# icyradio-main.net
KiCad netlist of a schematic drawn in EAGLE
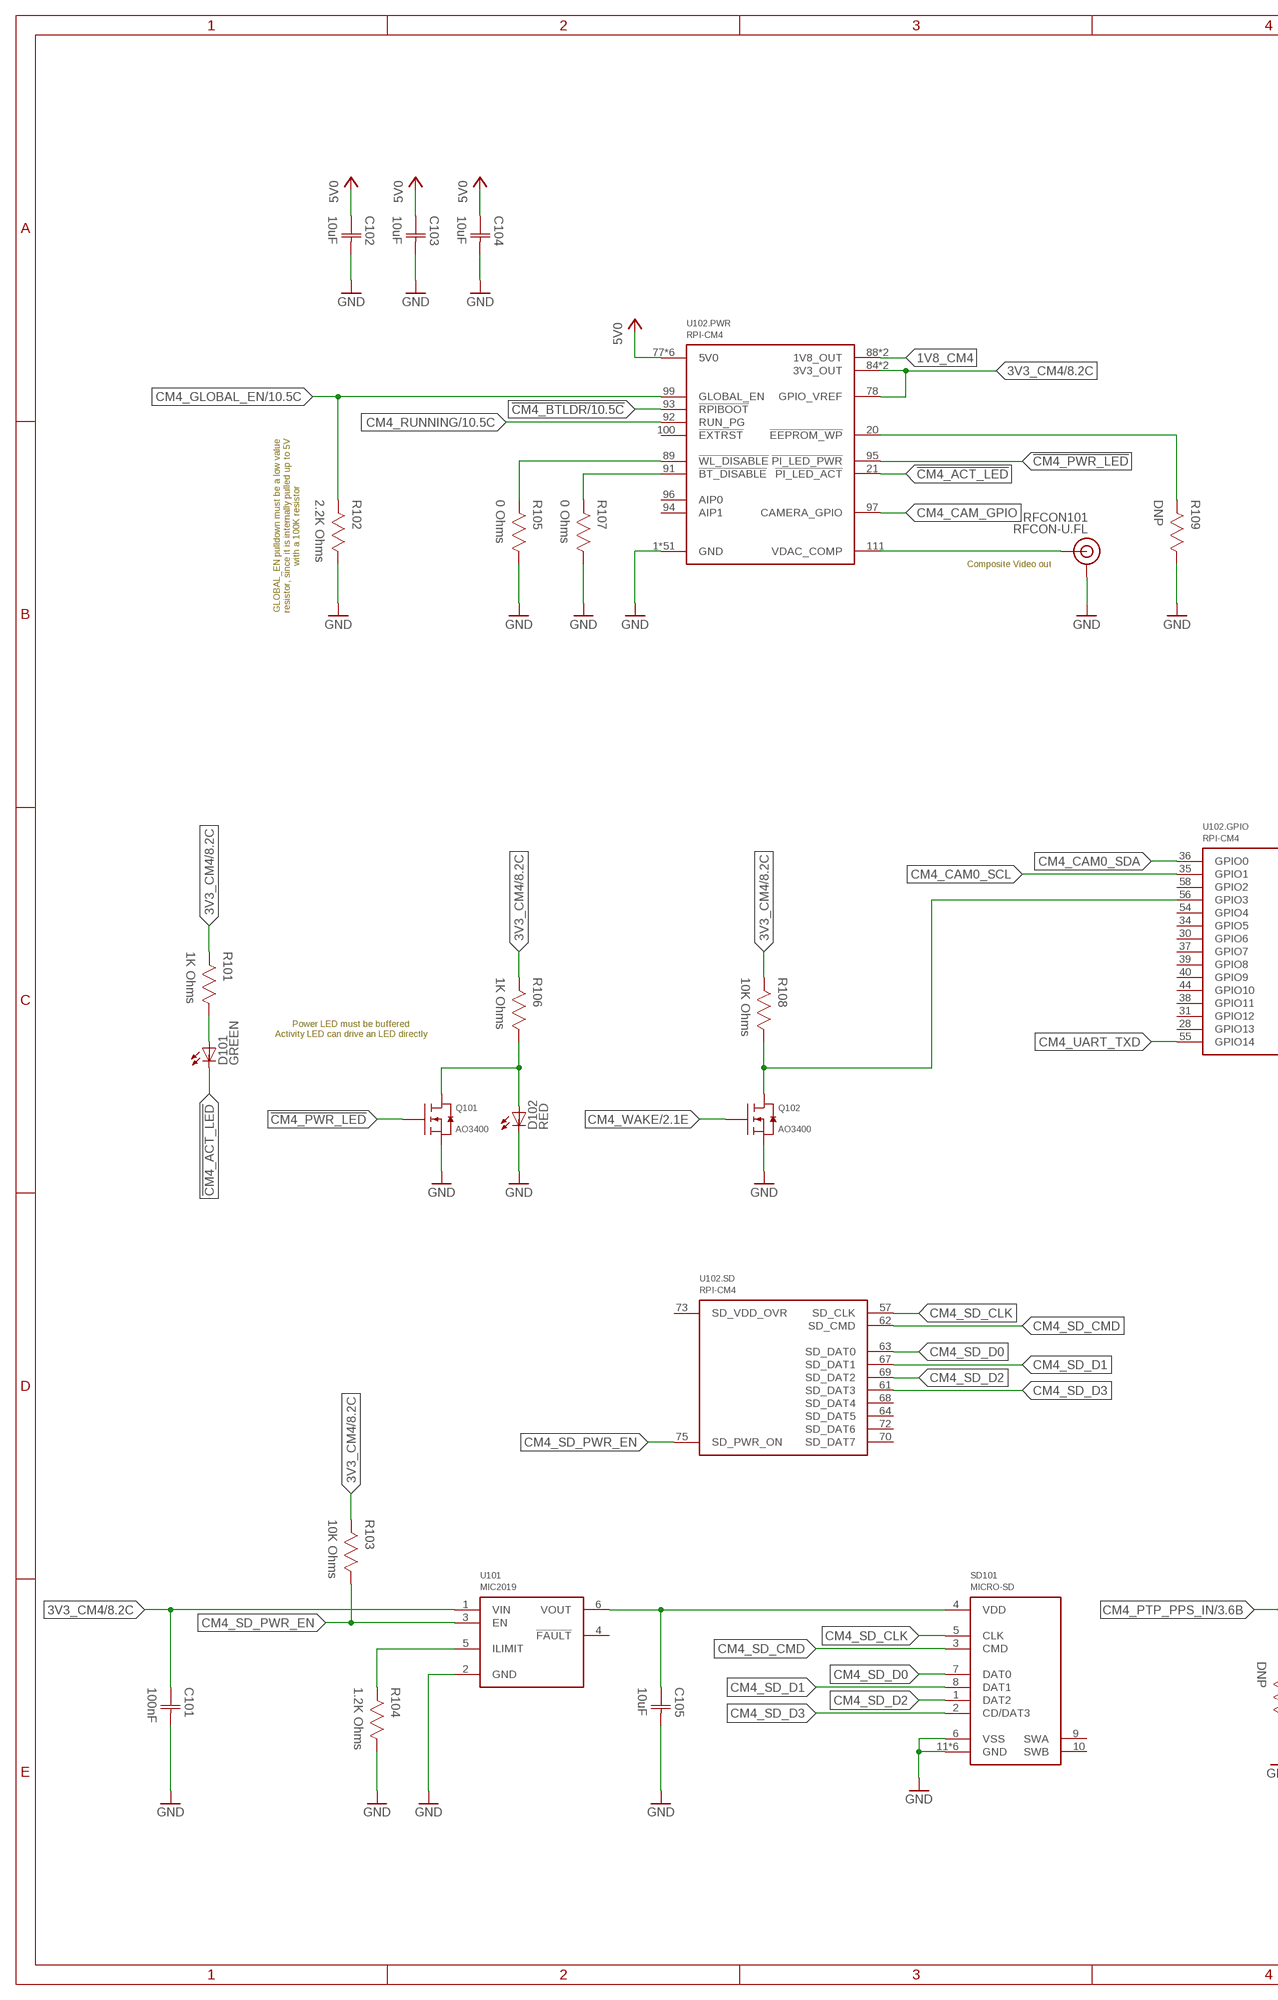
[diagram p0: schematic, sheet 1, part 1 of 2]
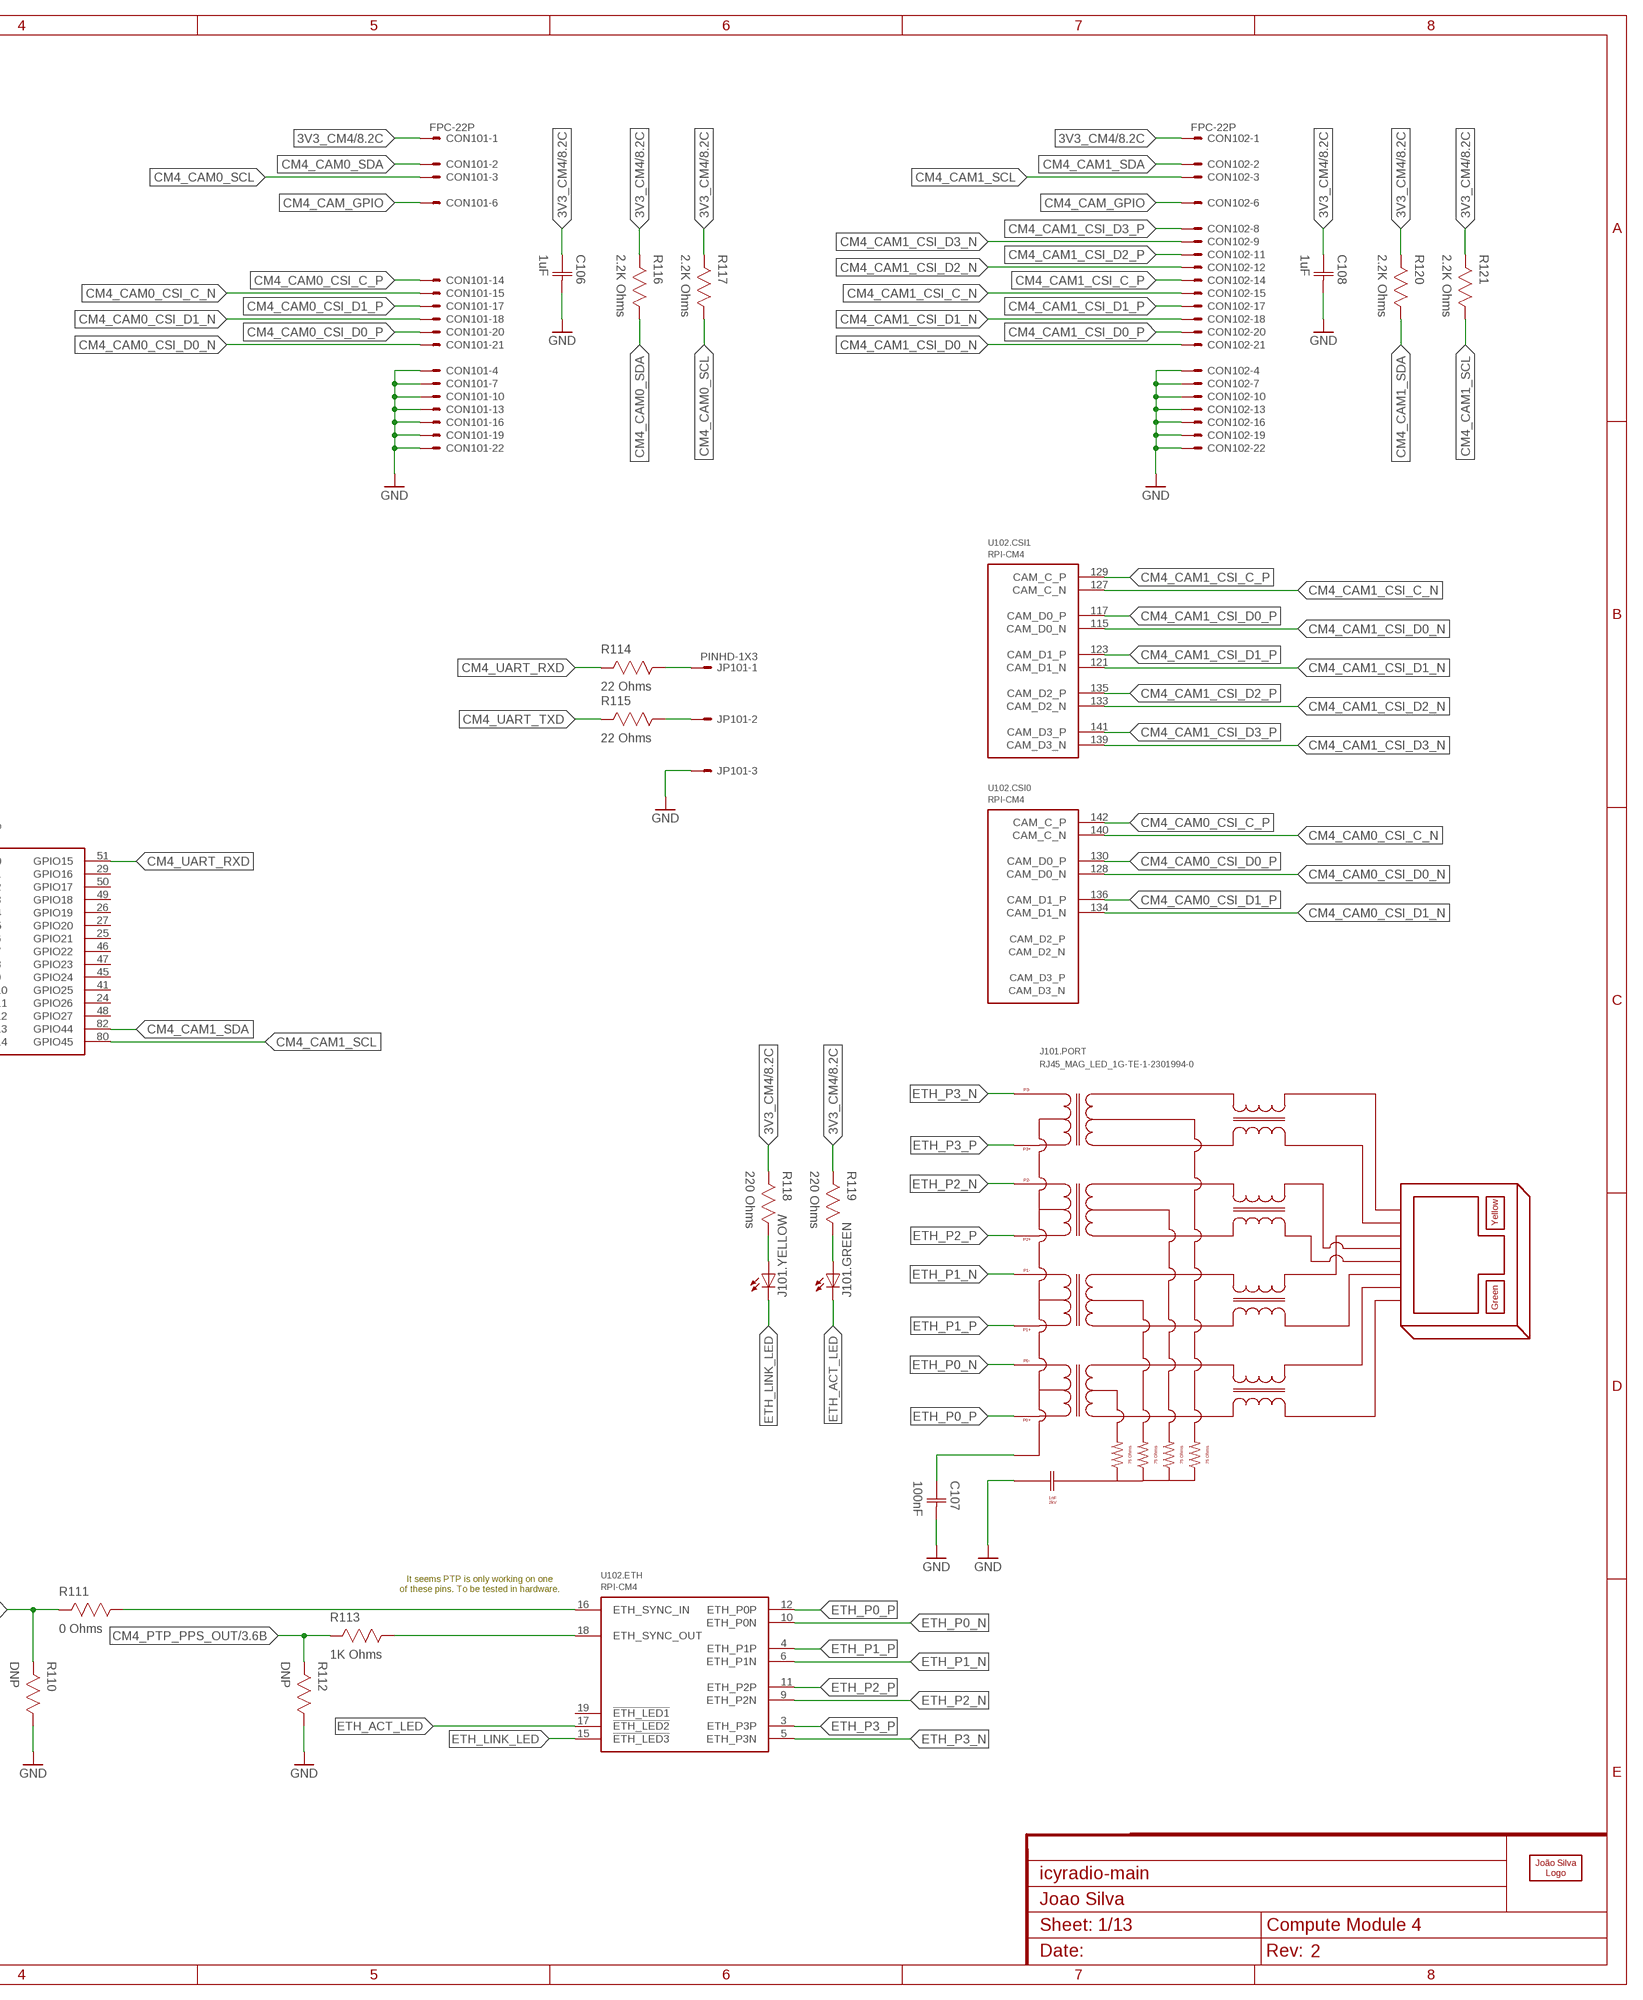
[diagram p1: schematic, sheet 1, part 2 of 2]
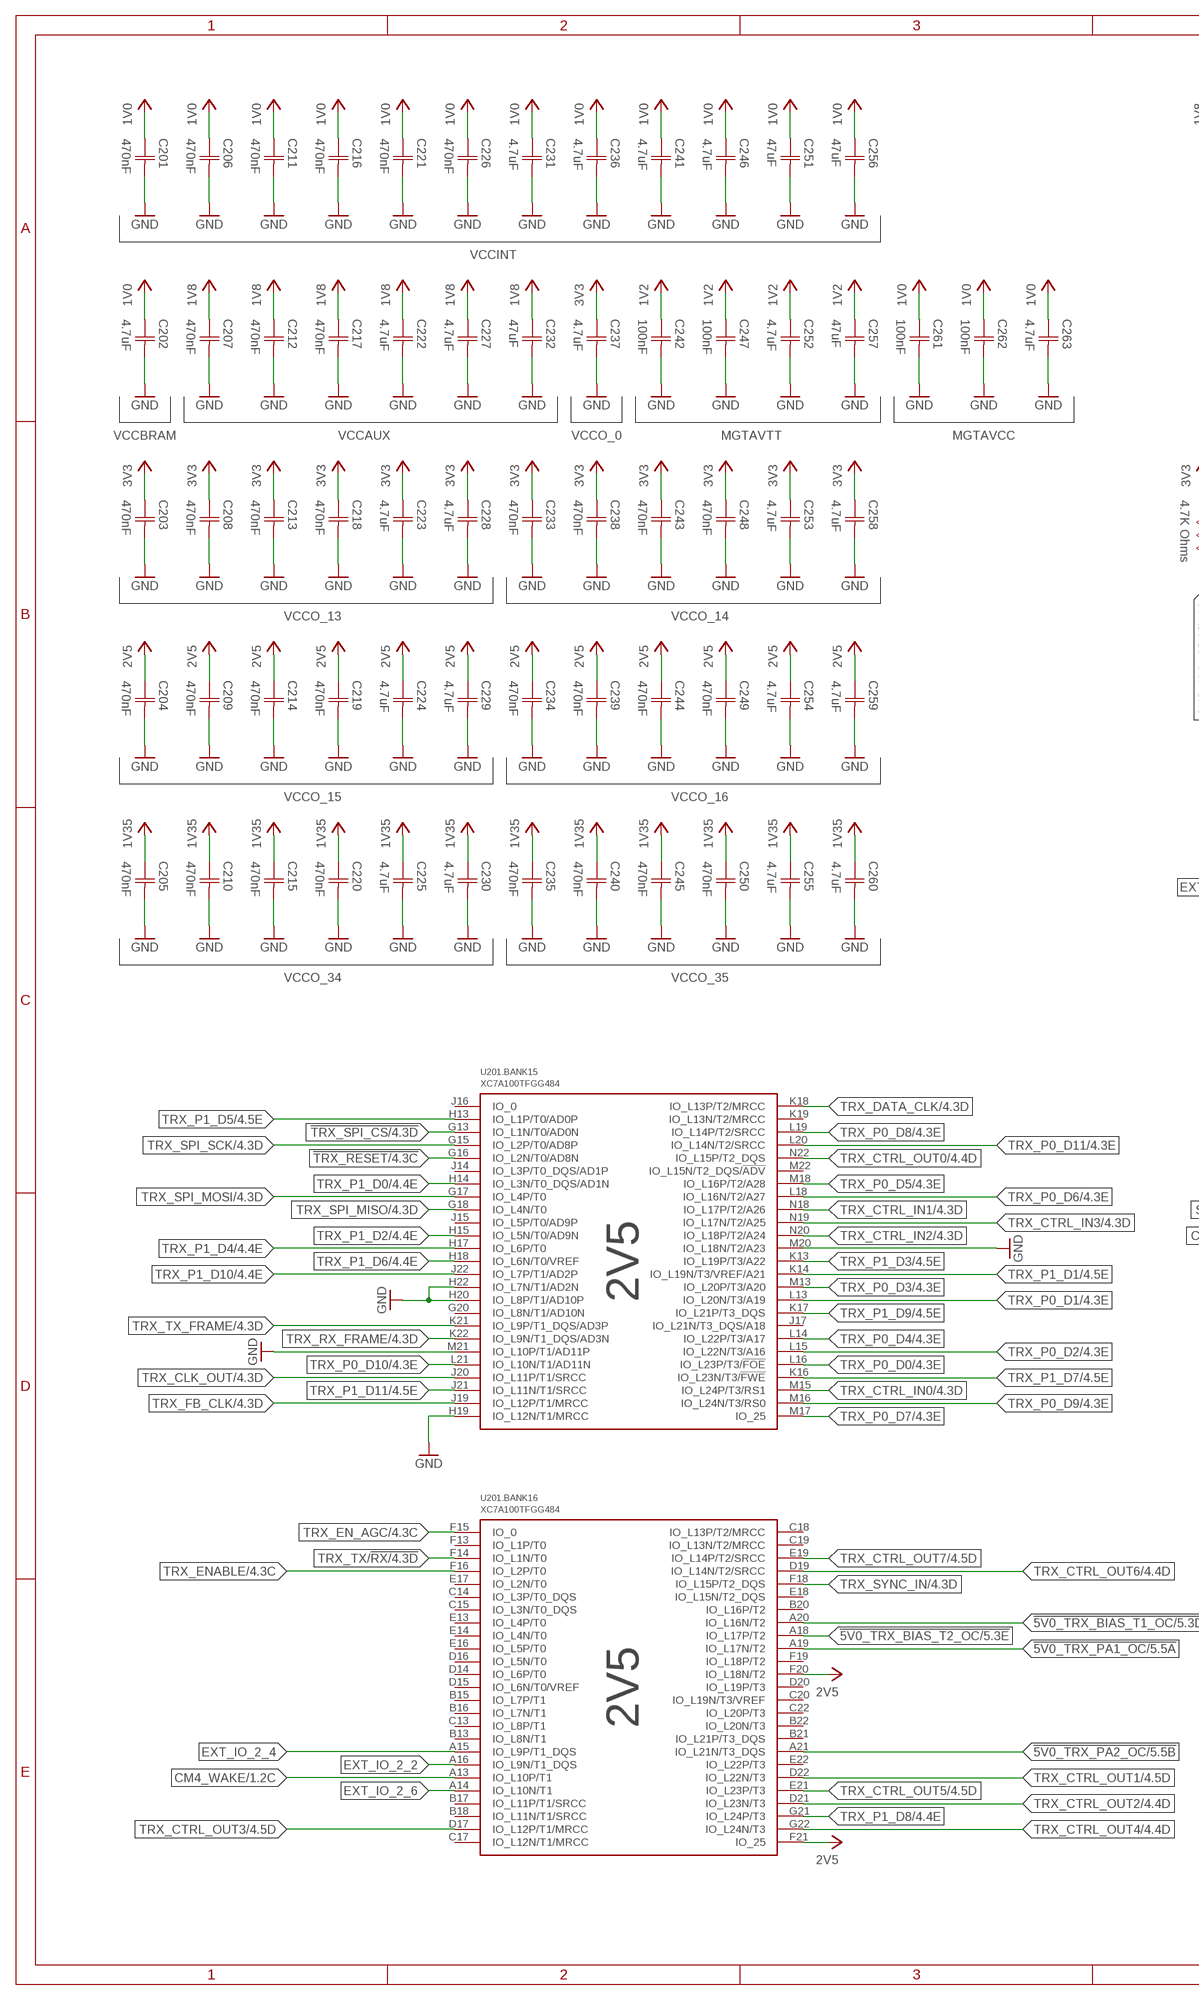
[diagram p2: schematic, sheet 2, part 1 of 2]
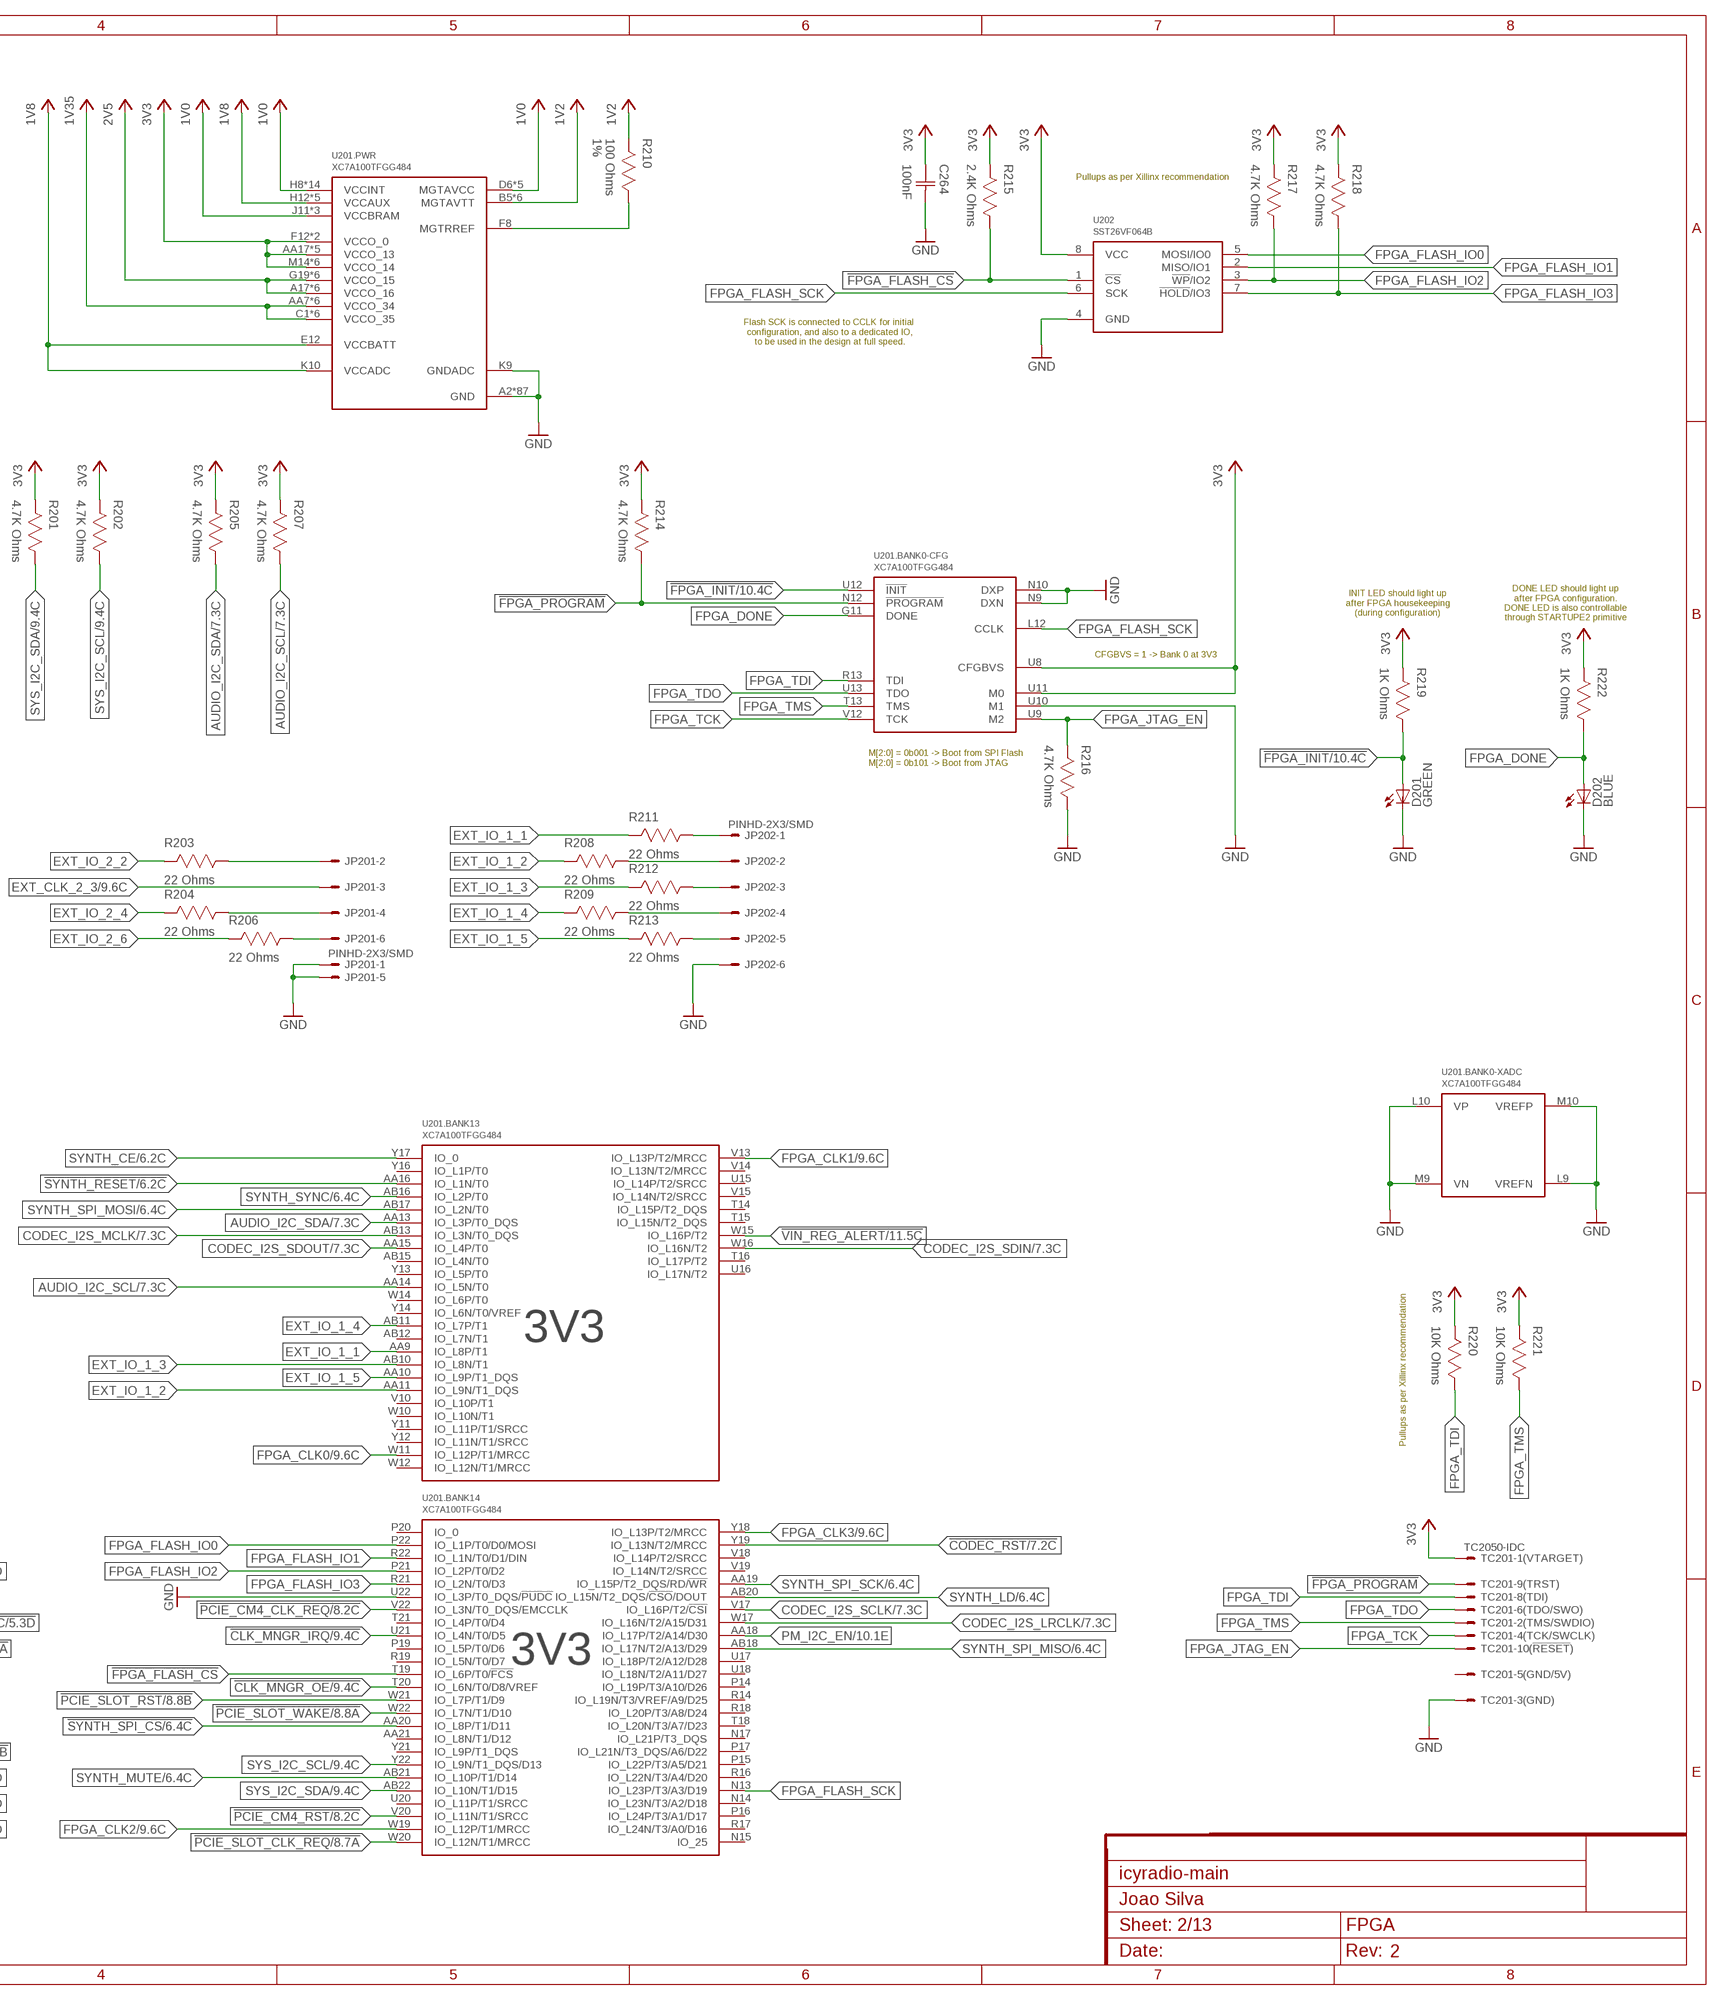
[diagram p3: schematic, sheet 2, part 2 of 2]
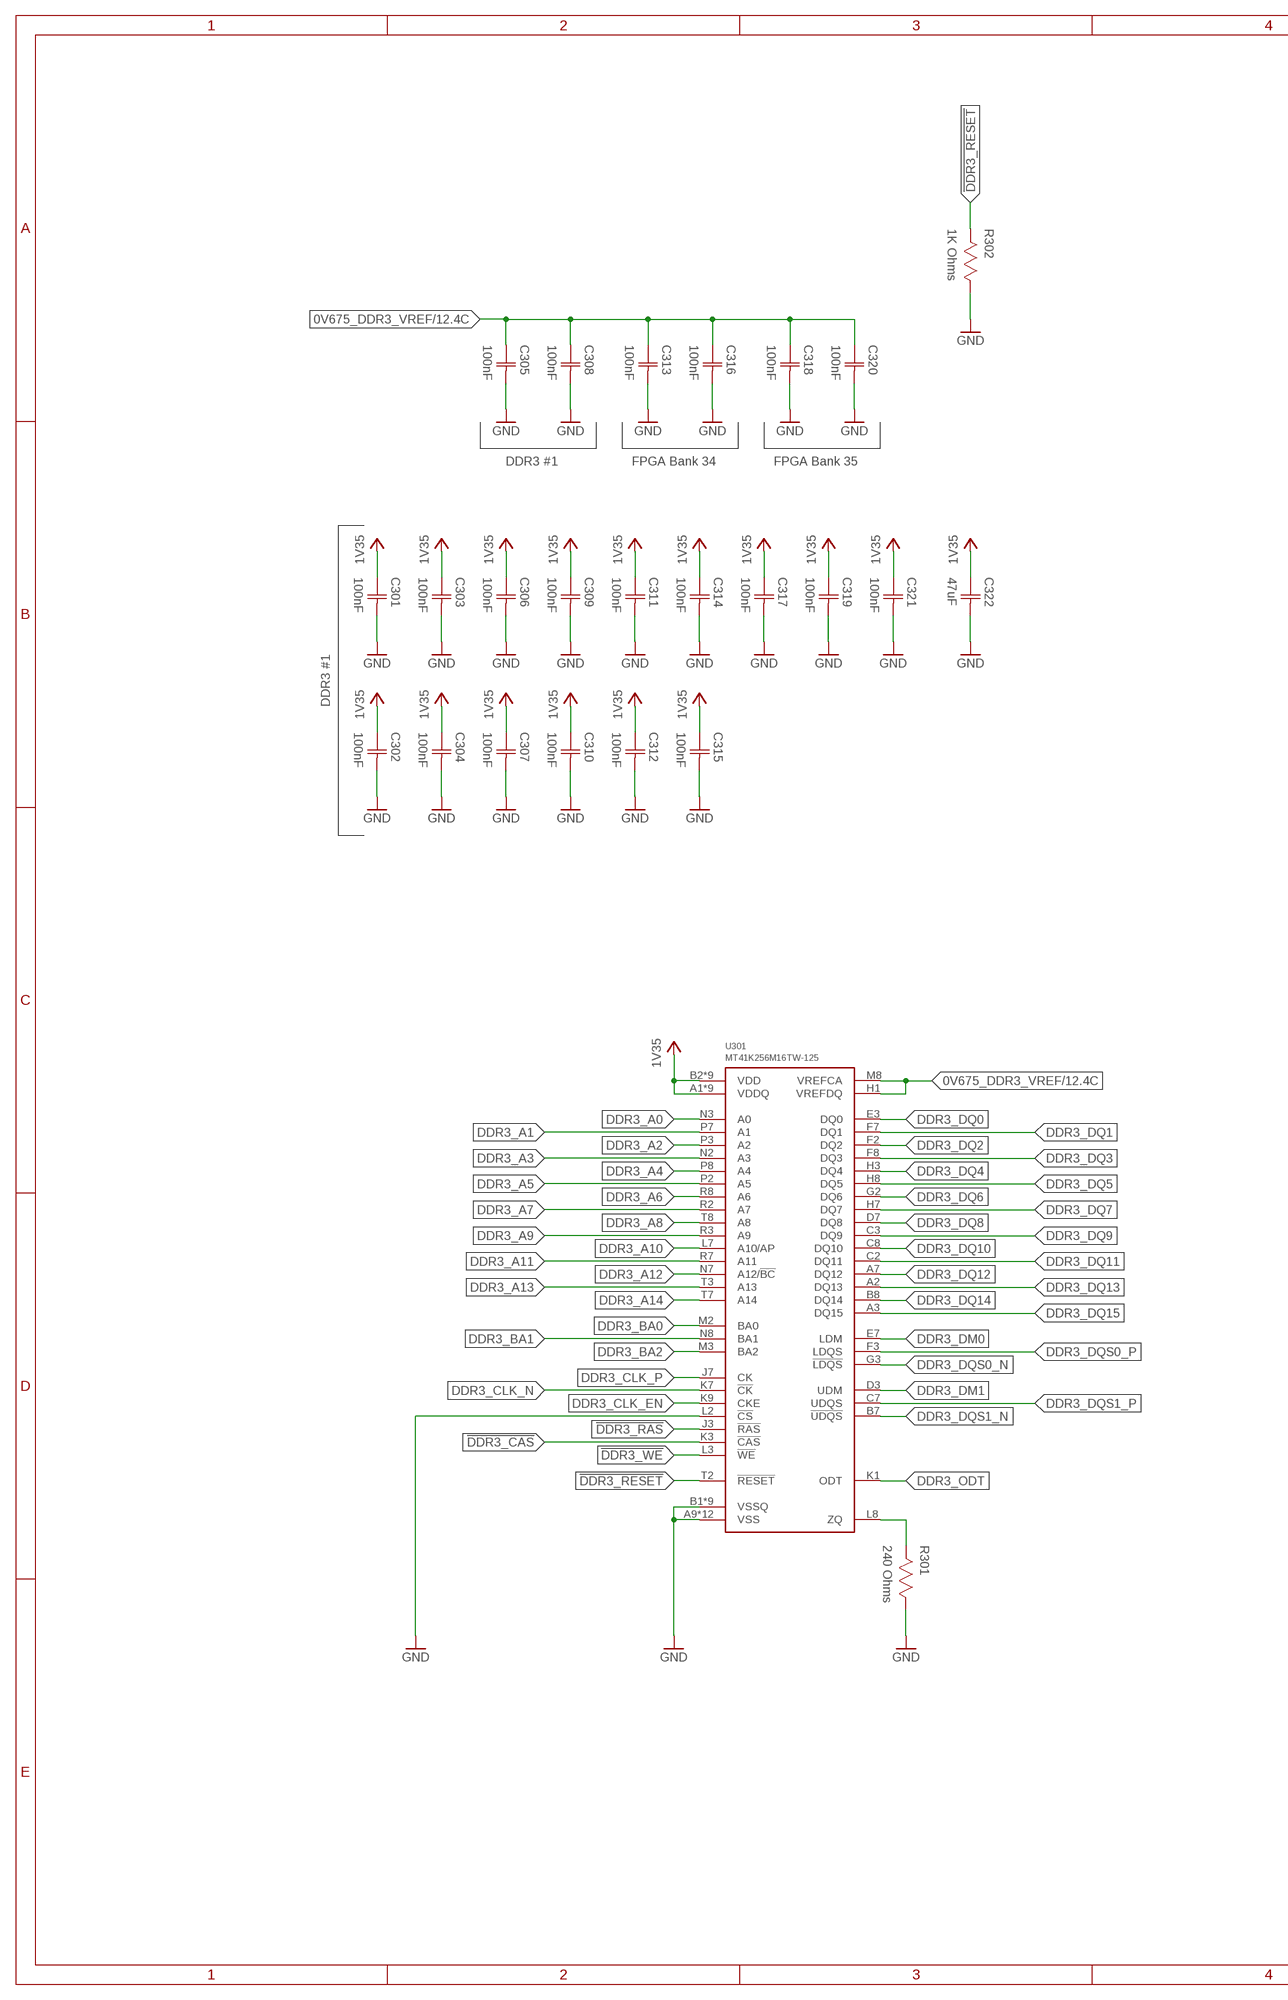
[diagram p4: schematic, sheet 3, part 1 of 2]
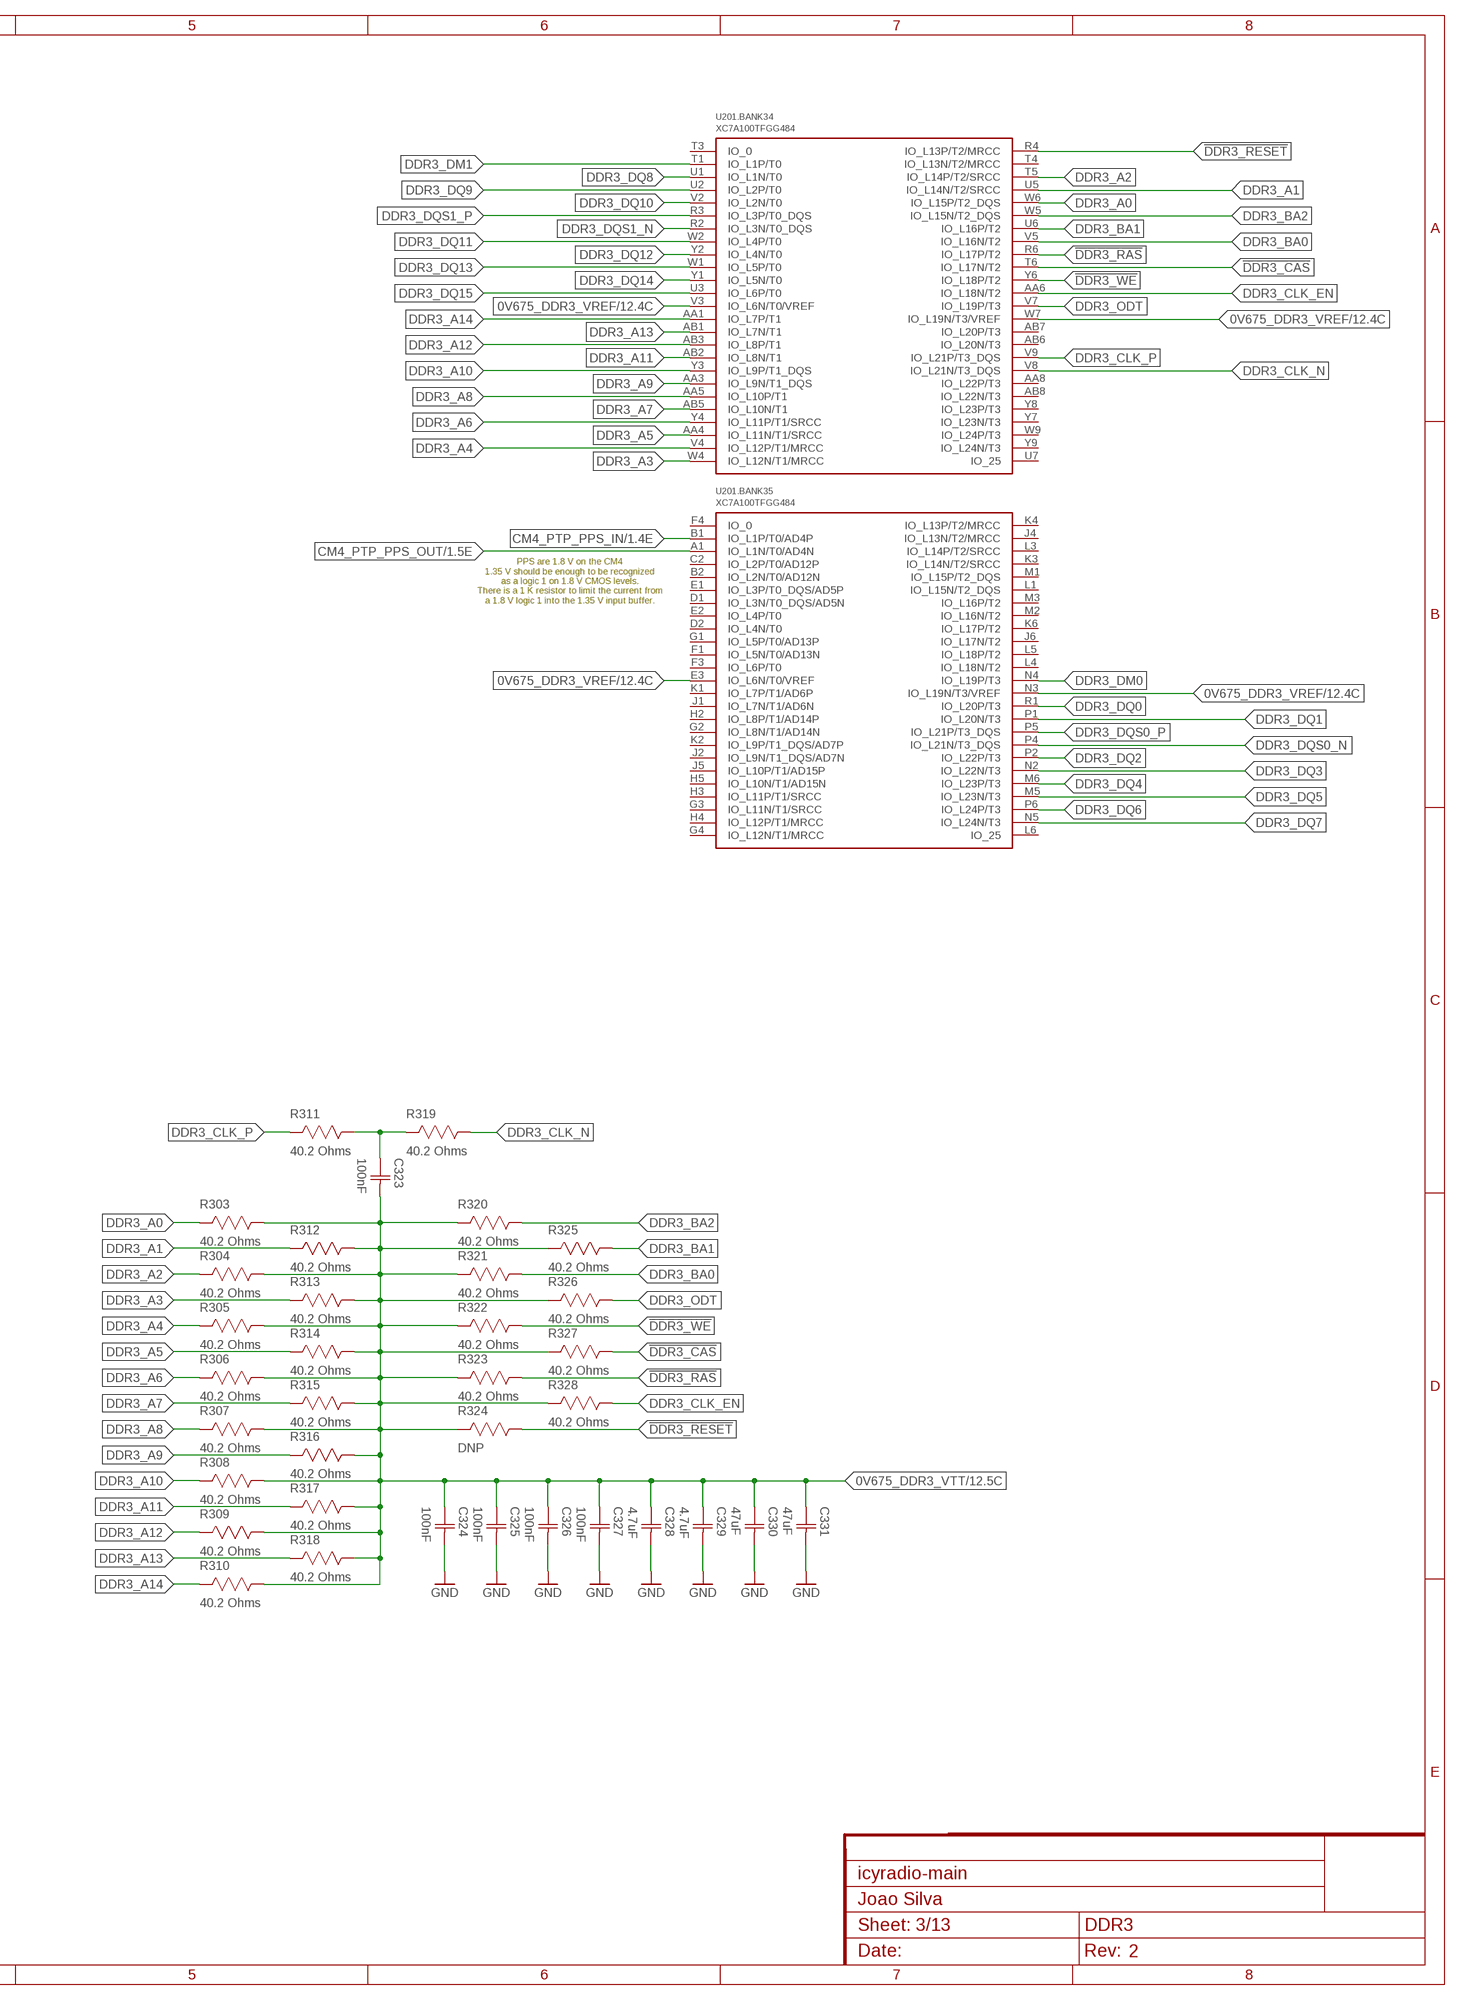
[diagram p5: schematic, sheet 3, part 2 of 2]
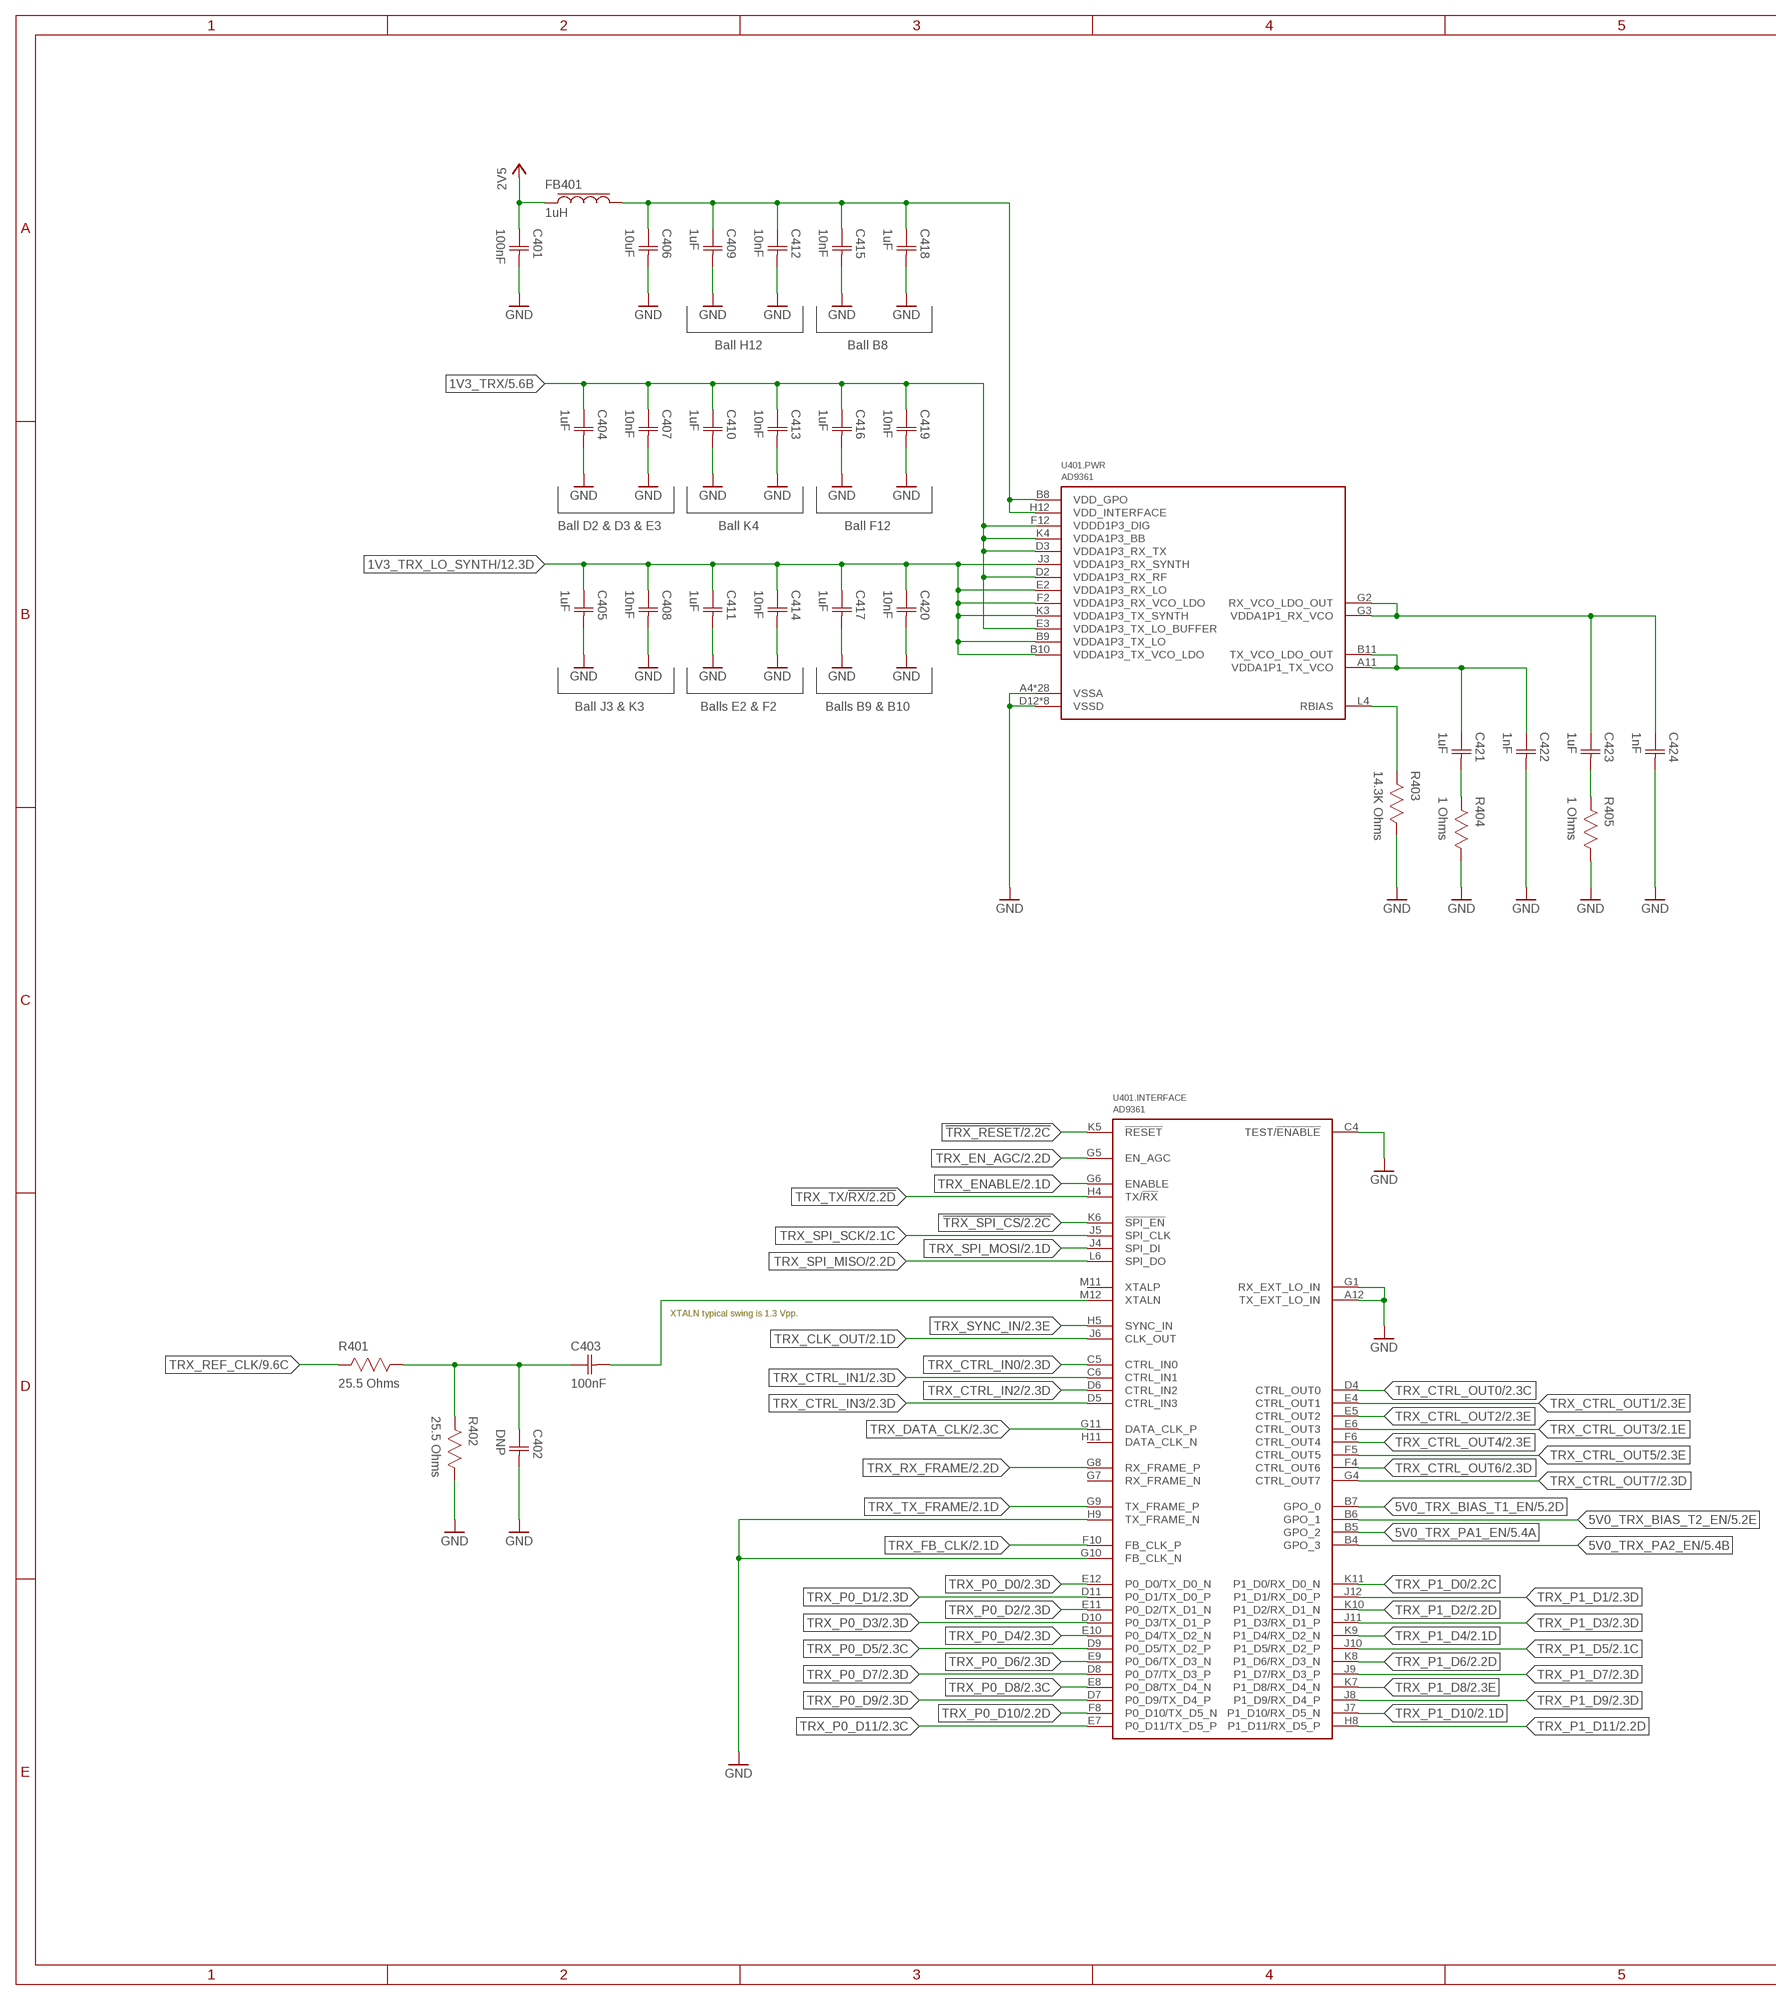
[diagram p6: schematic, sheet 4, part 1 of 2]
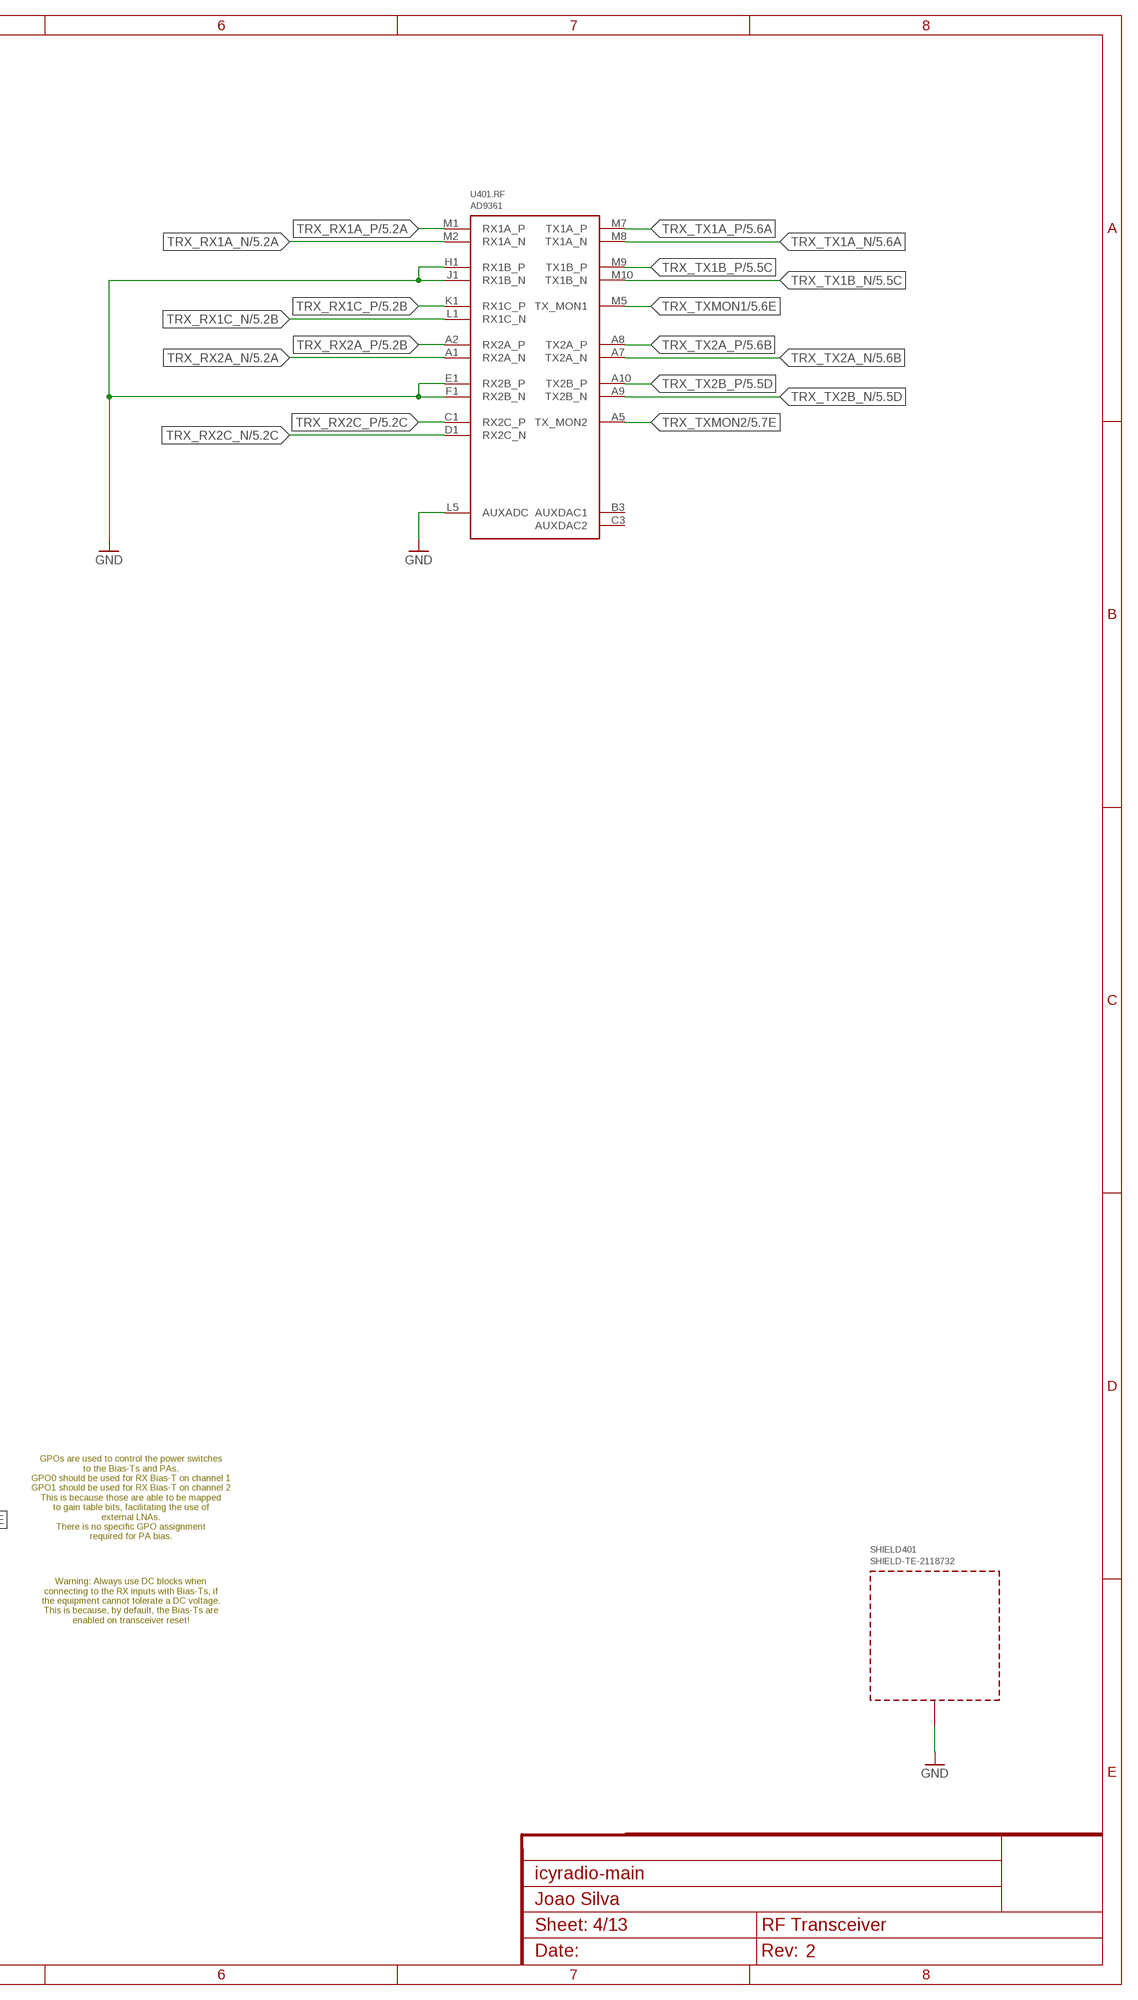
[diagram p7: schematic, sheet 4, part 2 of 2]
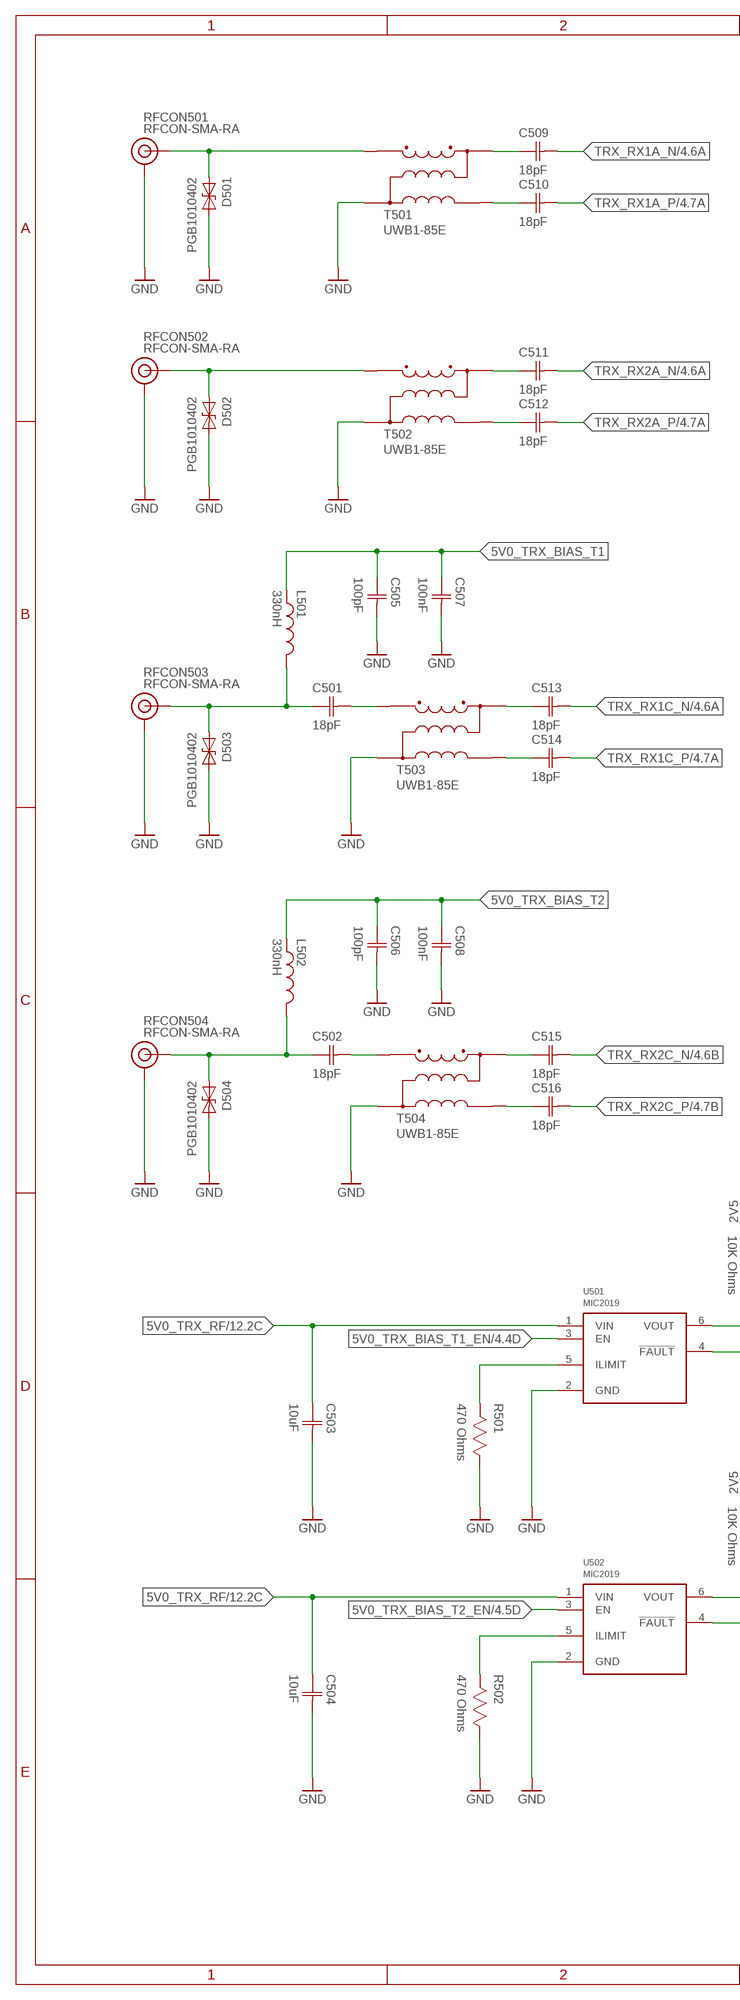
[diagram p8: schematic, sheet 5, part 1 of 2]
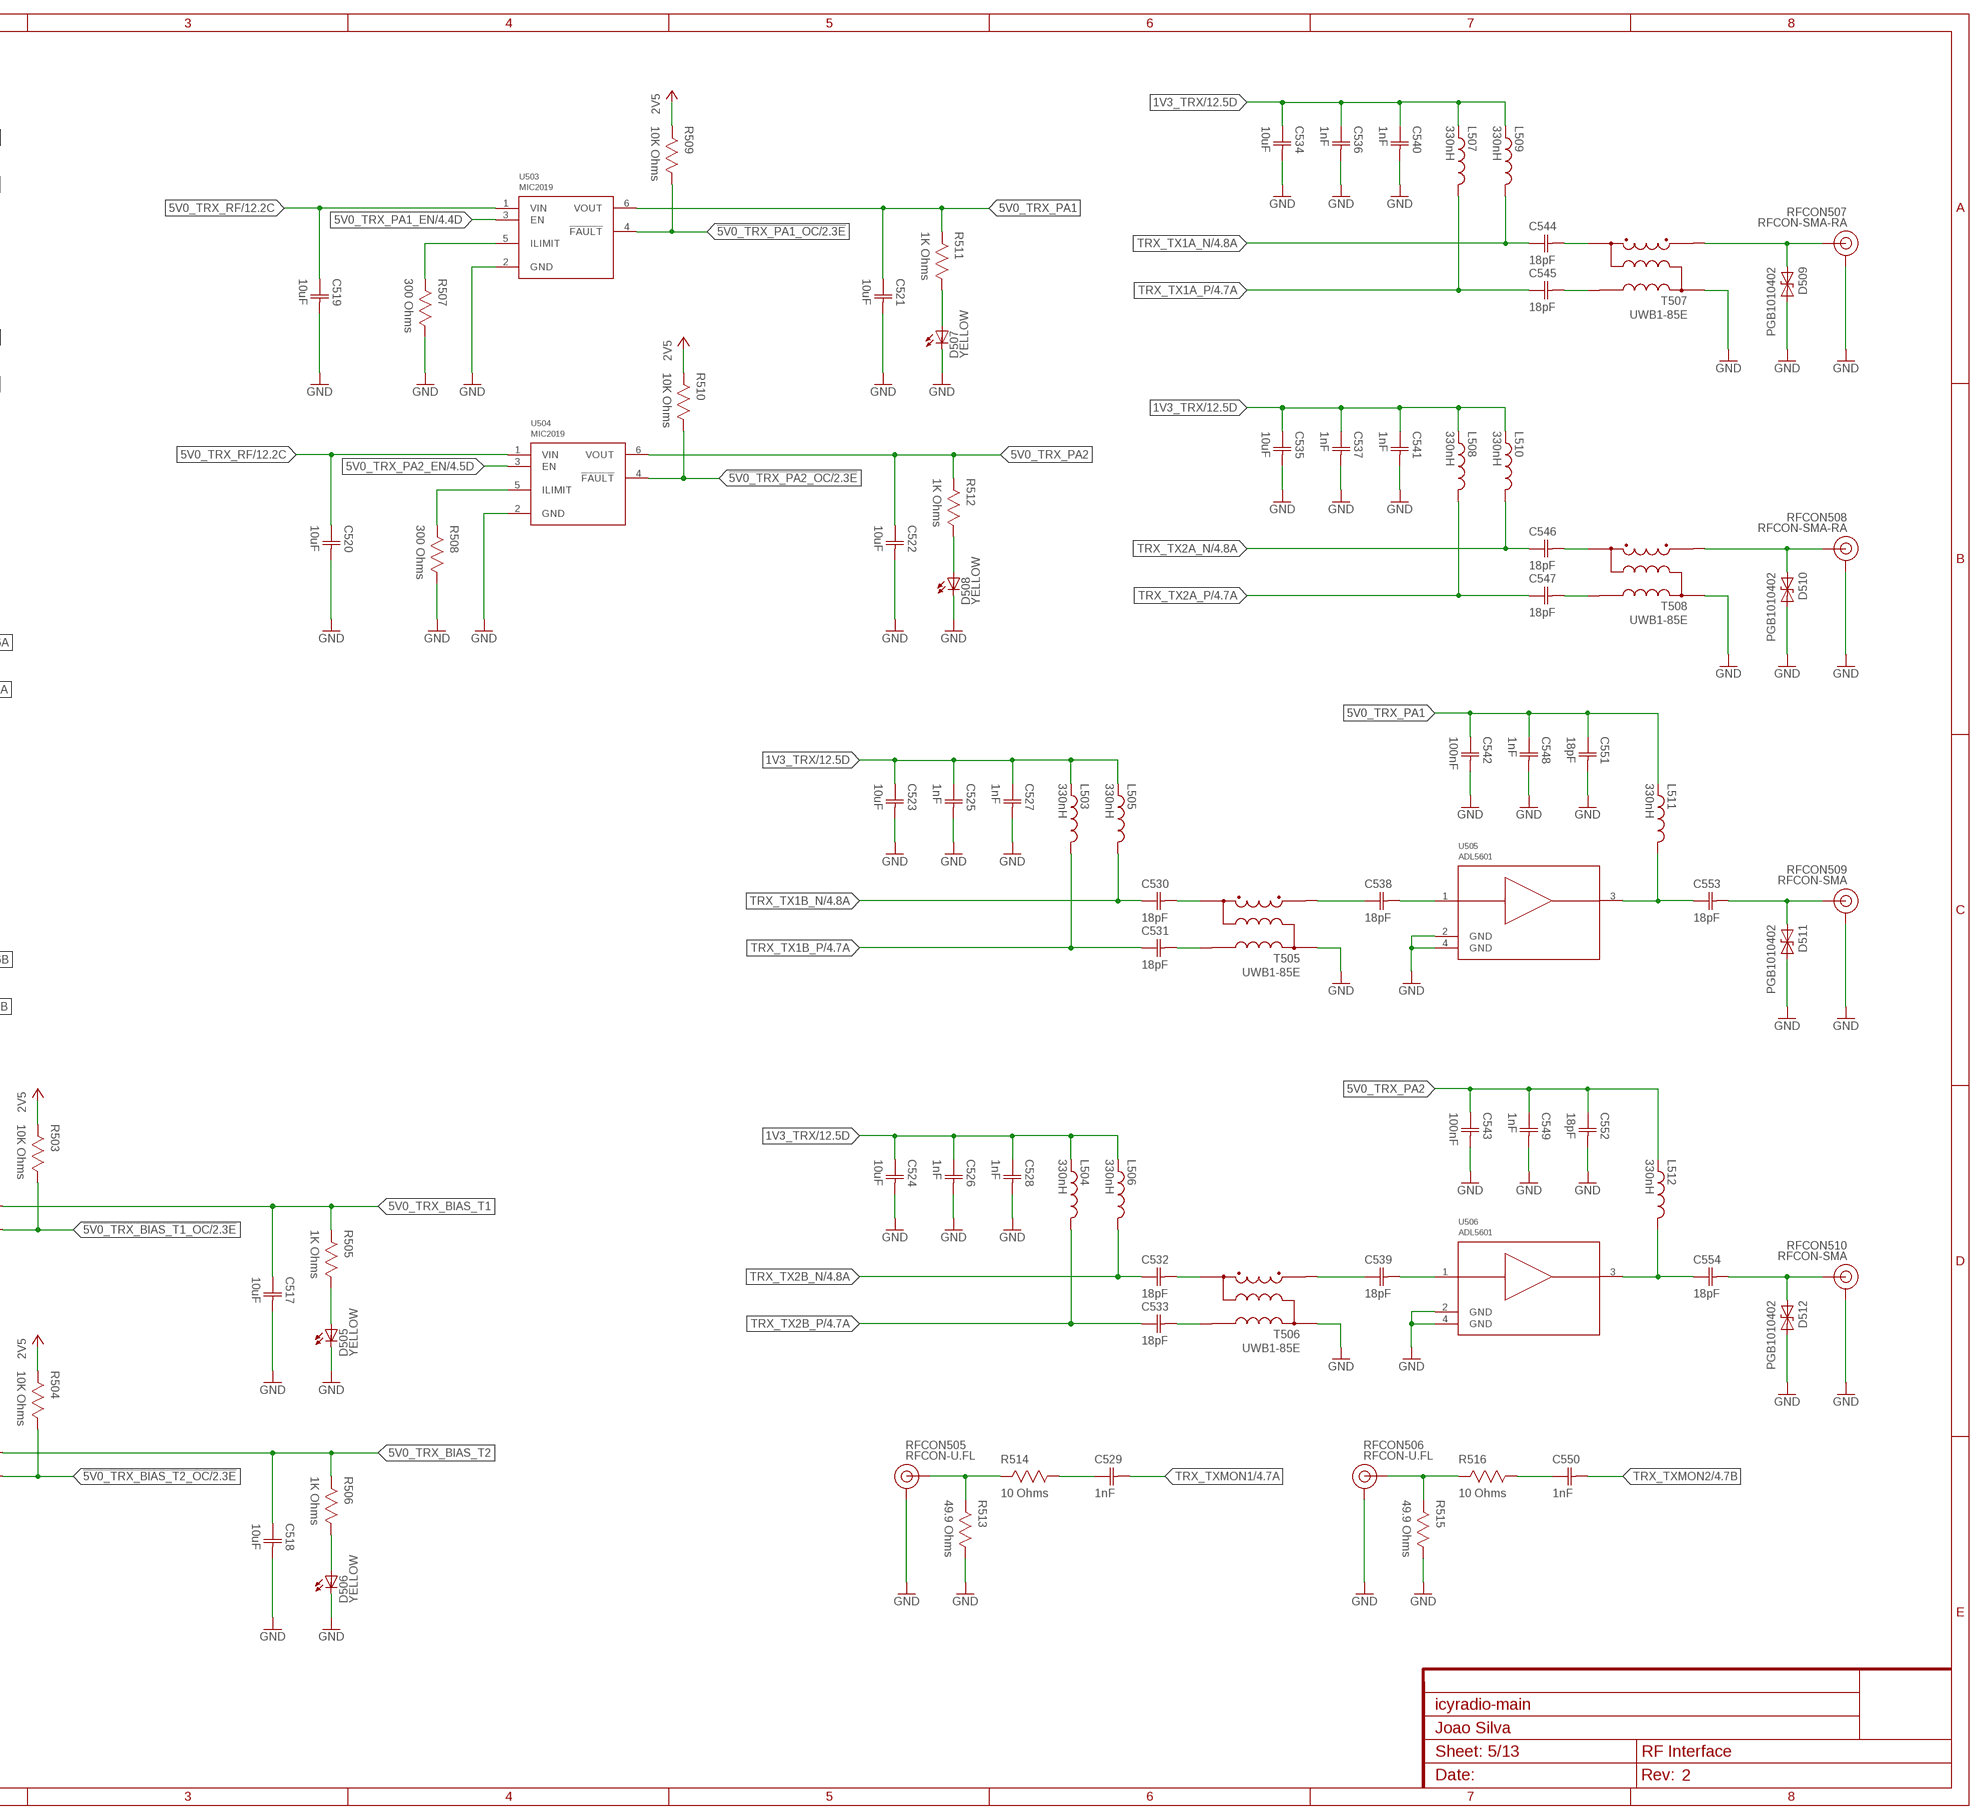
[diagram p9: schematic, sheet 5, part 2 of 2]
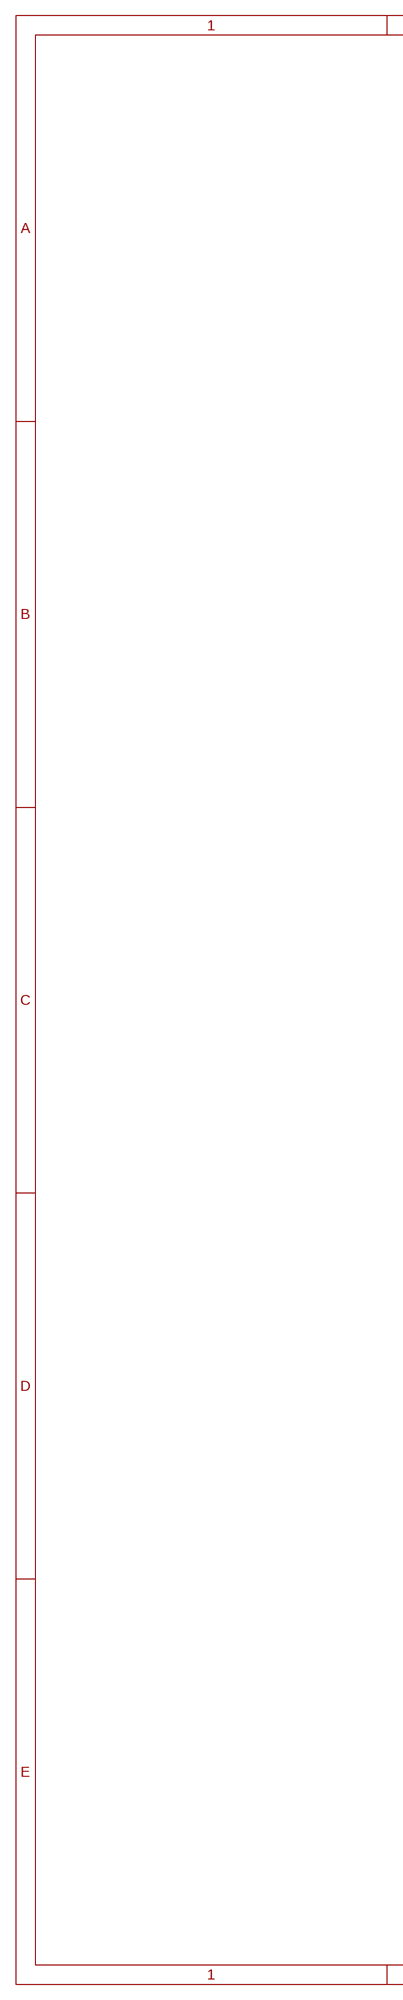
[diagram p10: schematic, sheet 6, part 1 of 2]
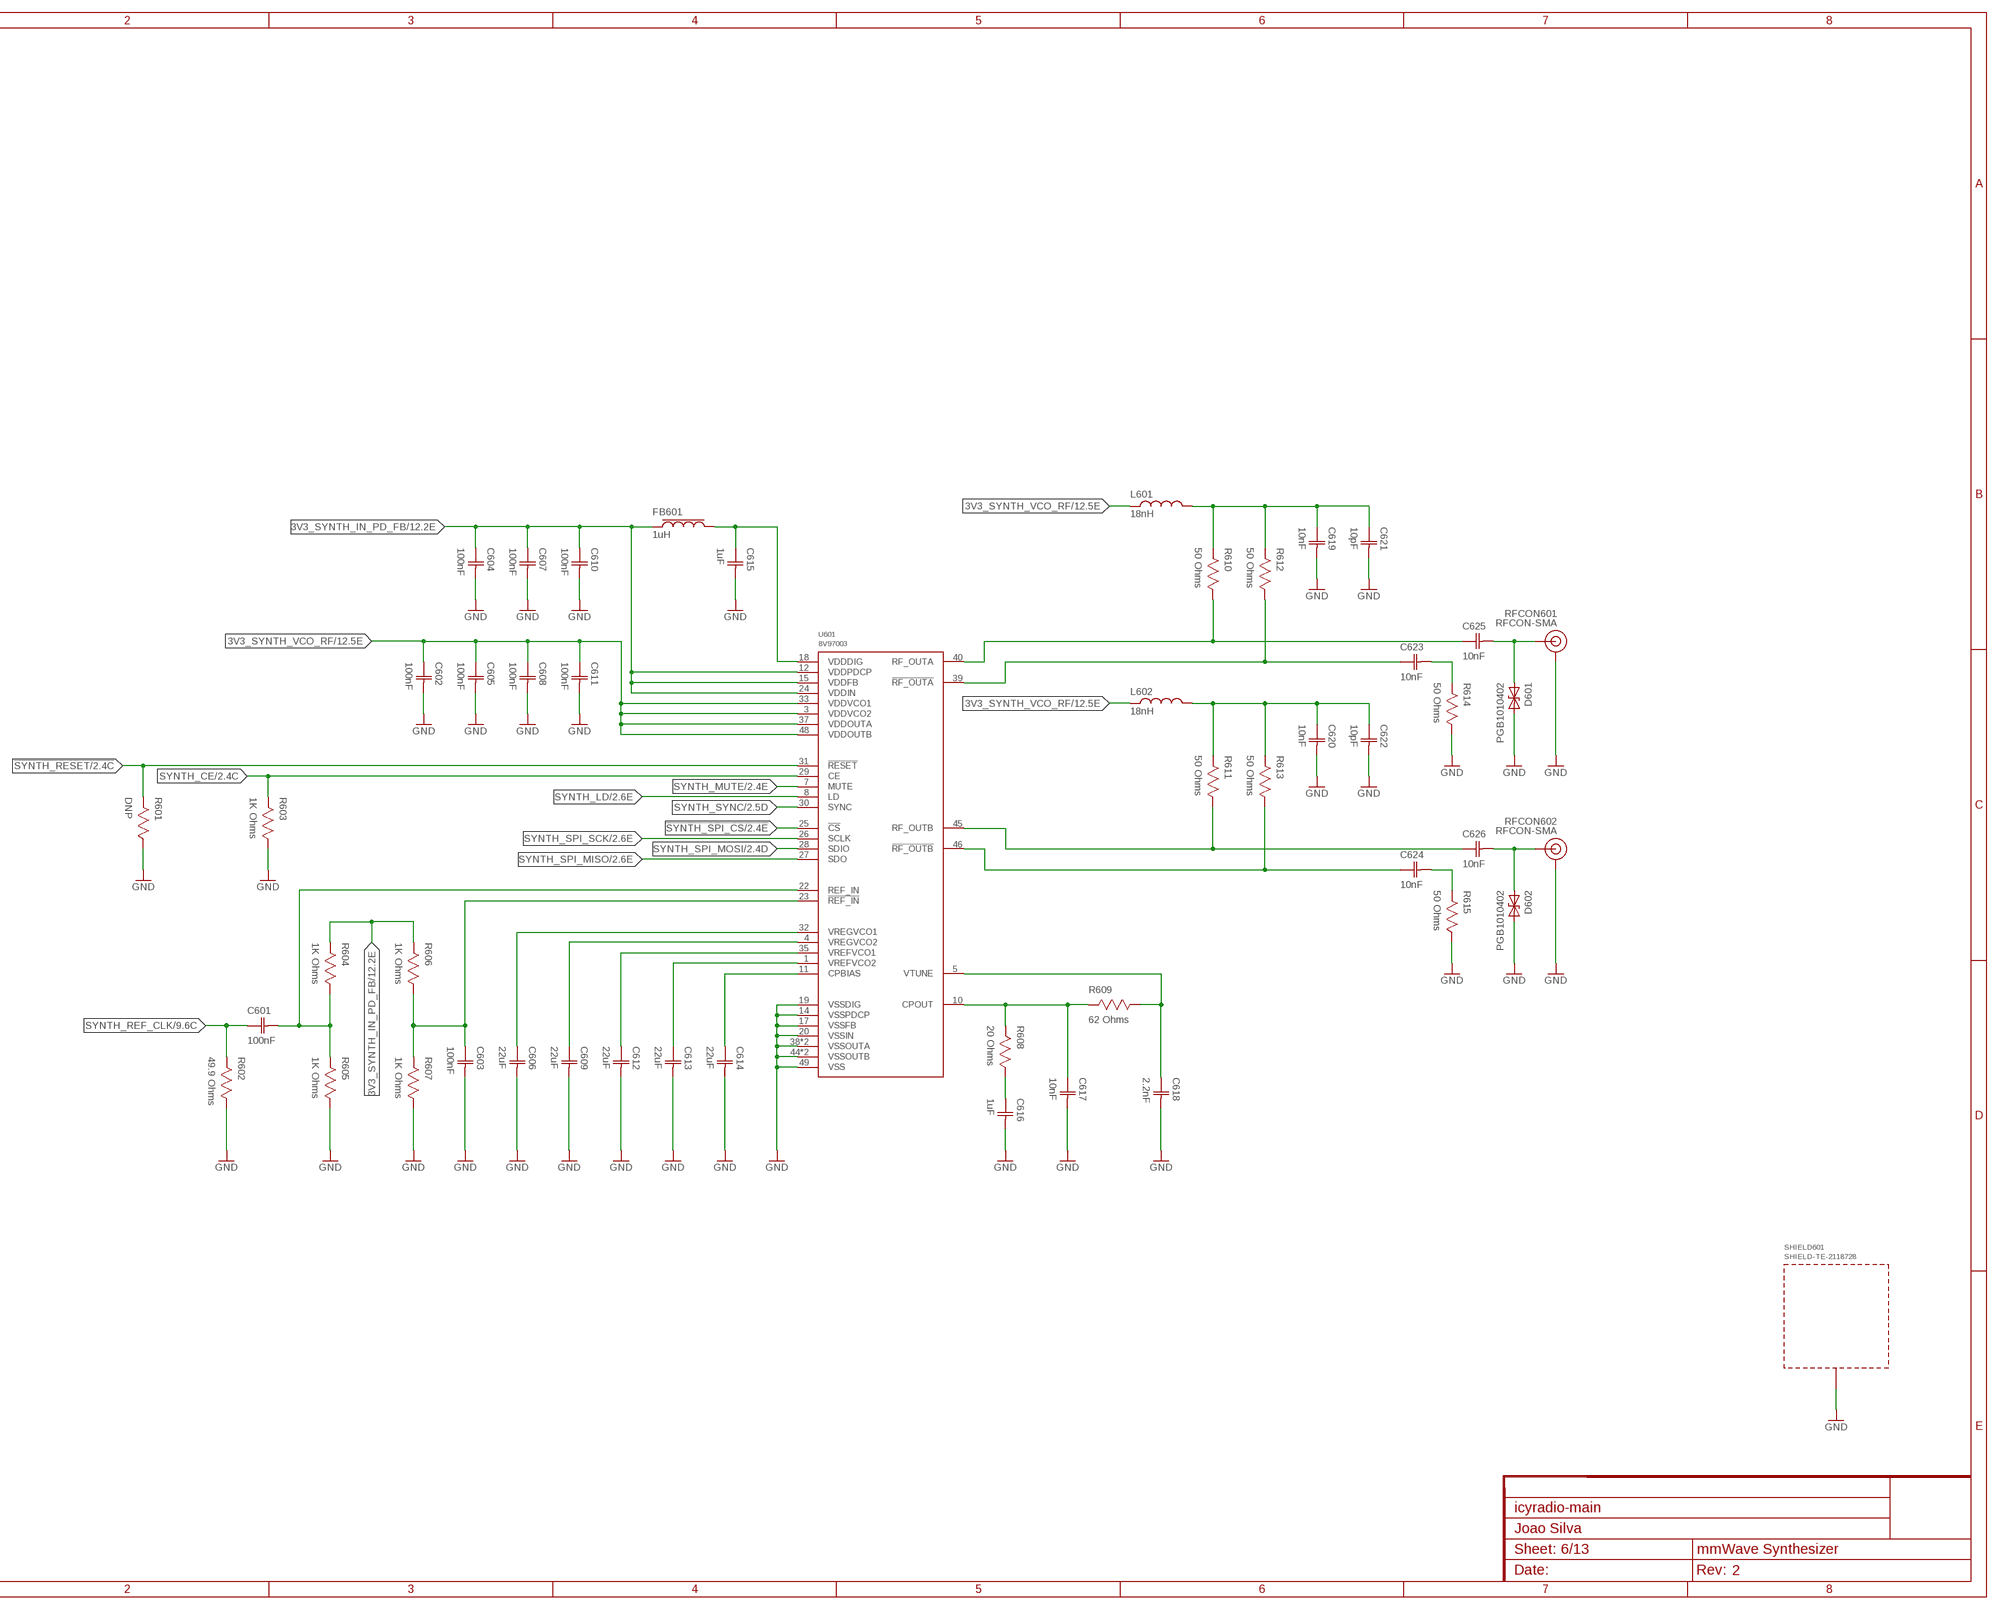
[diagram p11: schematic, sheet 6, part 2 of 2]
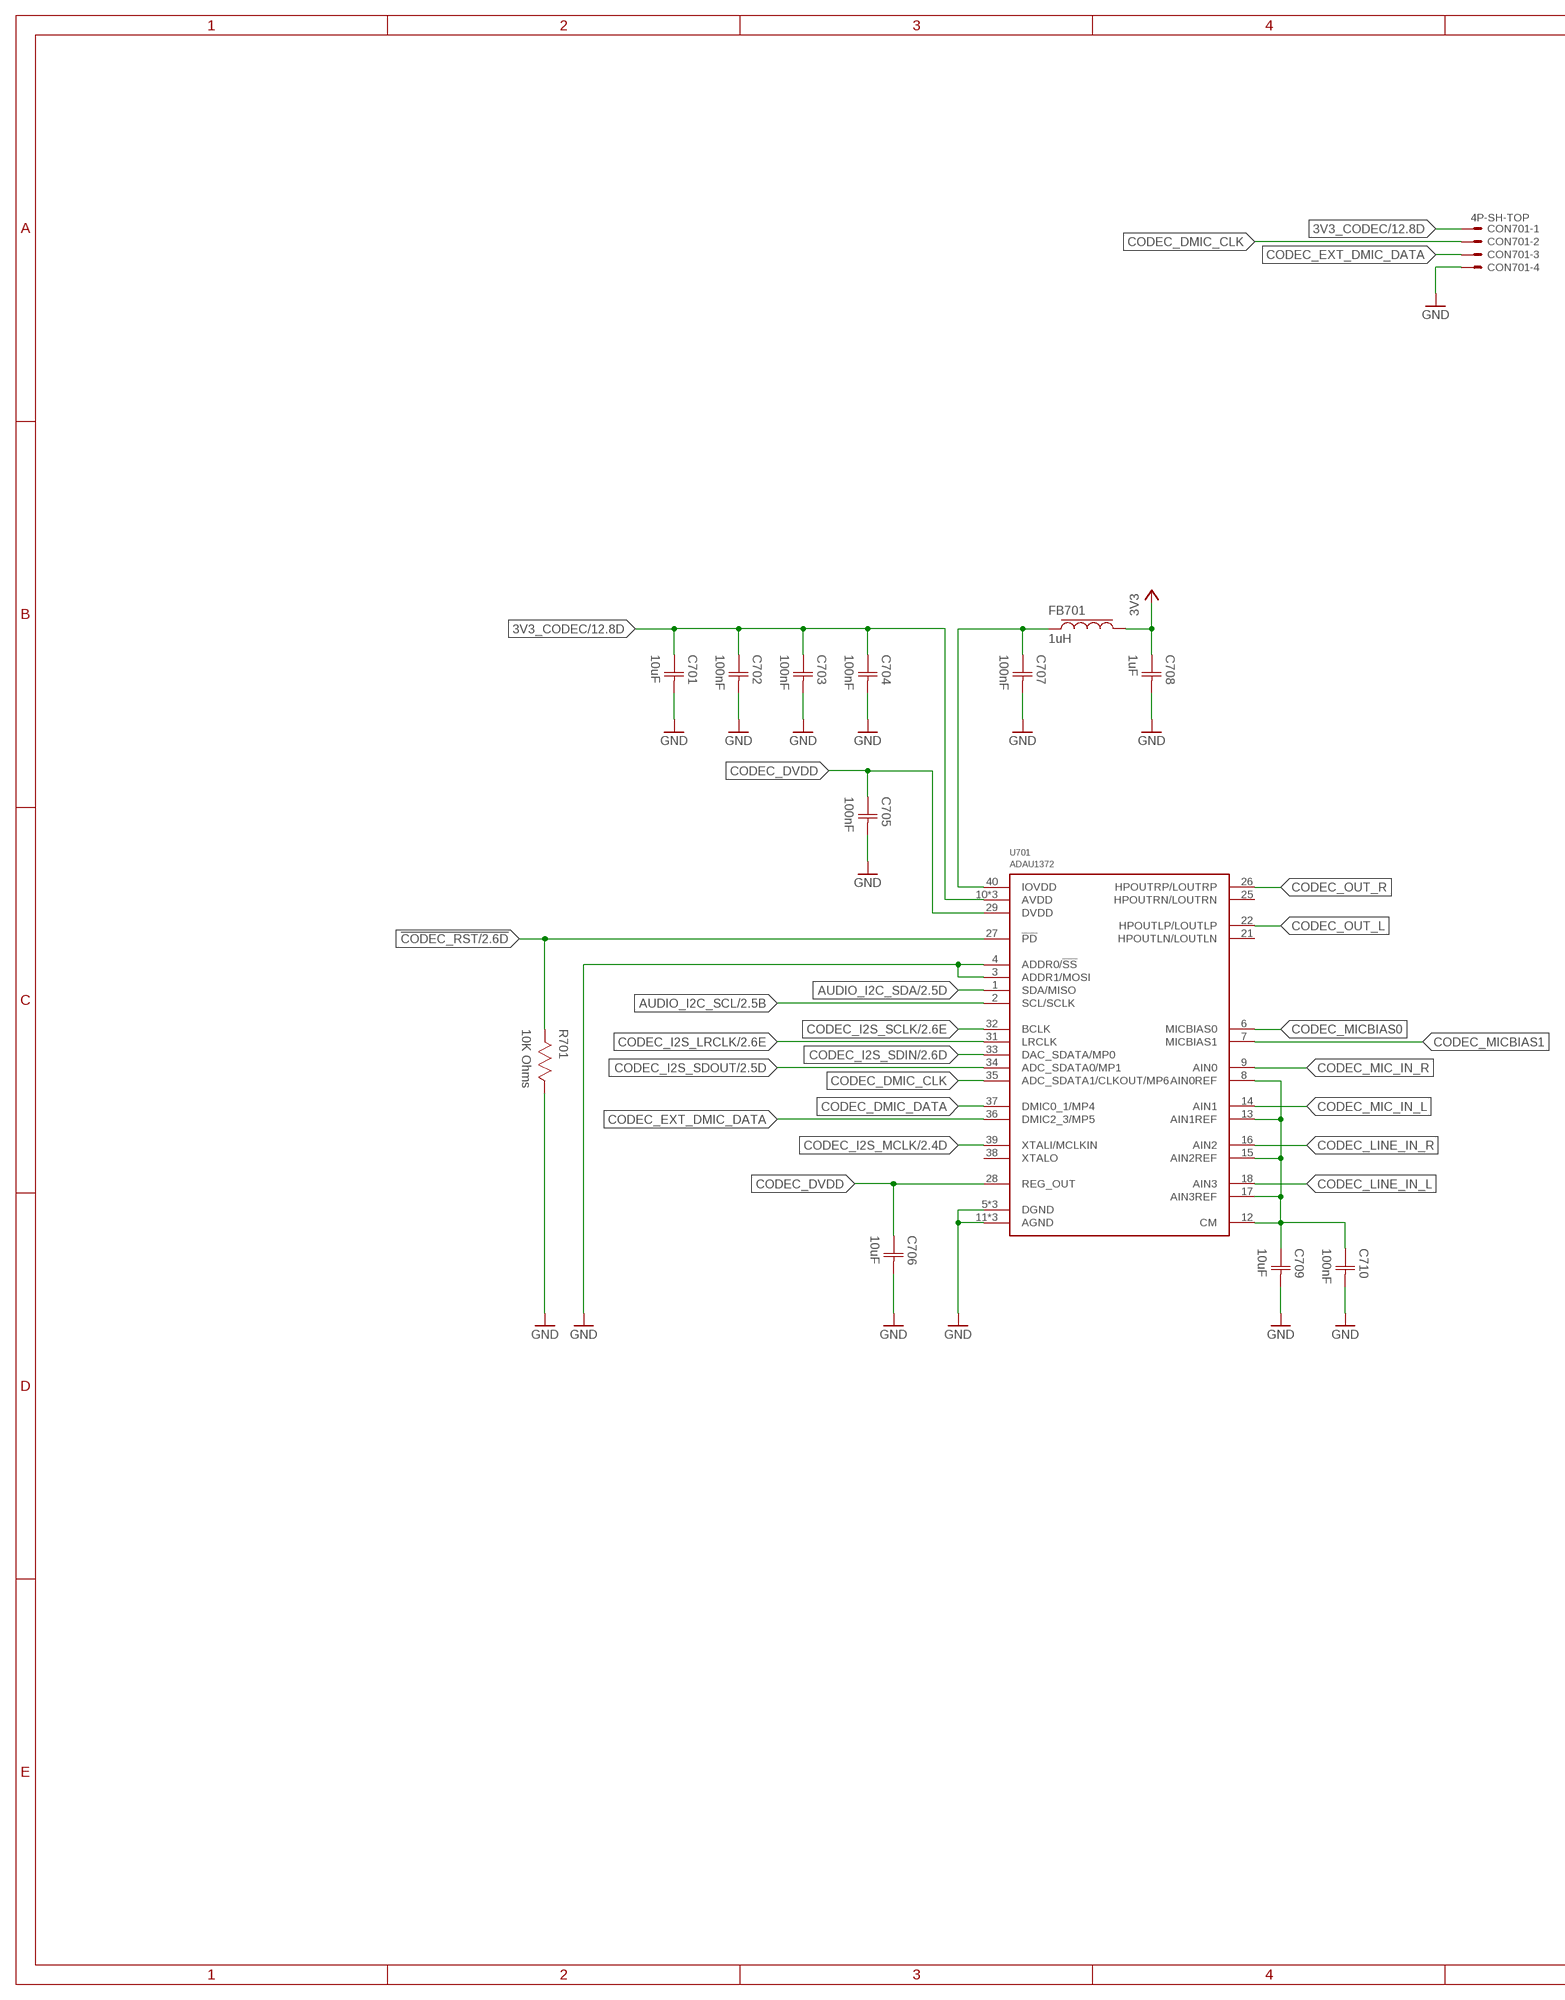
[diagram p12: schematic, sheet 7, part 1 of 2]
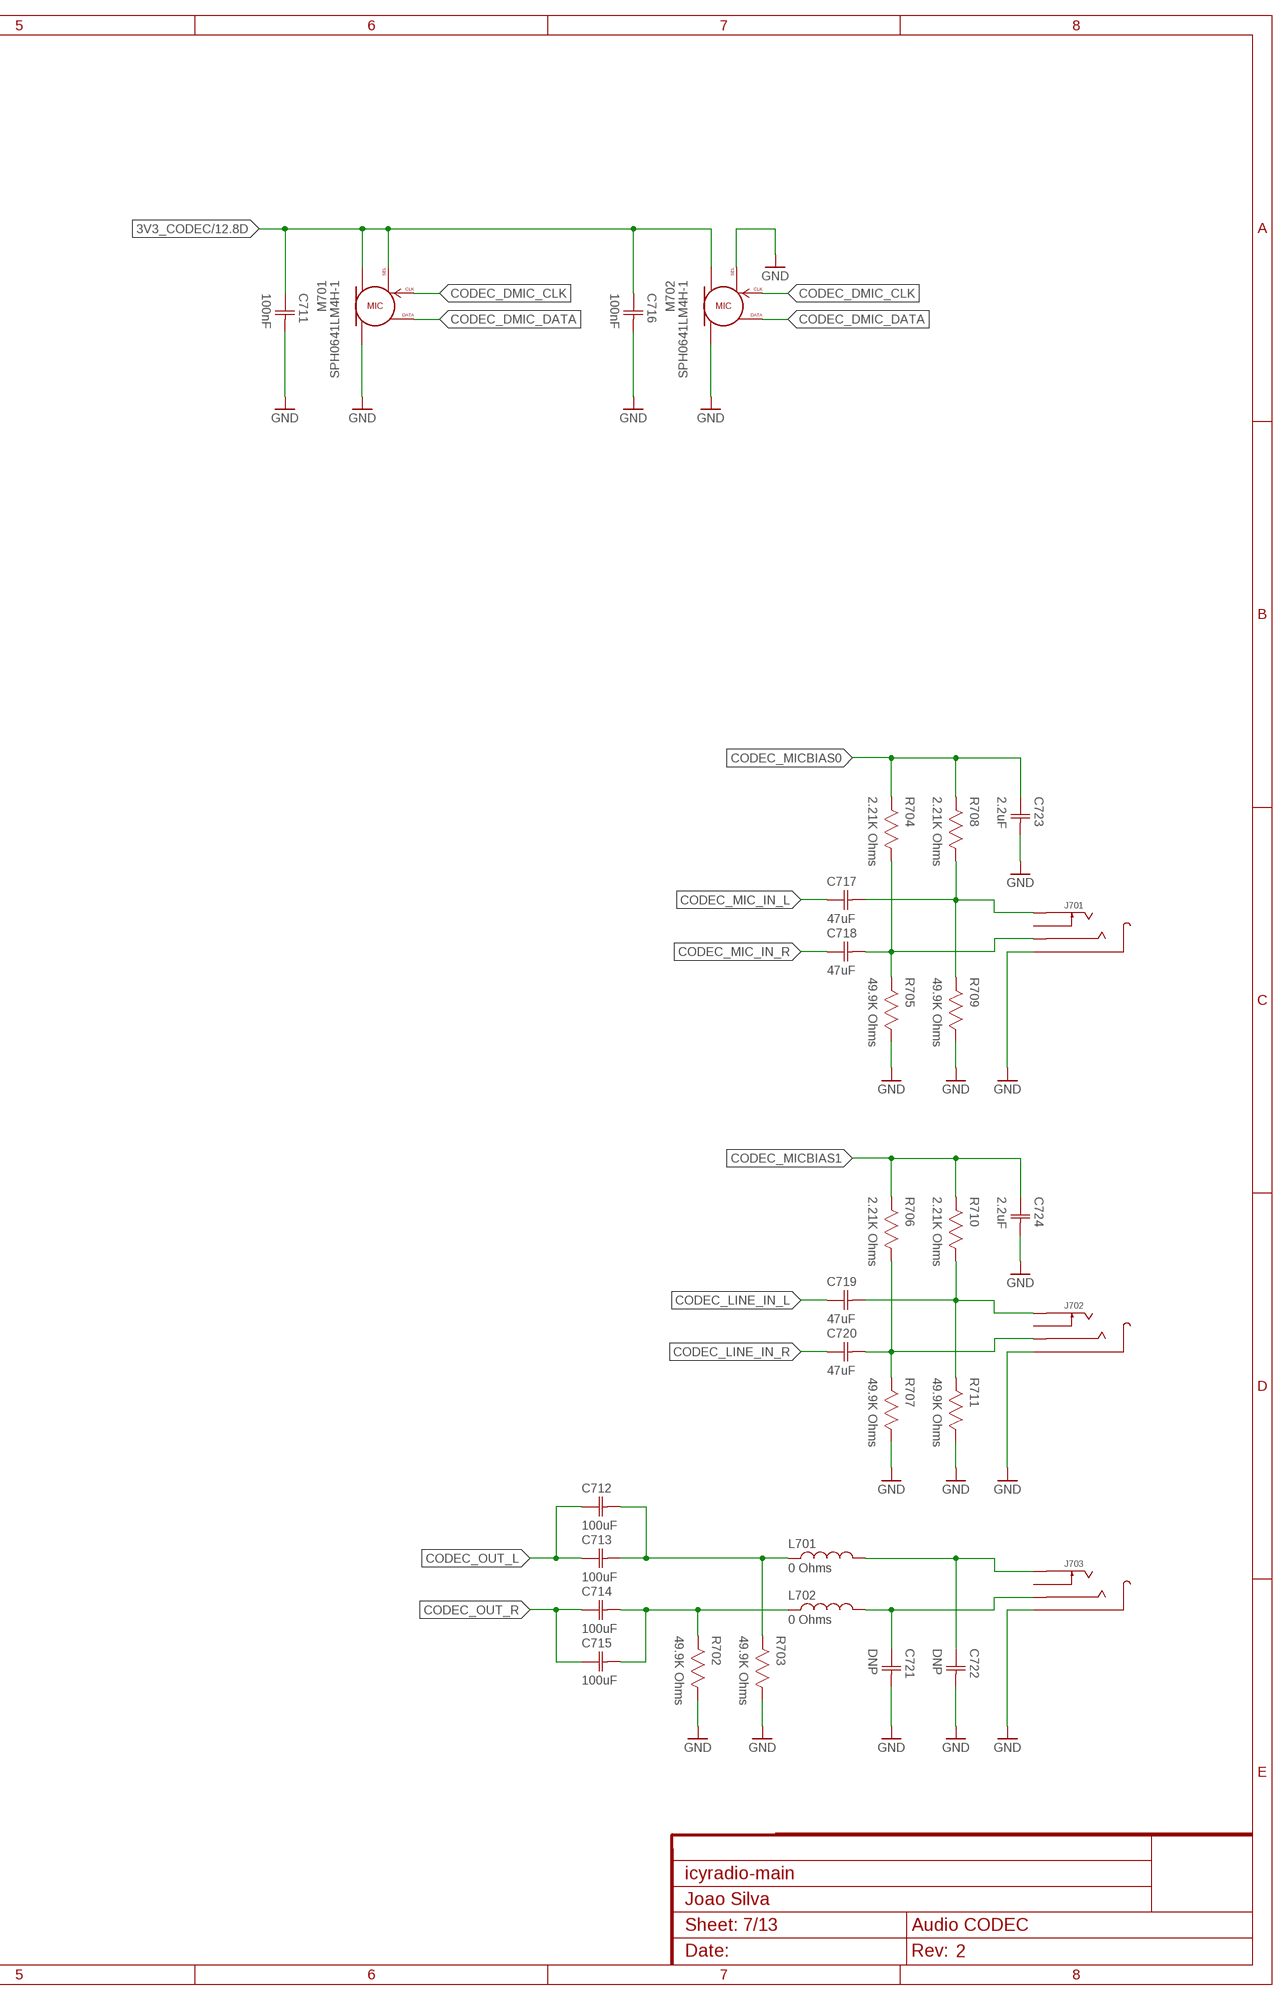
[diagram p13: schematic, sheet 7, part 2 of 2]
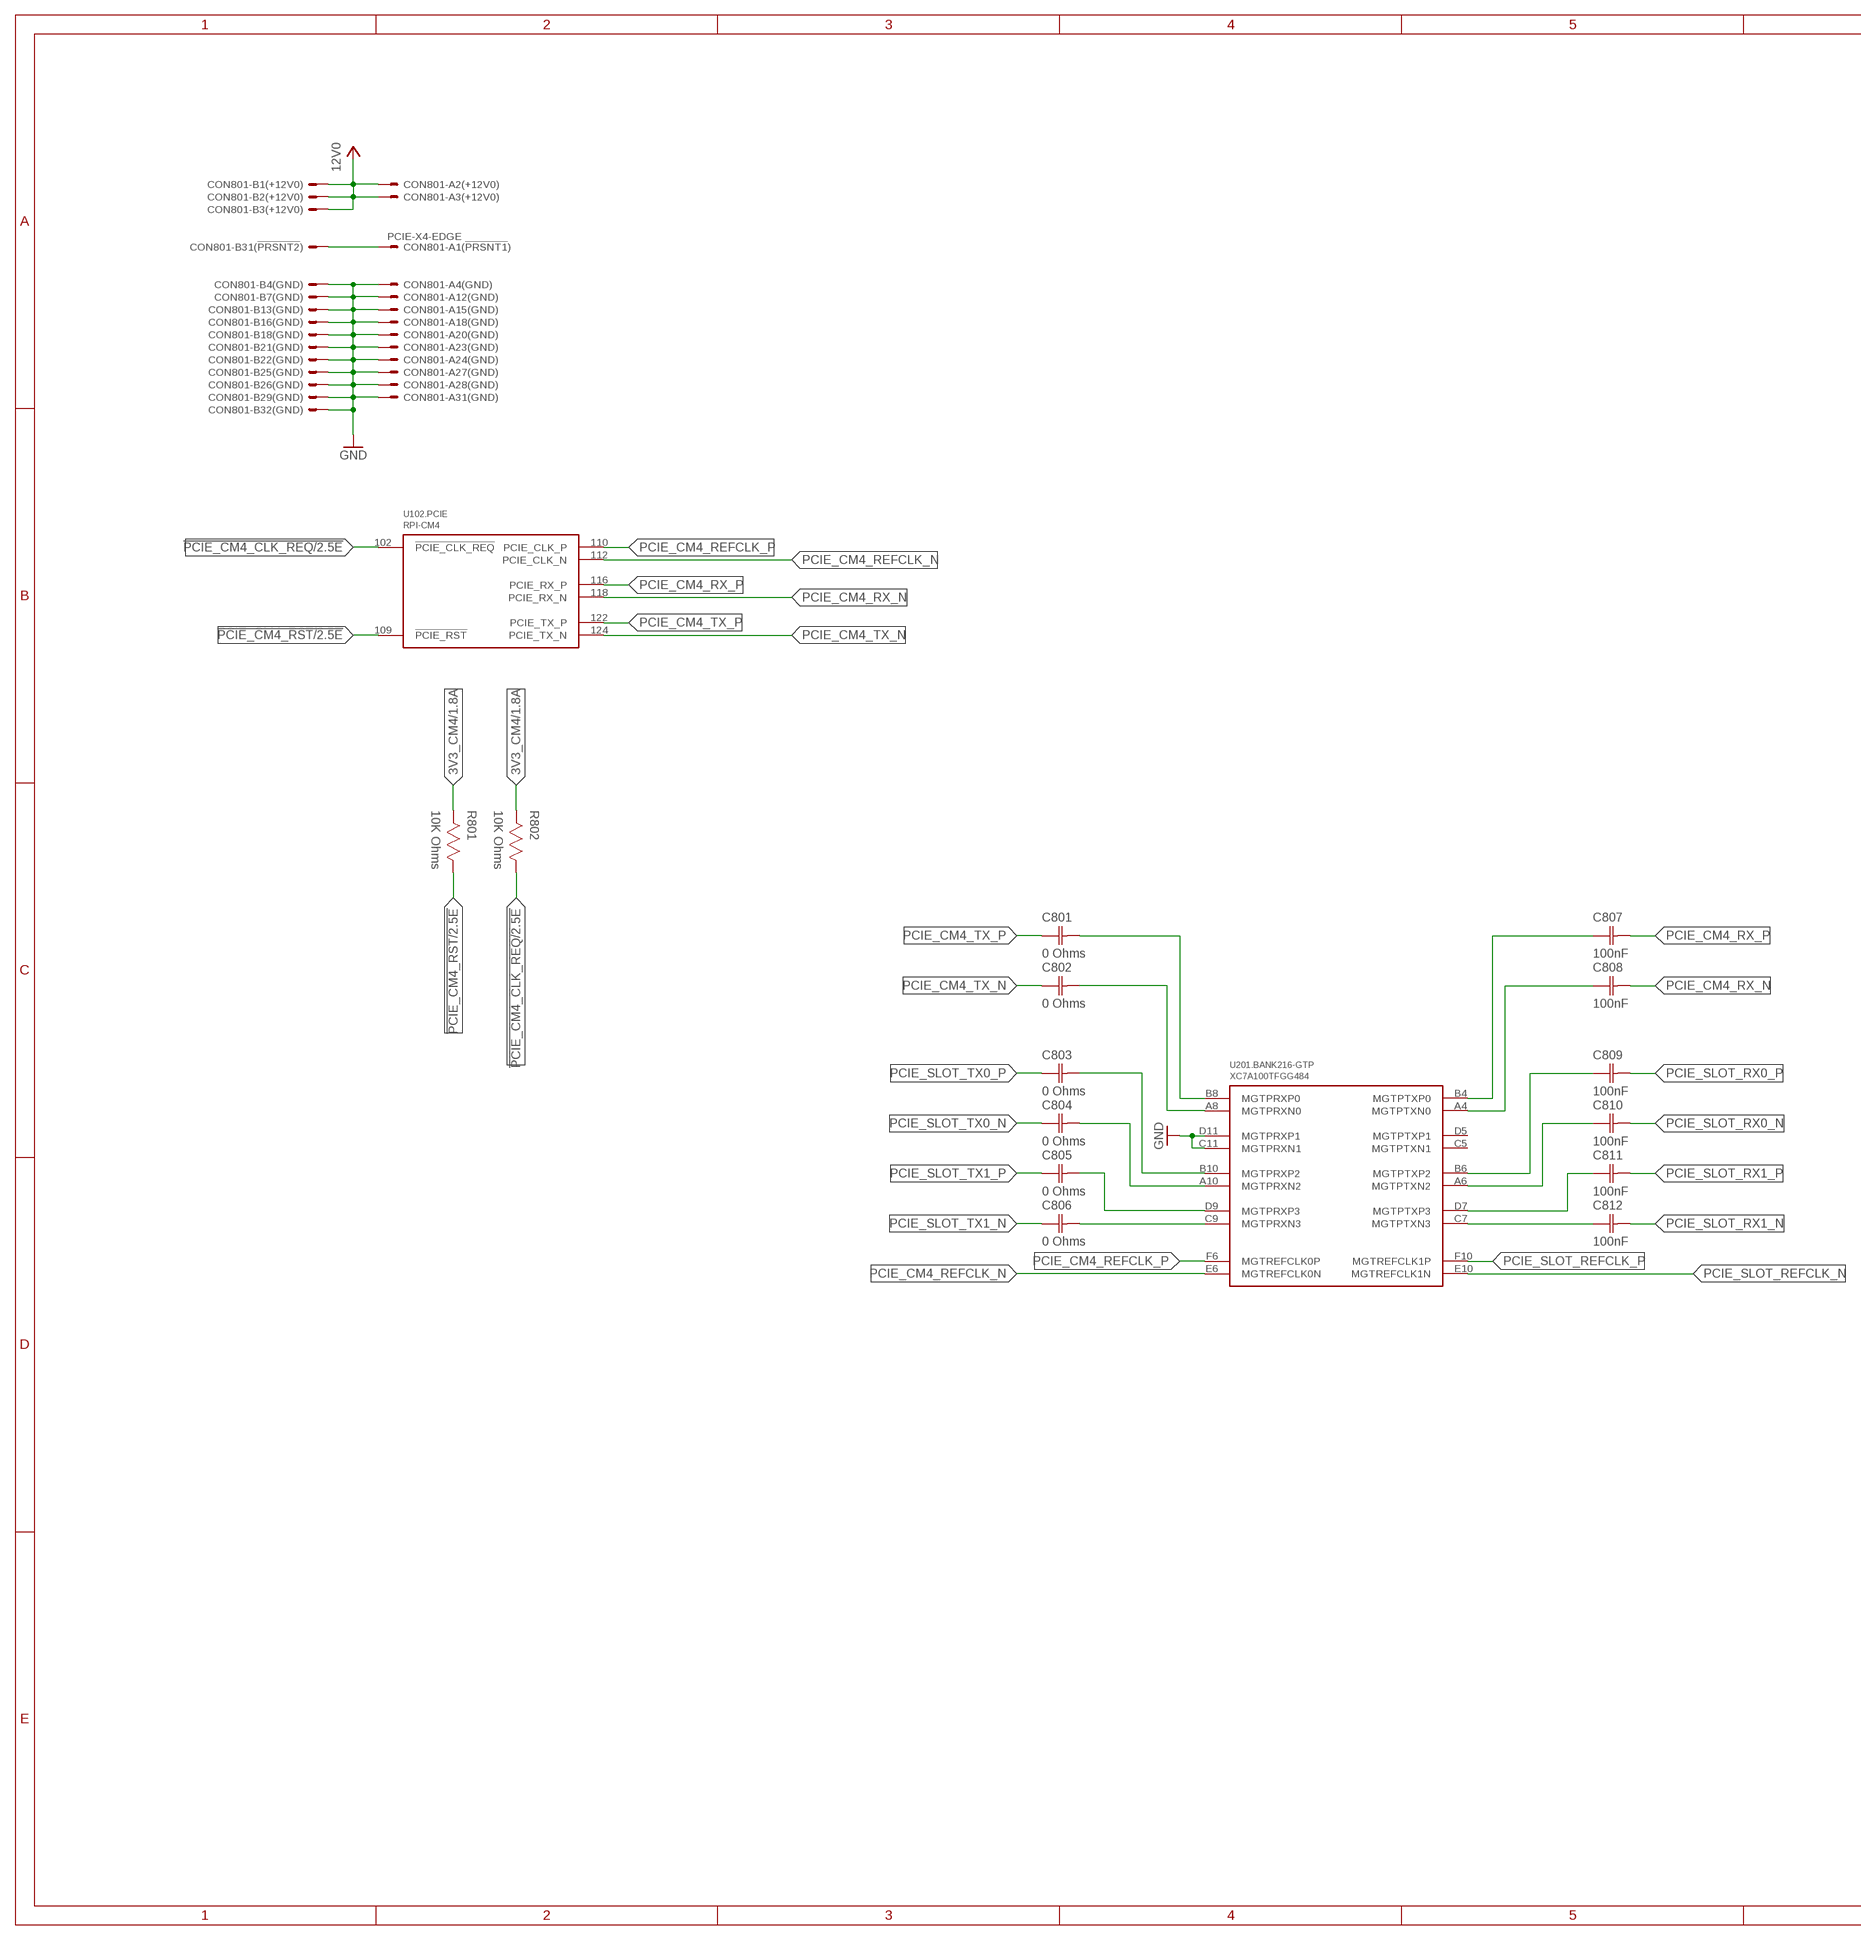
[diagram p14: schematic, sheet 8, part 1 of 2]
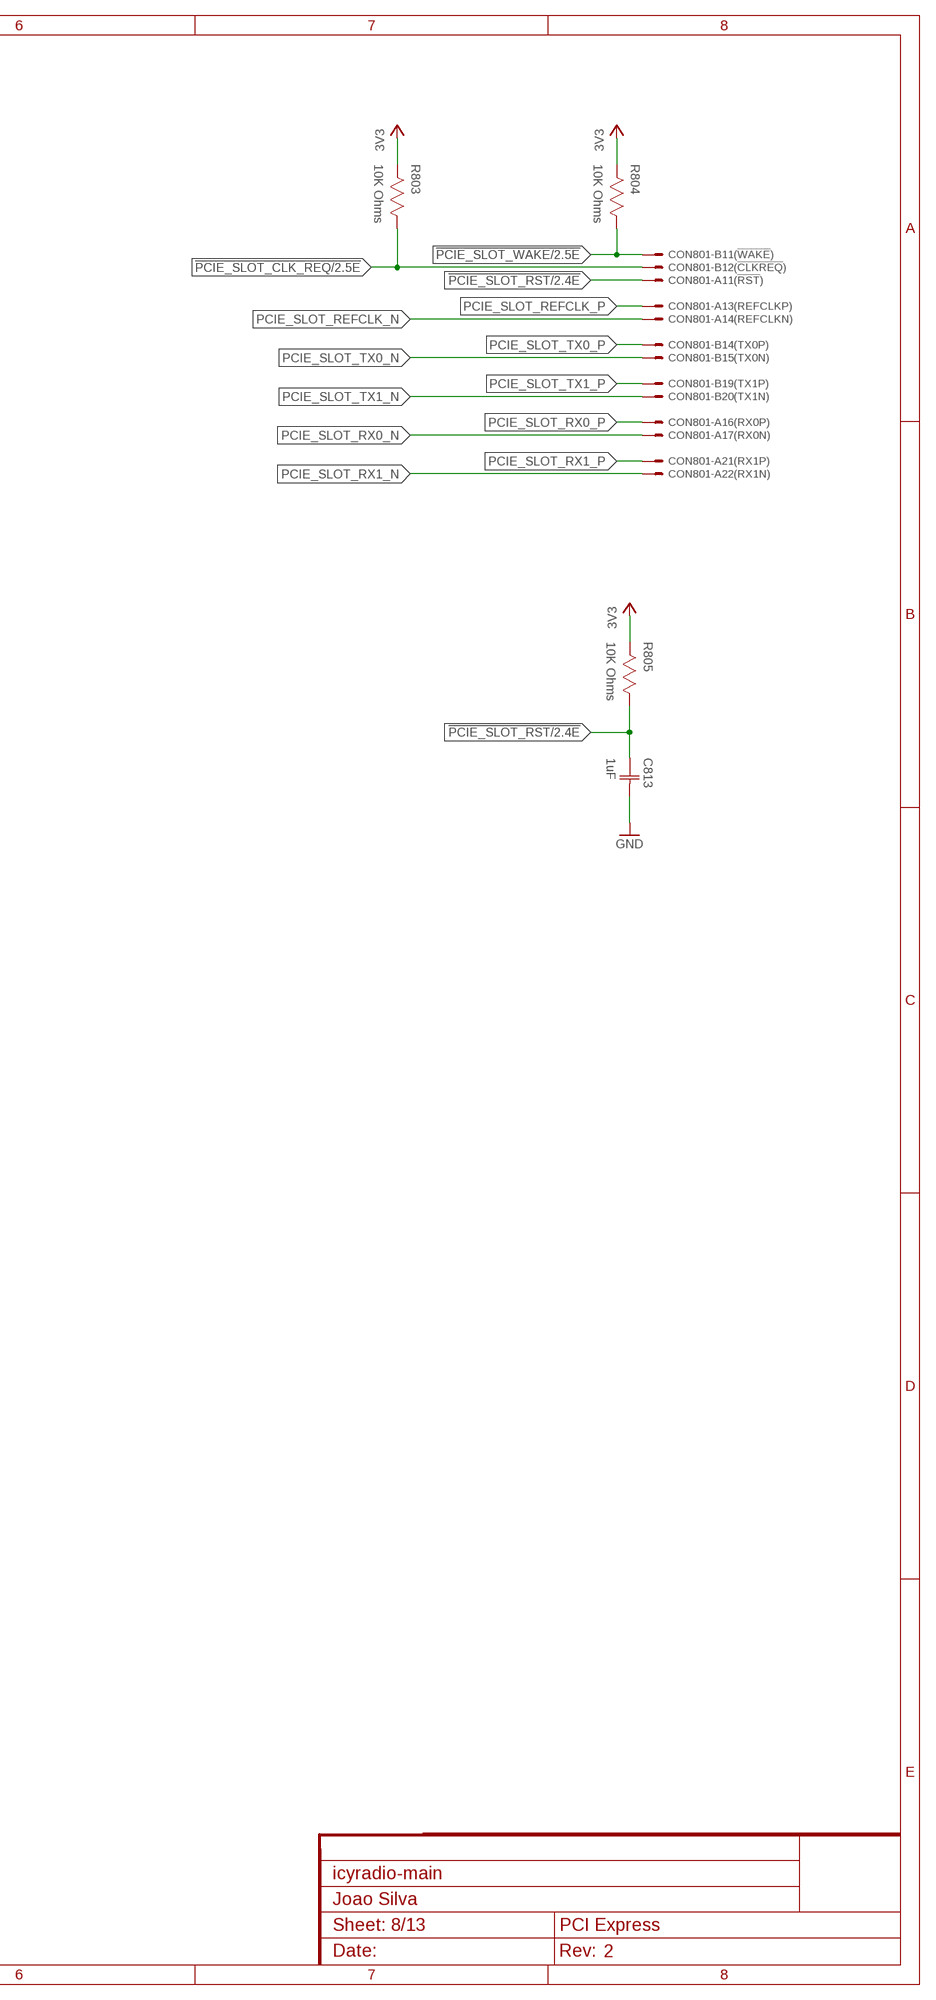
[diagram p15: schematic, sheet 8, part 2 of 2]
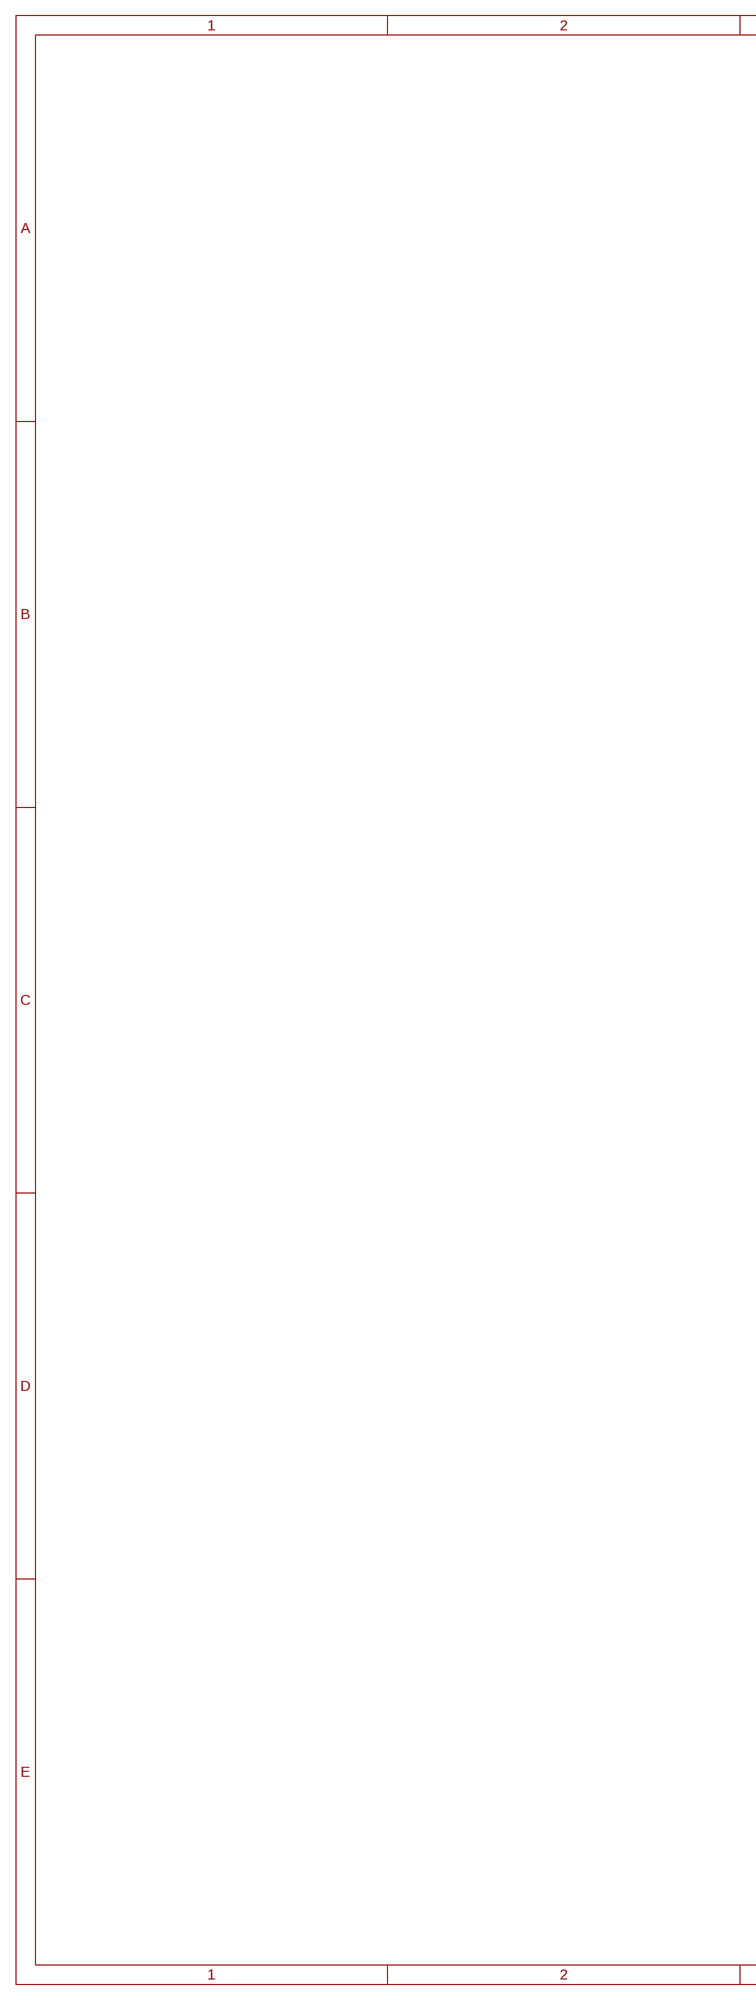
[diagram p16: schematic, sheet 9, part 1 of 2]
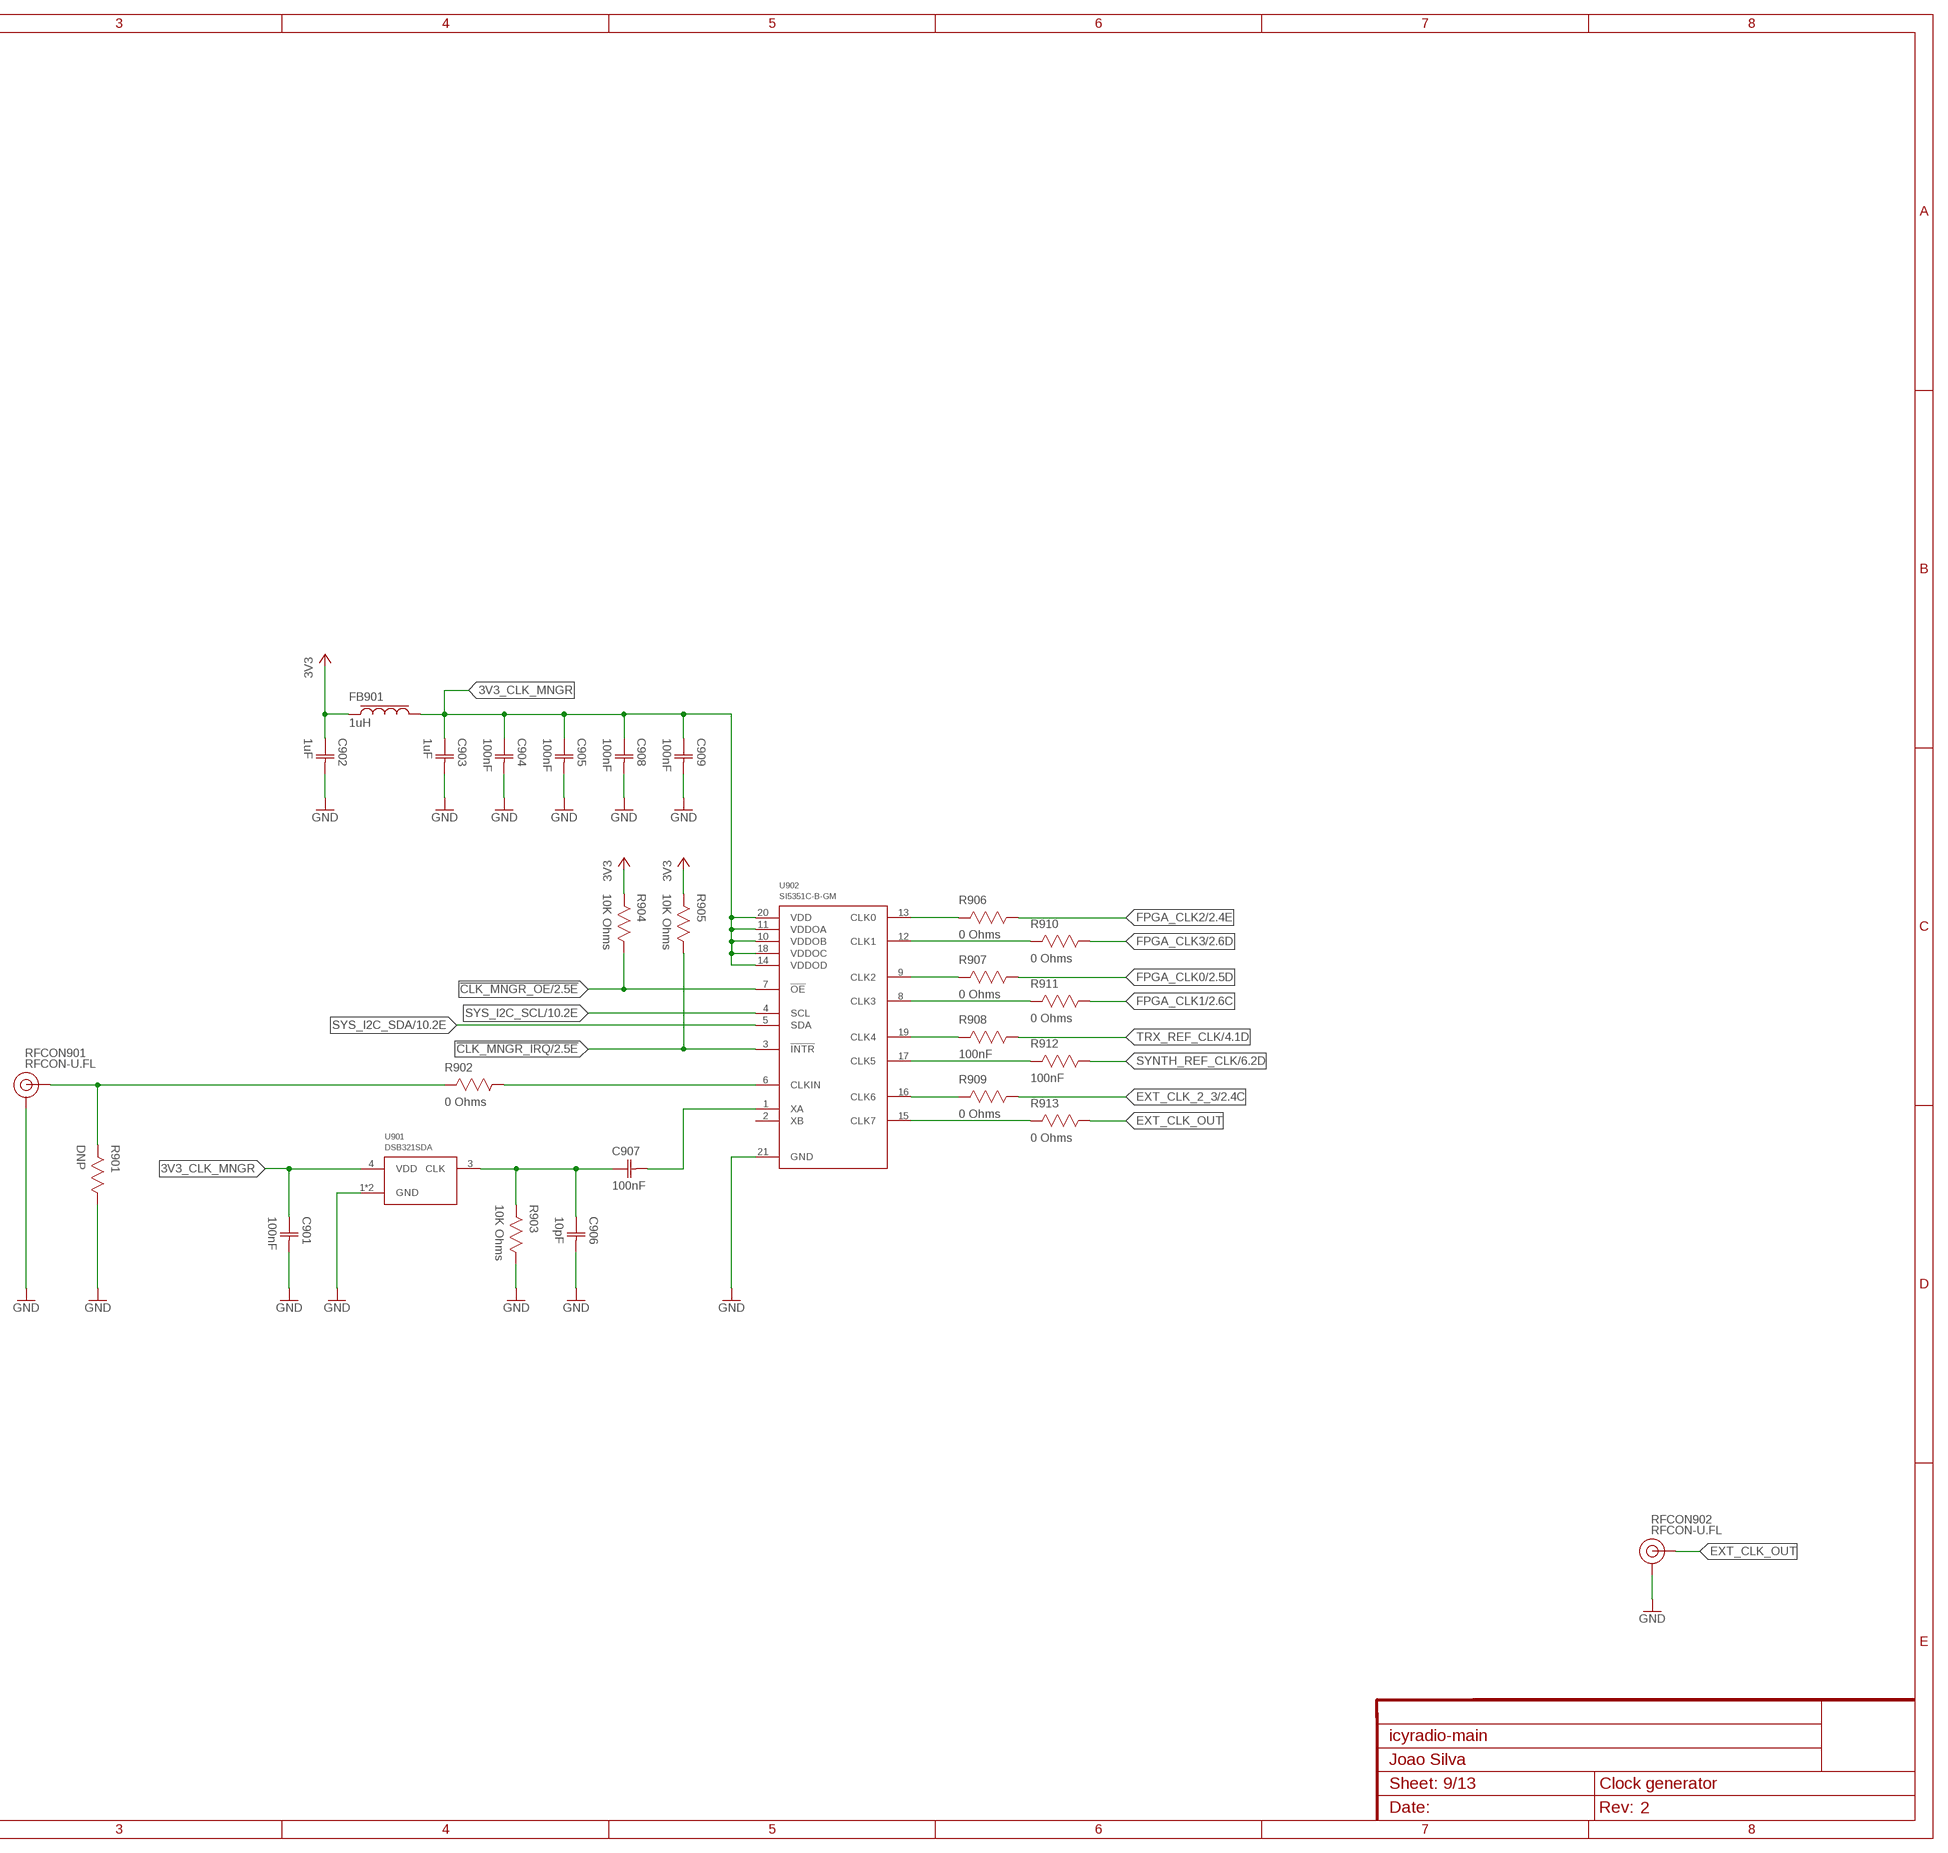
[diagram p17: schematic, sheet 9, part 2 of 2]
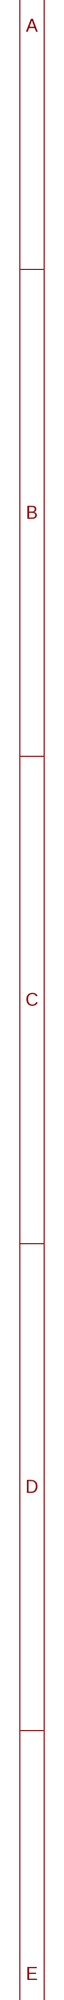
[diagram p18: schematic, sheet 10, part 1 of 2]
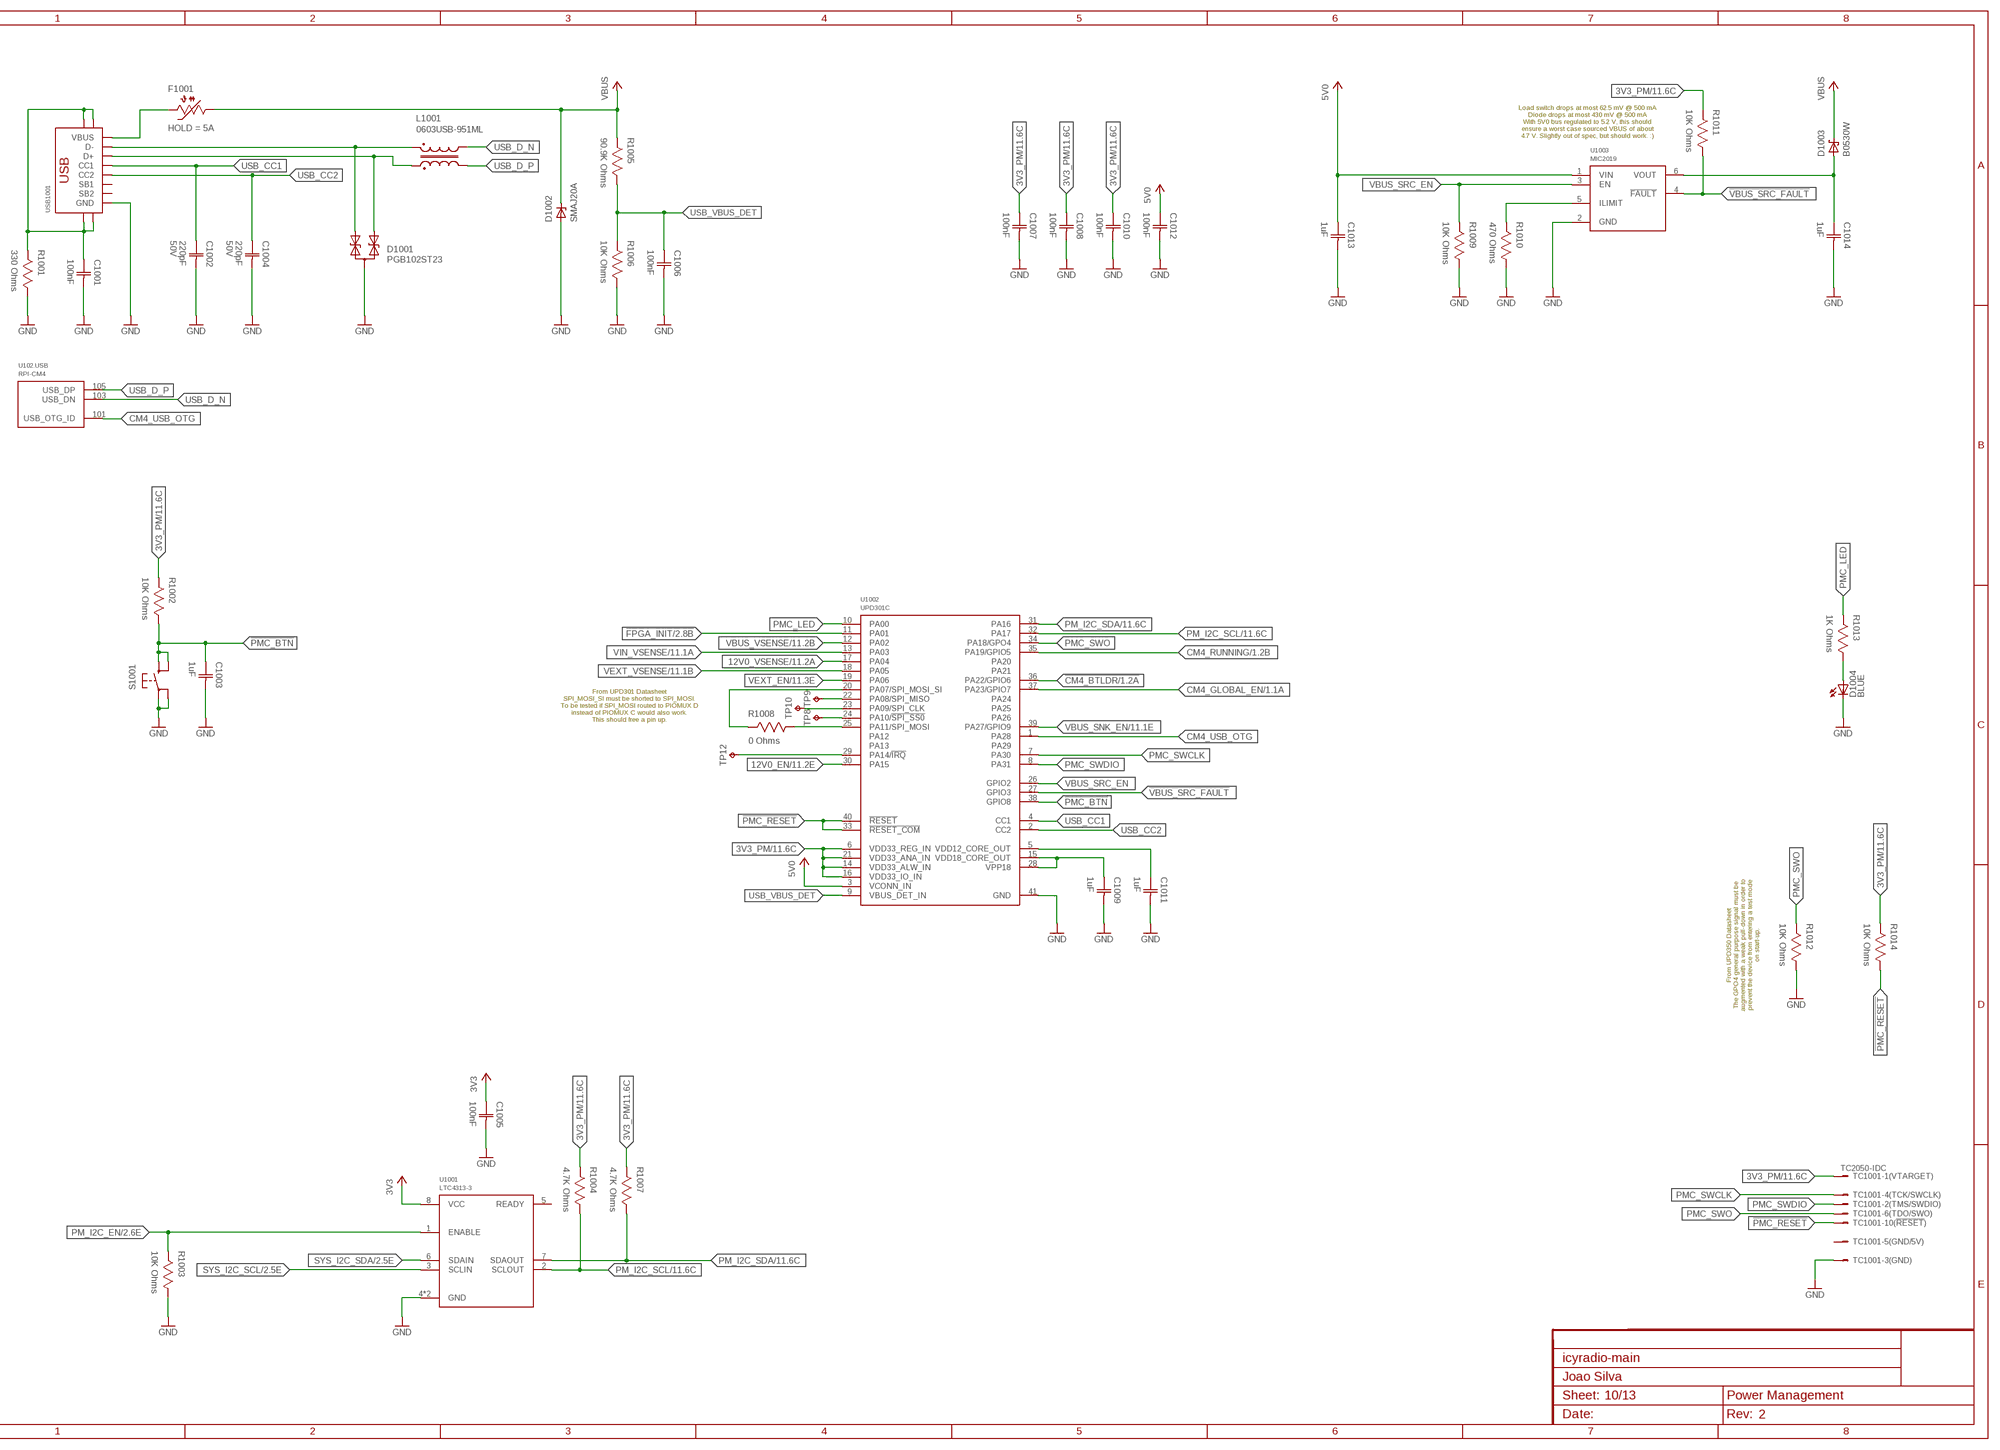
[diagram p19: schematic, sheet 10, part 2 of 2]
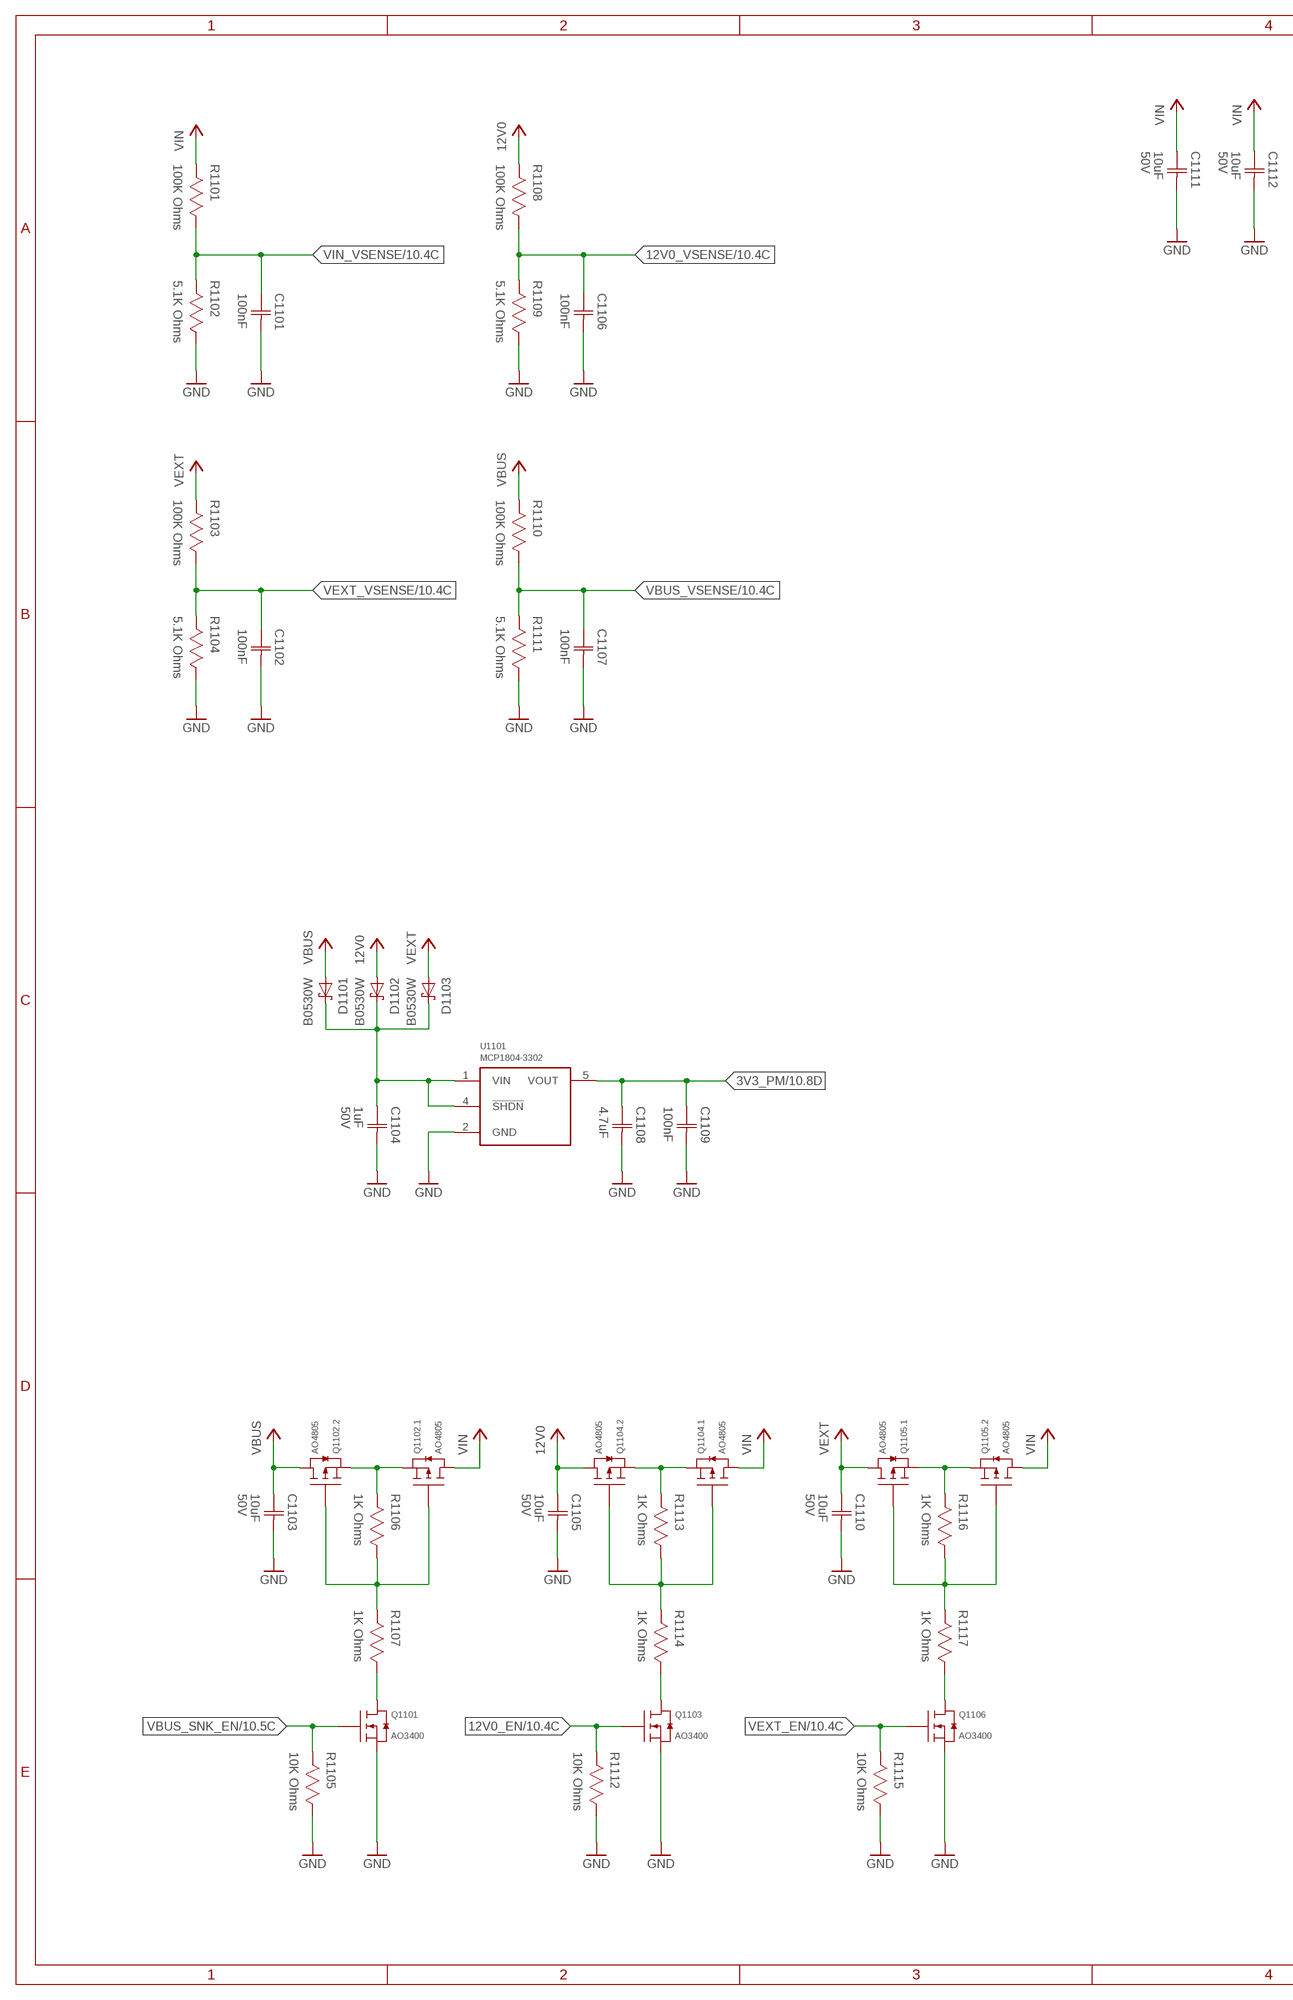
[diagram p20: schematic, sheet 11, part 1 of 2]
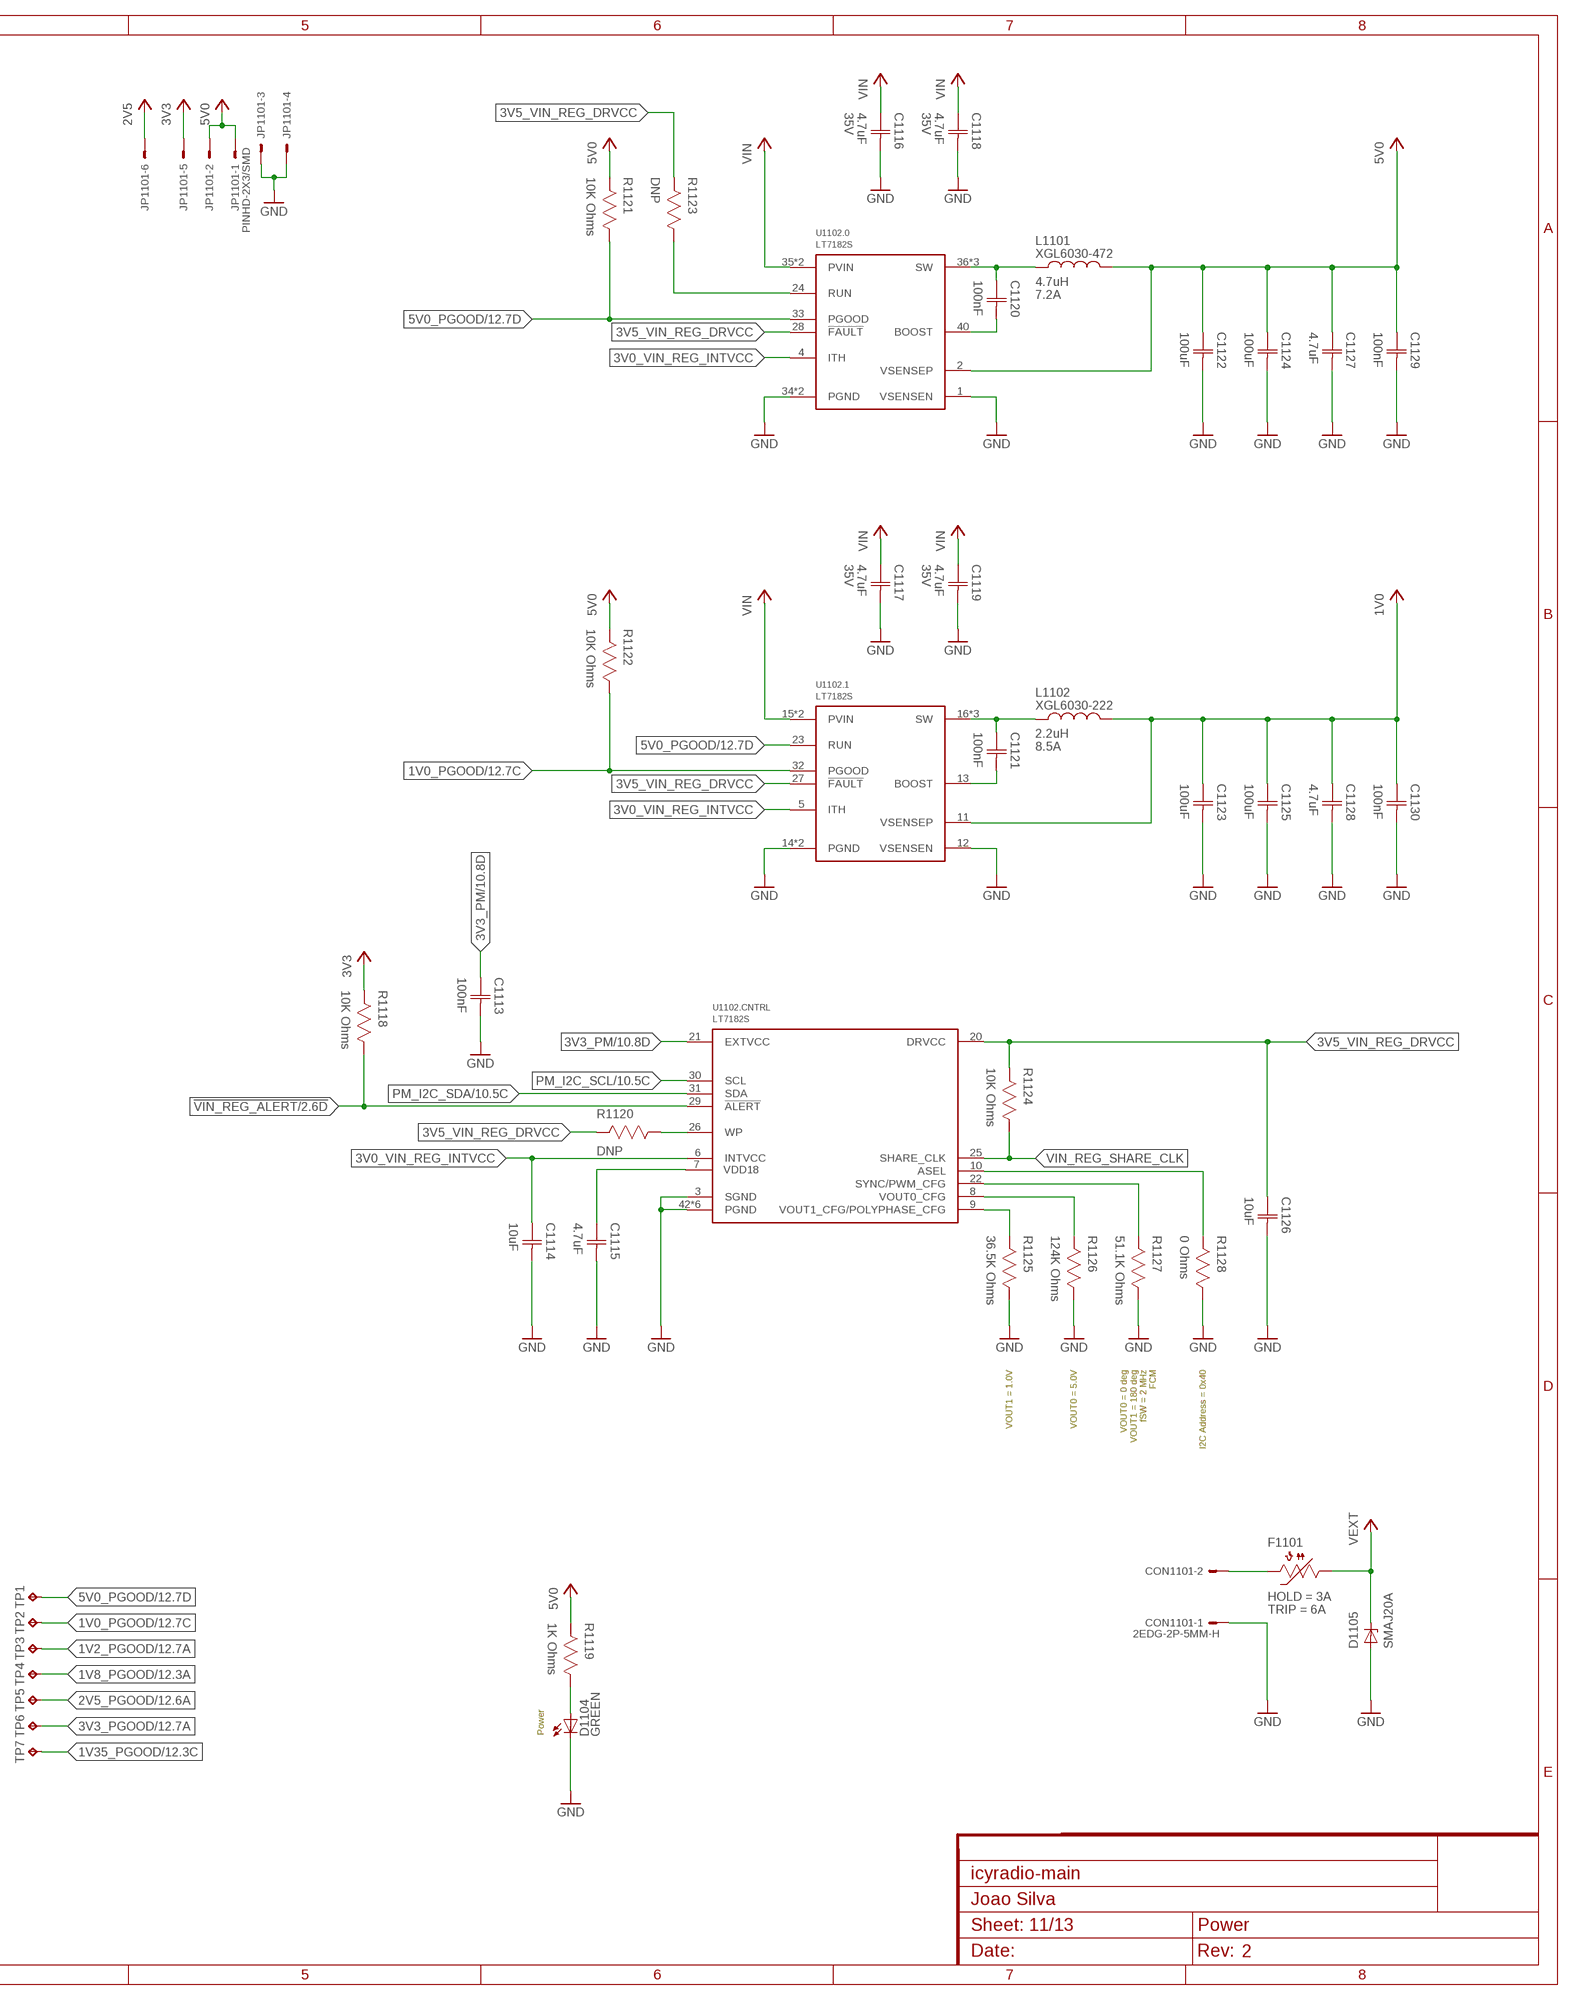
[diagram p21: schematic, sheet 11, part 2 of 2]
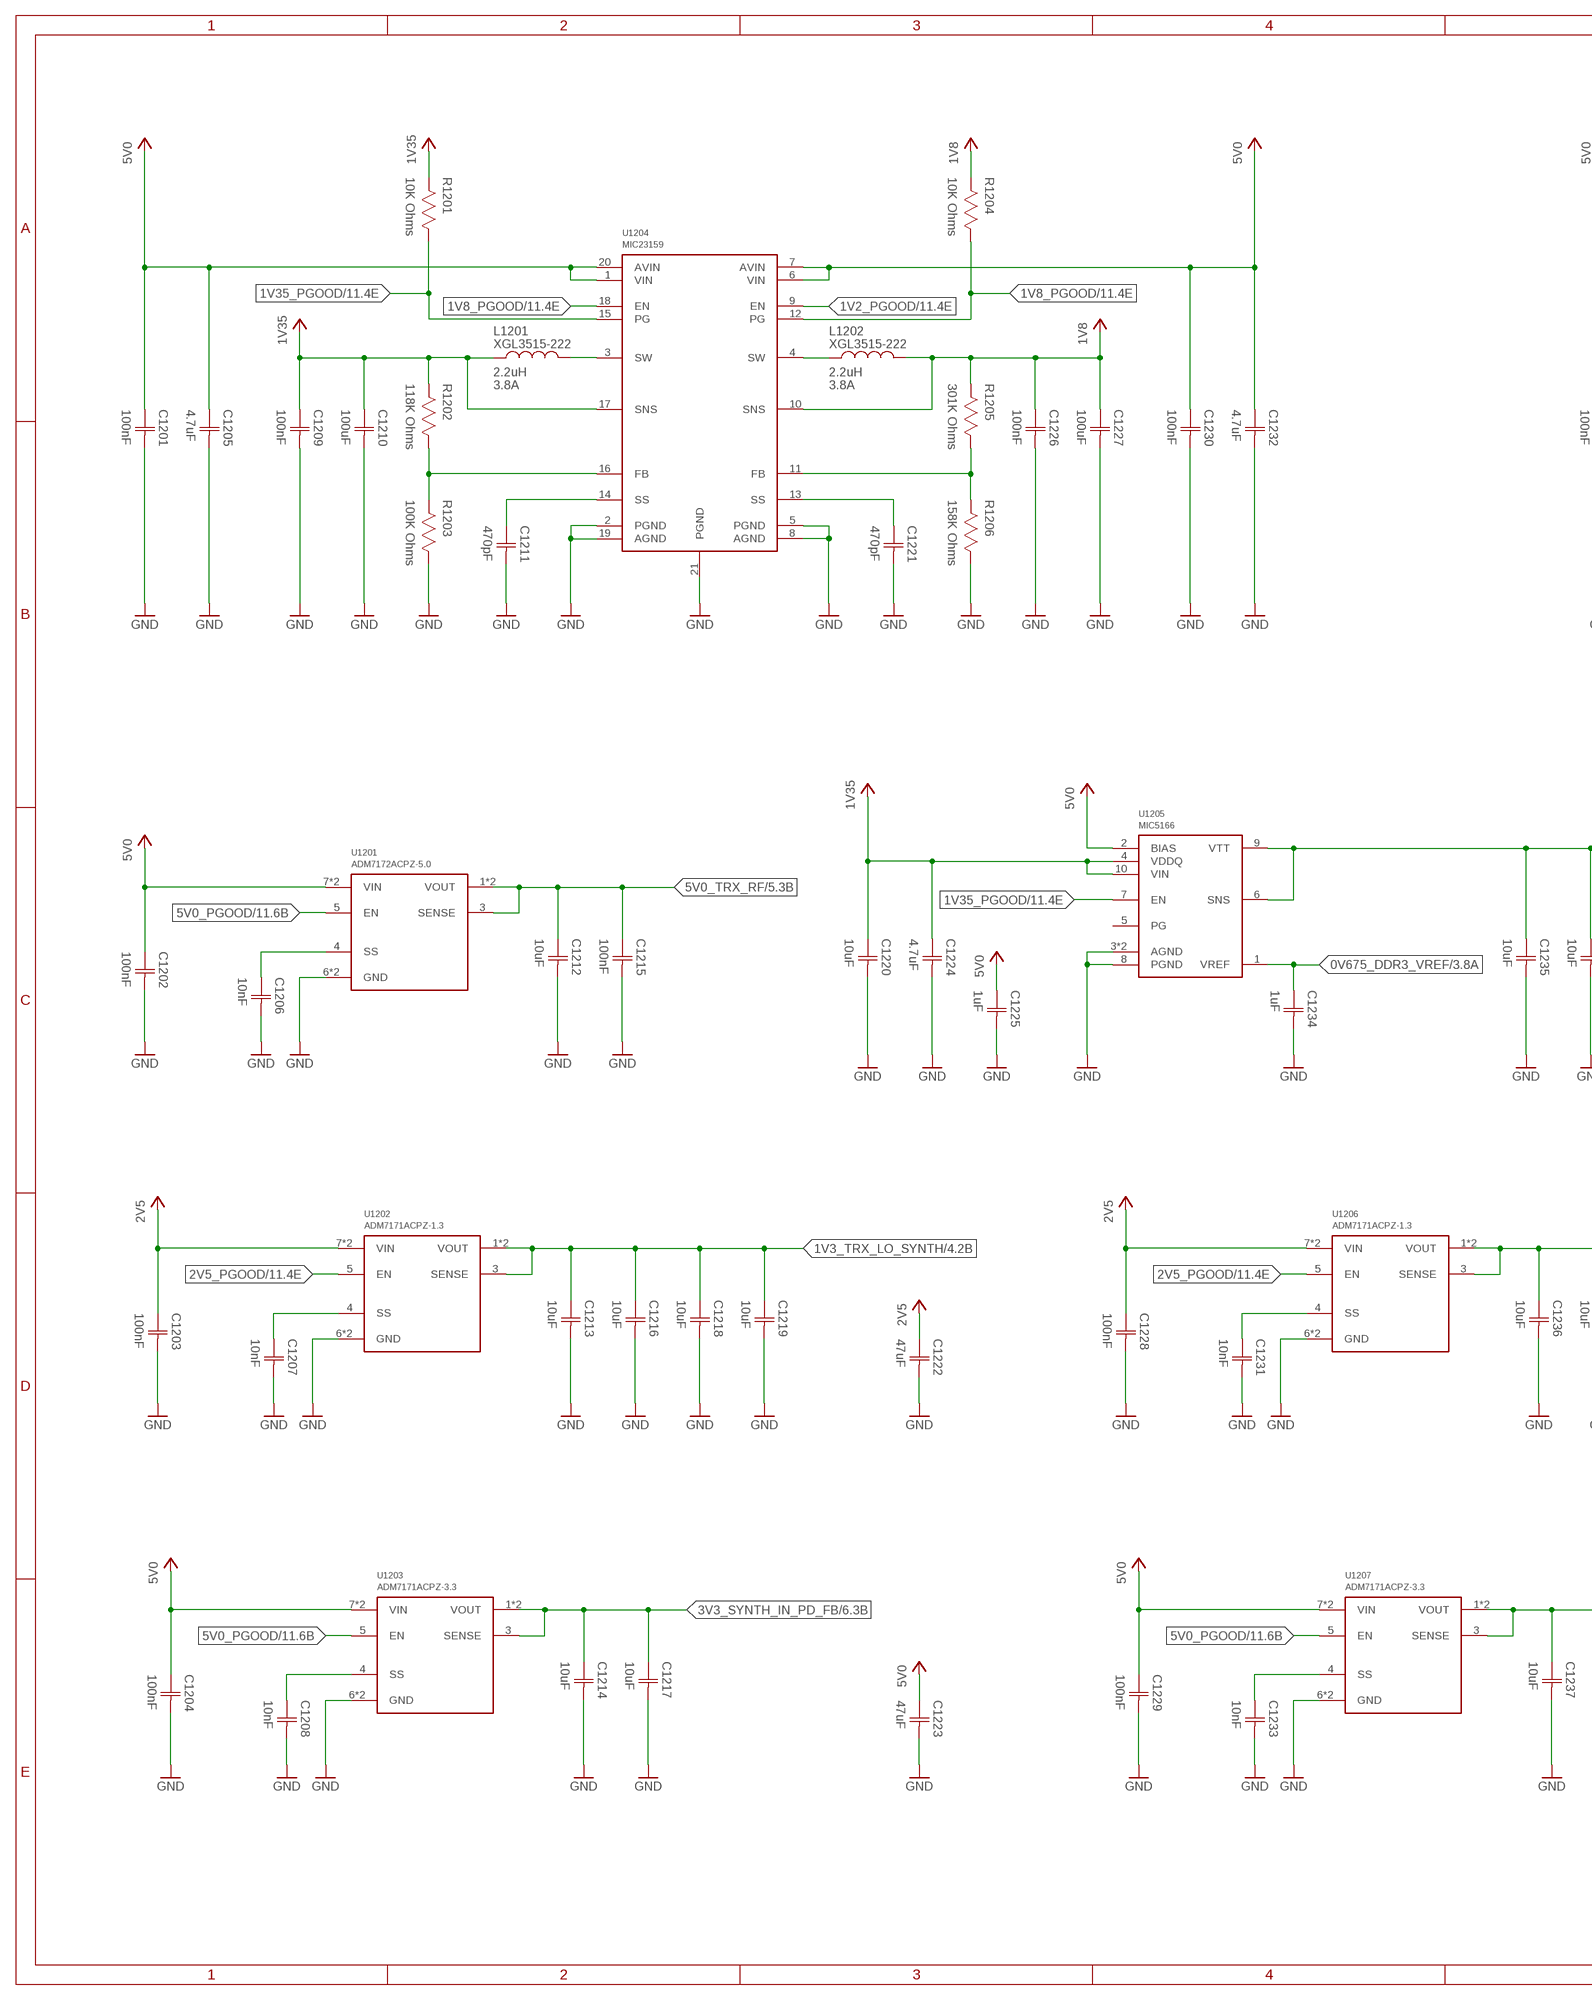
[diagram p22: schematic, sheet 12, part 1 of 2]
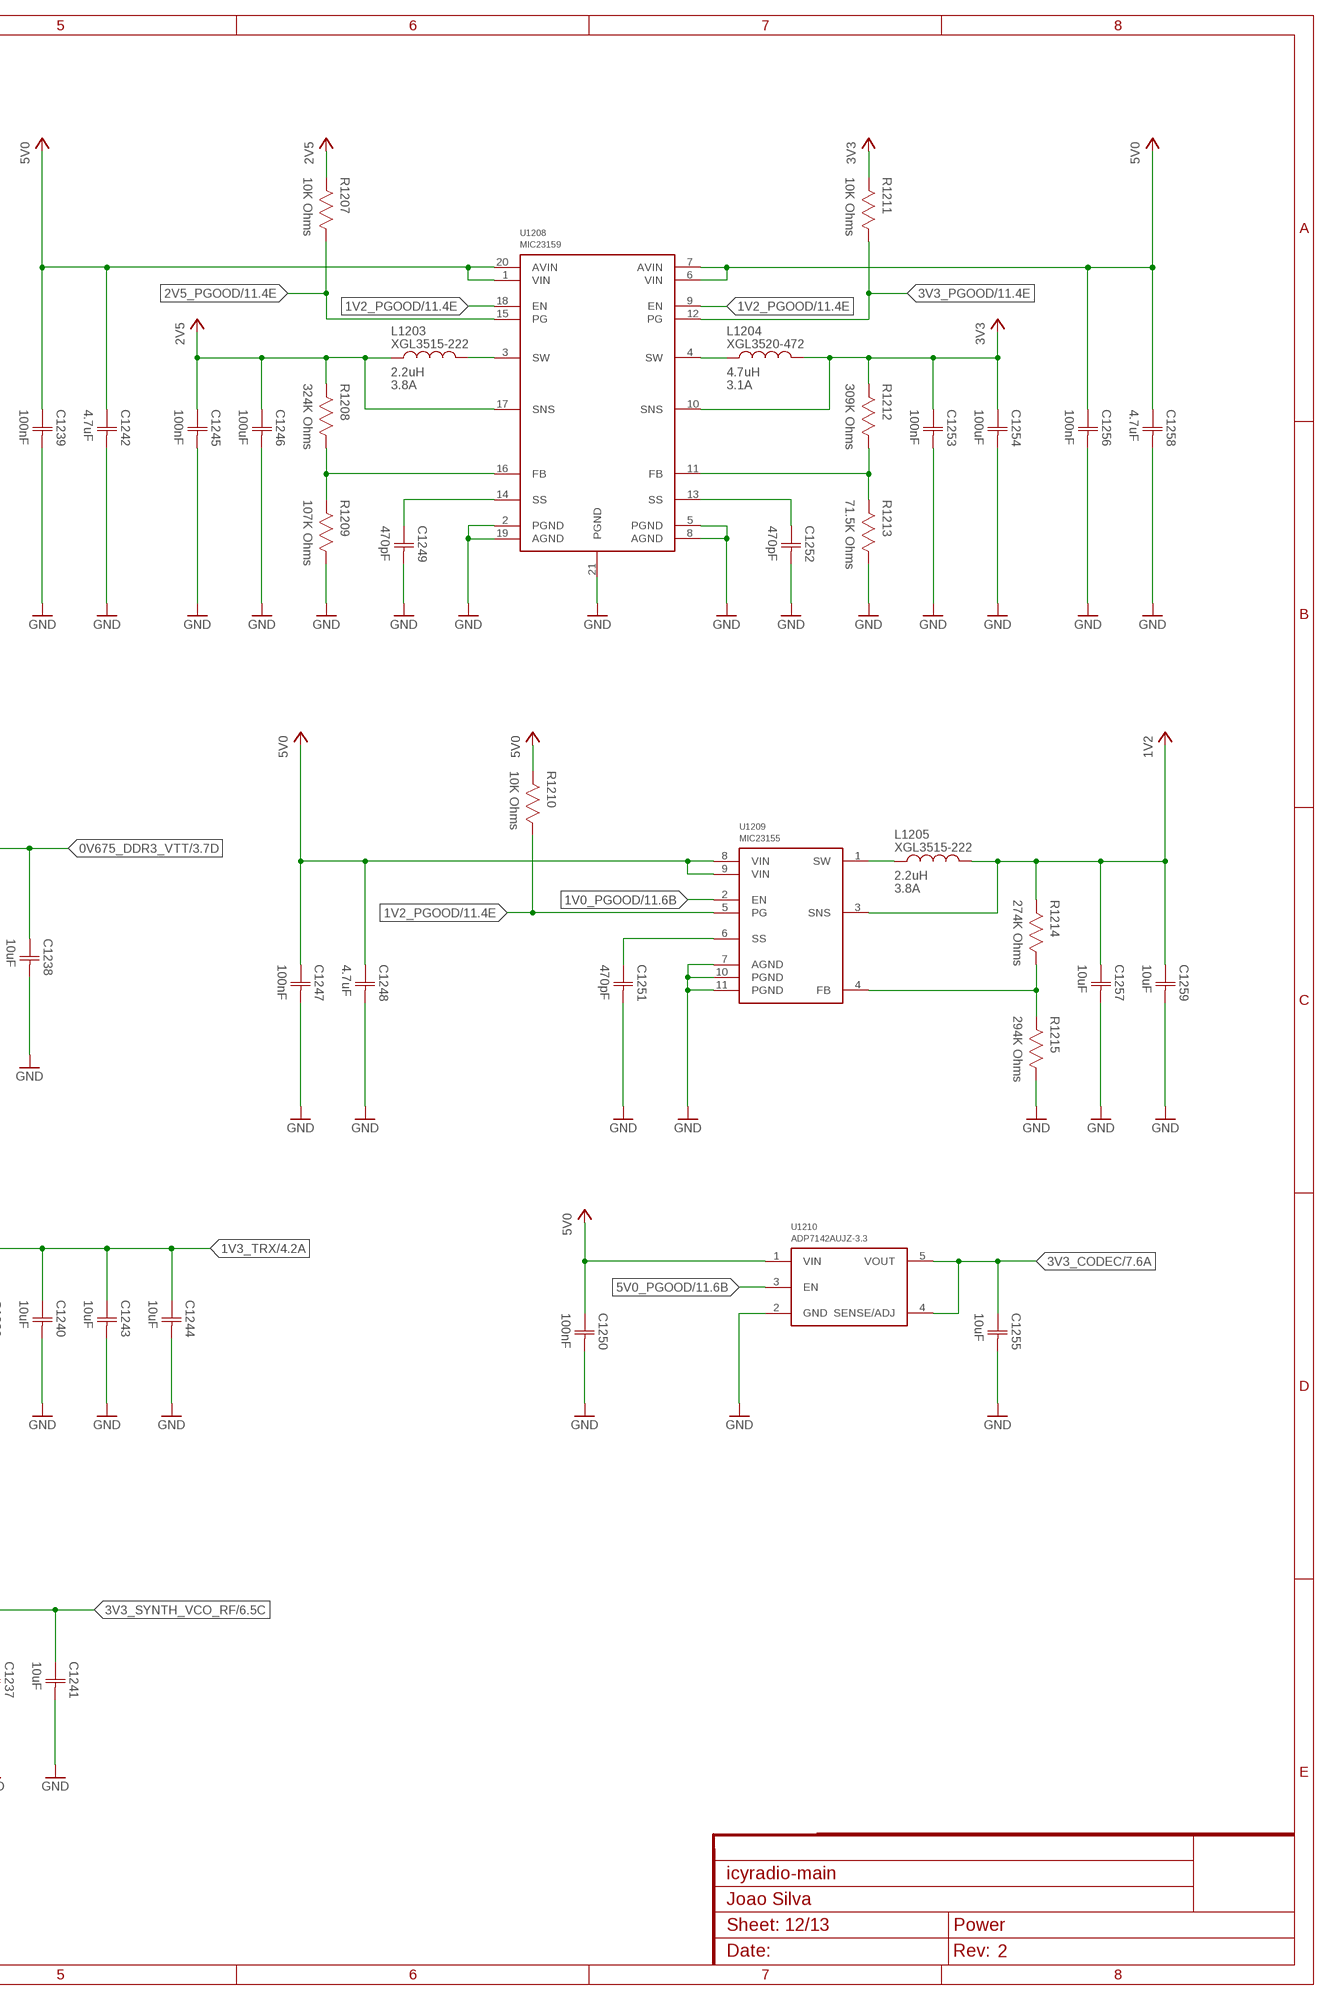
[diagram p23: schematic, sheet 12, part 2 of 2]
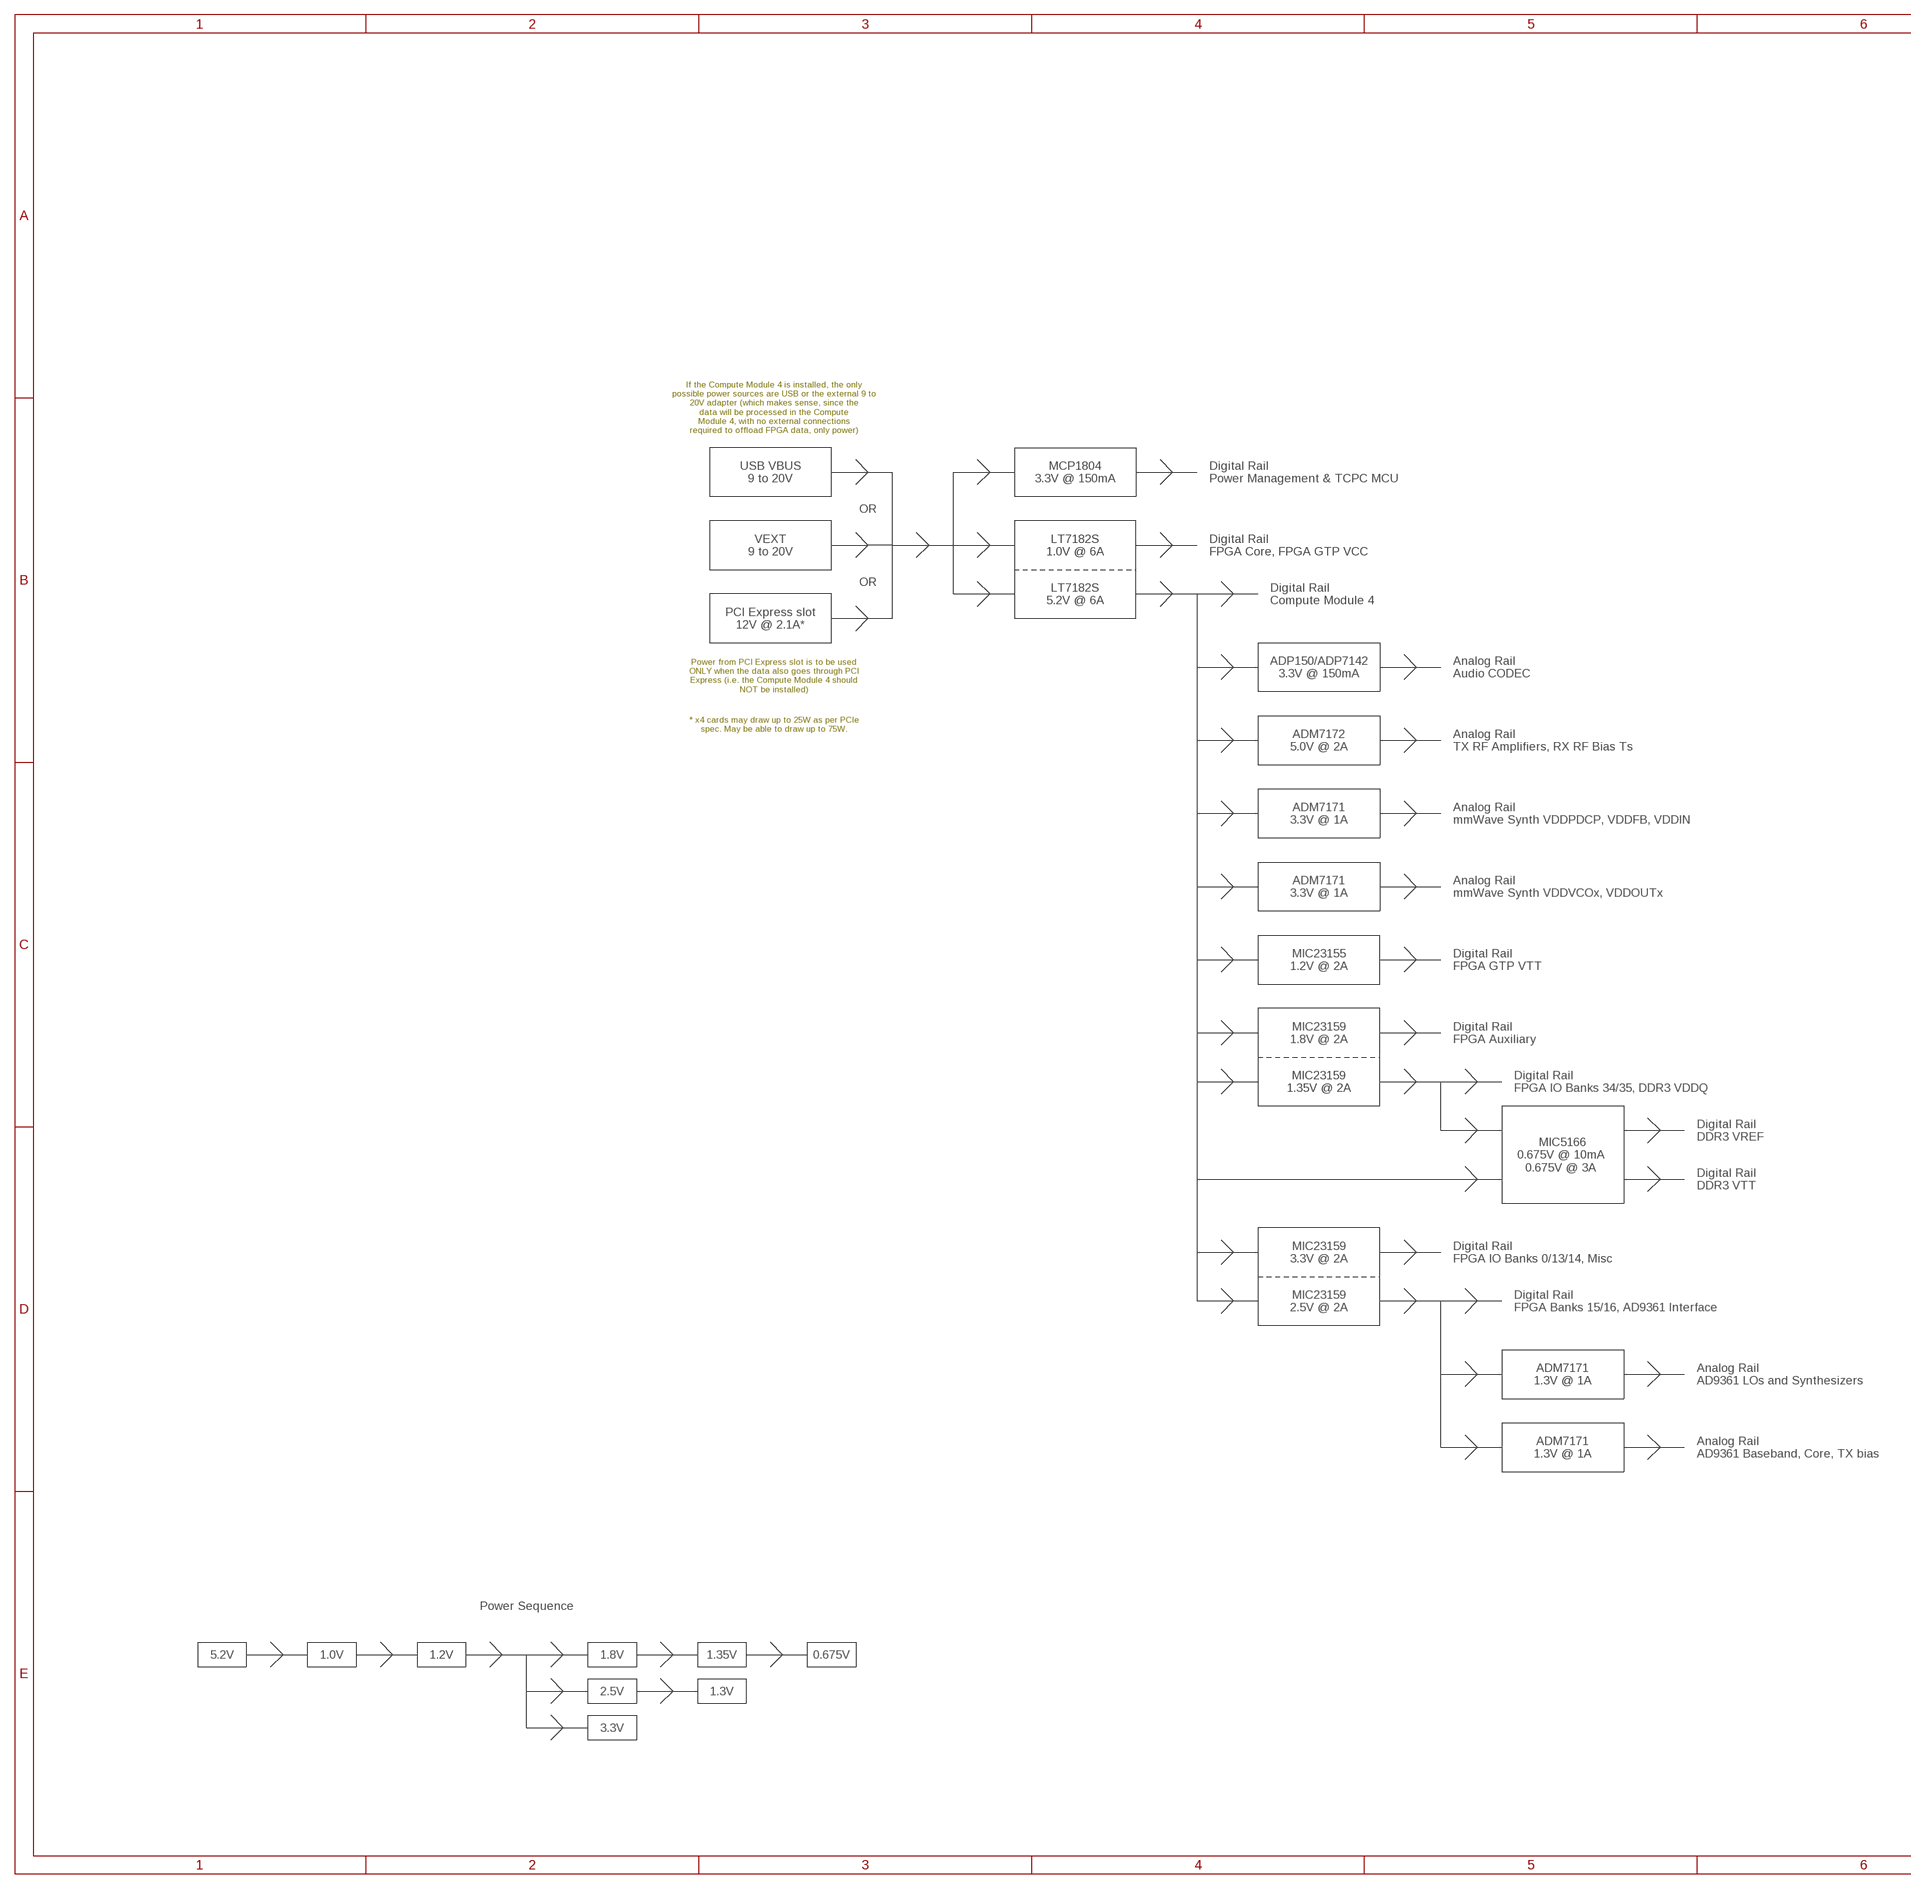
[diagram p24: schematic, sheet 13, part 1 of 2]
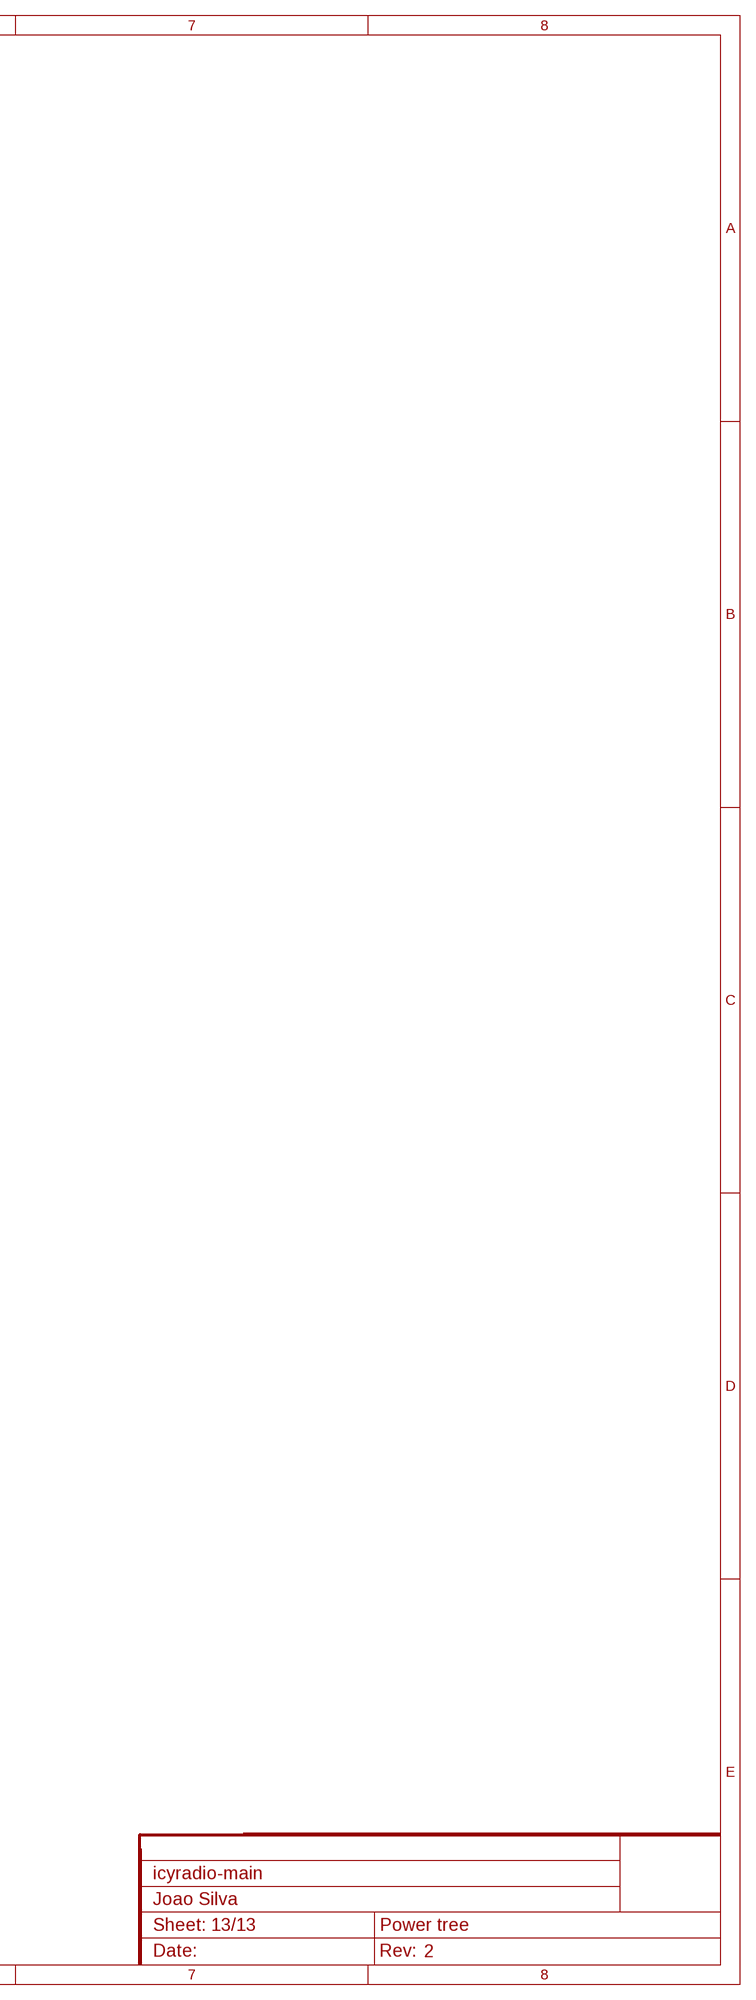
[diagram p25: schematic, sheet 13, part 2 of 2]

(export (version "E")
  (design (tool "Eeschema 10.0.6"))
  (components
    (comp (ref "C101")
      (value "100nF")
      (footprint "eagle-import:CAP0402")
      (libsource (lib "eagle-import") (part "CAPACITOR-0402"))
    )
    (comp (ref "C102")
      (value "10uF")
      (footprint "eagle-import:CAP0603")
      (libsource (lib "eagle-import") (part "CAPACITOR-0603"))
    )
    (comp (ref "C103")
      (value "10uF")
      (footprint "eagle-import:CAP0603")
      (libsource (lib "eagle-import") (part "CAPACITOR-0603"))
    )
    (comp (ref "C104")
      (value "10uF")
      (footprint "eagle-import:CAP0603")
      (libsource (lib "eagle-import") (part "CAPACITOR-0603"))
    )
    (comp (ref "C105")
      (value "10uF")
      (footprint "eagle-import:CAP0402")
      (libsource (lib "eagle-import") (part "CAPACITOR-0402"))
    )
    (comp (ref "C106")
      (value "1uF")
      (footprint "eagle-import:CAP0402")
      (libsource (lib "eagle-import") (part "CAPACITOR-0402"))
    )
    (comp (ref "C107")
      (value "100nF")
      (footprint "eagle-import:CAP0402")
      (libsource (lib "eagle-import") (part "CAPACITOR-0402"))
    )
    (comp (ref "C108")
      (value "1uF")
      (footprint "eagle-import:CAP0402")
      (libsource (lib "eagle-import") (part "CAPACITOR-0402"))
    )
    (comp (ref "CON101")
      (value "FPC-22P")
      (footprint "eagle-import:FPC-22P")
      (libsource (lib "eagle-import") (part "FPC-22P"))
    )
    (comp (ref "CON102")
      (value "FPC-22P")
      (footprint "eagle-import:FPC-22P")
      (libsource (lib "eagle-import") (part "FPC-22P"))
    )
    (comp (ref "D101")
      (value "LED0603")
      (footprint "eagle-import:0603")
      (fields (field (name "COLOR") "GREEN"))
      (libsource (lib "eagle-import") (part "LED0603"))
    )
    (comp (ref "D102")
      (value "LED0603")
      (footprint "eagle-import:0603")
      (fields (field (name "COLOR") "RED"))
      (libsource (lib "eagle-import") (part "LED0603"))
    )
    (comp (ref "J101")
      (value "RJ45_MAG_LED_1G-TE-1-2301994-0")
      (footprint "eagle-import:TE-1-2301994-0")
      (libsource (lib "eagle-import") (part "RJ45_MAG_LED_1G-TE-1-2301994-0"))
    )
    (comp (ref "JP101")
      (value "PINHD-1X3")
      (footprint "eagle-import:1X03")
      (libsource (lib "eagle-import") (part "PINHD-1X3"))
    )
    (comp (ref "LOGO101")
      (value "JS-10MM")
      (footprint "eagle-import:JS_10MM")
      (libsource (lib "eagle-import") (part "JS-10MM"))
    )
    (comp (ref "Q101")
      (value "AO3400")
      (footprint "eagle-import:SOT23")
      (libsource (lib "eagle-import") (part "AO3400"))
    )
    (comp (ref "Q102")
      (value "AO3400")
      (footprint "eagle-import:SOT23")
      (libsource (lib "eagle-import") (part "AO3400"))
    )
    (comp (ref "R101")
      (value "1K Ohms")
      (footprint "eagle-import:RES0402")
      (libsource (lib "eagle-import") (part "RESISTOR-0402"))
    )
    (comp (ref "R102")
      (value "2.2K Ohms")
      (footprint "eagle-import:RES0402")
      (libsource (lib "eagle-import") (part "RESISTOR-0402"))
    )
    (comp (ref "R103")
      (value "10K Ohms")
      (footprint "eagle-import:RES0402")
      (libsource (lib "eagle-import") (part "RESISTOR-0402"))
    )
    (comp (ref "R104")
      (value "1.2K Ohms")
      (footprint "eagle-import:RES0402")
      (libsource (lib "eagle-import") (part "RESISTOR-0402"))
    )
    (comp (ref "R105")
      (value "0 Ohms")
      (footprint "eagle-import:RES0402")
      (libsource (lib "eagle-import") (part "RESISTOR-0402"))
    )
    (comp (ref "R106")
      (value "1K Ohms")
      (footprint "eagle-import:RES0402")
      (libsource (lib "eagle-import") (part "RESISTOR-0402"))
    )
    (comp (ref "R107")
      (value "0 Ohms")
      (footprint "eagle-import:RES0402")
      (libsource (lib "eagle-import") (part "RESISTOR-0402"))
    )
    (comp (ref "R108")
      (value "10K Ohms")
      (footprint "eagle-import:RES0402")
      (libsource (lib "eagle-import") (part "RESISTOR-0402"))
    )
    (comp (ref "R109")
      (value "DNP")
      (footprint "eagle-import:RES0402")
      (libsource (lib "eagle-import") (part "RESISTOR-0402"))
    )
    (comp (ref "R110")
      (value "DNP")
      (footprint "eagle-import:RES0402")
      (libsource (lib "eagle-import") (part "RESISTOR-0402"))
    )
    (comp (ref "R111")
      (value "0 Ohms")
      (footprint "eagle-import:RES0402")
      (libsource (lib "eagle-import") (part "RESISTOR-0402"))
    )
    (comp (ref "R112")
      (value "DNP")
      (footprint "eagle-import:RES0402")
      (libsource (lib "eagle-import") (part "RESISTOR-0402"))
    )
    (comp (ref "R113")
      (value "1K Ohms")
      (footprint "eagle-import:RES0402")
      (libsource (lib "eagle-import") (part "RESISTOR-0402"))
    )
    (comp (ref "R114")
      (value "22 Ohms")
      (footprint "eagle-import:RES0402")
      (libsource (lib "eagle-import") (part "RESISTOR-0402"))
    )
    (comp (ref "R115")
      (value "22 Ohms")
      (footprint "eagle-import:RES0402")
      (libsource (lib "eagle-import") (part "RESISTOR-0402"))
    )
    (comp (ref "R116")
      (value "2.2K Ohms")
      (footprint "eagle-import:RES0402")
      (libsource (lib "eagle-import") (part "RESISTOR-0402"))
    )
    (comp (ref "R117")
      (value "2.2K Ohms")
      (footprint "eagle-import:RES0402")
      (libsource (lib "eagle-import") (part "RESISTOR-0402"))
    )
    (comp (ref "R118")
      (value "220 Ohms")
      (footprint "eagle-import:RES0402")
      (libsource (lib "eagle-import") (part "RESISTOR-0402"))
    )
    (comp (ref "R119")
      (value "220 Ohms")
      (footprint "eagle-import:RES0402")
      (libsource (lib "eagle-import") (part "RESISTOR-0402"))
    )
    (comp (ref "R120")
      (value "2.2K Ohms")
      (footprint "eagle-import:RES0402")
      (libsource (lib "eagle-import") (part "RESISTOR-0402"))
    )
    (comp (ref "R121")
      (value "2.2K Ohms")
      (footprint "eagle-import:RES0402")
      (libsource (lib "eagle-import") (part "RESISTOR-0402"))
    )
    (comp (ref "RFCON101")
      (value "RFCON-U.FL")
      (footprint "eagle-import:U.FL")
      (libsource (lib "eagle-import") (part "RFCON-U.FL"))
    )
    (comp (ref "SD101")
      (value "MICRO-SD")
      (footprint "eagle-import:TE-2201778-1")
      (fields (field (name "MANUFACTURER") "TE Connectivity"))
      (libsource (lib "eagle-import") (part "MICRO-SD"))
    )
    (comp (ref "U101")
      (value "MIC2019")
      (footprint "eagle-import:SOT23-6")
      (libsource (lib "eagle-import") (part "MIC2091"))
    )
    (comp (ref "U102")
      (value "RPI-CM4")
      (footprint "eagle-import:RPI-CM4")
      (libsource (lib "eagle-import") (part "RPI-CM4"))
    )
    (comp (ref "C1201")
      (value "100nF")
      (footprint "eagle-import:CAP0402")
      (libsource (lib "eagle-import") (part "CAPACITOR-0402"))
    )
    (comp (ref "C1202")
      (value "100nF")
      (footprint "eagle-import:CAP0402")
      (libsource (lib "eagle-import") (part "CAPACITOR-0402"))
    )
    (comp (ref "C1203")
      (value "100nF")
      (footprint "eagle-import:CAP0402")
      (libsource (lib "eagle-import") (part "CAPACITOR-0402"))
    )
    (comp (ref "C1204")
      (value "100nF")
      (footprint "eagle-import:CAP0402")
      (libsource (lib "eagle-import") (part "CAPACITOR-0402"))
    )
    (comp (ref "C1205")
      (value "4.7uF")
      (footprint "eagle-import:CAP0603")
      (libsource (lib "eagle-import") (part "CAPACITOR-0603"))
    )
    (comp (ref "C1206")
      (value "10nF")
      (footprint "eagle-import:CAP0402")
      (libsource (lib "eagle-import") (part "CAPACITOR-0402"))
    )
    (comp (ref "C1207")
      (value "10nF")
      (footprint "eagle-import:CAP0402")
      (libsource (lib "eagle-import") (part "CAPACITOR-0402"))
    )
    (comp (ref "C1208")
      (value "10nF")
      (footprint "eagle-import:CAP0402")
      (libsource (lib "eagle-import") (part "CAPACITOR-0402"))
    )
    (comp (ref "C1209")
      (value "100nF")
      (footprint "eagle-import:CAP0402")
      (libsource (lib "eagle-import") (part "CAPACITOR-0402"))
    )
    (comp (ref "C1210")
      (value "100uF")
      (footprint "eagle-import:CAP1206")
      (libsource (lib "eagle-import") (part "CAPACITOR-1206"))
    )
    (comp (ref "C1211")
      (value "470pF")
      (footprint "eagle-import:CAP0402")
      (libsource (lib "eagle-import") (part "CAPACITOR-0402"))
    )
    (comp (ref "C1212")
      (value "10uF")
      (footprint "eagle-import:CAP0603")
      (libsource (lib "eagle-import") (part "CAPACITOR-0603"))
    )
    (comp (ref "C1213")
      (value "10uF")
      (footprint "eagle-import:CAP0402")
      (libsource (lib "eagle-import") (part "CAPACITOR-0402"))
    )
    (comp (ref "C1214")
      (value "10uF")
      (footprint "eagle-import:CAP0402")
      (libsource (lib "eagle-import") (part "CAPACITOR-0402"))
    )
    (comp (ref "C1215")
      (value "100nF")
      (footprint "eagle-import:CAP0402")
      (libsource (lib "eagle-import") (part "CAPACITOR-0402"))
    )
    (comp (ref "C1216")
      (value "10uF")
      (footprint "eagle-import:CAP0402")
      (libsource (lib "eagle-import") (part "CAPACITOR-0402"))
    )
    (comp (ref "C1217")
      (value "10uF")
      (footprint "eagle-import:CAP0402")
      (libsource (lib "eagle-import") (part "CAPACITOR-0402"))
    )
    (comp (ref "C1218")
      (value "10uF")
      (footprint "eagle-import:CAP0402")
      (libsource (lib "eagle-import") (part "CAPACITOR-0402"))
    )
    (comp (ref "C1219")
      (value "10uF")
      (footprint "eagle-import:CAP0402")
      (libsource (lib "eagle-import") (part "CAPACITOR-0402"))
    )
    (comp (ref "C1220")
      (value "10uF")
      (footprint "eagle-import:CAP0402")
      (libsource (lib "eagle-import") (part "CAPACITOR-0402"))
    )
    (comp (ref "C1221")
      (value "470pF")
      (footprint "eagle-import:CAP0402")
      (libsource (lib "eagle-import") (part "CAPACITOR-0402"))
    )
    (comp (ref "C1222")
      (value "47uF")
      (footprint "eagle-import:CAP0603")
      (libsource (lib "eagle-import") (part "CAPACITOR-0603"))
    )
    (comp (ref "C1223")
      (value "47uF")
      (footprint "eagle-import:CAP0603")
      (libsource (lib "eagle-import") (part "CAPACITOR-0603"))
    )
    (comp (ref "C1224")
      (value "4.7uF")
      (footprint "eagle-import:CAP0402")
      (libsource (lib "eagle-import") (part "CAPACITOR-0402"))
    )
    (comp (ref "C1225")
      (value "1uF")
      (footprint "eagle-import:CAP0402")
      (libsource (lib "eagle-import") (part "CAPACITOR-0402"))
    )
    (comp (ref "C1226")
      (value "100nF")
      (footprint "eagle-import:CAP0402")
      (libsource (lib "eagle-import") (part "CAPACITOR-0402"))
    )
    (comp (ref "C1227")
      (value "100uF")
      (footprint "eagle-import:CAP1206")
      (libsource (lib "eagle-import") (part "CAPACITOR-1206"))
    )
    (comp (ref "C1228")
      (value "100nF")
      (footprint "eagle-import:CAP0402")
      (libsource (lib "eagle-import") (part "CAPACITOR-0402"))
    )
    (comp (ref "C1229")
      (value "100nF")
      (footprint "eagle-import:CAP0402")
      (libsource (lib "eagle-import") (part "CAPACITOR-0402"))
    )
    (comp (ref "C1230")
      (value "100nF")
      (footprint "eagle-import:CAP0402")
      (libsource (lib "eagle-import") (part "CAPACITOR-0402"))
    )
    (comp (ref "C1231")
      (value "10nF")
      (footprint "eagle-import:CAP0402")
      (libsource (lib "eagle-import") (part "CAPACITOR-0402"))
    )
    (comp (ref "C1232")
      (value "4.7uF")
      (footprint "eagle-import:CAP0603")
      (libsource (lib "eagle-import") (part "CAPACITOR-0603"))
    )
    (comp (ref "C1233")
      (value "10nF")
      (footprint "eagle-import:CAP0402")
      (libsource (lib "eagle-import") (part "CAPACITOR-0402"))
    )
    (comp (ref "C1234")
      (value "1uF")
      (footprint "eagle-import:CAP0402")
      (libsource (lib "eagle-import") (part "CAPACITOR-0402"))
    )
    (comp (ref "C1235")
      (value "10uF")
      (footprint "eagle-import:CAP0402")
      (libsource (lib "eagle-import") (part "CAPACITOR-0402"))
    )
    (comp (ref "C1236")
      (value "10uF")
      (footprint "eagle-import:CAP0402")
      (libsource (lib "eagle-import") (part "CAPACITOR-0402"))
    )
    (comp (ref "C1237")
      (value "10uF")
      (footprint "eagle-import:CAP0402")
      (libsource (lib "eagle-import") (part "CAPACITOR-0402"))
    )
    (comp (ref "C1238")
      (value "10uF")
      (footprint "eagle-import:CAP0402")
      (libsource (lib "eagle-import") (part "CAPACITOR-0402"))
    )
    (comp (ref "C1239")
      (value "100nF")
      (footprint "eagle-import:CAP0402")
      (libsource (lib "eagle-import") (part "CAPACITOR-0402"))
    )
    (comp (ref "C1240")
      (value "10uF")
      (footprint "eagle-import:CAP0402")
      (libsource (lib "eagle-import") (part "CAPACITOR-0402"))
    )
    (comp (ref "C1241")
      (value "10uF")
      (footprint "eagle-import:CAP0402")
      (libsource (lib "eagle-import") (part "CAPACITOR-0402"))
    )
    (comp (ref "C1242")
      (value "4.7uF")
      (footprint "eagle-import:CAP0603")
      (libsource (lib "eagle-import") (part "CAPACITOR-0603"))
    )
    (comp (ref "C1243")
      (value "10uF")
      (footprint "eagle-import:CAP0402")
      (libsource (lib "eagle-import") (part "CAPACITOR-0402"))
    )
    (comp (ref "C1244")
      (value "10uF")
      (footprint "eagle-import:CAP0402")
      (libsource (lib "eagle-import") (part "CAPACITOR-0402"))
    )
    (comp (ref "C1245")
      (value "100nF")
      (footprint "eagle-import:CAP0402")
      (libsource (lib "eagle-import") (part "CAPACITOR-0402"))
    )
    (comp (ref "C1246")
      (value "100uF")
      (footprint "eagle-import:CAP1206")
      (libsource (lib "eagle-import") (part "CAPACITOR-1206"))
    )
    (comp (ref "C1247")
      (value "100nF")
      (footprint "eagle-import:CAP0402")
      (libsource (lib "eagle-import") (part "CAPACITOR-0402"))
    )
    (comp (ref "C1248")
      (value "4.7uF")
      (footprint "eagle-import:CAP0603")
      (libsource (lib "eagle-import") (part "CAPACITOR-0603"))
    )
    (comp (ref "C1249")
      (value "470pF")
      (footprint "eagle-import:CAP0402")
      (libsource (lib "eagle-import") (part "CAPACITOR-0402"))
    )
    (comp (ref "C1250")
      (value "100nF")
      (footprint "eagle-import:CAP0402")
      (libsource (lib "eagle-import") (part "CAPACITOR-0402"))
    )
    (comp (ref "C1251")
      (value "470pF")
      (footprint "eagle-import:CAP0402")
      (libsource (lib "eagle-import") (part "CAPACITOR-0402"))
    )
    (comp (ref "C1252")
      (value "470pF")
      (footprint "eagle-import:CAP0402")
      (libsource (lib "eagle-import") (part "CAPACITOR-0402"))
    )
    (comp (ref "C1253")
      (value "100nF")
      (footprint "eagle-import:CAP0402")
      (libsource (lib "eagle-import") (part "CAPACITOR-0402"))
    )
    (comp (ref "C1254")
      (value "100uF")
      (footprint "eagle-import:CAP1206")
      (libsource (lib "eagle-import") (part "CAPACITOR-1206"))
    )
    (comp (ref "C1255")
      (value "10uF")
      (footprint "eagle-import:CAP0402")
      (libsource (lib "eagle-import") (part "CAPACITOR-0402"))
    )
    (comp (ref "C1256")
      (value "100nF")
      (footprint "eagle-import:CAP0402")
      (libsource (lib "eagle-import") (part "CAPACITOR-0402"))
    )
    (comp (ref "C1257")
      (value "10uF")
      (footprint "eagle-import:CAP0402")
      (libsource (lib "eagle-import") (part "CAPACITOR-0402"))
    )
    (comp (ref "C1258")
      (value "4.7uF")
      (footprint "eagle-import:CAP0603")
      (libsource (lib "eagle-import") (part "CAPACITOR-0603"))
    )
    (comp (ref "C1259")
      (value "10uF")
      (footprint "eagle-import:CAP0402")
      (libsource (lib "eagle-import") (part "CAPACITOR-0402"))
    )
    (comp (ref "L1201")
      (value "2.2uH")
      (footprint "eagle-import:XGL35XX")
      (fields
        (field (name "CURRENT") "3.8A")
        (field (name "REF") "XGL3515-222")
        (field (name "CURRENT_1") "3.8A")
      )
      (libsource (lib "eagle-import") (part "XGL3515-222"))
    )
    (comp (ref "L1202")
      (value "2.2uH")
      (footprint "eagle-import:XGL35XX")
      (fields
        (field (name "CURRENT") "3.8A")
        (field (name "REF") "XGL3515-222")
        (field (name "CURRENT_1") "3.8A")
      )
      (libsource (lib "eagle-import") (part "XGL3515-222"))
    )
    (comp (ref "L1203")
      (value "2.2uH")
      (footprint "eagle-import:XGL35XX")
      (fields
        (field (name "CURRENT") "3.8A")
        (field (name "REF") "XGL3515-222")
        (field (name "CURRENT_1") "3.8A")
      )
      (libsource (lib "eagle-import") (part "XGL3515-222"))
    )
    (comp (ref "L1204")
      (value "4.7uH")
      (footprint "eagle-import:XGL35XX")
      (fields (field (name "CURRENT") "3.1A") (field (name "REF") "XGL3520-472"))
      (libsource (lib "eagle-import") (part "XGL3520-472"))
    )
    (comp (ref "L1205")
      (value "2.2uH")
      (footprint "eagle-import:XGL35XX")
      (fields
        (field (name "CURRENT") "3.8A")
        (field (name "REF") "XGL3515-222")
        (field (name "CURRENT_1") "3.8A")
      )
      (libsource (lib "eagle-import") (part "XGL3515-222"))
    )
    (comp (ref "R1201")
      (value "10K Ohms")
      (footprint "eagle-import:RES0402")
      (libsource (lib "eagle-import") (part "RESISTOR-0402"))
    )
    (comp (ref "R1202")
      (value "118K Ohms")
      (footprint "eagle-import:RES0402")
      (libsource (lib "eagle-import") (part "RESISTOR-0402"))
    )
    (comp (ref "R1203")
      (value "100K Ohms")
      (footprint "eagle-import:RES0402")
      (libsource (lib "eagle-import") (part "RESISTOR-0402"))
    )
    (comp (ref "R1204")
      (value "10K Ohms")
      (footprint "eagle-import:RES0402")
      (libsource (lib "eagle-import") (part "RESISTOR-0402"))
    )
    (comp (ref "R1205")
      (value "301K Ohms")
      (footprint "eagle-import:RES0402")
      (libsource (lib "eagle-import") (part "RESISTOR-0402"))
    )
    (comp (ref "R1206")
      (value "158K Ohms")
      (footprint "eagle-import:RES0402")
      (libsource (lib "eagle-import") (part "RESISTOR-0402"))
    )
    (comp (ref "R1207")
      (value "10K Ohms")
      (footprint "eagle-import:RES0402")
      (libsource (lib "eagle-import") (part "RESISTOR-0402"))
    )
    (comp (ref "R1208")
      (value "324K Ohms")
      (footprint "eagle-import:RES0402")
      (libsource (lib "eagle-import") (part "RESISTOR-0402"))
    )
    (comp (ref "R1209")
      (value "107K Ohms")
      (footprint "eagle-import:RES0402")
      (libsource (lib "eagle-import") (part "RESISTOR-0402"))
    )
    (comp (ref "R1210")
      (value "10K Ohms")
      (footprint "eagle-import:RES0402")
      (libsource (lib "eagle-import") (part "RESISTOR-0402"))
    )
    (comp (ref "R1211")
      (value "10K Ohms")
      (footprint "eagle-import:RES0402")
      (libsource (lib "eagle-import") (part "RESISTOR-0402"))
    )
    (comp (ref "R1212")
      (value "309K Ohms")
      (footprint "eagle-import:RES0402")
      (libsource (lib "eagle-import") (part "RESISTOR-0402"))
    )
    (comp (ref "R1213")
      (value "71.5K Ohms")
      (footprint "eagle-import:RES0402")
      (libsource (lib "eagle-import") (part "RESISTOR-0402"))
    )
    (comp (ref "R1214")
      (value "274K Ohms")
      (footprint "eagle-import:RES0402")
      (libsource (lib "eagle-import") (part "RESISTOR-0402"))
    )
    (comp (ref "R1215")
      (value "294K Ohms")
      (footprint "eagle-import:RES0402")
      (libsource (lib "eagle-import") (part "RESISTOR-0402"))
    )
    (comp (ref "U1201")
      (value "ADM7172ACPZ-5.0")
      (footprint "eagle-import:LFCSP8_3X3")
      (libsource (lib "eagle-import") (part "ADM7172ACPZ-5.0"))
    )
    (comp (ref "U1202")
      (value "ADM7171ACPZ-1.3")
      (footprint "eagle-import:LFCSP8_3X3")
      (libsource (lib "eagle-import") (part "ADM7171ACPZ-1.3"))
    )
    (comp (ref "U1203")
      (value "ADM7171ACPZ-3.3")
      (footprint "eagle-import:LFCSP8_3X3")
      (libsource (lib "eagle-import") (part "ADM7171ACPZ-3.3"))
    )
    (comp (ref "U1204")
      (value "MIC23159")
      (footprint "eagle-import:VQFN20")
      (libsource (lib "eagle-import") (part "MIC23159"))
    )
    (comp (ref "U1205")
      (value "MIC5166")
      (footprint "eagle-import:DFN10")
      (libsource (lib "eagle-import") (part "MIC5166"))
    )
    (comp (ref "U1206")
      (value "ADM7171ACPZ-1.3")
      (footprint "eagle-import:LFCSP8_3X3")
      (libsource (lib "eagle-import") (part "ADM7171ACPZ-1.3"))
    )
    (comp (ref "U1207")
      (value "ADM7171ACPZ-3.3")
      (footprint "eagle-import:LFCSP8_3X3")
      (libsource (lib "eagle-import") (part "ADM7171ACPZ-3.3"))
    )
    (comp (ref "U1208")
      (value "MIC23159")
      (footprint "eagle-import:VQFN20")
      (libsource (lib "eagle-import") (part "MIC23159"))
    )
    (comp (ref "U1209")
      (value "MIC23155")
      (footprint "eagle-import:DFN10_0.65P")
      (libsource (lib "eagle-import") (part "MIC23155"))
    )
    (comp (ref "U1210")
      (value "ADP7142AUJZ-3.3")
      (footprint "eagle-import:SOT23-5")
      (libsource (lib "eagle-import") (part "ADP7142AUJZ-3.3"))
    )
    (comp (ref "C501")
      (value "18pF")
      (footprint "eagle-import:CAP0402")
      (libsource (lib "eagle-import") (part "CAPACITOR-0402"))
    )
    (comp (ref "C502")
      (value "18pF")
      (footprint "eagle-import:CAP0402")
      (libsource (lib "eagle-import") (part "CAPACITOR-0402"))
    )
    (comp (ref "C503")
      (value "10uF")
      (footprint "eagle-import:CAP0603")
      (libsource (lib "eagle-import") (part "CAPACITOR-0603"))
    )
    (comp (ref "C504")
      (value "10uF")
      (footprint "eagle-import:CAP0603")
      (libsource (lib "eagle-import") (part "CAPACITOR-0603"))
    )
    (comp (ref "C505")
      (value "100pF")
      (footprint "eagle-import:CAP0402")
      (libsource (lib "eagle-import") (part "CAPACITOR-0402"))
    )
    (comp (ref "C506")
      (value "100pF")
      (footprint "eagle-import:CAP0402")
      (libsource (lib "eagle-import") (part "CAPACITOR-0402"))
    )
    (comp (ref "C507")
      (value "100nF")
      (footprint "eagle-import:CAP0402")
      (libsource (lib "eagle-import") (part "CAPACITOR-0402"))
    )
    (comp (ref "C508")
      (value "100nF")
      (footprint "eagle-import:CAP0402")
      (libsource (lib "eagle-import") (part "CAPACITOR-0402"))
    )
    (comp (ref "C509")
      (value "18pF")
      (footprint "eagle-import:CAP0402")
      (libsource (lib "eagle-import") (part "CAPACITOR-0402"))
    )
    (comp (ref "C510")
      (value "18pF")
      (footprint "eagle-import:CAP0402")
      (libsource (lib "eagle-import") (part "CAPACITOR-0402"))
    )
    (comp (ref "C511")
      (value "18pF")
      (footprint "eagle-import:CAP0402")
      (libsource (lib "eagle-import") (part "CAPACITOR-0402"))
    )
    (comp (ref "C512")
      (value "18pF")
      (footprint "eagle-import:CAP0402")
      (libsource (lib "eagle-import") (part "CAPACITOR-0402"))
    )
    (comp (ref "C513")
      (value "18pF")
      (footprint "eagle-import:CAP0402")
      (libsource (lib "eagle-import") (part "CAPACITOR-0402"))
    )
    (comp (ref "C514")
      (value "18pF")
      (footprint "eagle-import:CAP0402")
      (libsource (lib "eagle-import") (part "CAPACITOR-0402"))
    )
    (comp (ref "C515")
      (value "18pF")
      (footprint "eagle-import:CAP0402")
      (libsource (lib "eagle-import") (part "CAPACITOR-0402"))
    )
    (comp (ref "C516")
      (value "18pF")
      (footprint "eagle-import:CAP0402")
      (libsource (lib "eagle-import") (part "CAPACITOR-0402"))
    )
    (comp (ref "C517")
      (value "10uF")
      (footprint "eagle-import:CAP0603")
      (libsource (lib "eagle-import") (part "CAPACITOR-0603"))
    )
    (comp (ref "C518")
      (value "10uF")
      (footprint "eagle-import:CAP0603")
      (libsource (lib "eagle-import") (part "CAPACITOR-0603"))
    )
    (comp (ref "C519")
      (value "10uF")
      (footprint "eagle-import:CAP0603")
      (libsource (lib "eagle-import") (part "CAPACITOR-0603"))
    )
    (comp (ref "C520")
      (value "10uF")
      (footprint "eagle-import:CAP0603")
      (libsource (lib "eagle-import") (part "CAPACITOR-0603"))
    )
    (comp (ref "C521")
      (value "10uF")
      (footprint "eagle-import:CAP0603")
      (libsource (lib "eagle-import") (part "CAPACITOR-0603"))
    )
    (comp (ref "C522")
      (value "10uF")
      (footprint "eagle-import:CAP0603")
      (libsource (lib "eagle-import") (part "CAPACITOR-0603"))
    )
    (comp (ref "C523")
      (value "10uF")
      (footprint "eagle-import:CAP0402")
      (libsource (lib "eagle-import") (part "CAPACITOR-0402"))
    )
    (comp (ref "C524")
      (value "10uF")
      (footprint "eagle-import:CAP0402")
      (libsource (lib "eagle-import") (part "CAPACITOR-0402"))
    )
    (comp (ref "C525")
      (value "1nF")
      (footprint "eagle-import:CAP0402")
      (libsource (lib "eagle-import") (part "CAPACITOR-0402"))
    )
    (comp (ref "C526")
      (value "1nF")
      (footprint "eagle-import:CAP0402")
      (libsource (lib "eagle-import") (part "CAPACITOR-0402"))
    )
    (comp (ref "C527")
      (value "1nF")
      (footprint "eagle-import:CAP0402")
      (libsource (lib "eagle-import") (part "CAPACITOR-0402"))
    )
    (comp (ref "C528")
      (value "1nF")
      (footprint "eagle-import:CAP0402")
      (libsource (lib "eagle-import") (part "CAPACITOR-0402"))
    )
    (comp (ref "C529")
      (value "1nF")
      (footprint "eagle-import:CAP0402")
      (libsource (lib "eagle-import") (part "CAPACITOR-0402"))
    )
    (comp (ref "C530")
      (value "18pF")
      (footprint "eagle-import:CAP0402")
      (libsource (lib "eagle-import") (part "CAPACITOR-0402"))
    )
    (comp (ref "C531")
      (value "18pF")
      (footprint "eagle-import:CAP0402")
      (libsource (lib "eagle-import") (part "CAPACITOR-0402"))
    )
    (comp (ref "C532")
      (value "18pF")
      (footprint "eagle-import:CAP0402")
      (libsource (lib "eagle-import") (part "CAPACITOR-0402"))
    )
    (comp (ref "C533")
      (value "18pF")
      (footprint "eagle-import:CAP0402")
      (libsource (lib "eagle-import") (part "CAPACITOR-0402"))
    )
    (comp (ref "C534")
      (value "10uF")
      (footprint "eagle-import:CAP0402")
      (libsource (lib "eagle-import") (part "CAPACITOR-0402"))
    )
    (comp (ref "C535")
      (value "10uF")
      (footprint "eagle-import:CAP0402")
      (libsource (lib "eagle-import") (part "CAPACITOR-0402"))
    )
    (comp (ref "C536")
      (value "1nF")
      (footprint "eagle-import:CAP0402")
      (libsource (lib "eagle-import") (part "CAPACITOR-0402"))
    )
    (comp (ref "C537")
      (value "1nF")
      (footprint "eagle-import:CAP0402")
      (libsource (lib "eagle-import") (part "CAPACITOR-0402"))
    )
    (comp (ref "C538")
      (value "18pF")
      (footprint "eagle-import:CAP0402")
      (libsource (lib "eagle-import") (part "CAPACITOR-0402"))
    )
    (comp (ref "C539")
      (value "18pF")
      (footprint "eagle-import:CAP0402")
      (libsource (lib "eagle-import") (part "CAPACITOR-0402"))
    )
    (comp (ref "C540")
      (value "1nF")
      (footprint "eagle-import:CAP0402")
      (libsource (lib "eagle-import") (part "CAPACITOR-0402"))
    )
    (comp (ref "C541")
      (value "1nF")
      (footprint "eagle-import:CAP0402")
      (libsource (lib "eagle-import") (part "CAPACITOR-0402"))
    )
    (comp (ref "C542")
      (value "100nF")
      (footprint "eagle-import:CAP0402")
      (libsource (lib "eagle-import") (part "CAPACITOR-0402"))
    )
    (comp (ref "C543")
      (value "100nF")
      (footprint "eagle-import:CAP0402")
      (libsource (lib "eagle-import") (part "CAPACITOR-0402"))
    )
    (comp (ref "C544")
      (value "18pF")
      (footprint "eagle-import:CAP0402")
      (libsource (lib "eagle-import") (part "CAPACITOR-0402"))
    )
    (comp (ref "C545")
      (value "18pF")
      (footprint "eagle-import:CAP0402")
      (libsource (lib "eagle-import") (part "CAPACITOR-0402"))
    )
    (comp (ref "C546")
      (value "18pF")
      (footprint "eagle-import:CAP0402")
      (libsource (lib "eagle-import") (part "CAPACITOR-0402"))
    )
    (comp (ref "C547")
      (value "18pF")
      (footprint "eagle-import:CAP0402")
      (libsource (lib "eagle-import") (part "CAPACITOR-0402"))
    )
    (comp (ref "C548")
      (value "1nF")
      (footprint "eagle-import:CAP0402")
      (libsource (lib "eagle-import") (part "CAPACITOR-0402"))
    )
    (comp (ref "C549")
      (value "1nF")
      (footprint "eagle-import:CAP0402")
      (libsource (lib "eagle-import") (part "CAPACITOR-0402"))
    )
    (comp (ref "C550")
      (value "1nF")
      (footprint "eagle-import:CAP0402")
      (libsource (lib "eagle-import") (part "CAPACITOR-0402"))
    )
    (comp (ref "C551")
      (value "18pF")
      (footprint "eagle-import:CAP0402")
      (libsource (lib "eagle-import") (part "CAPACITOR-0402"))
    )
    (comp (ref "C552")
      (value "18pF")
      (footprint "eagle-import:CAP0402")
      (libsource (lib "eagle-import") (part "CAPACITOR-0402"))
    )
    (comp (ref "C553")
      (value "18pF")
      (footprint "eagle-import:CAP0402")
      (libsource (lib "eagle-import") (part "CAPACITOR-0402"))
    )
    (comp (ref "C554")
      (value "18pF")
      (footprint "eagle-import:CAP0402")
      (libsource (lib "eagle-import") (part "CAPACITOR-0402"))
    )
    (comp (ref "D501")
      (value "PGB1010402")
      (footprint "eagle-import:TVS0402")
      (libsource (lib "eagle-import") (part "PGB1010402"))
    )
    (comp (ref "D502")
      (value "PGB1010402")
      (footprint "eagle-import:TVS0402")
      (libsource (lib "eagle-import") (part "PGB1010402"))
    )
    (comp (ref "D503")
      (value "PGB1010402")
      (footprint "eagle-import:TVS0402")
      (libsource (lib "eagle-import") (part "PGB1010402"))
    )
    (comp (ref "D504")
      (value "PGB1010402")
      (footprint "eagle-import:TVS0402")
      (libsource (lib "eagle-import") (part "PGB1010402"))
    )
    (comp (ref "D505")
      (value "LED0603")
      (footprint "eagle-import:0603")
      (fields (field (name "COLOR") "YELLOW"))
      (libsource (lib "eagle-import") (part "LED0603"))
    )
    (comp (ref "D506")
      (value "LED0603")
      (footprint "eagle-import:0603")
      (fields (field (name "COLOR") "YELLOW"))
      (libsource (lib "eagle-import") (part "LED0603"))
    )
    (comp (ref "D507")
      (value "LED0603")
      (footprint "eagle-import:0603")
      (fields (field (name "COLOR") "YELLOW"))
      (libsource (lib "eagle-import") (part "LED0603"))
    )
    (comp (ref "D508")
      (value "LED0603")
      (footprint "eagle-import:0603")
      (fields (field (name "COLOR") "YELLOW"))
      (libsource (lib "eagle-import") (part "LED0603"))
    )
    (comp (ref "D509")
      (value "PGB1010402")
      (footprint "eagle-import:TVS0402")
      (libsource (lib "eagle-import") (part "PGB1010402"))
    )
    (comp (ref "D510")
      (value "PGB1010402")
      (footprint "eagle-import:TVS0402")
      (libsource (lib "eagle-import") (part "PGB1010402"))
    )
    (comp (ref "D511")
      (value "PGB1010402")
      (footprint "eagle-import:TVS0402")
      (libsource (lib "eagle-import") (part "PGB1010402"))
    )
    (comp (ref "D512")
      (value "PGB1010402")
      (footprint "eagle-import:TVS0402")
      (libsource (lib "eagle-import") (part "PGB1010402"))
    )
    (comp (ref "L501")
      (value "330nH")
      (footprint "eagle-import:IND0805")
      (libsource (lib "eagle-import") (part "INDUCTOR-0805"))
    )
    (comp (ref "L502")
      (value "330nH")
      (footprint "eagle-import:IND0805")
      (libsource (lib "eagle-import") (part "INDUCTOR-0805"))
    )
    (comp (ref "L503")
      (value "330nH")
      (footprint "eagle-import:IND0603")
      (libsource (lib "eagle-import") (part "INDUCTOR-0603"))
    )
    (comp (ref "L504")
      (value "330nH")
      (footprint "eagle-import:IND0603")
      (libsource (lib "eagle-import") (part "INDUCTOR-0603"))
    )
    (comp (ref "L505")
      (value "330nH")
      (footprint "eagle-import:IND0603")
      (libsource (lib "eagle-import") (part "INDUCTOR-0603"))
    )
    (comp (ref "L506")
      (value "330nH")
      (footprint "eagle-import:IND0603")
      (libsource (lib "eagle-import") (part "INDUCTOR-0603"))
    )
    (comp (ref "L507")
      (value "330nH")
      (footprint "eagle-import:IND0603")
      (libsource (lib "eagle-import") (part "INDUCTOR-0603"))
    )
    (comp (ref "L508")
      (value "330nH")
      (footprint "eagle-import:IND0603")
      (libsource (lib "eagle-import") (part "INDUCTOR-0603"))
    )
    (comp (ref "L509")
      (value "330nH")
      (footprint "eagle-import:IND0603")
      (libsource (lib "eagle-import") (part "INDUCTOR-0603"))
    )
    (comp (ref "L510")
      (value "330nH")
      (footprint "eagle-import:IND0603")
      (libsource (lib "eagle-import") (part "INDUCTOR-0603"))
    )
    (comp (ref "L511")
      (value "330nH")
      (footprint "eagle-import:IND0603")
      (libsource (lib "eagle-import") (part "INDUCTOR-0603"))
    )
    (comp (ref "L512")
      (value "330nH")
      (footprint "eagle-import:IND0603")
      (libsource (lib "eagle-import") (part "INDUCTOR-0603"))
    )
    (comp (ref "R501")
      (value "470 Ohms")
      (footprint "eagle-import:RES0402")
      (libsource (lib "eagle-import") (part "RESISTOR-0402"))
    )
    (comp (ref "R502")
      (value "470 Ohms")
      (footprint "eagle-import:RES0402")
      (libsource (lib "eagle-import") (part "RESISTOR-0402"))
    )
    (comp (ref "R503")
      (value "10K Ohms")
      (footprint "eagle-import:RES0402")
      (libsource (lib "eagle-import") (part "RESISTOR-0402"))
    )
    (comp (ref "R504")
      (value "10K Ohms")
      (footprint "eagle-import:RES0402")
      (libsource (lib "eagle-import") (part "RESISTOR-0402"))
    )
    (comp (ref "R505")
      (value "1K Ohms")
      (footprint "eagle-import:RES0402")
      (libsource (lib "eagle-import") (part "RESISTOR-0402"))
    )
    (comp (ref "R506")
      (value "1K Ohms")
      (footprint "eagle-import:RES0402")
      (libsource (lib "eagle-import") (part "RESISTOR-0402"))
    )
    (comp (ref "R507")
      (value "300 Ohms")
      (footprint "eagle-import:RES0402")
      (libsource (lib "eagle-import") (part "RESISTOR-0402"))
    )
    (comp (ref "R508")
      (value "300 Ohms")
      (footprint "eagle-import:RES0402")
      (libsource (lib "eagle-import") (part "RESISTOR-0402"))
    )
    (comp (ref "R509")
      (value "10K Ohms")
      (footprint "eagle-import:RES0402")
      (libsource (lib "eagle-import") (part "RESISTOR-0402"))
    )
    (comp (ref "R510")
      (value "10K Ohms")
      (footprint "eagle-import:RES0402")
      (libsource (lib "eagle-import") (part "RESISTOR-0402"))
    )
    (comp (ref "R511")
      (value "1K Ohms")
      (footprint "eagle-import:RES0402")
      (libsource (lib "eagle-import") (part "RESISTOR-0402"))
    )
    (comp (ref "R512")
      (value "1K Ohms")
      (footprint "eagle-import:RES0402")
      (libsource (lib "eagle-import") (part "RESISTOR-0402"))
    )
    (comp (ref "R513")
      (value "49.9 Ohms")
      (footprint "eagle-import:RES0402")
      (libsource (lib "eagle-import") (part "RESISTOR-0402"))
    )
    (comp (ref "R514")
      (value "10 Ohms")
      (footprint "eagle-import:RES0402")
      (libsource (lib "eagle-import") (part "RESISTOR-0402"))
    )
    (comp (ref "R515")
      (value "49.9 Ohms")
      (footprint "eagle-import:RES0402")
      (libsource (lib "eagle-import") (part "RESISTOR-0402"))
    )
    (comp (ref "R516")
      (value "10 Ohms")
      (footprint "eagle-import:RES0402")
      (libsource (lib "eagle-import") (part "RESISTOR-0402"))
    )
    (comp (ref "RFCON501")
      (value "RFCON-SMA-RA")
      (footprint "eagle-import:SMA-RA")
      (libsource (lib "eagle-import") (part "RFCON-SMA-RA"))
    )
    (comp (ref "RFCON502")
      (value "RFCON-SMA-RA")
      (footprint "eagle-import:SMA-RA")
      (libsource (lib "eagle-import") (part "RFCON-SMA-RA"))
    )
    (comp (ref "RFCON503")
      (value "RFCON-SMA-RA")
      (footprint "eagle-import:SMA-RA")
      (libsource (lib "eagle-import") (part "RFCON-SMA-RA"))
    )
    (comp (ref "RFCON504")
      (value "RFCON-SMA-RA")
      (footprint "eagle-import:SMA-RA")
      (libsource (lib "eagle-import") (part "RFCON-SMA-RA"))
    )
    (comp (ref "RFCON505")
      (value "RFCON-U.FL")
      (footprint "eagle-import:U.FL")
      (libsource (lib "eagle-import") (part "RFCON-U.FL"))
    )
    (comp (ref "RFCON506")
      (value "RFCON-U.FL")
      (footprint "eagle-import:U.FL")
      (libsource (lib "eagle-import") (part "RFCON-U.FL"))
    )
    (comp (ref "RFCON507")
      (value "RFCON-SMA-RA")
      (footprint "eagle-import:SMA-RA")
      (libsource (lib "eagle-import") (part "RFCON-SMA-RA"))
    )
    (comp (ref "RFCON508")
      (value "RFCON-SMA-RA")
      (footprint "eagle-import:SMA-RA")
      (libsource (lib "eagle-import") (part "RFCON-SMA-RA"))
    )
    (comp (ref "RFCON509")
      (value "RFCON-SMA")
      (footprint "eagle-import:SMA")
      (libsource (lib "eagle-import") (part "RFCON-SMA"))
    )
    (comp (ref "RFCON510")
      (value "RFCON-SMA")
      (footprint "eagle-import:SMA")
      (libsource (lib "eagle-import") (part "RFCON-SMA"))
    )
    (comp (ref "T501")
      (value "UWB1-85E")
      (footprint "eagle-import:UWB1")
      (libsource (lib "eagle-import") (part "UWB1-85E"))
    )
    (comp (ref "T502")
      (value "UWB1-85E")
      (footprint "eagle-import:UWB1")
      (libsource (lib "eagle-import") (part "UWB1-85E"))
    )
    (comp (ref "T503")
      (value "UWB1-85E")
      (footprint "eagle-import:UWB1")
      (libsource (lib "eagle-import") (part "UWB1-85E"))
    )
    (comp (ref "T504")
      (value "UWB1-85E")
      (footprint "eagle-import:UWB1")
      (libsource (lib "eagle-import") (part "UWB1-85E"))
    )
    (comp (ref "T505")
      (value "UWB1-85E")
      (footprint "eagle-import:UWB1")
      (libsource (lib "eagle-import") (part "UWB1-85E"))
    )
    (comp (ref "T506")
      (value "UWB1-85E")
      (footprint "eagle-import:UWB1")
      (libsource (lib "eagle-import") (part "UWB1-85E"))
    )
    (comp (ref "T507")
      (value "UWB1-85E")
      (footprint "eagle-import:UWB1")
      (libsource (lib "eagle-import") (part "UWB1-85E"))
    )
    (comp (ref "T508")
      (value "UWB1-85E")
      (footprint "eagle-import:UWB1")
      (libsource (lib "eagle-import") (part "UWB1-85E"))
    )
    (comp (ref "U501")
      (value "MIC2019")
      (footprint "eagle-import:SOT23-6")
      (libsource (lib "eagle-import") (part "MIC2091"))
    )
    (comp (ref "U502")
      (value "MIC2019")
      (footprint "eagle-import:SOT23-6")
      (libsource (lib "eagle-import") (part "MIC2091"))
    )
    (comp (ref "U503")
      (value "MIC2019")
      (footprint "eagle-import:SOT23-6")
      (libsource (lib "eagle-import") (part "MIC2091"))
    )
    (comp (ref "U504")
      (value "MIC2019")
      (footprint "eagle-import:SOT23-6")
      (libsource (lib "eagle-import") (part "MIC2091"))
    )
    (comp (ref "U505")
      (value "ADL5601")
      (footprint "eagle-import:SOT89")
      (libsource (lib "eagle-import") (part "ADL5?601"))
    )
    (comp (ref "U506")
      (value "ADL5601")
      (footprint "eagle-import:SOT89")
      (libsource (lib "eagle-import") (part "ADL5?601"))
    )
    (comp (ref "C901")
      (value "100nF")
      (footprint "eagle-import:CAP0402")
      (libsource (lib "eagle-import") (part "CAPACITOR-0402"))
    )
    (comp (ref "C902")
      (value "1uF")
      (footprint "eagle-import:CAP0402")
      (libsource (lib "eagle-import") (part "CAPACITOR-0402"))
    )
    (comp (ref "C903")
      (value "1uF")
      (footprint "eagle-import:CAP0402")
      (libsource (lib "eagle-import") (part "CAPACITOR-0402"))
    )
    (comp (ref "C904")
      (value "100nF")
      (footprint "eagle-import:CAP0402")
      (libsource (lib "eagle-import") (part "CAPACITOR-0402"))
    )
    (comp (ref "C905")
      (value "100nF")
      (footprint "eagle-import:CAP0402")
      (libsource (lib "eagle-import") (part "CAPACITOR-0402"))
    )
    (comp (ref "C906")
      (value "10pF")
      (footprint "eagle-import:CAP0402")
      (libsource (lib "eagle-import") (part "CAPACITOR-0402"))
    )
    (comp (ref "C907")
      (value "100nF")
      (footprint "eagle-import:CAP0402")
      (libsource (lib "eagle-import") (part "CAPACITOR-0402"))
    )
    (comp (ref "C908")
      (value "100nF")
      (footprint "eagle-import:CAP0402")
      (libsource (lib "eagle-import") (part "CAPACITOR-0402"))
    )
    (comp (ref "C909")
      (value "100nF")
      (footprint "eagle-import:CAP0402")
      (libsource (lib "eagle-import") (part "CAPACITOR-0402"))
    )
    (comp (ref "FB901")
      (value "1uH")
      (footprint "eagle-import:IND0603")
      (libsource (lib "eagle-import") (part "FERRITE-0603"))
    )
    (comp (ref "R901")
      (value "DNP")
      (footprint "eagle-import:RES0402")
      (libsource (lib "eagle-import") (part "RESISTOR-0402"))
    )
    (comp (ref "R902")
      (value "0 Ohms")
      (footprint "eagle-import:RES0402")
      (libsource (lib "eagle-import") (part "RESISTOR-0402"))
    )
    (comp (ref "R903")
      (value "10K Ohms")
      (footprint "eagle-import:RES0402")
      (libsource (lib "eagle-import") (part "RESISTOR-0402"))
    )
    (comp (ref "R904")
      (value "10K Ohms")
      (footprint "eagle-import:RES0402")
      (libsource (lib "eagle-import") (part "RESISTOR-0402"))
    )
    (comp (ref "R905")
      (value "10K Ohms")
      (footprint "eagle-import:RES0402")
      (libsource (lib "eagle-import") (part "RESISTOR-0402"))
    )
    (comp (ref "R906")
      (value "0 Ohms")
      (footprint "eagle-import:RES0402")
      (libsource (lib "eagle-import") (part "RESISTOR-0402"))
    )
    (comp (ref "R907")
      (value "0 Ohms")
      (footprint "eagle-import:RES0402")
      (libsource (lib "eagle-import") (part "RESISTOR-0402"))
    )
    (comp (ref "R908")
      (value "100nF")
      (footprint "eagle-import:RES0402")
      (libsource (lib "eagle-import") (part "RESISTOR-0402"))
    )
    (comp (ref "R909")
      (value "0 Ohms")
      (footprint "eagle-import:RES0402")
      (libsource (lib "eagle-import") (part "RESISTOR-0402"))
    )
    (comp (ref "R910")
      (value "0 Ohms")
      (footprint "eagle-import:RES0402")
      (libsource (lib "eagle-import") (part "RESISTOR-0402"))
    )
    (comp (ref "R911")
      (value "0 Ohms")
      (footprint "eagle-import:RES0402")
      (libsource (lib "eagle-import") (part "RESISTOR-0402"))
    )
    (comp (ref "R912")
      (value "100nF")
      (footprint "eagle-import:RES0402")
      (libsource (lib "eagle-import") (part "RESISTOR-0402"))
    )
    (comp (ref "R913")
      (value "0 Ohms")
      (footprint "eagle-import:RES0402")
      (libsource (lib "eagle-import") (part "RESISTOR-0402"))
    )
    (comp (ref "RFCON901")
      (value "RFCON-U.FL")
      (footprint "eagle-import:U.FL")
      (libsource (lib "eagle-import") (part "RFCON-U.FL"))
    )
    (comp (ref "RFCON902")
      (value "RFCON-U.FL")
      (footprint "eagle-import:U.FL")
      (libsource (lib "eagle-import") (part "RFCON-U.FL"))
    )
    (comp (ref "U901")
      (value "DSB321SDA")
      (footprint "eagle-import:TCXO-3225")
      (libsource (lib "eagle-import") (part "DSB321SDA"))
    )
    (comp (ref "U902")
      (value "SI5351C-B-GM")
      (footprint "eagle-import:QFN20")
      (libsource (lib "eagle-import") (part "SI5351C-B-GM"))
    )
    (comp (ref "C1001")
      (value "100nF")
      (footprint "eagle-import:CAP0402")
      (libsource (lib "eagle-import") (part "CAPACITOR-0402"))
    )
    (comp (ref "C1002")
      (value "220pF")
      (footprint "eagle-import:CAP0402")
      (fields (field (name "VOLTAGE") "50V"))
      (libsource (lib "eagle-import") (part "CAPACITOR-0402"))
    )
    (comp (ref "C1003")
      (value "1uF")
      (footprint "eagle-import:CAP0402")
      (libsource (lib "eagle-import") (part "CAPACITOR-0402"))
    )
    (comp (ref "C1004")
      (value "220pF")
      (footprint "eagle-import:CAP0402")
      (fields (field (name "VOLTAGE") "50V"))
      (libsource (lib "eagle-import") (part "CAPACITOR-0402"))
    )
    (comp (ref "C1005")
      (value "100nF")
      (footprint "eagle-import:CAP0402")
      (libsource (lib "eagle-import") (part "CAPACITOR-0402"))
    )
    (comp (ref "C1006")
      (value "100nF")
      (footprint "eagle-import:CAP0402")
      (libsource (lib "eagle-import") (part "CAPACITOR-0402"))
    )
    (comp (ref "C1007")
      (value "100nF")
      (footprint "eagle-import:CAP0402")
      (libsource (lib "eagle-import") (part "CAPACITOR-0402"))
    )
    (comp (ref "C1008")
      (value "100nF")
      (footprint "eagle-import:CAP0402")
      (libsource (lib "eagle-import") (part "CAPACITOR-0402"))
    )
    (comp (ref "C1009")
      (value "1uF")
      (footprint "eagle-import:CAP0402")
      (libsource (lib "eagle-import") (part "CAPACITOR-0402"))
    )
    (comp (ref "C1010")
      (value "100nF")
      (footprint "eagle-import:CAP0402")
      (libsource (lib "eagle-import") (part "CAPACITOR-0402"))
    )
    (comp (ref "C1011")
      (value "1uF")
      (footprint "eagle-import:CAP0402")
      (libsource (lib "eagle-import") (part "CAPACITOR-0402"))
    )
    (comp (ref "C1012")
      (value "100nF")
      (footprint "eagle-import:CAP0402")
      (libsource (lib "eagle-import") (part "CAPACITOR-0402"))
    )
    (comp (ref "C1013")
      (value "1uF")
      (footprint "eagle-import:CAP0402")
      (libsource (lib "eagle-import") (part "CAPACITOR-0402"))
    )
    (comp (ref "C1014")
      (value "1uF")
      (footprint "eagle-import:CAP0402")
      (libsource (lib "eagle-import") (part "CAPACITOR-0402"))
    )
    (comp (ref "D1001")
      (value "PGB102ST23")
      (footprint "eagle-import:SOT23")
      (libsource (lib "eagle-import") (part "PGB102ST23"))
    )
    (comp (ref "D1002")
      (value "SMAJ20A")
      (footprint "eagle-import:DO214AC")
      (fields (field (name "MF") "Littelfuse"))
      (libsource (lib "eagle-import") (part "SMAJA20"))
    )
    (comp (ref "D1003")
      (value "B0530W")
      (footprint "eagle-import:SOD-123")
      (libsource (lib "eagle-import") (part "B0530W"))
    )
    (comp (ref "D1004")
      (value "LED0603")
      (footprint "eagle-import:0603")
      (fields (field (name "COLOR") "BLUE"))
      (libsource (lib "eagle-import") (part "LED0603"))
    )
    (comp (ref "F1001")
      (value "PTC1206")
      (footprint "eagle-import:1206")
      (fields (field (name "HOLD") "5A") (field (name "TRIP") "6A"))
      (libsource (lib "eagle-import") (part "PTC Fuses_PTC1206"))
    )
    (comp (ref "L1001")
      (value "0603USB-951ML")
      (footprint "eagle-import:0603USB")
      (libsource (lib "eagle-import") (part "0603USB-951ML"))
    )
    (comp (ref "R1001")
      (value "330 Ohms")
      (footprint "eagle-import:RES0402")
      (libsource (lib "eagle-import") (part "RESISTOR-0402"))
    )
    (comp (ref "R1002")
      (value "10K Ohms")
      (footprint "eagle-import:RES0402")
      (libsource (lib "eagle-import") (part "RESISTOR-0402"))
    )
    (comp (ref "R1003")
      (value "10K Ohms")
      (footprint "eagle-import:RES0402")
      (libsource (lib "eagle-import") (part "RESISTOR-0402"))
    )
    (comp (ref "R1004")
      (value "4.7K Ohms")
      (footprint "eagle-import:RES0402")
      (libsource (lib "eagle-import") (part "RESISTOR-0402"))
    )
    (comp (ref "R1005")
      (value "90.9K Ohms")
      (footprint "eagle-import:RES0402")
      (libsource (lib "eagle-import") (part "RESISTOR-0402"))
    )
    (comp (ref "R1006")
      (value "10K Ohms")
      (footprint "eagle-import:RES0402")
      (libsource (lib "eagle-import") (part "RESISTOR-0402"))
    )
    (comp (ref "R1007")
      (value "4.7K Ohms")
      (footprint "eagle-import:RES0402")
      (libsource (lib "eagle-import") (part "RESISTOR-0402"))
    )
    (comp (ref "R1008")
      (value "0 Ohms")
      (footprint "eagle-import:RES0402")
      (libsource (lib "eagle-import") (part "RESISTOR-0402"))
    )
    (comp (ref "R1009")
      (value "10K Ohms")
      (footprint "eagle-import:RES0402")
      (libsource (lib "eagle-import") (part "RESISTOR-0402"))
    )
    (comp (ref "R1010")
      (value "470 Ohms")
      (footprint "eagle-import:RES0402")
      (libsource (lib "eagle-import") (part "RESISTOR-0402"))
    )
    (comp (ref "R1011")
      (value "10K Ohms")
      (footprint "eagle-import:RES0402")
      (libsource (lib "eagle-import") (part "RESISTOR-0402"))
    )
    (comp (ref "R1012")
      (value "10K Ohms")
      (footprint "eagle-import:RES0402")
      (libsource (lib "eagle-import") (part "RESISTOR-0402"))
    )
    (comp (ref "R1013")
      (value "1K Ohms")
      (footprint "eagle-import:RES0402")
      (libsource (lib "eagle-import") (part "RESISTOR-0402"))
    )
    (comp (ref "R1014")
      (value "10K Ohms")
      (footprint "eagle-import:RES0402")
      (libsource (lib "eagle-import") (part "RESISTOR-0402"))
    )
    (comp (ref "S1001")
      (value "TAC_SWITCHSMD_4.5X4.5")
      (footprint "eagle-import:TAC_SW_SMD_4.5X4.5")
      (libsource (lib "eagle-import") (part "TAC_SWITCHSMD_4.5X4.5"))
    )
    (comp (ref "TC1001")
      (value "TC2050-IDC")
      (footprint "eagle-import:TC2050-IDC")
      (libsource (lib "eagle-import") (part "TC2050-IDC"))
    )
    (comp (ref "TP8")
      (value "TESTPOINT-0.7MM")
      (footprint "eagle-import:PAD0.7MM")
      (libsource (lib "eagle-import") (part "TESTPOINT-0.7MM"))
    )
    (comp (ref "TP9")
      (value "TESTPOINT-0.7MM")
      (footprint "eagle-import:PAD0.7MM")
      (libsource (lib "eagle-import") (part "TESTPOINT-0.7MM"))
    )
    (comp (ref "TP10")
      (value "TESTPOINT-0.7MM")
      (footprint "eagle-import:PAD0.7MM")
      (libsource (lib "eagle-import") (part "TESTPOINT-0.7MM"))
    )
    (comp (ref "TP12")
      (value "TESTPOINT-0.7MM")
      (footprint "eagle-import:PAD0.7MM")
      (libsource (lib "eagle-import") (part "TESTPOINT-0.7MM"))
    )
    (comp (ref "U1001")
      (value "LTC4313-3")
      (footprint "eagle-import:DFN8")
      (libsource (lib "eagle-import") (part "LTC4313-3"))
    )
    (comp (ref "U1002")
      (value "UPD301C")
      (footprint "eagle-import:VQFN40")
      (libsource (lib "eagle-import") (part "UPD301C"))
    )
    (comp (ref "U1003")
      (value "MIC2019")
      (footprint "eagle-import:SOT23-6")
      (libsource (lib "eagle-import") (part "MIC2091"))
    )
    (comp (ref "USB1001")
      (value "USB-C-16P-SMD-FLAT-SIDE-TYPE-2")
      (footprint "eagle-import:USB-C-16P-SMD-FLAT-SIDE-TYPE-2")
      (libsource (lib "eagle-import") (part "USB-C-16P-SMD-FLAT-SIDE-TYPE-2"))
    )
    (comp (ref "C301")
      (value "100nF")
      (footprint "eagle-import:CAP0402")
      (libsource (lib "eagle-import") (part "CAPACITOR-0402"))
    )
    (comp (ref "C302")
      (value "100nF")
      (footprint "eagle-import:CAP0402")
      (libsource (lib "eagle-import") (part "CAPACITOR-0402"))
    )
    (comp (ref "C303")
      (value "100nF")
      (footprint "eagle-import:CAP0402")
      (libsource (lib "eagle-import") (part "CAPACITOR-0402"))
    )
    (comp (ref "C304")
      (value "100nF")
      (footprint "eagle-import:CAP0402")
      (libsource (lib "eagle-import") (part "CAPACITOR-0402"))
    )
    (comp (ref "C305")
      (value "100nF")
      (footprint "eagle-import:CAP0402")
      (libsource (lib "eagle-import") (part "CAPACITOR-0402"))
    )
    (comp (ref "C306")
      (value "100nF")
      (footprint "eagle-import:CAP0402")
      (libsource (lib "eagle-import") (part "CAPACITOR-0402"))
    )
    (comp (ref "C307")
      (value "100nF")
      (footprint "eagle-import:CAP0402")
      (libsource (lib "eagle-import") (part "CAPACITOR-0402"))
    )
    (comp (ref "C308")
      (value "100nF")
      (footprint "eagle-import:CAP0402")
      (libsource (lib "eagle-import") (part "CAPACITOR-0402"))
    )
    (comp (ref "C309")
      (value "100nF")
      (footprint "eagle-import:CAP0402")
      (libsource (lib "eagle-import") (part "CAPACITOR-0402"))
    )
    (comp (ref "C310")
      (value "100nF")
      (footprint "eagle-import:CAP0402")
      (libsource (lib "eagle-import") (part "CAPACITOR-0402"))
    )
    (comp (ref "C311")
      (value "100nF")
      (footprint "eagle-import:CAP0402")
      (libsource (lib "eagle-import") (part "CAPACITOR-0402"))
    )
    (comp (ref "C312")
      (value "100nF")
      (footprint "eagle-import:CAP0402")
      (libsource (lib "eagle-import") (part "CAPACITOR-0402"))
    )
    (comp (ref "C313")
      (value "100nF")
      (footprint "eagle-import:CAP0402")
      (libsource (lib "eagle-import") (part "CAPACITOR-0402"))
    )
    (comp (ref "C314")
      (value "100nF")
      (footprint "eagle-import:CAP0402")
      (libsource (lib "eagle-import") (part "CAPACITOR-0402"))
    )
    (comp (ref "C315")
      (value "100nF")
      (footprint "eagle-import:CAP0402")
      (libsource (lib "eagle-import") (part "CAPACITOR-0402"))
    )
    (comp (ref "C316")
      (value "100nF")
      (footprint "eagle-import:CAP0402")
      (libsource (lib "eagle-import") (part "CAPACITOR-0402"))
    )
    (comp (ref "C317")
      (value "100nF")
      (footprint "eagle-import:CAP0402")
      (libsource (lib "eagle-import") (part "CAPACITOR-0402"))
    )
    (comp (ref "C318")
      (value "100nF")
      (footprint "eagle-import:CAP0402")
      (libsource (lib "eagle-import") (part "CAPACITOR-0402"))
    )
    (comp (ref "C319")
      (value "100nF")
      (footprint "eagle-import:CAP0402")
      (libsource (lib "eagle-import") (part "CAPACITOR-0402"))
    )
    (comp (ref "C320")
      (value "100nF")
      (footprint "eagle-import:CAP0402")
      (libsource (lib "eagle-import") (part "CAPACITOR-0402"))
    )
    (comp (ref "C321")
      (value "100nF")
      (footprint "eagle-import:CAP0402")
      (libsource (lib "eagle-import") (part "CAPACITOR-0402"))
    )
    (comp (ref "C322")
      (value "47uF")
      (footprint "eagle-import:CAP0603")
      (libsource (lib "eagle-import") (part "CAPACITOR-0603"))
    )
    (comp (ref "C323")
      (value "100nF")
      (footprint "eagle-import:CAP0402")
      (libsource (lib "eagle-import") (part "CAPACITOR-0402"))
    )
    (comp (ref "C324")
      (value "100nF")
      (footprint "eagle-import:CAP0402")
      (libsource (lib "eagle-import") (part "CAPACITOR-0402"))
    )
    (comp (ref "C325")
      (value "100nF")
      (footprint "eagle-import:CAP0402")
      (libsource (lib "eagle-import") (part "CAPACITOR-0402"))
    )
    (comp (ref "C326")
      (value "100nF")
      (footprint "eagle-import:CAP0402")
      (libsource (lib "eagle-import") (part "CAPACITOR-0402"))
    )
    (comp (ref "C327")
      (value "100nF")
      (footprint "eagle-import:CAP0402")
      (libsource (lib "eagle-import") (part "CAPACITOR-0402"))
    )
    (comp (ref "C328")
      (value "4.7uF")
      (footprint "eagle-import:CAP0402")
      (libsource (lib "eagle-import") (part "CAPACITOR-0402"))
    )
    (comp (ref "C329")
      (value "4.7uF")
      (footprint "eagle-import:CAP0402")
      (libsource (lib "eagle-import") (part "CAPACITOR-0402"))
    )
    (comp (ref "C330")
      (value "47uF")
      (footprint "eagle-import:CAP0603")
      (libsource (lib "eagle-import") (part "CAPACITOR-0603"))
    )
    (comp (ref "C331")
      (value "47uF")
      (footprint "eagle-import:CAP0603")
      (libsource (lib "eagle-import") (part "CAPACITOR-0603"))
    )
    (comp (ref "R301")
      (value "240 Ohms")
      (footprint "eagle-import:RES0402")
      (libsource (lib "eagle-import") (part "RESISTOR-0402"))
    )
    (comp (ref "R302")
      (value "1K Ohms")
      (footprint "eagle-import:RES0402")
      (libsource (lib "eagle-import") (part "RESISTOR-0402"))
    )
    (comp (ref "R303")
      (value "40.2 Ohms")
      (footprint "eagle-import:RES0402")
      (libsource (lib "eagle-import") (part "RESISTOR-0402"))
    )
    (comp (ref "R304")
      (value "40.2 Ohms")
      (footprint "eagle-import:RES0402")
      (libsource (lib "eagle-import") (part "RESISTOR-0402"))
    )
    (comp (ref "R305")
      (value "40.2 Ohms")
      (footprint "eagle-import:RES0402")
      (libsource (lib "eagle-import") (part "RESISTOR-0402"))
    )
    (comp (ref "R306")
      (value "40.2 Ohms")
      (footprint "eagle-import:RES0402")
      (libsource (lib "eagle-import") (part "RESISTOR-0402"))
    )
    (comp (ref "R307")
      (value "40.2 Ohms")
      (footprint "eagle-import:RES0402")
      (libsource (lib "eagle-import") (part "RESISTOR-0402"))
    )
    (comp (ref "R308")
      (value "40.2 Ohms")
      (footprint "eagle-import:RES0402")
      (libsource (lib "eagle-import") (part "RESISTOR-0402"))
    )
    (comp (ref "R309")
      (value "40.2 Ohms")
      (footprint "eagle-import:RES0402")
      (libsource (lib "eagle-import") (part "RESISTOR-0402"))
    )
    (comp (ref "R310")
      (value "40.2 Ohms")
      (footprint "eagle-import:RES0402")
      (libsource (lib "eagle-import") (part "RESISTOR-0402"))
    )
    (comp (ref "R311")
      (value "40.2 Ohms")
      (footprint "eagle-import:RES0402")
      (libsource (lib "eagle-import") (part "RESISTOR-0402"))
    )
    (comp (ref "R312")
      (value "40.2 Ohms")
      (footprint "eagle-import:RES0402")
      (libsource (lib "eagle-import") (part "RESISTOR-0402"))
    )
    (comp (ref "R313")
      (value "40.2 Ohms")
      (footprint "eagle-import:RES0402")
      (libsource (lib "eagle-import") (part "RESISTOR-0402"))
    )
    (comp (ref "R314")
      (value "40.2 Ohms")
      (footprint "eagle-import:RES0402")
      (libsource (lib "eagle-import") (part "RESISTOR-0402"))
    )
    (comp (ref "R315")
      (value "40.2 Ohms")
      (footprint "eagle-import:RES0402")
      (libsource (lib "eagle-import") (part "RESISTOR-0402"))
    )
    (comp (ref "R316")
      (value "40.2 Ohms")
      (footprint "eagle-import:RES0402")
      (libsource (lib "eagle-import") (part "RESISTOR-0402"))
    )
    (comp (ref "R317")
      (value "40.2 Ohms")
      (footprint "eagle-import:RES0402")
      (libsource (lib "eagle-import") (part "RESISTOR-0402"))
    )
    (comp (ref "R318")
      (value "40.2 Ohms")
      (footprint "eagle-import:RES0402")
      (libsource (lib "eagle-import") (part "RESISTOR-0402"))
    )
    (comp (ref "R319")
      (value "40.2 Ohms")
      (footprint "eagle-import:RES0402")
      (libsource (lib "eagle-import") (part "RESISTOR-0402"))
    )
    (comp (ref "R320")
      (value "40.2 Ohms")
      (footprint "eagle-import:RES0402")
      (libsource (lib "eagle-import") (part "RESISTOR-0402"))
    )
    (comp (ref "R321")
      (value "40.2 Ohms")
      (footprint "eagle-import:RES0402")
      (libsource (lib "eagle-import") (part "RESISTOR-0402"))
    )
    (comp (ref "R322")
      (value "40.2 Ohms")
      (footprint "eagle-import:RES0402")
      (libsource (lib "eagle-import") (part "RESISTOR-0402"))
    )
    (comp (ref "R323")
      (value "40.2 Ohms")
      (footprint "eagle-import:RES0402")
      (libsource (lib "eagle-import") (part "RESISTOR-0402"))
    )
    (comp (ref "R324")
      (value "DNP")
      (footprint "eagle-import:RES0402")
      (libsource (lib "eagle-import") (part "RESISTOR-0402"))
    )
    (comp (ref "R325")
      (value "40.2 Ohms")
      (footprint "eagle-import:RES0402")
      (libsource (lib "eagle-import") (part "RESISTOR-0402"))
    )
    (comp (ref "R326")
      (value "40.2 Ohms")
      (footprint "eagle-import:RES0402")
      (libsource (lib "eagle-import") (part "RESISTOR-0402"))
    )
    (comp (ref "R327")
      (value "40.2 Ohms")
      (footprint "eagle-import:RES0402")
      (libsource (lib "eagle-import") (part "RESISTOR-0402"))
    )
    (comp (ref "R328")
      (value "40.2 Ohms")
      (footprint "eagle-import:RES0402")
      (libsource (lib "eagle-import") (part "RESISTOR-0402"))
    )
    (comp (ref "U201")
      (value "XC7A100TFGG484")
      (footprint "eagle-import:FGG484")
      (libsource (lib "eagle-import") (part "XC7A100TFGG484"))
    )
    (comp (ref "U301")
      (value "MT41K256M16TW-125")
      (footprint "eagle-import:FBGA96_14X8")
      (libsource (lib "eagle-import") (part "MT41K256M16?TW-125"))
    )
    (comp (ref "C1101")
      (value "100nF")
      (footprint "eagle-import:CAP0402")
      (libsource (lib "eagle-import") (part "CAPACITOR-0402"))
    )
    (comp (ref "C1102")
      (value "100nF")
      (footprint "eagle-import:CAP0402")
      (libsource (lib "eagle-import") (part "CAPACITOR-0402"))
    )
    (comp (ref "C1103")
      (value "10uF")
      (footprint "eagle-import:CAP1206")
      (fields (field (name "VOLTAGE") "50V"))
      (libsource (lib "eagle-import") (part "CAPACITOR-1206"))
    )
    (comp (ref "C1104")
      (value "1uF")
      (footprint "eagle-import:CAP0603")
      (fields (field (name "VOLTAGE") "50V"))
      (libsource (lib "eagle-import") (part "CAPACITOR-0603"))
    )
    (comp (ref "C1105")
      (value "10uF")
      (footprint "eagle-import:CAP1206")
      (fields (field (name "VOLTAGE") "50V"))
      (libsource (lib "eagle-import") (part "CAPACITOR-1206"))
    )
    (comp (ref "C1106")
      (value "100nF")
      (footprint "eagle-import:CAP0402")
      (libsource (lib "eagle-import") (part "CAPACITOR-0402"))
    )
    (comp (ref "C1107")
      (value "100nF")
      (footprint "eagle-import:CAP0402")
      (libsource (lib "eagle-import") (part "CAPACITOR-0402"))
    )
    (comp (ref "C1108")
      (value "4.7uF")
      (footprint "eagle-import:CAP0402")
      (libsource (lib "eagle-import") (part "CAPACITOR-0402"))
    )
    (comp (ref "C1109")
      (value "100nF")
      (footprint "eagle-import:CAP0402")
      (libsource (lib "eagle-import") (part "CAPACITOR-0402"))
    )
    (comp (ref "C1110")
      (value "10uF")
      (footprint "eagle-import:CAP1206")
      (fields (field (name "VOLTAGE") "50V"))
      (libsource (lib "eagle-import") (part "CAPACITOR-1206"))
    )
    (comp (ref "C1111")
      (value "10uF")
      (footprint "eagle-import:CAP1206")
      (fields (field (name "VOLTAGE") "50V"))
      (libsource (lib "eagle-import") (part "CAPACITOR-1206"))
    )
    (comp (ref "C1112")
      (value "10uF")
      (footprint "eagle-import:CAP1206")
      (fields (field (name "VOLTAGE") "50V"))
      (libsource (lib "eagle-import") (part "CAPACITOR-1206"))
    )
    (comp (ref "C1113")
      (value "100nF")
      (footprint "eagle-import:CAP0402")
      (libsource (lib "eagle-import") (part "CAPACITOR-0402"))
    )
    (comp (ref "C1114")
      (value "10uF")
      (footprint "eagle-import:CAP0402")
      (libsource (lib "eagle-import") (part "CAPACITOR-0402"))
    )
    (comp (ref "C1115")
      (value "4.7uF")
      (footprint "eagle-import:CAP0402")
      (libsource (lib "eagle-import") (part "CAPACITOR-0402"))
    )
    (comp (ref "C1116")
      (value "4.7uF")
      (footprint "eagle-import:CAP0603")
      (fields (field (name "VOLTAGE") "35V"))
      (libsource (lib "eagle-import") (part "CAPACITOR-0603"))
    )
    (comp (ref "C1117")
      (value "4.7uF")
      (footprint "eagle-import:CAP0603")
      (fields (field (name "VOLTAGE") "35V"))
      (libsource (lib "eagle-import") (part "CAPACITOR-0603"))
    )
    (comp (ref "C1118")
      (value "4.7uF")
      (footprint "eagle-import:CAP0603")
      (fields (field (name "VOLTAGE") "35V"))
      (libsource (lib "eagle-import") (part "CAPACITOR-0603"))
    )
    (comp (ref "C1119")
      (value "4.7uF")
      (footprint "eagle-import:CAP0603")
      (fields (field (name "VOLTAGE") "35V"))
      (libsource (lib "eagle-import") (part "CAPACITOR-0603"))
    )
    (comp (ref "C1120")
      (value "100nF")
      (footprint "eagle-import:CAP0402")
      (libsource (lib "eagle-import") (part "CAPACITOR-0402"))
    )
    (comp (ref "C1121")
      (value "100nF")
      (footprint "eagle-import:CAP0402")
      (libsource (lib "eagle-import") (part "CAPACITOR-0402"))
    )
    (comp (ref "C1122")
      (value "100uF")
      (footprint "eagle-import:CAP1206")
      (libsource (lib "eagle-import") (part "CAPACITOR-1206"))
    )
    (comp (ref "C1123")
      (value "100uF")
      (footprint "eagle-import:CAP1206")
      (libsource (lib "eagle-import") (part "CAPACITOR-1206"))
    )
    (comp (ref "C1124")
      (value "100uF")
      (footprint "eagle-import:CAP1206")
      (libsource (lib "eagle-import") (part "CAPACITOR-1206"))
    )
    (comp (ref "C1125")
      (value "100uF")
      (footprint "eagle-import:CAP1206")
      (libsource (lib "eagle-import") (part "CAPACITOR-1206"))
    )
    (comp (ref "C1126")
      (value "10uF")
      (footprint "eagle-import:CAP0402")
      (libsource (lib "eagle-import") (part "CAPACITOR-0402"))
    )
    (comp (ref "C1127")
      (value "4.7uF")
      (footprint "eagle-import:CAP0603")
      (libsource (lib "eagle-import") (part "CAPACITOR-0603"))
    )
    (comp (ref "C1128")
      (value "4.7uF")
      (footprint "eagle-import:CAP0402")
      (libsource (lib "eagle-import") (part "CAPACITOR-0402"))
    )
    (comp (ref "C1129")
      (value "100nF")
      (footprint "eagle-import:CAP0402")
      (libsource (lib "eagle-import") (part "CAPACITOR-0402"))
    )
    (comp (ref "C1130")
      (value "100nF")
      (footprint "eagle-import:CAP0402")
      (libsource (lib "eagle-import") (part "CAPACITOR-0402"))
    )
    (comp (ref "CON1101")
      (value "2EDG-2P-5MM-H")
      (footprint "eagle-import:2EDG-2P-5MM-H")
      (libsource (lib "eagle-import") (part "2EDG-2P-5MM-H"))
    )
    (comp (ref "D1101")
      (value "B0530W")
      (footprint "eagle-import:SOD-123")
      (libsource (lib "eagle-import") (part "B0530W"))
    )
    (comp (ref "D1102")
      (value "B0530W")
      (footprint "eagle-import:SOD-123")
      (libsource (lib "eagle-import") (part "B0530W"))
    )
    (comp (ref "D1103")
      (value "B0530W")
      (footprint "eagle-import:SOD-123")
      (libsource (lib "eagle-import") (part "B0530W"))
    )
    (comp (ref "D1104")
      (value "LED0603")
      (footprint "eagle-import:0603")
      (fields (field (name "COLOR") "GREEN"))
      (libsource (lib "eagle-import") (part "LED0603"))
    )
    (comp (ref "D1105")
      (value "SMAJ20A")
      (footprint "eagle-import:DO214AC")
      (fields (field (name "MF") "Littelfuse"))
      (libsource (lib "eagle-import") (part "SMAJA20"))
    )
    (comp (ref "F1101")
      (value "2.6A Hold")
      (footprint "eagle-import:1206")
      (fields (field (name "HOLD") "3A") (field (name "TRIP") "6A"))
      (libsource (lib "eagle-import") (part "PTC1206"))
    )
    (comp (ref "JP1101")
      (value "PINHD-2X3/SMD")
      (footprint "eagle-import:2X03_SMD")
      (fields (field (name "OCLCSC") "C5160777"))
      (libsource (lib "eagle-import") (part "PINHD-2X3/SMD"))
    )
    (comp (ref "L1101")
      (value "4.7uH")
      (footprint "eagle-import:XGL6030")
      (fields (field (name "CURRENT") "7.2A") (field (name "REF") "XGL6030-472"))
      (libsource (lib "eagle-import") (part "XGL6030-472"))
    )
    (comp (ref "L1102")
      (value "2.2uH")
      (footprint "eagle-import:XGL6030")
      (fields (field (name "CURRENT") "8.5A") (field (name "REF") "XGL6030-222"))
      (libsource (lib "eagle-import") (part "XGL6030-222"))
    )
    (comp (ref "Q1101")
      (value "AO3400")
      (footprint "eagle-import:SOT23")
      (libsource (lib "eagle-import") (part "AO3400"))
    )
    (comp (ref "Q1102")
      (value "AO4805")
      (footprint "eagle-import:SOIC8")
      (libsource (lib "eagle-import") (part "AO4805"))
    )
    (comp (ref "Q1103")
      (value "AO3400")
      (footprint "eagle-import:SOT23")
      (libsource (lib "eagle-import") (part "AO3400"))
    )
    (comp (ref "Q1104")
      (value "AO4805")
      (footprint "eagle-import:SOIC8")
      (libsource (lib "eagle-import") (part "AO4805"))
    )
    (comp (ref "Q1105")
      (value "AO4805")
      (footprint "eagle-import:SOIC8")
      (libsource (lib "eagle-import") (part "AO4805"))
    )
    (comp (ref "Q1106")
      (value "AO3400")
      (footprint "eagle-import:SOT23")
      (libsource (lib "eagle-import") (part "AO3400"))
    )
    (comp (ref "R1101")
      (value "100K Ohms")
      (footprint "eagle-import:RES0402")
      (libsource (lib "eagle-import") (part "RESISTOR-0402"))
    )
    (comp (ref "R1102")
      (value "5.1K Ohms")
      (footprint "eagle-import:RES0402")
      (libsource (lib "eagle-import") (part "RESISTOR-0402"))
    )
    (comp (ref "R1103")
      (value "100K Ohms")
      (footprint "eagle-import:RES0402")
      (libsource (lib "eagle-import") (part "RESISTOR-0402"))
    )
    (comp (ref "R1104")
      (value "5.1K Ohms")
      (footprint "eagle-import:RES0402")
      (libsource (lib "eagle-import") (part "RESISTOR-0402"))
    )
    (comp (ref "R1105")
      (value "10K Ohms")
      (footprint "eagle-import:RES0402")
      (libsource (lib "eagle-import") (part "RESISTOR-0402"))
    )
    (comp (ref "R1106")
      (value "1K Ohms")
      (footprint "eagle-import:RES0402")
      (libsource (lib "eagle-import") (part "RESISTOR-0402"))
    )
    (comp (ref "R1107")
      (value "1K Ohms")
      (footprint "eagle-import:RES0402")
      (libsource (lib "eagle-import") (part "RESISTOR-0402"))
    )
    (comp (ref "R1108")
      (value "100K Ohms")
      (footprint "eagle-import:RES0402")
      (libsource (lib "eagle-import") (part "RESISTOR-0402"))
    )
    (comp (ref "R1109")
      (value "5.1K Ohms")
      (footprint "eagle-import:RES0402")
      (libsource (lib "eagle-import") (part "RESISTOR-0402"))
    )
    (comp (ref "R1110")
      (value "100K Ohms")
      (footprint "eagle-import:RES0402")
      (libsource (lib "eagle-import") (part "RESISTOR-0402"))
    )
    (comp (ref "R1111")
      (value "5.1K Ohms")
      (footprint "eagle-import:RES0402")
      (libsource (lib "eagle-import") (part "RESISTOR-0402"))
    )
    (comp (ref "R1112")
      (value "10K Ohms")
      (footprint "eagle-import:RES0402")
      (libsource (lib "eagle-import") (part "RESISTOR-0402"))
    )
    (comp (ref "R1113")
      (value "1K Ohms")
      (footprint "eagle-import:RES0402")
      (libsource (lib "eagle-import") (part "RESISTOR-0402"))
    )
    (comp (ref "R1114")
      (value "1K Ohms")
      (footprint "eagle-import:RES0402")
      (libsource (lib "eagle-import") (part "RESISTOR-0402"))
    )
    (comp (ref "R1115")
      (value "10K Ohms")
      (footprint "eagle-import:RES0402")
      (libsource (lib "eagle-import") (part "RESISTOR-0402"))
    )
    (comp (ref "R1116")
      (value "1K Ohms")
      (footprint "eagle-import:RES0402")
      (libsource (lib "eagle-import") (part "RESISTOR-0402"))
    )
    (comp (ref "R1117")
      (value "1K Ohms")
      (footprint "eagle-import:RES0402")
      (libsource (lib "eagle-import") (part "RESISTOR-0402"))
    )
    (comp (ref "R1118")
      (value "10K Ohms")
      (footprint "eagle-import:RES0402")
      (libsource (lib "eagle-import") (part "RESISTOR-0402"))
    )
    (comp (ref "R1119")
      (value "1K Ohms")
      (footprint "eagle-import:RES0402")
      (libsource (lib "eagle-import") (part "RESISTOR-0402"))
    )
    (comp (ref "R1120")
      (value "DNP")
      (footprint "eagle-import:RES0402")
      (libsource (lib "eagle-import") (part "RESISTOR-0402"))
    )
    (comp (ref "R1121")
      (value "10K Ohms")
      (footprint "eagle-import:RES0402")
      (libsource (lib "eagle-import") (part "RESISTOR-0402"))
    )
    (comp (ref "R1122")
      (value "10K Ohms")
      (footprint "eagle-import:RES0402")
      (libsource (lib "eagle-import") (part "RESISTOR-0402"))
    )
    (comp (ref "R1123")
      (value "DNP")
      (footprint "eagle-import:RES0402")
      (libsource (lib "eagle-import") (part "RESISTOR-0402"))
    )
    (comp (ref "R1124")
      (value "10K Ohms")
      (footprint "eagle-import:RES0402")
      (libsource (lib "eagle-import") (part "RESISTOR-0402"))
    )
    (comp (ref "R1125")
      (value "36.5K Ohms")
      (footprint "eagle-import:RES0402")
      (libsource (lib "eagle-import") (part "RESISTOR-0402"))
    )
    (comp (ref "R1126")
      (value "124K Ohms")
      (footprint "eagle-import:RES0402")
      (libsource (lib "eagle-import") (part "RESISTOR-0402"))
    )
    (comp (ref "R1127")
      (value "51.1K Ohms")
      (footprint "eagle-import:RES0402")
      (libsource (lib "eagle-import") (part "RESISTOR-0402"))
    )
    (comp (ref "R1128")
      (value "0 Ohms")
      (footprint "eagle-import:RES0402")
      (libsource (lib "eagle-import") (part "RESISTOR-0402"))
    )
    (comp (ref "TP1")
      (value "TESTPOINT-0.7MM")
      (footprint "eagle-import:PAD0.7MM")
      (libsource (lib "eagle-import") (part "TESTPOINT-0.7MM"))
    )
    (comp (ref "TP2")
      (value "TESTPOINT-0.7MM")
      (footprint "eagle-import:PAD0.7MM")
      (libsource (lib "eagle-import") (part "TESTPOINT-0.7MM"))
    )
    (comp (ref "TP3")
      (value "TESTPOINT-0.7MM")
      (footprint "eagle-import:PAD0.7MM")
      (libsource (lib "eagle-import") (part "TESTPOINT-0.7MM"))
    )
    (comp (ref "TP4")
      (value "TESTPOINT-0.7MM")
      (footprint "eagle-import:PAD0.7MM")
      (libsource (lib "eagle-import") (part "TESTPOINT-0.7MM"))
    )
    (comp (ref "TP5")
      (value "TESTPOINT-0.7MM")
      (footprint "eagle-import:PAD0.7MM")
      (libsource (lib "eagle-import") (part "TESTPOINT-0.7MM"))
    )
    (comp (ref "TP6")
      (value "TESTPOINT-0.7MM")
      (footprint "eagle-import:PAD0.7MM")
      (libsource (lib "eagle-import") (part "TESTPOINT-0.7MM"))
    )
    (comp (ref "TP7")
      (value "TESTPOINT-0.7MM")
      (footprint "eagle-import:PAD0.7MM")
      (libsource (lib "eagle-import") (part "TESTPOINT-0.7MM"))
    )
    (comp (ref "U1101")
      (value "MCP1804-3302")
      (footprint "eagle-import:SOT23-5")
      (libsource (lib "eagle-import") (part "MCP1804-3302"))
    )
    (comp (ref "U1102")
      (value "LT7182S")
      (footprint "eagle-import:LQFN40_ASYM_CORNER")
      (libsource (lib "eagle-import") (part "LT7182S"))
    )
    (comp (ref "C701")
      (value "10uF")
      (footprint "eagle-import:CAP0402")
      (libsource (lib "eagle-import") (part "CAPACITOR-0402"))
    )
    (comp (ref "C702")
      (value "100nF")
      (footprint "eagle-import:CAP0402")
      (libsource (lib "eagle-import") (part "CAPACITOR-0402"))
    )
    (comp (ref "C703")
      (value "100nF")
      (footprint "eagle-import:CAP0402")
      (libsource (lib "eagle-import") (part "CAPACITOR-0402"))
    )
    (comp (ref "C704")
      (value "100nF")
      (footprint "eagle-import:CAP0402")
      (libsource (lib "eagle-import") (part "CAPACITOR-0402"))
    )
    (comp (ref "C705")
      (value "100nF")
      (footprint "eagle-import:CAP0402")
      (libsource (lib "eagle-import") (part "CAPACITOR-0402"))
    )
    (comp (ref "C706")
      (value "10uF")
      (footprint "eagle-import:CAP0402")
      (libsource (lib "eagle-import") (part "CAPACITOR-0402"))
    )
    (comp (ref "C707")
      (value "100nF")
      (footprint "eagle-import:CAP0402")
      (libsource (lib "eagle-import") (part "CAPACITOR-0402"))
    )
    (comp (ref "C708")
      (value "1uF")
      (footprint "eagle-import:CAP0402")
      (libsource (lib "eagle-import") (part "CAPACITOR-0402"))
    )
    (comp (ref "C709")
      (value "10uF")
      (footprint "eagle-import:CAP0402")
      (libsource (lib "eagle-import") (part "CAPACITOR-0402"))
    )
    (comp (ref "C710")
      (value "100nF")
      (footprint "eagle-import:CAP0402")
      (libsource (lib "eagle-import") (part "CAPACITOR-0402"))
    )
    (comp (ref "C711")
      (value "100nF")
      (footprint "eagle-import:CAP0402")
      (libsource (lib "eagle-import") (part "CAPACITOR-0402"))
    )
    (comp (ref "C712")
      (value "100uF")
      (footprint "eagle-import:CAP0805")
      (libsource (lib "eagle-import") (part "CAPACITOR-0805"))
    )
    (comp (ref "C713")
      (value "100uF")
      (footprint "eagle-import:CAP0805")
      (libsource (lib "eagle-import") (part "CAPACITOR-0805"))
    )
    (comp (ref "C714")
      (value "100uF")
      (footprint "eagle-import:CAP0805")
      (libsource (lib "eagle-import") (part "CAPACITOR-0805"))
    )
    (comp (ref "C715")
      (value "100uF")
      (footprint "eagle-import:CAP0805")
      (libsource (lib "eagle-import") (part "CAPACITOR-0805"))
    )
    (comp (ref "C716")
      (value "100nF")
      (footprint "eagle-import:CAP0402")
      (libsource (lib "eagle-import") (part "CAPACITOR-0402"))
    )
    (comp (ref "C717")
      (value "47uF")
      (footprint "eagle-import:CAP0603")
      (libsource (lib "eagle-import") (part "CAPACITOR-0603"))
    )
    (comp (ref "C718")
      (value "47uF")
      (footprint "eagle-import:CAP0603")
      (libsource (lib "eagle-import") (part "CAPACITOR-0603"))
    )
    (comp (ref "C719")
      (value "47uF")
      (footprint "eagle-import:CAP0603")
      (libsource (lib "eagle-import") (part "CAPACITOR-0603"))
    )
    (comp (ref "C720")
      (value "47uF")
      (footprint "eagle-import:CAP0603")
      (libsource (lib "eagle-import") (part "CAPACITOR-0603"))
    )
    (comp (ref "C721")
      (value "DNP")
      (footprint "eagle-import:CAP0402")
      (libsource (lib "eagle-import") (part "CAPACITOR-0402"))
    )
    (comp (ref "C722")
      (value "DNP")
      (footprint "eagle-import:CAP0402")
      (libsource (lib "eagle-import") (part "CAPACITOR-0402"))
    )
    (comp (ref "C723")
      (value "2.2uF")
      (footprint "eagle-import:CAP0402")
      (libsource (lib "eagle-import") (part "CAPACITOR-0402"))
    )
    (comp (ref "C724")
      (value "2.2uF")
      (footprint "eagle-import:CAP0402")
      (libsource (lib "eagle-import") (part "CAPACITOR-0402"))
    )
    (comp (ref "CON701")
      (value "4P-SH-TOP")
      (footprint "eagle-import:SH-04-TOP")
      (libsource (lib "eagle-import") (part "4P-SH-TOP"))
    )
    (comp (ref "FB701")
      (value "1uH")
      (footprint "eagle-import:IND0603")
      (libsource (lib "eagle-import") (part "FERRITE-0603"))
    )
    (comp (ref "J701")
      (value "TRSJACK")
      (footprint "eagle-import:3.5TRSJACK")
      (libsource (lib "eagle-import") (part "TRSJACK"))
    )
    (comp (ref "J702")
      (value "TRSJACK")
      (footprint "eagle-import:3.5TRSJACK")
      (libsource (lib "eagle-import") (part "TRSJACK"))
    )
    (comp (ref "J703")
      (value "TRSJACK")
      (footprint "eagle-import:3.5TRSJACK")
      (libsource (lib "eagle-import") (part "TRSJACK"))
    )
    (comp (ref "L701")
      (value "0 Ohms")
      (footprint "eagle-import:IND0603")
      (libsource (lib "eagle-import") (part "INDUCTOR-0603"))
    )
    (comp (ref "L702")
      (value "0 Ohms")
      (footprint "eagle-import:IND0603")
      (libsource (lib "eagle-import") (part "INDUCTOR-0603"))
    )
    (comp (ref "M701")
      (value "SPH0641LM4H-1")
      (footprint "eagle-import:SPH0641LM4H-1")
      (libsource (lib "eagle-import") (part "SPH0641LM4H-1"))
    )
    (comp (ref "M702")
      (value "SPH0641LM4H-1")
      (footprint "eagle-import:SPH0641LM4H-1")
      (libsource (lib "eagle-import") (part "SPH0641LM4H-1"))
    )
    (comp (ref "R701")
      (value "10K Ohms")
      (footprint "eagle-import:RES0402")
      (libsource (lib "eagle-import") (part "RESISTOR-0402"))
    )
    (comp (ref "R702")
      (value "49.9K Ohms")
      (footprint "eagle-import:RES0402")
      (libsource (lib "eagle-import") (part "RESISTOR-0402"))
    )
    (comp (ref "R703")
      (value "49.9K Ohms")
      (footprint "eagle-import:RES0402")
      (libsource (lib "eagle-import") (part "RESISTOR-0402"))
    )
    (comp (ref "R704")
      (value "2.21K Ohms")
      (footprint "eagle-import:RES0402")
      (libsource (lib "eagle-import") (part "RESISTOR-0402"))
    )
    (comp (ref "R705")
      (value "49.9K Ohms")
      (footprint "eagle-import:RES0402")
      (libsource (lib "eagle-import") (part "RESISTOR-0402"))
    )
    (comp (ref "R706")
      (value "2.21K Ohms")
      (footprint "eagle-import:RES0402")
      (libsource (lib "eagle-import") (part "RESISTOR-0402"))
    )
    (comp (ref "R707")
      (value "49.9K Ohms")
      (footprint "eagle-import:RES0402")
      (libsource (lib "eagle-import") (part "RESISTOR-0402"))
    )
    (comp (ref "R708")
      (value "2.21K Ohms")
      (footprint "eagle-import:RES0402")
      (libsource (lib "eagle-import") (part "RESISTOR-0402"))
    )
    (comp (ref "R709")
      (value "49.9K Ohms")
      (footprint "eagle-import:RES0402")
      (libsource (lib "eagle-import") (part "RESISTOR-0402"))
    )
    (comp (ref "R710")
      (value "2.21K Ohms")
      (footprint "eagle-import:RES0402")
      (libsource (lib "eagle-import") (part "RESISTOR-0402"))
    )
    (comp (ref "R711")
      (value "49.9K Ohms")
      (footprint "eagle-import:RES0402")
      (libsource (lib "eagle-import") (part "RESISTOR-0402"))
    )
    (comp (ref "U701")
      (value "ADAU1372")
      (footprint "eagle-import:QFN40")
      (libsource (lib "eagle-import") (part "ADAU1372"))
    )
    (comp (ref "C201")
      (value "470nF")
      (footprint "eagle-import:CAP0402")
      (libsource (lib "eagle-import") (part "CAPACITOR-0402"))
    )
    (comp (ref "C202")
      (value "4.7uF")
      (footprint "eagle-import:CAP0402")
      (libsource (lib "eagle-import") (part "CAPACITOR-0402"))
    )
    (comp (ref "C203")
      (value "470nF")
      (footprint "eagle-import:CAP0402")
      (libsource (lib "eagle-import") (part "CAPACITOR-0402"))
    )
    (comp (ref "C204")
      (value "470nF")
      (footprint "eagle-import:CAP0402")
      (libsource (lib "eagle-import") (part "CAPACITOR-0402"))
    )
    (comp (ref "C205")
      (value "470nF")
      (footprint "eagle-import:CAP0402")
      (libsource (lib "eagle-import") (part "CAPACITOR-0402"))
    )
    (comp (ref "C206")
      (value "470nF")
      (footprint "eagle-import:CAP0402")
      (libsource (lib "eagle-import") (part "CAPACITOR-0402"))
    )
    (comp (ref "C207")
      (value "470nF")
      (footprint "eagle-import:CAP0402")
      (libsource (lib "eagle-import") (part "CAPACITOR-0402"))
    )
    (comp (ref "C208")
      (value "470nF")
      (footprint "eagle-import:CAP0402")
      (libsource (lib "eagle-import") (part "CAPACITOR-0402"))
    )
    (comp (ref "C209")
      (value "470nF")
      (footprint "eagle-import:CAP0402")
      (libsource (lib "eagle-import") (part "CAPACITOR-0402"))
    )
    (comp (ref "C210")
      (value "470nF")
      (footprint "eagle-import:CAP0402")
      (libsource (lib "eagle-import") (part "CAPACITOR-0402"))
    )
    (comp (ref "C211")
      (value "470nF")
      (footprint "eagle-import:CAP0402")
      (libsource (lib "eagle-import") (part "CAPACITOR-0402"))
    )
    (comp (ref "C212")
      (value "470nF")
      (footprint "eagle-import:CAP0402")
      (libsource (lib "eagle-import") (part "CAPACITOR-0402"))
    )
    (comp (ref "C213")
      (value "470nF")
      (footprint "eagle-import:CAP0402")
      (libsource (lib "eagle-import") (part "CAPACITOR-0402"))
    )
    (comp (ref "C214")
      (value "470nF")
      (footprint "eagle-import:CAP0402")
      (libsource (lib "eagle-import") (part "CAPACITOR-0402"))
    )
    (comp (ref "C215")
      (value "470nF")
      (footprint "eagle-import:CAP0402")
      (libsource (lib "eagle-import") (part "CAPACITOR-0402"))
    )
    (comp (ref "C216")
      (value "470nF")
      (footprint "eagle-import:CAP0402")
      (libsource (lib "eagle-import") (part "CAPACITOR-0402"))
    )
    (comp (ref "C217")
      (value "470nF")
      (footprint "eagle-import:CAP0402")
      (libsource (lib "eagle-import") (part "CAPACITOR-0402"))
    )
    (comp (ref "C218")
      (value "470nF")
      (footprint "eagle-import:CAP0402")
      (libsource (lib "eagle-import") (part "CAPACITOR-0402"))
    )
    (comp (ref "C219")
      (value "470nF")
      (footprint "eagle-import:CAP0402")
      (libsource (lib "eagle-import") (part "CAPACITOR-0402"))
    )
    (comp (ref "C220")
      (value "470nF")
      (footprint "eagle-import:CAP0402")
      (libsource (lib "eagle-import") (part "CAPACITOR-0402"))
    )
    (comp (ref "C221")
      (value "470nF")
      (footprint "eagle-import:CAP0402")
      (libsource (lib "eagle-import") (part "CAPACITOR-0402"))
    )
    (comp (ref "C222")
      (value "4.7uF")
      (footprint "eagle-import:CAP0402")
      (libsource (lib "eagle-import") (part "CAPACITOR-0402"))
    )
    (comp (ref "C223")
      (value "4.7uF")
      (footprint "eagle-import:CAP0402")
      (libsource (lib "eagle-import") (part "CAPACITOR-0402"))
    )
    (comp (ref "C224")
      (value "4.7uF")
      (footprint "eagle-import:CAP0402")
      (libsource (lib "eagle-import") (part "CAPACITOR-0402"))
    )
    (comp (ref "C225")
      (value "4.7uF")
      (footprint "eagle-import:CAP0402")
      (libsource (lib "eagle-import") (part "CAPACITOR-0402"))
    )
    (comp (ref "C226")
      (value "470nF")
      (footprint "eagle-import:CAP0402")
      (libsource (lib "eagle-import") (part "CAPACITOR-0402"))
    )
    (comp (ref "C227")
      (value "4.7uF")
      (footprint "eagle-import:CAP0402")
      (libsource (lib "eagle-import") (part "CAPACITOR-0402"))
    )
    (comp (ref "C228")
      (value "4.7uF")
      (footprint "eagle-import:CAP0402")
      (libsource (lib "eagle-import") (part "CAPACITOR-0402"))
    )
    (comp (ref "C229")
      (value "4.7uF")
      (footprint "eagle-import:CAP0402")
      (libsource (lib "eagle-import") (part "CAPACITOR-0402"))
    )
    (comp (ref "C230")
      (value "4.7uF")
      (footprint "eagle-import:CAP0402")
      (libsource (lib "eagle-import") (part "CAPACITOR-0402"))
    )
    (comp (ref "C231")
      (value "4.7uF")
      (footprint "eagle-import:CAP0402")
      (libsource (lib "eagle-import") (part "CAPACITOR-0402"))
    )
    (comp (ref "C232")
      (value "47uF")
      (footprint "eagle-import:CAP0603")
      (libsource (lib "eagle-import") (part "CAPACITOR-0603"))
    )
    (comp (ref "C233")
      (value "470nF")
      (footprint "eagle-import:CAP0402")
      (libsource (lib "eagle-import") (part "CAPACITOR-0402"))
    )
    (comp (ref "C234")
      (value "470nF")
      (footprint "eagle-import:CAP0402")
      (libsource (lib "eagle-import") (part "CAPACITOR-0402"))
    )
    (comp (ref "C235")
      (value "470nF")
      (footprint "eagle-import:CAP0402")
      (libsource (lib "eagle-import") (part "CAPACITOR-0402"))
    )
    (comp (ref "C236")
      (value "4.7uF")
      (footprint "eagle-import:CAP0402")
      (libsource (lib "eagle-import") (part "CAPACITOR-0402"))
    )
    (comp (ref "C237")
      (value "4.7uF")
      (footprint "eagle-import:CAP0402")
      (libsource (lib "eagle-import") (part "CAPACITOR-0402"))
    )
    (comp (ref "C238")
      (value "470nF")
      (footprint "eagle-import:CAP0402")
      (libsource (lib "eagle-import") (part "CAPACITOR-0402"))
    )
    (comp (ref "C239")
      (value "470nF")
      (footprint "eagle-import:CAP0402")
      (libsource (lib "eagle-import") (part "CAPACITOR-0402"))
    )
    (comp (ref "C240")
      (value "470nF")
      (footprint "eagle-import:CAP0402")
      (libsource (lib "eagle-import") (part "CAPACITOR-0402"))
    )
    (comp (ref "C241")
      (value "4.7uF")
      (footprint "eagle-import:CAP0402")
      (libsource (lib "eagle-import") (part "CAPACITOR-0402"))
    )
    (comp (ref "C242")
      (value "100nF")
      (footprint "eagle-import:CAP0402")
      (libsource (lib "eagle-import") (part "CAPACITOR-0402"))
    )
    (comp (ref "C243")
      (value "470nF")
      (footprint "eagle-import:CAP0402")
      (libsource (lib "eagle-import") (part "CAPACITOR-0402"))
    )
    (comp (ref "C244")
      (value "470nF")
      (footprint "eagle-import:CAP0402")
      (libsource (lib "eagle-import") (part "CAPACITOR-0402"))
    )
    (comp (ref "C245")
      (value "470nF")
      (footprint "eagle-import:CAP0402")
      (libsource (lib "eagle-import") (part "CAPACITOR-0402"))
    )
    (comp (ref "C246")
      (value "4.7uF")
      (footprint "eagle-import:CAP0402")
      (libsource (lib "eagle-import") (part "CAPACITOR-0402"))
    )
    (comp (ref "C247")
      (value "100nF")
      (footprint "eagle-import:CAP0402")
      (libsource (lib "eagle-import") (part "CAPACITOR-0402"))
    )
    (comp (ref "C248")
      (value "470nF")
      (footprint "eagle-import:CAP0402")
      (libsource (lib "eagle-import") (part "CAPACITOR-0402"))
    )
    (comp (ref "C249")
      (value "470nF")
      (footprint "eagle-import:CAP0402")
      (libsource (lib "eagle-import") (part "CAPACITOR-0402"))
    )
    (comp (ref "C250")
      (value "470nF")
      (footprint "eagle-import:CAP0402")
      (libsource (lib "eagle-import") (part "CAPACITOR-0402"))
    )
    (comp (ref "C251")
      (value "47uF")
      (footprint "eagle-import:CAP0603")
      (libsource (lib "eagle-import") (part "CAPACITOR-0603"))
    )
    (comp (ref "C252")
      (value "4.7uF")
      (footprint "eagle-import:CAP0402")
      (libsource (lib "eagle-import") (part "CAPACITOR-0402"))
    )
    (comp (ref "C253")
      (value "4.7uF")
      (footprint "eagle-import:CAP0402")
      (libsource (lib "eagle-import") (part "CAPACITOR-0402"))
    )
    (comp (ref "C254")
      (value "4.7uF")
      (footprint "eagle-import:CAP0402")
      (libsource (lib "eagle-import") (part "CAPACITOR-0402"))
    )
    (comp (ref "C255")
      (value "4.7uF")
      (footprint "eagle-import:CAP0402")
      (libsource (lib "eagle-import") (part "CAPACITOR-0402"))
    )
    (comp (ref "C256")
      (value "47uF")
      (footprint "eagle-import:CAP0603")
      (libsource (lib "eagle-import") (part "CAPACITOR-0603"))
    )
    (comp (ref "C257")
      (value "47uF")
      (footprint "eagle-import:CAP0603")
      (libsource (lib "eagle-import") (part "CAPACITOR-0603"))
    )
    (comp (ref "C258")
      (value "4.7uF")
      (footprint "eagle-import:CAP0402")
      (libsource (lib "eagle-import") (part "CAPACITOR-0402"))
    )
    (comp (ref "C259")
      (value "4.7uF")
      (footprint "eagle-import:CAP0402")
      (libsource (lib "eagle-import") (part "CAPACITOR-0402"))
    )
    (comp (ref "C260")
      (value "4.7uF")
      (footprint "eagle-import:CAP0402")
      (libsource (lib "eagle-import") (part "CAPACITOR-0402"))
    )
    (comp (ref "C261")
      (value "100nF")
      (footprint "eagle-import:CAP0402")
      (libsource (lib "eagle-import") (part "CAPACITOR-0402"))
    )
    (comp (ref "C262")
      (value "100nF")
      (footprint "eagle-import:CAP0402")
      (libsource (lib "eagle-import") (part "CAPACITOR-0402"))
    )
    (comp (ref "C263")
      (value "4.7uF")
      (footprint "eagle-import:CAP0402")
      (libsource (lib "eagle-import") (part "CAPACITOR-0402"))
    )
    (comp (ref "C264")
      (value "100nF")
      (footprint "eagle-import:CAP0402")
      (libsource (lib "eagle-import") (part "CAPACITOR-0402"))
    )
    (comp (ref "D201")
      (value "LED0603")
      (footprint "eagle-import:0603")
      (fields (field (name "COLOR") "GREEN"))
      (libsource (lib "eagle-import") (part "LED0603"))
    )
    (comp (ref "D202")
      (value "LED0603")
      (footprint "eagle-import:0603")
      (fields (field (name "COLOR") "BLUE"))
      (libsource (lib "eagle-import") (part "LED0603"))
    )
    (comp (ref "JP201")
      (value "PINHD-2X3/SMD")
      (footprint "eagle-import:2X03_SMD")
      (fields (field (name "OCLCSC") "C5160777"))
      (libsource (lib "eagle-import") (part "PINHD-2X3/SMD"))
    )
    (comp (ref "JP202")
      (value "PINHD-2X3/SMD")
      (footprint "eagle-import:2X03_SMD")
      (fields (field (name "OCLCSC") "C5160777"))
      (libsource (lib "eagle-import") (part "PINHD-2X3/SMD"))
    )
    (comp (ref "R201")
      (value "4.7K Ohms")
      (footprint "eagle-import:RES0402")
      (libsource (lib "eagle-import") (part "RESISTOR-0402"))
    )
    (comp (ref "R202")
      (value "4.7K Ohms")
      (footprint "eagle-import:RES0402")
      (libsource (lib "eagle-import") (part "RESISTOR-0402"))
    )
    (comp (ref "R203")
      (value "22 Ohms")
      (footprint "eagle-import:RES0402")
      (libsource (lib "eagle-import") (part "RESISTOR-0402"))
    )
    (comp (ref "R204")
      (value "22 Ohms")
      (footprint "eagle-import:RES0402")
      (libsource (lib "eagle-import") (part "RESISTOR-0402"))
    )
    (comp (ref "R205")
      (value "4.7K Ohms")
      (footprint "eagle-import:RES0402")
      (libsource (lib "eagle-import") (part "RESISTOR-0402"))
    )
    (comp (ref "R206")
      (value "22 Ohms")
      (footprint "eagle-import:RES0402")
      (libsource (lib "eagle-import") (part "RESISTOR-0402"))
    )
    (comp (ref "R207")
      (value "4.7K Ohms")
      (footprint "eagle-import:RES0402")
      (libsource (lib "eagle-import") (part "RESISTOR-0402"))
    )
    (comp (ref "R208")
      (value "22 Ohms")
      (footprint "eagle-import:RES0402")
      (libsource (lib "eagle-import") (part "RESISTOR-0402"))
    )
    (comp (ref "R209")
      (value "22 Ohms")
      (footprint "eagle-import:RES0402")
      (libsource (lib "eagle-import") (part "RESISTOR-0402"))
    )
    (comp (ref "R210")
      (value "100 Ohms")
      (footprint "eagle-import:RES0402")
      (fields (field (name "TOLERANCE") "1%"))
      (libsource (lib "eagle-import") (part "RESISTOR-0402"))
    )
    (comp (ref "R211")
      (value "22 Ohms")
      (footprint "eagle-import:RES0402")
      (libsource (lib "eagle-import") (part "RESISTOR-0402"))
    )
    (comp (ref "R212")
      (value "22 Ohms")
      (footprint "eagle-import:RES0402")
      (libsource (lib "eagle-import") (part "RESISTOR-0402"))
    )
    (comp (ref "R213")
      (value "22 Ohms")
      (footprint "eagle-import:RES0402")
      (libsource (lib "eagle-import") (part "RESISTOR-0402"))
    )
    (comp (ref "R214")
      (value "4.7K Ohms")
      (footprint "eagle-import:RES0402")
      (libsource (lib "eagle-import") (part "RESISTOR-0402"))
    )
    (comp (ref "R215")
      (value "2.4K Ohms")
      (footprint "eagle-import:RES0402")
      (libsource (lib "eagle-import") (part "RESISTOR-0402"))
    )
    (comp (ref "R216")
      (value "4.7K Ohms")
      (footprint "eagle-import:RES0402")
      (libsource (lib "eagle-import") (part "RESISTOR-0402"))
    )
    (comp (ref "R217")
      (value "4.7K Ohms")
      (footprint "eagle-import:RES0402")
      (libsource (lib "eagle-import") (part "RESISTOR-0402"))
    )
    (comp (ref "R218")
      (value "4.7K Ohms")
      (footprint "eagle-import:RES0402")
      (libsource (lib "eagle-import") (part "RESISTOR-0402"))
    )
    (comp (ref "R219")
      (value "1K Ohms")
      (footprint "eagle-import:RES0402")
      (libsource (lib "eagle-import") (part "RESISTOR-0402"))
    )
    (comp (ref "R220")
      (value "10K Ohms")
      (footprint "eagle-import:RES0402")
      (libsource (lib "eagle-import") (part "RESISTOR-0402"))
    )
    (comp (ref "R221")
      (value "10K Ohms")
      (footprint "eagle-import:RES0402")
      (libsource (lib "eagle-import") (part "RESISTOR-0402"))
    )
    (comp (ref "R222")
      (value "1K Ohms")
      (footprint "eagle-import:RES0402")
      (libsource (lib "eagle-import") (part "RESISTOR-0402"))
    )
    (comp (ref "TC201")
      (value "TC2050-IDC")
      (footprint "eagle-import:TC2050-IDC")
      (libsource (lib "eagle-import") (part "TC2050-IDC"))
    )
    (comp (ref "U202")
      (value "SST26VF064B")
      (footprint "eagle-import:WSOIC8")
      (libsource (lib "eagle-import") (part "SST26VF064B"))
    )
    (comp (ref "C601")
      (value "100nF")
      (footprint "eagle-import:CAP0402")
      (libsource (lib "eagle-import") (part "CAPACITOR-0402"))
    )
    (comp (ref "C602")
      (value "100nF")
      (footprint "eagle-import:CAP0402")
      (libsource (lib "eagle-import") (part "CAPACITOR-0402"))
    )
    (comp (ref "C603")
      (value "100nF")
      (footprint "eagle-import:CAP0402")
      (libsource (lib "eagle-import") (part "CAPACITOR-0402"))
    )
    (comp (ref "C604")
      (value "100nF")
      (footprint "eagle-import:CAP0402")
      (libsource (lib "eagle-import") (part "CAPACITOR-0402"))
    )
    (comp (ref "C605")
      (value "100nF")
      (footprint "eagle-import:CAP0402")
      (libsource (lib "eagle-import") (part "CAPACITOR-0402"))
    )
    (comp (ref "C606")
      (value "22uF")
      (footprint "eagle-import:CAP0402")
      (libsource (lib "eagle-import") (part "CAPACITOR-0402"))
    )
    (comp (ref "C607")
      (value "100nF")
      (footprint "eagle-import:CAP0402")
      (libsource (lib "eagle-import") (part "CAPACITOR-0402"))
    )
    (comp (ref "C608")
      (value "100nF")
      (footprint "eagle-import:CAP0402")
      (libsource (lib "eagle-import") (part "CAPACITOR-0402"))
    )
    (comp (ref "C609")
      (value "22uF")
      (footprint "eagle-import:CAP0402")
      (libsource (lib "eagle-import") (part "CAPACITOR-0402"))
    )
    (comp (ref "C610")
      (value "100nF")
      (footprint "eagle-import:CAP0402")
      (libsource (lib "eagle-import") (part "CAPACITOR-0402"))
    )
    (comp (ref "C611")
      (value "100nF")
      (footprint "eagle-import:CAP0402")
      (libsource (lib "eagle-import") (part "CAPACITOR-0402"))
    )
    (comp (ref "C612")
      (value "22uF")
      (footprint "eagle-import:CAP0402")
      (libsource (lib "eagle-import") (part "CAPACITOR-0402"))
    )
    (comp (ref "C613")
      (value "22uF")
      (footprint "eagle-import:CAP0402")
      (libsource (lib "eagle-import") (part "CAPACITOR-0402"))
    )
    (comp (ref "C614")
      (value "22uF")
      (footprint "eagle-import:CAP0402")
      (libsource (lib "eagle-import") (part "CAPACITOR-0402"))
    )
    (comp (ref "C615")
      (value "1uF")
      (footprint "eagle-import:CAP0402")
      (libsource (lib "eagle-import") (part "CAPACITOR-0402"))
    )
    (comp (ref "C616")
      (value "1uF")
      (footprint "eagle-import:CAP0402")
      (libsource (lib "eagle-import") (part "CAPACITOR-0402"))
    )
    (comp (ref "C617")
      (value "10nF")
      (footprint "eagle-import:CAP0402")
      (libsource (lib "eagle-import") (part "CAPACITOR-0402"))
    )
    (comp (ref "C618")
      (value "2.2nF")
      (footprint "eagle-import:CAP0402")
      (libsource (lib "eagle-import") (part "CAPACITOR-0402"))
    )
    (comp (ref "C619")
      (value "10nF")
      (footprint "eagle-import:CAP0402")
      (libsource (lib "eagle-import") (part "CAPACITOR-0402"))
    )
    (comp (ref "C620")
      (value "10nF")
      (footprint "eagle-import:CAP0402")
      (libsource (lib "eagle-import") (part "CAPACITOR-0402"))
    )
    (comp (ref "C621")
      (value "10pF")
      (footprint "eagle-import:CAP0402")
      (libsource (lib "eagle-import") (part "CAPACITOR-0402"))
    )
    (comp (ref "C622")
      (value "10pF")
      (footprint "eagle-import:CAP0402")
      (libsource (lib "eagle-import") (part "CAPACITOR-0402"))
    )
    (comp (ref "C623")
      (value "10nF")
      (footprint "eagle-import:CAP0402")
      (libsource (lib "eagle-import") (part "CAPACITOR-0402"))
    )
    (comp (ref "C624")
      (value "10nF")
      (footprint "eagle-import:CAP0402")
      (libsource (lib "eagle-import") (part "CAPACITOR-0402"))
    )
    (comp (ref "C625")
      (value "10nF")
      (footprint "eagle-import:CAP0402")
      (libsource (lib "eagle-import") (part "CAPACITOR-0402"))
    )
    (comp (ref "C626")
      (value "10nF")
      (footprint "eagle-import:CAP0402")
      (libsource (lib "eagle-import") (part "CAPACITOR-0402"))
    )
    (comp (ref "D601")
      (value "PGB1010402")
      (footprint "eagle-import:TVS0402")
      (libsource (lib "eagle-import") (part "PGB1010402"))
    )
    (comp (ref "D602")
      (value "PGB1010402")
      (footprint "eagle-import:TVS0402")
      (libsource (lib "eagle-import") (part "PGB1010402"))
    )
    (comp (ref "FB601")
      (value "1uH")
      (footprint "eagle-import:IND0603")
      (libsource (lib "eagle-import") (part "FERRITE-0603"))
    )
    (comp (ref "L601")
      (value "18nH")
      (footprint "eagle-import:IND0402")
      (libsource (lib "eagle-import") (part "INDUCTOR-0402"))
    )
    (comp (ref "L602")
      (value "18nH")
      (footprint "eagle-import:IND0402")
      (libsource (lib "eagle-import") (part "INDUCTOR-0402"))
    )
    (comp (ref "R601")
      (value "DNP")
      (footprint "eagle-import:RES0402")
      (libsource (lib "eagle-import") (part "RESISTOR-0402"))
    )
    (comp (ref "R602")
      (value "49.9 Ohms")
      (footprint "eagle-import:RES0402")
      (libsource (lib "eagle-import") (part "RESISTOR-0402"))
    )
    (comp (ref "R603")
      (value "1K Ohms")
      (footprint "eagle-import:RES0402")
      (libsource (lib "eagle-import") (part "RESISTOR-0402"))
    )
    (comp (ref "R604")
      (value "1K Ohms")
      (footprint "eagle-import:RES0402")
      (libsource (lib "eagle-import") (part "RESISTOR-0402"))
    )
    (comp (ref "R605")
      (value "1K Ohms")
      (footprint "eagle-import:RES0402")
      (libsource (lib "eagle-import") (part "RESISTOR-0402"))
    )
    (comp (ref "R606")
      (value "1K Ohms")
      (footprint "eagle-import:RES0402")
      (libsource (lib "eagle-import") (part "RESISTOR-0402"))
    )
    (comp (ref "R607")
      (value "1K Ohms")
      (footprint "eagle-import:RES0402")
      (libsource (lib "eagle-import") (part "RESISTOR-0402"))
    )
    (comp (ref "R608")
      (value "20 Ohms")
      (footprint "eagle-import:RES0402")
      (libsource (lib "eagle-import") (part "RESISTOR-0402"))
    )
    (comp (ref "R609")
      (value "62 Ohms")
      (footprint "eagle-import:RES0402")
      (libsource (lib "eagle-import") (part "RESISTOR-0402"))
    )
    (comp (ref "R610")
      (value "50 Ohms")
      (footprint "eagle-import:RES0402")
      (libsource (lib "eagle-import") (part "RESISTOR-0402"))
    )
    (comp (ref "R611")
      (value "50 Ohms")
      (footprint "eagle-import:RES0402")
      (libsource (lib "eagle-import") (part "RESISTOR-0402"))
    )
    (comp (ref "R612")
      (value "50 Ohms")
      (footprint "eagle-import:RES0402")
      (libsource (lib "eagle-import") (part "RESISTOR-0402"))
    )
    (comp (ref "R613")
      (value "50 Ohms")
      (footprint "eagle-import:RES0402")
      (libsource (lib "eagle-import") (part "RESISTOR-0402"))
    )
    (comp (ref "R614")
      (value "50 Ohms")
      (footprint "eagle-import:RES0402")
      (libsource (lib "eagle-import") (part "RESISTOR-0402"))
    )
    (comp (ref "R615")
      (value "50 Ohms")
      (footprint "eagle-import:RES0402")
      (libsource (lib "eagle-import") (part "RESISTOR-0402"))
    )
    (comp (ref "RFCON601")
      (value "RFCON-SMA")
      (footprint "eagle-import:SMA")
      (libsource (lib "eagle-import") (part "RFCON-SMA"))
    )
    (comp (ref "RFCON602")
      (value "RFCON-SMA")
      (footprint "eagle-import:SMA")
      (libsource (lib "eagle-import") (part "RFCON-SMA"))
    )
    (comp (ref "SHIELD601")
      (value "SHIELD-TE-2118728")
      (footprint "eagle-import:2118728")
      (libsource (lib "eagle-import") (part "SHIELD-TE-2118728"))
    )
    (comp (ref "U601")
      (value "8V97003")
      (footprint "eagle-import:VFQFPN48")
      (libsource (lib "eagle-import") (part "8V97003"))
    )
    (comp (ref "C401")
      (value "100nF")
      (footprint "eagle-import:CAP0402")
      (libsource (lib "eagle-import") (part "CAPACITOR-0402"))
    )
    (comp (ref "C402")
      (value "DNP")
      (footprint "eagle-import:CAP0402")
      (libsource (lib "eagle-import") (part "CAPACITOR-0402"))
    )
    (comp (ref "C403")
      (value "100nF")
      (footprint "eagle-import:CAP0402")
      (libsource (lib "eagle-import") (part "CAPACITOR-0402"))
    )
    (comp (ref "C404")
      (value "1uF")
      (footprint "eagle-import:CAP0402")
      (libsource (lib "eagle-import") (part "CAPACITOR-0402"))
    )
    (comp (ref "C405")
      (value "1uF")
      (footprint "eagle-import:CAP0402")
      (libsource (lib "eagle-import") (part "CAPACITOR-0402"))
    )
    (comp (ref "C406")
      (value "10uF")
      (footprint "eagle-import:CAP0402")
      (libsource (lib "eagle-import") (part "CAPACITOR-0402"))
    )
    (comp (ref "C407")
      (value "10nF")
      (footprint "eagle-import:CAP0402")
      (libsource (lib "eagle-import") (part "CAPACITOR-0402"))
    )
    (comp (ref "C408")
      (value "10nF")
      (footprint "eagle-import:CAP0402")
      (libsource (lib "eagle-import") (part "CAPACITOR-0402"))
    )
    (comp (ref "C409")
      (value "1uF")
      (footprint "eagle-import:CAP0402")
      (libsource (lib "eagle-import") (part "CAPACITOR-0402"))
    )
    (comp (ref "C410")
      (value "1uF")
      (footprint "eagle-import:CAP0402")
      (libsource (lib "eagle-import") (part "CAPACITOR-0402"))
    )
    (comp (ref "C411")
      (value "1uF")
      (footprint "eagle-import:CAP0402")
      (libsource (lib "eagle-import") (part "CAPACITOR-0402"))
    )
    (comp (ref "C412")
      (value "10nF")
      (footprint "eagle-import:CAP0402")
      (libsource (lib "eagle-import") (part "CAPACITOR-0402"))
    )
    (comp (ref "C413")
      (value "10nF")
      (footprint "eagle-import:CAP0402")
      (libsource (lib "eagle-import") (part "CAPACITOR-0402"))
    )
    (comp (ref "C414")
      (value "10nF")
      (footprint "eagle-import:CAP0402")
      (libsource (lib "eagle-import") (part "CAPACITOR-0402"))
    )
    (comp (ref "C415")
      (value "10nF")
      (footprint "eagle-import:CAP0402")
      (libsource (lib "eagle-import") (part "CAPACITOR-0402"))
    )
    (comp (ref "C416")
      (value "1uF")
      (footprint "eagle-import:CAP0402")
      (libsource (lib "eagle-import") (part "CAPACITOR-0402"))
    )
    (comp (ref "C417")
      (value "1uF")
      (footprint "eagle-import:CAP0402")
      (libsource (lib "eagle-import") (part "CAPACITOR-0402"))
    )
    (comp (ref "C418")
      (value "1uF")
      (footprint "eagle-import:CAP0402")
      (libsource (lib "eagle-import") (part "CAPACITOR-0402"))
    )
    (comp (ref "C419")
      (value "10nF")
      (footprint "eagle-import:CAP0402")
      (libsource (lib "eagle-import") (part "CAPACITOR-0402"))
    )
    (comp (ref "C420")
      (value "10nF")
      (footprint "eagle-import:CAP0402")
      (libsource (lib "eagle-import") (part "CAPACITOR-0402"))
    )
    (comp (ref "C421")
      (value "1uF")
      (footprint "eagle-import:CAP0402")
      (libsource (lib "eagle-import") (part "CAPACITOR-0402"))
    )
    (comp (ref "C422")
      (value "1nF")
      (footprint "eagle-import:CAP0402")
      (libsource (lib "eagle-import") (part "CAPACITOR-0402"))
    )
    (comp (ref "C423")
      (value "1uF")
      (footprint "eagle-import:CAP0402")
      (libsource (lib "eagle-import") (part "CAPACITOR-0402"))
    )
    (comp (ref "C424")
      (value "1nF")
      (footprint "eagle-import:CAP0402")
      (libsource (lib "eagle-import") (part "CAPACITOR-0402"))
    )
    (comp (ref "FB401")
      (value "1uH")
      (footprint "eagle-import:IND0603")
      (libsource (lib "eagle-import") (part "FERRITE-0603"))
    )
    (comp (ref "R401")
      (value "25.5 Ohms")
      (footprint "eagle-import:RES0402")
      (libsource (lib "eagle-import") (part "RESISTOR-0402"))
    )
    (comp (ref "R402")
      (value "25.5 Ohms")
      (footprint "eagle-import:RES0402")
      (libsource (lib "eagle-import") (part "RESISTOR-0402"))
    )
    (comp (ref "R403")
      (value "14.3K Ohms")
      (footprint "eagle-import:RES0402")
      (libsource (lib "eagle-import") (part "RESISTOR-0402"))
    )
    (comp (ref "R404")
      (value "1 Ohms")
      (footprint "eagle-import:RES0402")
      (libsource (lib "eagle-import") (part "RESISTOR-0402"))
    )
    (comp (ref "R405")
      (value "1 Ohms")
      (footprint "eagle-import:RES0402")
      (libsource (lib "eagle-import") (part "RESISTOR-0402"))
    )
    (comp (ref "SHIELD401")
      (value "SHIELD-TE-2118732")
      (footprint "eagle-import:2118732")
      (libsource (lib "eagle-import") (part "SHIELD-TE-2118732"))
    )
    (comp (ref "U401")
      (value "AD9361")
      (footprint "eagle-import:BGA144")
      (libsource (lib "eagle-import") (part "AD9361"))
    )
    (comp (ref "C801")
      (value "0 Ohms")
      (footprint "eagle-import:CAP0402")
      (libsource (lib "eagle-import") (part "CAPACITOR-0402"))
    )
    (comp (ref "C802")
      (value "0 Ohms")
      (footprint "eagle-import:CAP0402")
      (libsource (lib "eagle-import") (part "CAPACITOR-0402"))
    )
    (comp (ref "C803")
      (value "0 Ohms")
      (footprint "eagle-import:CAP0402")
      (libsource (lib "eagle-import") (part "CAPACITOR-0402"))
    )
    (comp (ref "C804")
      (value "0 Ohms")
      (footprint "eagle-import:CAP0402")
      (libsource (lib "eagle-import") (part "CAPACITOR-0402"))
    )
    (comp (ref "C805")
      (value "0 Ohms")
      (footprint "eagle-import:CAP0402")
      (libsource (lib "eagle-import") (part "CAPACITOR-0402"))
    )
    (comp (ref "C806")
      (value "0 Ohms")
      (footprint "eagle-import:CAP0402")
      (libsource (lib "eagle-import") (part "CAPACITOR-0402"))
    )
    (comp (ref "C807")
      (value "100nF")
      (footprint "eagle-import:CAP0402")
      (libsource (lib "eagle-import") (part "CAPACITOR-0402"))
    )
    (comp (ref "C808")
      (value "100nF")
      (footprint "eagle-import:CAP0402")
      (libsource (lib "eagle-import") (part "CAPACITOR-0402"))
    )
    (comp (ref "C809")
      (value "100nF")
      (footprint "eagle-import:CAP0402")
      (libsource (lib "eagle-import") (part "CAPACITOR-0402"))
    )
    (comp (ref "C810")
      (value "100nF")
      (footprint "eagle-import:CAP0402")
      (libsource (lib "eagle-import") (part "CAPACITOR-0402"))
    )
    (comp (ref "C811")
      (value "100nF")
      (footprint "eagle-import:CAP0402")
      (libsource (lib "eagle-import") (part "CAPACITOR-0402"))
    )
    (comp (ref "C812")
      (value "100nF")
      (footprint "eagle-import:CAP0402")
      (libsource (lib "eagle-import") (part "CAPACITOR-0402"))
    )
    (comp (ref "C813")
      (value "1uF")
      (footprint "eagle-import:CAP0402")
      (libsource (lib "eagle-import") (part "CAPACITOR-0402"))
    )
    (comp (ref "CON801")
      (value "PCIE-X4-EDGE")
      (footprint "eagle-import:PCIE-X4-EDGE")
      (libsource (lib "eagle-import") (part "PCIE-X4-EDGE"))
    )
    (comp (ref "R801")
      (value "10K Ohms")
      (footprint "eagle-import:RES0402")
      (libsource (lib "eagle-import") (part "RESISTOR-0402"))
    )
    (comp (ref "R802")
      (value "10K Ohms")
      (footprint "eagle-import:RES0402")
      (libsource (lib "eagle-import") (part "RESISTOR-0402"))
    )
    (comp (ref "R803")
      (value "10K Ohms")
      (footprint "eagle-import:RES0402")
      (libsource (lib "eagle-import") (part "RESISTOR-0402"))
    )
    (comp (ref "R804")
      (value "10K Ohms")
      (footprint "eagle-import:RES0402")
      (libsource (lib "eagle-import") (part "RESISTOR-0402"))
    )
    (comp (ref "R805")
      (value "10K Ohms")
      (footprint "eagle-import:RES0402")
      (libsource (lib "eagle-import") (part "RESISTOR-0402"))
    )
  )
  (nets
    (net (code "1") (name "0V675_DDR3_VREF") (class "Default")
      (node (ref "C1234") (pin "1") (pinfunction "C1_1") (pintype "passive"))
      (node (ref "C305") (pin "1") (pinfunction "C1_1") (pintype "passive"))
      (node (ref "C308") (pin "1") (pinfunction "C1_1") (pintype "passive"))
      (node (ref "C313") (pin "1") (pinfunction "C1_1") (pintype "passive"))
      (node (ref "C316") (pin "1") (pinfunction "C1_1") (pintype "passive"))
      (node (ref "C318") (pin "1") (pinfunction "C1_1") (pintype "passive"))
      (node (ref "C320") (pin "1") (pinfunction "C1_1") (pintype "passive"))
      (node (ref "U1205") (pin "1") (pinfunction "VREF_1") (pintype "bidirectional"))
      (node (ref "U201") (pin "E3") (pinfunction "IO_L6N/T0/VREF_E3") (pintype "bidirectional"))
      (node (ref "U201") (pin "N3") (pinfunction "IO_L19N/T3/VREF_N3") (pintype "bidirectional"))
      (node (ref "U201") (pin "V3") (pinfunction "IO_L6N/T0/VREF_V3") (pintype "bidirectional"))
      (node (ref "U201") (pin "W7") (pinfunction "IO_L19N/T3/VREF_W7") (pintype "bidirectional"))
      (node (ref "U301") (pin "H1") (pinfunction "VREFDQ_H1") (pintype "bidirectional"))
      (node (ref "U301") (pin "M8") (pinfunction "VREFCA_M8") (pintype "bidirectional"))
    )
    (net (code "2") (name "0V675_DDR3_VTT") (class "Default")
      (node (ref "C1235") (pin "1") (pinfunction "C1_1") (pintype "passive"))
      (node (ref "C1238") (pin "1") (pinfunction "C1_1") (pintype "passive"))
      (node (ref "C323") (pin "2") (pinfunction "C2_2") (pintype "passive"))
      (node (ref "C324") (pin "1") (pinfunction "C1_1") (pintype "passive"))
      (node (ref "C325") (pin "1") (pinfunction "C1_1") (pintype "passive"))
      (node (ref "C326") (pin "1") (pinfunction "C1_1") (pintype "passive"))
      (node (ref "C327") (pin "1") (pinfunction "C1_1") (pintype "passive"))
      (node (ref "C328") (pin "1") (pinfunction "C1_1") (pintype "passive"))
      (node (ref "C329") (pin "1") (pinfunction "C1_1") (pintype "passive"))
      (node (ref "C330") (pin "1") (pinfunction "C1_1") (pintype "passive"))
      (node (ref "C331") (pin "1") (pinfunction "C1_1") (pintype "passive"))
      (node (ref "R303") (pin "1") (pinfunction "1_1") (pintype "passive"))
      (node (ref "R304") (pin "1") (pinfunction "1_1") (pintype "passive"))
      (node (ref "R305") (pin "1") (pinfunction "1_1") (pintype "passive"))
      (node (ref "R306") (pin "1") (pinfunction "1_1") (pintype "passive"))
      (node (ref "R307") (pin "1") (pinfunction "1_1") (pintype "passive"))
      (node (ref "R308") (pin "1") (pinfunction "1_1") (pintype "passive"))
      (node (ref "R309") (pin "1") (pinfunction "1_1") (pintype "passive"))
      (node (ref "R310") (pin "1") (pinfunction "1_1") (pintype "passive"))
      (node (ref "R312") (pin "1") (pinfunction "1_1") (pintype "passive"))
      (node (ref "R313") (pin "1") (pinfunction "1_1") (pintype "passive"))
      (node (ref "R314") (pin "1") (pinfunction "1_1") (pintype "passive"))
      (node (ref "R315") (pin "1") (pinfunction "1_1") (pintype "passive"))
      (node (ref "R316") (pin "1") (pinfunction "1_1") (pintype "passive"))
      (node (ref "R317") (pin "1") (pinfunction "1_1") (pintype "passive"))
      (node (ref "R318") (pin "1") (pinfunction "1_1") (pintype "passive"))
      (node (ref "R320") (pin "2") (pinfunction "2_2") (pintype "passive"))
      (node (ref "R321") (pin "2") (pinfunction "2_2") (pintype "passive"))
      (node (ref "R322") (pin "2") (pinfunction "2_2") (pintype "passive"))
      (node (ref "R323") (pin "2") (pinfunction "2_2") (pintype "passive"))
      (node (ref "R324") (pin "2") (pinfunction "2_2") (pintype "passive"))
      (node (ref "R325") (pin "2") (pinfunction "2_2") (pintype "passive"))
      (node (ref "R326") (pin "2") (pinfunction "2_2") (pintype "passive"))
      (node (ref "R327") (pin "2") (pinfunction "2_2") (pintype "passive"))
      (node (ref "R328") (pin "2") (pinfunction "2_2") (pintype "passive"))
      (node (ref "U1205") (pin "6") (pinfunction "SNS_6") (pintype "bidirectional"))
      (node (ref "U1205") (pin "9") (pinfunction "VTT_9") (pintype "bidirectional"))
    )
    (net (code "3") (name "1V0") (class "Default")
      (node (ref "C1123") (pin "1") (pinfunction "C1_1") (pintype "passive"))
      (node (ref "C1125") (pin "1") (pinfunction "C1_1") (pintype "passive"))
      (node (ref "C1128") (pin "1") (pinfunction "C1_1") (pintype "passive"))
      (node (ref "C1130") (pin "1") (pinfunction "C1_1") (pintype "passive"))
      (node (ref "C201") (pin "1") (pinfunction "C1_1") (pintype "passive"))
      (node (ref "C202") (pin "1") (pinfunction "C1_1") (pintype "passive"))
      (node (ref "C206") (pin "1") (pinfunction "C1_1") (pintype "passive"))
      (node (ref "C211") (pin "1") (pinfunction "C1_1") (pintype "passive"))
      (node (ref "C216") (pin "1") (pinfunction "C1_1") (pintype "passive"))
      (node (ref "C221") (pin "1") (pinfunction "C1_1") (pintype "passive"))
      (node (ref "C226") (pin "1") (pinfunction "C1_1") (pintype "passive"))
      (node (ref "C231") (pin "1") (pinfunction "C1_1") (pintype "passive"))
      (node (ref "C236") (pin "1") (pinfunction "C1_1") (pintype "passive"))
      (node (ref "C241") (pin "1") (pinfunction "C1_1") (pintype "passive"))
      (node (ref "C246") (pin "1") (pinfunction "C1_1") (pintype "passive"))
      (node (ref "C251") (pin "1") (pinfunction "C1_1") (pintype "passive"))
      (node (ref "C256") (pin "1") (pinfunction "C1_1") (pintype "passive"))
      (node (ref "C261") (pin "1") (pinfunction "C1_1") (pintype "passive"))
      (node (ref "C262") (pin "1") (pinfunction "C1_1") (pintype "passive"))
      (node (ref "C263") (pin "1") (pinfunction "C1_1") (pintype "passive"))
      (node (ref "L1102") (pin "2") (pinfunction "2_2") (pintype "passive"))
      (node (ref "U1102") (pin "11") (pinfunction "VSENSEP_11") (pintype "bidirectional"))
      (node (ref "U201") (pin "D10") (pinfunction "MGTAVCC_D10") (pintype "bidirectional"))
      (node (ref "U201") (pin "D6") (pinfunction "MGTAVCC_D6") (pintype "bidirectional"))
      (node (ref "U201") (pin "E8") (pinfunction "MGTAVCC_E8") (pintype "bidirectional"))
      (node (ref "U201") (pin "F7") (pinfunction "MGTAVCC_F7") (pintype "bidirectional"))
      (node (ref "U201") (pin "F9") (pinfunction "MGTAVCC_F9") (pintype "bidirectional"))
      (node (ref "U201") (pin "H10") (pinfunction "VCCINT_H10") (pintype "bidirectional"))
      (node (ref "U201") (pin "H8") (pinfunction "VCCINT_H8") (pintype "bidirectional"))
      (node (ref "U201") (pin "J11") (pinfunction "VCCBRAM_J11") (pintype "bidirectional"))
      (node (ref "U201") (pin "J7") (pinfunction "VCCINT_J7") (pintype "bidirectional"))
      (node (ref "U201") (pin "J9") (pinfunction "VCCINT_J9") (pintype "bidirectional"))
      (node (ref "U201") (pin "K8") (pinfunction "VCCINT_K8") (pintype "bidirectional"))
      (node (ref "U201") (pin "L11") (pinfunction "VCCBRAM_L11") (pintype "bidirectional"))
      (node (ref "U201") (pin "L7") (pinfunction "VCCINT_L7") (pintype "bidirectional"))
      (node (ref "U201") (pin "M8") (pinfunction "VCCINT_M8") (pintype "bidirectional"))
      (node (ref "U201") (pin "N11") (pinfunction "VCCBRAM_N11") (pintype "bidirectional"))
      (node (ref "U201") (pin "N7") (pinfunction "VCCINT_N7") (pintype "bidirectional"))
      (node (ref "U201") (pin "P10") (pinfunction "VCCINT_P10") (pintype "bidirectional"))
      (node (ref "U201") (pin "P8") (pinfunction "VCCINT_P8") (pintype "bidirectional"))
      (node (ref "U201") (pin "R7") (pinfunction "VCCINT_R7") (pintype "bidirectional"))
      (node (ref "U201") (pin "R9") (pinfunction "VCCINT_R9") (pintype "bidirectional"))
      (node (ref "U201") (pin "T10") (pinfunction "VCCINT_T10") (pintype "bidirectional"))
      (node (ref "U201") (pin "T8") (pinfunction "VCCINT_T8") (pintype "bidirectional"))
    )
    (net (code "4") (name "1V0_PGOOD") (class "Default")
      (node (ref "R1122") (pin "1") (pinfunction "1_1") (pintype "passive"))
      (node (ref "TP2") (pin "TP") (pinfunction "TP_TP") (pintype "input"))
      (node (ref "U1102") (pin "32") (pinfunction "PGOOD_32") (pintype "bidirectional"))
      (node (ref "U1209") (pin "2") (pinfunction "EN_2") (pintype "bidirectional"))
    )
    (net (code "5") (name "1V2") (class "Default")
      (node (ref "C1257") (pin "1") (pinfunction "C1_1") (pintype "passive"))
      (node (ref "C1259") (pin "1") (pinfunction "C1_1") (pintype "passive"))
      (node (ref "C242") (pin "1") (pinfunction "C1_1") (pintype "passive"))
      (node (ref "C247") (pin "1") (pinfunction "C1_1") (pintype "passive"))
      (node (ref "C252") (pin "1") (pinfunction "C1_1") (pintype "passive"))
      (node (ref "C257") (pin "1") (pinfunction "C1_1") (pintype "passive"))
      (node (ref "L1205") (pin "2") (pinfunction "2_2") (pintype "passive"))
      (node (ref "R1214") (pin "2") (pinfunction "2_2") (pintype "passive"))
      (node (ref "R210") (pin "2") (pinfunction "2_2") (pintype "passive"))
      (node (ref "U1209") (pin "3") (pinfunction "SNS_3") (pintype "bidirectional"))
      (node (ref "U201") (pin "B11") (pinfunction "MGTAVTT_B11") (pintype "bidirectional"))
      (node (ref "U201") (pin "B5") (pinfunction "MGTAVTT_B5") (pintype "bidirectional"))
      (node (ref "U201") (pin "B7") (pinfunction "MGTAVTT_B7") (pintype "bidirectional"))
      (node (ref "U201") (pin "B9") (pinfunction "MGTAVTT_B9") (pintype "bidirectional"))
      (node (ref "U201") (pin "C4") (pinfunction "MGTAVTT_C4") (pintype "bidirectional"))
      (node (ref "U201") (pin "C8") (pinfunction "MGTAVTT_C8") (pintype "bidirectional"))
    )
    (net (code "6") (name "1V2_PGOOD") (class "Default")
      (node (ref "R1210") (pin "1") (pinfunction "1_1") (pintype "passive"))
      (node (ref "TP3") (pin "TP") (pinfunction "TP_TP") (pintype "input"))
      (node (ref "U1204") (pin "9") (pinfunction "EN_9") (pintype "bidirectional"))
      (node (ref "U1208") (pin "18") (pinfunction "EN_18") (pintype "bidirectional"))
      (node (ref "U1208") (pin "9") (pinfunction "EN_9") (pintype "bidirectional"))
      (node (ref "U1209") (pin "5") (pinfunction "PG_5") (pintype "bidirectional"))
    )
    (net (code "7") (name "1V3_TRX") (class "Default")
      (node (ref "C1236") (pin "1") (pinfunction "C1_1") (pintype "passive"))
      (node (ref "C1240") (pin "1") (pinfunction "C1_1") (pintype "passive"))
      (node (ref "C1243") (pin "1") (pinfunction "C1_1") (pintype "passive"))
      (node (ref "C1244") (pin "1") (pinfunction "C1_1") (pintype "passive"))
      (node (ref "C404") (pin "1") (pinfunction "C1_1") (pintype "passive"))
      (node (ref "C407") (pin "1") (pinfunction "C1_1") (pintype "passive"))
      (node (ref "C410") (pin "1") (pinfunction "C1_1") (pintype "passive"))
      (node (ref "C413") (pin "1") (pinfunction "C1_1") (pintype "passive"))
      (node (ref "C416") (pin "1") (pinfunction "C1_1") (pintype "passive"))
      (node (ref "C419") (pin "1") (pinfunction "C1_1") (pintype "passive"))
      (node (ref "C523") (pin "1") (pinfunction "C1_1") (pintype "passive"))
      (node (ref "C524") (pin "1") (pinfunction "C1_1") (pintype "passive"))
      (node (ref "C525") (pin "1") (pinfunction "C1_1") (pintype "passive"))
      (node (ref "C526") (pin "1") (pinfunction "C1_1") (pintype "passive"))
      (node (ref "C527") (pin "1") (pinfunction "C1_1") (pintype "passive"))
      (node (ref "C528") (pin "1") (pinfunction "C1_1") (pintype "passive"))
      (node (ref "C534") (pin "1") (pinfunction "C1_1") (pintype "passive"))
      (node (ref "C535") (pin "1") (pinfunction "C1_1") (pintype "passive"))
      (node (ref "C536") (pin "1") (pinfunction "C1_1") (pintype "passive"))
      (node (ref "C537") (pin "1") (pinfunction "C1_1") (pintype "passive"))
      (node (ref "C540") (pin "1") (pinfunction "C1_1") (pintype "passive"))
      (node (ref "C541") (pin "1") (pinfunction "C1_1") (pintype "passive"))
      (node (ref "L503") (pin "1") (pinfunction "1_1") (pintype "passive"))
      (node (ref "L504") (pin "1") (pinfunction "1_1") (pintype "passive"))
      (node (ref "L505") (pin "1") (pinfunction "1_1") (pintype "passive"))
      (node (ref "L506") (pin "1") (pinfunction "1_1") (pintype "passive"))
      (node (ref "L507") (pin "1") (pinfunction "1_1") (pintype "passive"))
      (node (ref "L508") (pin "1") (pinfunction "1_1") (pintype "passive"))
      (node (ref "L509") (pin "1") (pinfunction "1_1") (pintype "passive"))
      (node (ref "L510") (pin "1") (pinfunction "1_1") (pintype "passive"))
      (node (ref "U1206") (pin "1") (pinfunction "VOUT_1") (pintype "bidirectional"))
      (node (ref "U1206") (pin "2") (pinfunction "VOUT_2") (pintype "bidirectional"))
      (node (ref "U1206") (pin "3") (pinfunction "SENSE_3") (pintype "bidirectional"))
      (node (ref "U401") (pin "D2") (pinfunction "VDDA1P3_RX_RF_D2") (pintype "bidirectional"))
      (node (ref "U401") (pin "D3") (pinfunction "VDDA1P3_RX_TX_D3") (pintype "bidirectional"))
      (node (ref "U401") (pin "E3") (pinfunction "VDDA1P3_TX_LO_BUFFER_E3") (pintype "bidirectional"))
      (node (ref "U401") (pin "F12") (pinfunction "VDDD1P3_DIG_F12") (pintype "bidirectional"))
      (node (ref "U401") (pin "K4") (pinfunction "VDDA1P3_BB_K4") (pintype "bidirectional"))
    )
    (net (code "8") (name "1V3_TRX_LO_SYNTH") (class "Default")
      (node (ref "C1213") (pin "1") (pinfunction "C1_1") (pintype "passive"))
      (node (ref "C1216") (pin "1") (pinfunction "C1_1") (pintype "passive"))
      (node (ref "C1218") (pin "1") (pinfunction "C1_1") (pintype "passive"))
      (node (ref "C1219") (pin "1") (pinfunction "C1_1") (pintype "passive"))
      (node (ref "C405") (pin "1") (pinfunction "C1_1") (pintype "passive"))
      (node (ref "C408") (pin "1") (pinfunction "C1_1") (pintype "passive"))
      (node (ref "C411") (pin "1") (pinfunction "C1_1") (pintype "passive"))
      (node (ref "C414") (pin "1") (pinfunction "C1_1") (pintype "passive"))
      (node (ref "C417") (pin "1") (pinfunction "C1_1") (pintype "passive"))
      (node (ref "C420") (pin "1") (pinfunction "C1_1") (pintype "passive"))
      (node (ref "U1202") (pin "1") (pinfunction "VOUT_1") (pintype "bidirectional"))
      (node (ref "U1202") (pin "2") (pinfunction "VOUT_2") (pintype "bidirectional"))
      (node (ref "U1202") (pin "3") (pinfunction "SENSE_3") (pintype "bidirectional"))
      (node (ref "U401") (pin "B10") (pinfunction "VDDA1P3_TX_VCO_LDO_B10") (pintype "bidirectional"))
      (node (ref "U401") (pin "B9") (pinfunction "VDDA1P3_TX_LO_B9") (pintype "bidirectional"))
      (node (ref "U401") (pin "E2") (pinfunction "VDDA1P3_RX_LO_E2") (pintype "bidirectional"))
      (node (ref "U401") (pin "F2") (pinfunction "VDDA1P3_RX_VCO_LDO_F2") (pintype "bidirectional"))
      (node (ref "U401") (pin "J3") (pinfunction "VDDA1P3_RX_SYNTH_J3") (pintype "bidirectional"))
      (node (ref "U401") (pin "K3") (pinfunction "VDDA1P3_TX_SYNTH_K3") (pintype "bidirectional"))
    )
    (net (code "9") (name "1V8") (class "Default")
      (node (ref "C1226") (pin "1") (pinfunction "C1_1") (pintype "passive"))
      (node (ref "C1227") (pin "1") (pinfunction "C1_1") (pintype "passive"))
      (node (ref "C207") (pin "1") (pinfunction "C1_1") (pintype "passive"))
      (node (ref "C212") (pin "1") (pinfunction "C1_1") (pintype "passive"))
      (node (ref "C217") (pin "1") (pinfunction "C1_1") (pintype "passive"))
      (node (ref "C222") (pin "1") (pinfunction "C1_1") (pintype "passive"))
      (node (ref "C227") (pin "1") (pinfunction "C1_1") (pintype "passive"))
      (node (ref "C232") (pin "1") (pinfunction "C1_1") (pintype "passive"))
      (node (ref "L1202") (pin "2") (pinfunction "2_2") (pintype "passive"))
      (node (ref "R1204") (pin "2") (pinfunction "2_2") (pintype "passive"))
      (node (ref "R1205") (pin "2") (pinfunction "2_2") (pintype "passive"))
      (node (ref "U1204") (pin "10") (pinfunction "SNS_10") (pintype "bidirectional"))
      (node (ref "U201") (pin "E12") (pinfunction "VCCBATT_E12") (pintype "bidirectional"))
      (node (ref "U201") (pin "H12") (pinfunction "VCCAUX_H12") (pintype "bidirectional"))
      (node (ref "U201") (pin "K10") (pinfunction "VCCADC_K10") (pintype "bidirectional"))
      (node (ref "U201") (pin "K12") (pinfunction "VCCAUX_K12") (pintype "bidirectional"))
      (node (ref "U201") (pin "M12") (pinfunction "VCCAUX_M12") (pintype "bidirectional"))
      (node (ref "U201") (pin "P12") (pinfunction "VCCAUX_P12") (pintype "bidirectional"))
      (node (ref "U201") (pin "R11") (pinfunction "VCCAUX_R11") (pintype "bidirectional"))
    )
    (net (code "10") (name "1V8_CM4") (class "Default")
      (node (ref "U102") (pin "88") (pinfunction "1V8_OUT_88") (pintype "bidirectional"))
      (node (ref "U102") (pin "90") (pinfunction "1V8_OUT_90") (pintype "bidirectional"))
    )
    (net (code "11") (name "1V8_PGOOD") (class "Default")
      (node (ref "R1204") (pin "1") (pinfunction "1_1") (pintype "passive"))
      (node (ref "TP4") (pin "TP") (pinfunction "TP_TP") (pintype "input"))
      (node (ref "U1204") (pin "12") (pinfunction "PG_12") (pintype "bidirectional"))
      (node (ref "U1204") (pin "18") (pinfunction "EN_18") (pintype "bidirectional"))
    )
    (net (code "12") (name "1V35") (class "Default")
      (node (ref "C1209") (pin "1") (pinfunction "C1_1") (pintype "passive"))
      (node (ref "C1210") (pin "1") (pinfunction "C1_1") (pintype "passive"))
      (node (ref "C1220") (pin "1") (pinfunction "C1_1") (pintype "passive"))
      (node (ref "C1224") (pin "1") (pinfunction "C1_1") (pintype "passive"))
      (node (ref "C205") (pin "1") (pinfunction "C1_1") (pintype "passive"))
      (node (ref "C210") (pin "1") (pinfunction "C1_1") (pintype "passive"))
      (node (ref "C215") (pin "1") (pinfunction "C1_1") (pintype "passive"))
      (node (ref "C220") (pin "1") (pinfunction "C1_1") (pintype "passive"))
      (node (ref "C225") (pin "1") (pinfunction "C1_1") (pintype "passive"))
      (node (ref "C230") (pin "1") (pinfunction "C1_1") (pintype "passive"))
      (node (ref "C235") (pin "1") (pinfunction "C1_1") (pintype "passive"))
      (node (ref "C240") (pin "1") (pinfunction "C1_1") (pintype "passive"))
      (node (ref "C245") (pin "1") (pinfunction "C1_1") (pintype "passive"))
      (node (ref "C250") (pin "1") (pinfunction "C1_1") (pintype "passive"))
      (node (ref "C255") (pin "1") (pinfunction "C1_1") (pintype "passive"))
      (node (ref "C260") (pin "1") (pinfunction "C1_1") (pintype "passive"))
      (node (ref "C301") (pin "1") (pinfunction "C1_1") (pintype "passive"))
      (node (ref "C302") (pin "1") (pinfunction "C1_1") (pintype "passive"))
      (node (ref "C303") (pin "1") (pinfunction "C1_1") (pintype "passive"))
      (node (ref "C304") (pin "1") (pinfunction "C1_1") (pintype "passive"))
      (node (ref "C306") (pin "1") (pinfunction "C1_1") (pintype "passive"))
      (node (ref "C307") (pin "1") (pinfunction "C1_1") (pintype "passive"))
      (node (ref "C309") (pin "1") (pinfunction "C1_1") (pintype "passive"))
      (node (ref "C310") (pin "1") (pinfunction "C1_1") (pintype "passive"))
      (node (ref "C311") (pin "1") (pinfunction "C1_1") (pintype "passive"))
      (node (ref "C312") (pin "1") (pinfunction "C1_1") (pintype "passive"))
      (node (ref "C314") (pin "1") (pinfunction "C1_1") (pintype "passive"))
      (node (ref "C315") (pin "1") (pinfunction "C1_1") (pintype "passive"))
      (node (ref "C317") (pin "1") (pinfunction "C1_1") (pintype "passive"))
      (node (ref "C319") (pin "1") (pinfunction "C1_1") (pintype "passive"))
      (node (ref "C321") (pin "1") (pinfunction "C1_1") (pintype "passive"))
      (node (ref "C322") (pin "1") (pinfunction "C1_1") (pintype "passive"))
      (node (ref "L1201") (pin "1") (pinfunction "1_1") (pintype "passive"))
      (node (ref "R1201") (pin "2") (pinfunction "2_2") (pintype "passive"))
      (node (ref "R1202") (pin "2") (pinfunction "2_2") (pintype "passive"))
      (node (ref "U1204") (pin "17") (pinfunction "SNS_17") (pintype "bidirectional"))
      (node (ref "U1205") (pin "10") (pinfunction "VIN_10") (pintype "bidirectional"))
      (node (ref "U1205") (pin "4") (pinfunction "VDDQ_4") (pintype "bidirectional"))
      (node (ref "U201") (pin "AA7") (pinfunction "VCCO_34_AA7") (pintype "bidirectional"))
      (node (ref "U201") (pin "AB4") (pinfunction "VCCO_34_AB4") (pintype "bidirectional"))
      (node (ref "U201") (pin "C1") (pinfunction "VCCO_35_C1") (pintype "bidirectional"))
      (node (ref "U201") (pin "F2") (pinfunction "VCCO_35_F2") (pintype "bidirectional"))
      (node (ref "U201") (pin "H6") (pinfunction "VCCO_35_H6") (pintype "bidirectional"))
      (node (ref "U201") (pin "J3") (pinfunction "VCCO_35_J3") (pintype "bidirectional"))
      (node (ref "U201") (pin "M4") (pinfunction "VCCO_35_M4") (pintype "bidirectional"))
      (node (ref "U201") (pin "N1") (pinfunction "VCCO_35_N1") (pintype "bidirectional"))
      (node (ref "U201") (pin "R5") (pinfunction "VCCO_34_R5") (pintype "bidirectional"))
      (node (ref "U201") (pin "T2") (pinfunction "VCCO_34_T2") (pintype "bidirectional"))
      (node (ref "U201") (pin "V6") (pinfunction "VCCO_34_V6") (pintype "bidirectional"))
      (node (ref "U201") (pin "W3") (pinfunction "VCCO_34_W3") (pintype "bidirectional"))
      (node (ref "U301") (pin "A1") (pinfunction "VDDQ_A1") (pintype "bidirectional"))
      (node (ref "U301") (pin "A8") (pinfunction "VDDQ_A8") (pintype "bidirectional"))
      (node (ref "U301") (pin "B2") (pinfunction "VDD_B2") (pintype "bidirectional"))
      (node (ref "U301") (pin "C1") (pinfunction "VDDQ_C1") (pintype "bidirectional"))
      (node (ref "U301") (pin "C9") (pinfunction "VDDQ_C9") (pintype "bidirectional"))
      (node (ref "U301") (pin "D2") (pinfunction "VDDQ_D2") (pintype "bidirectional"))
      (node (ref "U301") (pin "D9") (pinfunction "VDD_D9") (pintype "bidirectional"))
      (node (ref "U301") (pin "E9") (pinfunction "VDDQ_E9") (pintype "bidirectional"))
      (node (ref "U301") (pin "F1") (pinfunction "VDDQ_F1") (pintype "bidirectional"))
      (node (ref "U301") (pin "G7") (pinfunction "VDD_G7") (pintype "bidirectional"))
      (node (ref "U301") (pin "H2") (pinfunction "VDDQ_H2") (pintype "bidirectional"))
      (node (ref "U301") (pin "H9") (pinfunction "VDDQ_H9") (pintype "bidirectional"))
      (node (ref "U301") (pin "K2") (pinfunction "VDD_K2") (pintype "bidirectional"))
      (node (ref "U301") (pin "K8") (pinfunction "VDD_K8") (pintype "bidirectional"))
      (node (ref "U301") (pin "N1") (pinfunction "VDD_N1") (pintype "bidirectional"))
      (node (ref "U301") (pin "N9") (pinfunction "VDD_N9") (pintype "bidirectional"))
      (node (ref "U301") (pin "R1") (pinfunction "VDD_R1") (pintype "bidirectional"))
      (node (ref "U301") (pin "R9") (pinfunction "VDD_R9") (pintype "bidirectional"))
    )
    (net (code "13") (name "1V35_PGOOD") (class "Default")
      (node (ref "R1201") (pin "1") (pinfunction "1_1") (pintype "passive"))
      (node (ref "TP7") (pin "TP") (pinfunction "TP_TP") (pintype "input"))
      (node (ref "U1204") (pin "15") (pinfunction "PG_15") (pintype "bidirectional"))
      (node (ref "U1205") (pin "7") (pinfunction "EN_7") (pintype "bidirectional"))
    )
    (net (code "14") (name "2V5") (class "Default")
      (node (ref "C1203") (pin "1") (pinfunction "C1_1") (pintype "passive"))
      (node (ref "C1222") (pin "1") (pinfunction "C1_1") (pintype "passive"))
      (node (ref "C1228") (pin "1") (pinfunction "C1_1") (pintype "passive"))
      (node (ref "C1245") (pin "1") (pinfunction "C1_1") (pintype "passive"))
      (node (ref "C1246") (pin "1") (pinfunction "C1_1") (pintype "passive"))
      (node (ref "C204") (pin "1") (pinfunction "C1_1") (pintype "passive"))
      (node (ref "C209") (pin "1") (pinfunction "C1_1") (pintype "passive"))
      (node (ref "C214") (pin "1") (pinfunction "C1_1") (pintype "passive"))
      (node (ref "C219") (pin "1") (pinfunction "C1_1") (pintype "passive"))
      (node (ref "C224") (pin "1") (pinfunction "C1_1") (pintype "passive"))
      (node (ref "C229") (pin "1") (pinfunction "C1_1") (pintype "passive"))
      (node (ref "C234") (pin "1") (pinfunction "C1_1") (pintype "passive"))
      (node (ref "C239") (pin "1") (pinfunction "C1_1") (pintype "passive"))
      (node (ref "C244") (pin "1") (pinfunction "C1_1") (pintype "passive"))
      (node (ref "C249") (pin "1") (pinfunction "C1_1") (pintype "passive"))
      (node (ref "C254") (pin "1") (pinfunction "C1_1") (pintype "passive"))
      (node (ref "C259") (pin "1") (pinfunction "C1_1") (pintype "passive"))
      (node (ref "C401") (pin "1") (pinfunction "C1_1") (pintype "passive"))
      (node (ref "FB401") (pin "1") (pinfunction "1_1") (pintype "passive"))
      (node (ref "JP1101") (pin "6") (pinfunction "S_6") (pintype "passive"))
      (node (ref "L1203") (pin "1") (pinfunction "1_1") (pintype "passive"))
      (node (ref "R1207") (pin "2") (pinfunction "2_2") (pintype "passive"))
      (node (ref "R1208") (pin "2") (pinfunction "2_2") (pintype "passive"))
      (node (ref "R503") (pin "2") (pinfunction "2_2") (pintype "passive"))
      (node (ref "R504") (pin "2") (pinfunction "2_2") (pintype "passive"))
      (node (ref "R509") (pin "2") (pinfunction "2_2") (pintype "passive"))
      (node (ref "R510") (pin "2") (pinfunction "2_2") (pintype "passive"))
      (node (ref "U1202") (pin "7") (pinfunction "VIN_7") (pintype "bidirectional"))
      (node (ref "U1202") (pin "8") (pinfunction "VIN_8") (pintype "bidirectional"))
      (node (ref "U1206") (pin "7") (pinfunction "VIN_7") (pintype "bidirectional"))
      (node (ref "U1206") (pin "8") (pinfunction "VIN_8") (pintype "bidirectional"))
      (node (ref "U1208") (pin "17") (pinfunction "SNS_17") (pintype "bidirectional"))
      (node (ref "U201") (pin "A17") (pinfunction "VCCO_16_A17") (pintype "bidirectional"))
      (node (ref "U201") (pin "B14") (pinfunction "VCCO_16_B14") (pintype "bidirectional"))
      (node (ref "U201") (pin "C21") (pinfunction "VCCO_16_C21") (pintype "bidirectional"))
      (node (ref "U201") (pin "D18") (pinfunction "VCCO_16_D18") (pintype "bidirectional"))
      (node (ref "U201") (pin "E15") (pinfunction "VCCO_16_E15") (pintype "bidirectional"))
      (node (ref "U201") (pin "F20") (pinfunction "IO_L18N/T2_F20") (pintype "bidirectional"))
      (node (ref "U201") (pin "F21") (pinfunction "IO_25_F21") (pintype "bidirectional"))
      (node (ref "U201") (pin "F22") (pinfunction "VCCO_16_F22") (pintype "bidirectional"))
      (node (ref "U201") (pin "G19") (pinfunction "VCCO_15_G19") (pintype "bidirectional"))
      (node (ref "U201") (pin "H16") (pinfunction "VCCO_15_H16") (pintype "bidirectional"))
      (node (ref "U201") (pin "J13") (pinfunction "VCCO_15_J13") (pintype "bidirectional"))
      (node (ref "U201") (pin "K20") (pinfunction "VCCO_15_K20") (pintype "bidirectional"))
      (node (ref "U201") (pin "L17") (pinfunction "VCCO_15_L17") (pintype "bidirectional"))
      (node (ref "U201") (pin "N21") (pinfunction "VCCO_15_N21") (pintype "bidirectional"))
    )
    (net (code "15") (name "2V5_PGOOD") (class "Default")
      (node (ref "R1207") (pin "1") (pinfunction "1_1") (pintype "passive"))
      (node (ref "TP5") (pin "TP") (pinfunction "TP_TP") (pintype "input"))
      (node (ref "U1202") (pin "5") (pinfunction "EN_5") (pintype "bidirectional"))
      (node (ref "U1206") (pin "5") (pinfunction "EN_5") (pintype "bidirectional"))
      (node (ref "U1208") (pin "15") (pinfunction "PG_15") (pintype "bidirectional"))
    )
    (net (code "16") (name "3V0_VIN_REG_INTVCC") (class "Default")
      (node (ref "C1114") (pin "1") (pinfunction "C1_1") (pintype "passive"))
      (node (ref "U1102") (pin "4") (pinfunction "ITH_4") (pintype "bidirectional"))
      (node (ref "U1102") (pin "5") (pinfunction "ITH_5") (pintype "bidirectional"))
      (node (ref "U1102") (pin "6") (pinfunction "INTVCC_6") (pintype "bidirectional"))
    )
    (net (code "17") (name "3V3") (class "Default")
      (node (ref "C1005") (pin "1") (pinfunction "C1_1") (pintype "passive"))
      (node (ref "C1253") (pin "1") (pinfunction "C1_1") (pintype "passive"))
      (node (ref "C1254") (pin "1") (pinfunction "C1_1") (pintype "passive"))
      (node (ref "C203") (pin "1") (pinfunction "C1_1") (pintype "passive"))
      (node (ref "C208") (pin "1") (pinfunction "C1_1") (pintype "passive"))
      (node (ref "C213") (pin "1") (pinfunction "C1_1") (pintype "passive"))
      (node (ref "C218") (pin "1") (pinfunction "C1_1") (pintype "passive"))
      (node (ref "C223") (pin "1") (pinfunction "C1_1") (pintype "passive"))
      (node (ref "C228") (pin "1") (pinfunction "C1_1") (pintype "passive"))
      (node (ref "C233") (pin "1") (pinfunction "C1_1") (pintype "passive"))
      (node (ref "C237") (pin "1") (pinfunction "C1_1") (pintype "passive"))
      (node (ref "C238") (pin "1") (pinfunction "C1_1") (pintype "passive"))
      (node (ref "C243") (pin "1") (pinfunction "C1_1") (pintype "passive"))
      (node (ref "C248") (pin "1") (pinfunction "C1_1") (pintype "passive"))
      (node (ref "C253") (pin "1") (pinfunction "C1_1") (pintype "passive"))
      (node (ref "C258") (pin "1") (pinfunction "C1_1") (pintype "passive"))
      (node (ref "C264") (pin "1") (pinfunction "C1_1") (pintype "passive"))
      (node (ref "C708") (pin "1") (pinfunction "C1_1") (pintype "passive"))
      (node (ref "C902") (pin "1") (pinfunction "C1_1") (pintype "passive"))
      (node (ref "FB701") (pin "2") (pinfunction "2_2") (pintype "passive"))
      (node (ref "FB901") (pin "1") (pinfunction "1_1") (pintype "passive"))
      (node (ref "JP1101") (pin "5") (pinfunction "S_5") (pintype "passive"))
      (node (ref "L1204") (pin "2") (pinfunction "2_2") (pintype "passive"))
      (node (ref "R1118") (pin "2") (pinfunction "2_2") (pintype "passive"))
      (node (ref "R1211") (pin "2") (pinfunction "2_2") (pintype "passive"))
      (node (ref "R1212") (pin "2") (pinfunction "2_2") (pintype "passive"))
      (node (ref "R201") (pin "2") (pinfunction "2_2") (pintype "passive"))
      (node (ref "R202") (pin "2") (pinfunction "2_2") (pintype "passive"))
      (node (ref "R205") (pin "2") (pinfunction "2_2") (pintype "passive"))
      (node (ref "R207") (pin "2") (pinfunction "2_2") (pintype "passive"))
      (node (ref "R214") (pin "2") (pinfunction "2_2") (pintype "passive"))
      (node (ref "R215") (pin "2") (pinfunction "2_2") (pintype "passive"))
      (node (ref "R217") (pin "2") (pinfunction "2_2") (pintype "passive"))
      (node (ref "R218") (pin "2") (pinfunction "2_2") (pintype "passive"))
      (node (ref "R219") (pin "2") (pinfunction "2_2") (pintype "passive"))
      (node (ref "R220") (pin "2") (pinfunction "2_2") (pintype "passive"))
      (node (ref "R221") (pin "2") (pinfunction "2_2") (pintype "passive"))
      (node (ref "R222") (pin "2") (pinfunction "2_2") (pintype "passive"))
      (node (ref "R803") (pin "2") (pinfunction "2_2") (pintype "passive"))
      (node (ref "R804") (pin "2") (pinfunction "2_2") (pintype "passive"))
      (node (ref "R805") (pin "2") (pinfunction "2_2") (pintype "passive"))
      (node (ref "R904") (pin "2") (pinfunction "2_2") (pintype "passive"))
      (node (ref "R905") (pin "2") (pinfunction "2_2") (pintype "passive"))
      (node (ref "TC201") (pin "1") (pinfunction "S_1") (pintype "passive"))
      (node (ref "U1001") (pin "8") (pinfunction "VCC_8") (pintype "bidirectional"))
      (node (ref "U1208") (pin "10") (pinfunction "SNS_10") (pintype "bidirectional"))
      (node (ref "U201") (pin "AA17") (pinfunction "VCCO_13_AA17") (pintype "bidirectional"))
      (node (ref "U201") (pin "AB14") (pinfunction "VCCO_13_AB14") (pintype "bidirectional"))
      (node (ref "U201") (pin "F12") (pinfunction "VCCO_0_F12") (pintype "bidirectional"))
      (node (ref "U201") (pin "M14") (pinfunction "VCCO_14_M14") (pintype "bidirectional"))
      (node (ref "U201") (pin "P18") (pinfunction "VCCO_14_P18") (pintype "bidirectional"))
      (node (ref "U201") (pin "R15") (pinfunction "VCCO_14_R15") (pintype "bidirectional"))
      (node (ref "U201") (pin "T12") (pinfunction "VCCO_0_T12") (pintype "bidirectional"))
      (node (ref "U201") (pin "T22") (pinfunction "VCCO_14_T22") (pintype "bidirectional"))
      (node (ref "U201") (pin "U11") (pinfunction "M0_U11") (pintype "bidirectional"))
      (node (ref "U201") (pin "U19") (pinfunction "VCCO_14_U19") (pintype "bidirectional"))
      (node (ref "U201") (pin "U8") (pinfunction "CFGBVS_U8") (pintype "bidirectional"))
      (node (ref "U201") (pin "V16") (pinfunction "VCCO_13_V16") (pintype "bidirectional"))
      (node (ref "U201") (pin "W13") (pinfunction "VCCO_13_W13") (pintype "bidirectional"))
      (node (ref "U201") (pin "Y10") (pinfunction "VCCO_13_Y10") (pintype "bidirectional"))
      (node (ref "U201") (pin "Y20") (pinfunction "VCCO_14_Y20") (pintype "bidirectional"))
      (node (ref "U202") (pin "8") (pinfunction "VCC_8") (pintype "power_in"))
    )
    (net (code "18") (name "3V3_CLK_MNGR") (class "Default")
      (node (ref "C901") (pin "1") (pinfunction "C1_1") (pintype "passive"))
      (node (ref "C903") (pin "1") (pinfunction "C1_1") (pintype "passive"))
      (node (ref "C904") (pin "1") (pinfunction "C1_1") (pintype "passive"))
      (node (ref "C905") (pin "1") (pinfunction "C1_1") (pintype "passive"))
      (node (ref "C908") (pin "1") (pinfunction "C1_1") (pintype "passive"))
      (node (ref "C909") (pin "1") (pinfunction "C1_1") (pintype "passive"))
      (node (ref "FB901") (pin "2") (pinfunction "2_2") (pintype "passive"))
      (node (ref "U901") (pin "4") (pinfunction "VDD_4") (pintype "power_in"))
      (node (ref "U902") (pin "10") (pinfunction "VDDOB_10") (pintype "bidirectional"))
      (node (ref "U902") (pin "11") (pinfunction "VDDOA_11") (pintype "bidirectional"))
      (node (ref "U902") (pin "14") (pinfunction "VDDOD_14") (pintype "bidirectional"))
      (node (ref "U902") (pin "18") (pinfunction "VDDOC_18") (pintype "bidirectional"))
      (node (ref "U902") (pin "20") (pinfunction "VDD_20") (pintype "bidirectional"))
    )
    (net (code "19") (name "3V3_CM4") (class "Default")
      (node (ref "C101") (pin "1") (pinfunction "C1_1") (pintype "passive"))
      (node (ref "C106") (pin "1") (pinfunction "C1_1") (pintype "passive"))
      (node (ref "C108") (pin "1") (pinfunction "C1_1") (pintype "passive"))
      (node (ref "CON101") (pin "1") (pinfunction "S_1") (pintype "passive"))
      (node (ref "CON102") (pin "1") (pinfunction "S_1") (pintype "passive"))
      (node (ref "R101") (pin "2") (pinfunction "2_2") (pintype "passive"))
      (node (ref "R103") (pin "2") (pinfunction "2_2") (pintype "passive"))
      (node (ref "R106") (pin "2") (pinfunction "2_2") (pintype "passive"))
      (node (ref "R108") (pin "2") (pinfunction "2_2") (pintype "passive"))
      (node (ref "R116") (pin "2") (pinfunction "2_2") (pintype "passive"))
      (node (ref "R117") (pin "2") (pinfunction "2_2") (pintype "passive"))
      (node (ref "R118") (pin "2") (pinfunction "2_2") (pintype "passive"))
      (node (ref "R119") (pin "2") (pinfunction "2_2") (pintype "passive"))
      (node (ref "R120") (pin "2") (pinfunction "2_2") (pintype "passive"))
      (node (ref "R121") (pin "2") (pinfunction "2_2") (pintype "passive"))
      (node (ref "R801") (pin "2") (pinfunction "2_2") (pintype "passive"))
      (node (ref "R802") (pin "2") (pinfunction "2_2") (pintype "passive"))
      (node (ref "U101") (pin "1") (pinfunction "VIN_1") (pintype "bidirectional"))
      (node (ref "U102") (pin "78") (pinfunction "GPIO_VREF_78") (pintype "bidirectional"))
      (node (ref "U102") (pin "84") (pinfunction "3V3_OUT_84") (pintype "bidirectional"))
      (node (ref "U102") (pin "86") (pinfunction "3V3_OUT_86") (pintype "bidirectional"))
    )
    (net (code "20") (name "3V3_CODEC") (class "Default")
      (node (ref "C1255") (pin "1") (pinfunction "C1_1") (pintype "passive"))
      (node (ref "C701") (pin "1") (pinfunction "C1_1") (pintype "passive"))
      (node (ref "C702") (pin "1") (pinfunction "C1_1") (pintype "passive"))
      (node (ref "C703") (pin "1") (pinfunction "C1_1") (pintype "passive"))
      (node (ref "C704") (pin "1") (pinfunction "C1_1") (pintype "passive"))
      (node (ref "C711") (pin "1") (pinfunction "C1_1") (pintype "passive"))
      (node (ref "C716") (pin "1") (pinfunction "C1_1") (pintype "passive"))
      (node (ref "CON701") (pin "1") (pinfunction "S_1") (pintype "passive"))
      (node (ref "M701") (pin "2") (pinfunction "SEL_2") (pintype "passive"))
      (node (ref "M701") (pin "5") (pinfunction "VCC_5") (pintype "passive"))
      (node (ref "M702") (pin "5") (pinfunction "VCC_5") (pintype "passive"))
      (node (ref "U1210") (pin "4") (pinfunction "SENSE/ADJ_4") (pintype "bidirectional"))
      (node (ref "U1210") (pin "5") (pinfunction "VOUT_5") (pintype "bidirectional"))
      (node (ref "U701") (pin "10") (pinfunction "AVDD_10") (pintype "bidirectional"))
      (node (ref "U701") (pin "19") (pinfunction "AVDD_19") (pintype "bidirectional"))
      (node (ref "U701") (pin "24") (pinfunction "AVDD_24") (pintype "bidirectional"))
    )
    (net (code "21") (name "3V3_PGOOD") (class "Default")
      (node (ref "R1211") (pin "1") (pinfunction "1_1") (pintype "passive"))
      (node (ref "TP6") (pin "TP") (pinfunction "TP_TP") (pintype "input"))
      (node (ref "U1208") (pin "12") (pinfunction "PG_12") (pintype "bidirectional"))
    )
    (net (code "22") (name "3V3_PM") (class "Default")
      (node (ref "C1007") (pin "1") (pinfunction "C1_1") (pintype "passive"))
      (node (ref "C1008") (pin "1") (pinfunction "C1_1") (pintype "passive"))
      (node (ref "C1010") (pin "1") (pinfunction "C1_1") (pintype "passive"))
      (node (ref "C1108") (pin "1") (pinfunction "C1_1") (pintype "passive"))
      (node (ref "C1109") (pin "1") (pinfunction "C1_1") (pintype "passive"))
      (node (ref "C1113") (pin "1") (pinfunction "C1_1") (pintype "passive"))
      (node (ref "R1002") (pin "2") (pinfunction "2_2") (pintype "passive"))
      (node (ref "R1004") (pin "2") (pinfunction "2_2") (pintype "passive"))
      (node (ref "R1007") (pin "2") (pinfunction "2_2") (pintype "passive"))
      (node (ref "R1011") (pin "2") (pinfunction "2_2") (pintype "passive"))
      (node (ref "R1014") (pin "2") (pinfunction "2_2") (pintype "passive"))
      (node (ref "TC1001") (pin "1") (pinfunction "S_1") (pintype "passive"))
      (node (ref "U1002") (pin "14") (pinfunction "VDD33_ALW_IN_14") (pintype "bidirectional"))
      (node (ref "U1002") (pin "16") (pinfunction "VDD33_IO_IN_16") (pintype "bidirectional"))
      (node (ref "U1002") (pin "21") (pinfunction "VDD33_ANA_IN_21") (pintype "bidirectional"))
      (node (ref "U1002") (pin "6") (pinfunction "VDD33_REG_IN_6") (pintype "bidirectional"))
      (node (ref "U1101") (pin "5") (pinfunction "VOUT_5") (pintype "bidirectional"))
      (node (ref "U1102") (pin "21") (pinfunction "EXTVCC_21") (pintype "bidirectional"))
    )
    (net (code "23") (name "3V3_SYNTH_IN_PD_FB") (class "Default")
      (node (ref "C1214") (pin "1") (pinfunction "C1_1") (pintype "passive"))
      (node (ref "C1217") (pin "1") (pinfunction "C1_1") (pintype "passive"))
      (node (ref "C604") (pin "1") (pinfunction "C1_1") (pintype "passive"))
      (node (ref "C607") (pin "1") (pinfunction "C1_1") (pintype "passive"))
      (node (ref "C610") (pin "1") (pinfunction "C1_1") (pintype "passive"))
      (node (ref "FB601") (pin "1") (pinfunction "1_1") (pintype "passive"))
      (node (ref "R604") (pin "2") (pinfunction "2_2") (pintype "passive"))
      (node (ref "R606") (pin "2") (pinfunction "2_2") (pintype "passive"))
      (node (ref "U1203") (pin "1") (pinfunction "VOUT_1") (pintype "bidirectional"))
      (node (ref "U1203") (pin "2") (pinfunction "VOUT_2") (pintype "bidirectional"))
      (node (ref "U1203") (pin "3") (pinfunction "SENSE_3") (pintype "bidirectional"))
      (node (ref "U601") (pin "12") (pinfunction "VDDPDCP_12") (pintype "bidirectional"))
      (node (ref "U601") (pin "15") (pinfunction "VDDFB_15") (pintype "bidirectional"))
      (node (ref "U601") (pin "24") (pinfunction "VDDIN_24") (pintype "bidirectional"))
    )
    (net (code "24") (name "3V3_SYNTH_VCO_RF") (class "Default")
      (node (ref "C1237") (pin "1") (pinfunction "C1_1") (pintype "passive"))
      (node (ref "C1241") (pin "1") (pinfunction "C1_1") (pintype "passive"))
      (node (ref "C602") (pin "1") (pinfunction "C1_1") (pintype "passive"))
      (node (ref "C605") (pin "1") (pinfunction "C1_1") (pintype "passive"))
      (node (ref "C608") (pin "1") (pinfunction "C1_1") (pintype "passive"))
      (node (ref "C611") (pin "1") (pinfunction "C1_1") (pintype "passive"))
      (node (ref "L601") (pin "1") (pinfunction "1_1") (pintype "passive"))
      (node (ref "L602") (pin "1") (pinfunction "1_1") (pintype "passive"))
      (node (ref "U1207") (pin "1") (pinfunction "VOUT_1") (pintype "bidirectional"))
      (node (ref "U1207") (pin "2") (pinfunction "VOUT_2") (pintype "bidirectional"))
      (node (ref "U1207") (pin "3") (pinfunction "SENSE_3") (pintype "bidirectional"))
      (node (ref "U601") (pin "3") (pinfunction "VDDVCO2_3") (pintype "bidirectional"))
      (node (ref "U601") (pin "33") (pinfunction "VDDVCO1_33") (pintype "bidirectional"))
      (node (ref "U601") (pin "37") (pinfunction "VDDOUTA_37") (pintype "bidirectional"))
      (node (ref "U601") (pin "48") (pinfunction "VDDOUTB_48") (pintype "bidirectional"))
    )
    (net (code "25") (name "3V5_VIN_REG_DRVCC") (class "Default")
      (node (ref "C1126") (pin "1") (pinfunction "C1_1") (pintype "passive"))
      (node (ref "R1120") (pin "2") (pinfunction "2_2") (pintype "passive"))
      (node (ref "R1123") (pin "2") (pinfunction "2_2") (pintype "passive"))
      (node (ref "R1124") (pin "2") (pinfunction "2_2") (pintype "passive"))
      (node (ref "U1102") (pin "20") (pinfunction "DRVCC_20") (pintype "bidirectional"))
      (node (ref "U1102") (pin "27") (pinfunction "~{FAULT}_27") (pintype "bidirectional"))
      (node (ref "U1102") (pin "28") (pinfunction "~{FAULT}_28") (pintype "bidirectional"))
    )
    (net (code "26") (name "5V0") (class "Default")
      (node (ref "C1012") (pin "1") (pinfunction "C1_1") (pintype "passive"))
      (node (ref "C1013") (pin "1") (pinfunction "C1_1") (pintype "passive"))
      (node (ref "C102") (pin "1") (pinfunction "C1_1") (pintype "passive"))
      (node (ref "C103") (pin "1") (pinfunction "C1_1") (pintype "passive"))
      (node (ref "C104") (pin "1") (pinfunction "C1_1") (pintype "passive"))
      (node (ref "C1122") (pin "1") (pinfunction "C1_1") (pintype "passive"))
      (node (ref "C1124") (pin "1") (pinfunction "C1_1") (pintype "passive"))
      (node (ref "C1127") (pin "1") (pinfunction "C1_1") (pintype "passive"))
      (node (ref "C1129") (pin "1") (pinfunction "C1_1") (pintype "passive"))
      (node (ref "C1201") (pin "1") (pinfunction "C1_1") (pintype "passive"))
      (node (ref "C1202") (pin "1") (pinfunction "C1_1") (pintype "passive"))
      (node (ref "C1204") (pin "1") (pinfunction "C1_1") (pintype "passive"))
      (node (ref "C1205") (pin "1") (pinfunction "C1_1") (pintype "passive"))
      (node (ref "C1223") (pin "1") (pinfunction "C1_1") (pintype "passive"))
      (node (ref "C1225") (pin "1") (pinfunction "C1_1") (pintype "passive"))
      (node (ref "C1229") (pin "1") (pinfunction "C1_1") (pintype "passive"))
      (node (ref "C1230") (pin "1") (pinfunction "C1_1") (pintype "passive"))
      (node (ref "C1232") (pin "1") (pinfunction "C1_1") (pintype "passive"))
      (node (ref "C1239") (pin "1") (pinfunction "C1_1") (pintype "passive"))
      (node (ref "C1242") (pin "1") (pinfunction "C1_1") (pintype "passive"))
      (node (ref "C1247") (pin "1") (pinfunction "C1_1") (pintype "passive"))
      (node (ref "C1248") (pin "1") (pinfunction "C1_1") (pintype "passive"))
      (node (ref "C1250") (pin "1") (pinfunction "C1_1") (pintype "passive"))
      (node (ref "C1256") (pin "1") (pinfunction "C1_1") (pintype "passive"))
      (node (ref "C1258") (pin "1") (pinfunction "C1_1") (pintype "passive"))
      (node (ref "JP1101") (pin "1") (pinfunction "S_1") (pintype "passive"))
      (node (ref "JP1101") (pin "2") (pinfunction "S_2") (pintype "passive"))
      (node (ref "L1101") (pin "2") (pinfunction "2_2") (pintype "passive"))
      (node (ref "R1119") (pin "2") (pinfunction "2_2") (pintype "passive"))
      (node (ref "R1121") (pin "2") (pinfunction "2_2") (pintype "passive"))
      (node (ref "R1122") (pin "2") (pinfunction "2_2") (pintype "passive"))
      (node (ref "R1210") (pin "2") (pinfunction "2_2") (pintype "passive"))
      (node (ref "U1002") (pin "3") (pinfunction "VCONN_IN_3") (pintype "bidirectional"))
      (node (ref "U1003") (pin "1") (pinfunction "VIN_1") (pintype "bidirectional"))
      (node (ref "U102") (pin "77") (pinfunction "5V0_77") (pintype "bidirectional"))
      (node (ref "U102") (pin "79") (pinfunction "5V0_79") (pintype "bidirectional"))
      (node (ref "U102") (pin "81") (pinfunction "5V0_81") (pintype "bidirectional"))
      (node (ref "U102") (pin "83") (pinfunction "5V0_83") (pintype "bidirectional"))
      (node (ref "U102") (pin "85") (pinfunction "5V0_85") (pintype "bidirectional"))
      (node (ref "U102") (pin "87") (pinfunction "5V0_87") (pintype "bidirectional"))
      (node (ref "U1102") (pin "2") (pinfunction "VSENSEP_2") (pintype "bidirectional"))
      (node (ref "U1201") (pin "7") (pinfunction "VIN_7") (pintype "bidirectional"))
      (node (ref "U1201") (pin "8") (pinfunction "VIN_8") (pintype "bidirectional"))
      (node (ref "U1203") (pin "7") (pinfunction "VIN_7") (pintype "bidirectional"))
      (node (ref "U1203") (pin "8") (pinfunction "VIN_8") (pintype "bidirectional"))
      (node (ref "U1204") (pin "1") (pinfunction "VIN_1") (pintype "bidirectional"))
      (node (ref "U1204") (pin "20") (pinfunction "AVIN_20") (pintype "bidirectional"))
      (node (ref "U1204") (pin "6") (pinfunction "VIN_6") (pintype "bidirectional"))
      (node (ref "U1204") (pin "7") (pinfunction "AVIN_7") (pintype "bidirectional"))
      (node (ref "U1205") (pin "2") (pinfunction "BIAS_2") (pintype "bidirectional"))
      (node (ref "U1207") (pin "7") (pinfunction "VIN_7") (pintype "bidirectional"))
      (node (ref "U1207") (pin "8") (pinfunction "VIN_8") (pintype "bidirectional"))
      (node (ref "U1208") (pin "1") (pinfunction "VIN_1") (pintype "bidirectional"))
      (node (ref "U1208") (pin "20") (pinfunction "AVIN_20") (pintype "bidirectional"))
      (node (ref "U1208") (pin "6") (pinfunction "VIN_6") (pintype "bidirectional"))
      (node (ref "U1208") (pin "7") (pinfunction "AVIN_7") (pintype "bidirectional"))
      (node (ref "U1209") (pin "8") (pinfunction "VIN_8") (pintype "bidirectional"))
      (node (ref "U1209") (pin "9") (pinfunction "VIN_9") (pintype "bidirectional"))
      (node (ref "U1210") (pin "1") (pinfunction "VIN_1") (pintype "bidirectional"))
    )
    (net (code "27") (name "5V0_PGOOD") (class "Default")
      (node (ref "R1121") (pin "1") (pinfunction "1_1") (pintype "passive"))
      (node (ref "TP1") (pin "TP") (pinfunction "TP_TP") (pintype "input"))
      (node (ref "U1102") (pin "23") (pinfunction "RUN_23") (pintype "bidirectional"))
      (node (ref "U1102") (pin "33") (pinfunction "PGOOD_33") (pintype "bidirectional"))
      (node (ref "U1201") (pin "5") (pinfunction "EN_5") (pintype "bidirectional"))
      (node (ref "U1203") (pin "5") (pinfunction "EN_5") (pintype "bidirectional"))
      (node (ref "U1207") (pin "5") (pinfunction "EN_5") (pintype "bidirectional"))
      (node (ref "U1210") (pin "3") (pinfunction "EN_3") (pintype "bidirectional"))
    )
    (net (code "28") (name "5V0_TRX_BIAS_T1") (class "Default")
      (node (ref "C505") (pin "1") (pinfunction "C1_1") (pintype "passive"))
      (node (ref "C507") (pin "1") (pinfunction "C1_1") (pintype "passive"))
      (node (ref "C517") (pin "1") (pinfunction "C1_1") (pintype "passive"))
      (node (ref "L501") (pin "1") (pinfunction "1_1") (pintype "passive"))
      (node (ref "R505") (pin "2") (pinfunction "2_2") (pintype "passive"))
      (node (ref "U501") (pin "6") (pinfunction "VOUT_6") (pintype "bidirectional"))
    )
    (net (code "29") (name "5V0_TRX_BIAS_T1_EN") (class "Default")
      (node (ref "U401") (pin "B7") (pinfunction "GPO_0_B7") (pintype "bidirectional"))
      (node (ref "U501") (pin "3") (pinfunction "EN_3") (pintype "bidirectional"))
    )
    (net (code "30") (name "5V0_TRX_BIAS_T2") (class "Default")
      (node (ref "C506") (pin "1") (pinfunction "C1_1") (pintype "passive"))
      (node (ref "C508") (pin "1") (pinfunction "C1_1") (pintype "passive"))
      (node (ref "C518") (pin "1") (pinfunction "C1_1") (pintype "passive"))
      (node (ref "L502") (pin "1") (pinfunction "1_1") (pintype "passive"))
      (node (ref "R506") (pin "2") (pinfunction "2_2") (pintype "passive"))
      (node (ref "U502") (pin "6") (pinfunction "VOUT_6") (pintype "bidirectional"))
    )
    (net (code "31") (name "5V0_TRX_BIAS_T2_EN") (class "Default")
      (node (ref "U401") (pin "B6") (pinfunction "GPO_1_B6") (pintype "bidirectional"))
      (node (ref "U502") (pin "3") (pinfunction "EN_3") (pintype "bidirectional"))
    )
    (net (code "32") (name "5V0_TRX_PA1") (class "Default")
      (node (ref "C521") (pin "1") (pinfunction "C1_1") (pintype "passive"))
      (node (ref "C542") (pin "1") (pinfunction "C1_1") (pintype "passive"))
      (node (ref "C548") (pin "1") (pinfunction "C1_1") (pintype "passive"))
      (node (ref "C551") (pin "1") (pinfunction "C1_1") (pintype "passive"))
      (node (ref "L511") (pin "1") (pinfunction "1_1") (pintype "passive"))
      (node (ref "R511") (pin "2") (pinfunction "2_2") (pintype "passive"))
      (node (ref "U503") (pin "6") (pinfunction "VOUT_6") (pintype "bidirectional"))
    )
    (net (code "33") (name "5V0_TRX_PA1_EN") (class "Default")
      (node (ref "U401") (pin "B5") (pinfunction "GPO_2_B5") (pintype "bidirectional"))
      (node (ref "U503") (pin "3") (pinfunction "EN_3") (pintype "bidirectional"))
    )
    (net (code "34") (name "5V0_TRX_PA2") (class "Default")
      (node (ref "C522") (pin "1") (pinfunction "C1_1") (pintype "passive"))
      (node (ref "C543") (pin "1") (pinfunction "C1_1") (pintype "passive"))
      (node (ref "C549") (pin "1") (pinfunction "C1_1") (pintype "passive"))
      (node (ref "C552") (pin "1") (pinfunction "C1_1") (pintype "passive"))
      (node (ref "L512") (pin "1") (pinfunction "1_1") (pintype "passive"))
      (node (ref "R512") (pin "2") (pinfunction "2_2") (pintype "passive"))
      (node (ref "U504") (pin "6") (pinfunction "VOUT_6") (pintype "bidirectional"))
    )
    (net (code "35") (name "5V0_TRX_PA2_EN") (class "Default")
      (node (ref "U401") (pin "B4") (pinfunction "GPO_3_B4") (pintype "bidirectional"))
      (node (ref "U504") (pin "3") (pinfunction "EN_3") (pintype "bidirectional"))
    )
    (net (code "36") (name "5V0_TRX_RF") (class "Default")
      (node (ref "C1212") (pin "1") (pinfunction "C1_1") (pintype "passive"))
      (node (ref "C1215") (pin "1") (pinfunction "C1_1") (pintype "passive"))
      (node (ref "C503") (pin "1") (pinfunction "C1_1") (pintype "passive"))
      (node (ref "C504") (pin "1") (pinfunction "C1_1") (pintype "passive"))
      (node (ref "C519") (pin "1") (pinfunction "C1_1") (pintype "passive"))
      (node (ref "C520") (pin "1") (pinfunction "C1_1") (pintype "passive"))
      (node (ref "U1201") (pin "1") (pinfunction "VOUT_1") (pintype "bidirectional"))
      (node (ref "U1201") (pin "2") (pinfunction "VOUT_2") (pintype "bidirectional"))
      (node (ref "U1201") (pin "3") (pinfunction "SENSE_3") (pintype "bidirectional"))
      (node (ref "U501") (pin "1") (pinfunction "VIN_1") (pintype "bidirectional"))
      (node (ref "U502") (pin "1") (pinfunction "VIN_1") (pintype "bidirectional"))
      (node (ref "U503") (pin "1") (pinfunction "VIN_1") (pintype "bidirectional"))
      (node (ref "U504") (pin "1") (pinfunction "VIN_1") (pintype "bidirectional"))
    )
    (net (code "37") (name "12V0") (class "Default")
      (node (ref "C1105") (pin "1") (pinfunction "C1_1") (pintype "passive"))
      (node (ref "CON801") (pin "A2") (pinfunction "S_A2") (pintype "passive"))
      (node (ref "CON801") (pin "A3") (pinfunction "S_A3") (pintype "passive"))
      (node (ref "CON801") (pin "B1") (pinfunction "S_B1") (pintype "passive"))
      (node (ref "CON801") (pin "B2") (pinfunction "S_B2") (pintype "passive"))
      (node (ref "CON801") (pin "B3") (pinfunction "S_B3") (pintype "passive"))
      (node (ref "D1102") (pin "A") (pinfunction "A_A") (pintype "passive"))
      (node (ref "Q1104") (pin "5") (pinfunction "D_5") (pintype "passive"))
      (node (ref "Q1104") (pin "6") (pinfunction "D_6") (pintype "passive"))
      (node (ref "R1108") (pin "2") (pinfunction "2_2") (pintype "passive"))
    )
    (net (code "38") (name "12V0_EN") (class "Default")
      (node (ref "Q1103") (pin "1") (pinfunction "G_1") (pintype "passive"))
      (node (ref "R1112") (pin "2") (pinfunction "2_2") (pintype "passive"))
      (node (ref "U1002") (pin "30") (pinfunction "PA15_30") (pintype "bidirectional"))
    )
    (net (code "39") (name "12V0_VSENSE") (class "Default")
      (node (ref "C1106") (pin "1") (pinfunction "C1_1") (pintype "passive"))
      (node (ref "R1108") (pin "1") (pinfunction "1_1") (pintype "passive"))
      (node (ref "R1109") (pin "2") (pinfunction "2_2") (pintype "passive"))
      (node (ref "U1002") (pin "17") (pinfunction "PA04_17") (pintype "bidirectional"))
    )
    (net (code "40") (name "AUDIO_I2C_SCL") (class "Default")
      (node (ref "R207") (pin "1") (pinfunction "1_1") (pintype "passive"))
      (node (ref "U201") (pin "AA14") (pinfunction "IO_L5N/T0_AA14") (pintype "bidirectional"))
      (node (ref "U701") (pin "2") (pinfunction "SCL/SCLK_2") (pintype "bidirectional"))
    )
    (net (code "41") (name "AUDIO_I2C_SDA") (class "Default")
      (node (ref "R205") (pin "1") (pinfunction "1_1") (pintype "passive"))
      (node (ref "U201") (pin "AA13") (pinfunction "IO_L3P/T0_DQS_AA13") (pintype "bidirectional"))
      (node (ref "U701") (pin "1") (pinfunction "SDA/MISO_1") (pintype "bidirectional"))
    )
    (net (code "42") (name "CM4_CAM0_CSI_C_N") (class "Default")
      (node (ref "CON101") (pin "15") (pinfunction "S_15") (pintype "passive"))
      (node (ref "U102") (pin "140") (pinfunction "CAM_C_N_140") (pintype "bidirectional"))
    )
    (net (code "43") (name "CM4_CAM0_CSI_C_P") (class "Default")
      (node (ref "CON101") (pin "14") (pinfunction "S_14") (pintype "passive"))
      (node (ref "U102") (pin "142") (pinfunction "CAM_C_P_142") (pintype "bidirectional"))
    )
    (net (code "44") (name "CM4_CAM0_CSI_D0_N") (class "Default")
      (node (ref "CON101") (pin "21") (pinfunction "S_21") (pintype "passive"))
      (node (ref "U102") (pin "128") (pinfunction "CAM_D0_N_128") (pintype "bidirectional"))
    )
    (net (code "45") (name "CM4_CAM0_CSI_D0_P") (class "Default")
      (node (ref "CON101") (pin "20") (pinfunction "S_20") (pintype "passive"))
      (node (ref "U102") (pin "130") (pinfunction "CAM_D0_P_130") (pintype "bidirectional"))
    )
    (net (code "46") (name "CM4_CAM0_CSI_D1_N") (class "Default")
      (node (ref "CON101") (pin "18") (pinfunction "S_18") (pintype "passive"))
      (node (ref "U102") (pin "134") (pinfunction "CAM_D1_N_134") (pintype "bidirectional"))
    )
    (net (code "47") (name "CM4_CAM0_CSI_D1_P") (class "Default")
      (node (ref "CON101") (pin "17") (pinfunction "S_17") (pintype "passive"))
      (node (ref "U102") (pin "136") (pinfunction "CAM_D1_P_136") (pintype "bidirectional"))
    )
    (net (code "48") (name "CM4_CAM0_SCL") (class "Default")
      (node (ref "CON101") (pin "3") (pinfunction "S_3") (pintype "passive"))
      (node (ref "R117") (pin "1") (pinfunction "1_1") (pintype "passive"))
      (node (ref "U102") (pin "35") (pinfunction "GPIO1_35") (pintype "bidirectional"))
    )
    (net (code "49") (name "CM4_CAM0_SDA") (class "Default")
      (node (ref "CON101") (pin "2") (pinfunction "S_2") (pintype "passive"))
      (node (ref "R116") (pin "1") (pinfunction "1_1") (pintype "passive"))
      (node (ref "U102") (pin "36") (pinfunction "GPIO0_36") (pintype "bidirectional"))
    )
    (net (code "50") (name "CM4_CAM1_CSI_C_N") (class "Default")
      (node (ref "CON102") (pin "15") (pinfunction "S_15") (pintype "passive"))
      (node (ref "U102") (pin "127") (pinfunction "CAM_C_N_127") (pintype "bidirectional"))
    )
    (net (code "51") (name "CM4_CAM1_CSI_C_P") (class "Default")
      (node (ref "CON102") (pin "14") (pinfunction "S_14") (pintype "passive"))
      (node (ref "U102") (pin "129") (pinfunction "CAM_C_P_129") (pintype "bidirectional"))
    )
    (net (code "52") (name "CM4_CAM1_CSI_D0_N") (class "Default")
      (node (ref "CON102") (pin "21") (pinfunction "S_21") (pintype "passive"))
      (node (ref "U102") (pin "115") (pinfunction "CAM_D0_N_115") (pintype "bidirectional"))
    )
    (net (code "53") (name "CM4_CAM1_CSI_D0_P") (class "Default")
      (node (ref "CON102") (pin "20") (pinfunction "S_20") (pintype "passive"))
      (node (ref "U102") (pin "117") (pinfunction "CAM_D0_P_117") (pintype "bidirectional"))
    )
    (net (code "54") (name "CM4_CAM1_CSI_D1_N") (class "Default")
      (node (ref "CON102") (pin "18") (pinfunction "S_18") (pintype "passive"))
      (node (ref "U102") (pin "121") (pinfunction "CAM_D1_N_121") (pintype "bidirectional"))
    )
    (net (code "55") (name "CM4_CAM1_CSI_D1_P") (class "Default")
      (node (ref "CON102") (pin "17") (pinfunction "S_17") (pintype "passive"))
      (node (ref "U102") (pin "123") (pinfunction "CAM_D1_P_123") (pintype "bidirectional"))
    )
    (net (code "56") (name "CM4_CAM1_CSI_D2_N") (class "Default")
      (node (ref "CON102") (pin "12") (pinfunction "S_12") (pintype "passive"))
      (node (ref "U102") (pin "133") (pinfunction "CAM_D2_N_133") (pintype "bidirectional"))
    )
    (net (code "57") (name "CM4_CAM1_CSI_D2_P") (class "Default")
      (node (ref "CON102") (pin "11") (pinfunction "S_11") (pintype "passive"))
      (node (ref "U102") (pin "135") (pinfunction "CAM_D2_P_135") (pintype "bidirectional"))
    )
    (net (code "58") (name "CM4_CAM1_CSI_D3_N") (class "Default")
      (node (ref "CON102") (pin "9") (pinfunction "S_9") (pintype "passive"))
      (node (ref "U102") (pin "139") (pinfunction "CAM_D3_N_139") (pintype "bidirectional"))
    )
    (net (code "59") (name "CM4_CAM1_CSI_D3_P") (class "Default")
      (node (ref "CON102") (pin "8") (pinfunction "S_8") (pintype "passive"))
      (node (ref "U102") (pin "141") (pinfunction "CAM_D3_P_141") (pintype "bidirectional"))
    )
    (net (code "60") (name "CM4_CAM1_SCL") (class "Default")
      (node (ref "CON102") (pin "3") (pinfunction "S_3") (pintype "passive"))
      (node (ref "R121") (pin "1") (pinfunction "1_1") (pintype "passive"))
      (node (ref "U102") (pin "80") (pinfunction "GPIO45_80") (pintype "bidirectional"))
    )
    (net (code "61") (name "CM4_CAM1_SDA") (class "Default")
      (node (ref "CON102") (pin "2") (pinfunction "S_2") (pintype "passive"))
      (node (ref "R120") (pin "1") (pinfunction "1_1") (pintype "passive"))
      (node (ref "U102") (pin "82") (pinfunction "GPIO44_82") (pintype "bidirectional"))
    )
    (net (code "62") (name "CM4_CAM_GPIO") (class "Default")
      (node (ref "CON101") (pin "6") (pinfunction "S_6") (pintype "passive"))
      (node (ref "CON102") (pin "6") (pinfunction "S_6") (pintype "passive"))
      (node (ref "U102") (pin "97") (pinfunction "CAMERA_GPIO_97") (pintype "bidirectional"))
    )
    (net (code "63") (name "CM4_GLOBAL_EN") (class "Default")
      (node (ref "R102") (pin "2") (pinfunction "2_2") (pintype "passive"))
      (node (ref "U1002") (pin "37") (pinfunction "PA23/GPIO7_37") (pintype "bidirectional"))
      (node (ref "U102") (pin "99") (pinfunction "GLOBAL_EN_99") (pintype "bidirectional"))
    )
    (net (code "64") (name "CM4_PTP_PPS_IN") (class "Default")
      (node (ref "R110") (pin "2") (pinfunction "2_2") (pintype "passive"))
      (node (ref "R111") (pin "2") (pinfunction "2_2") (pintype "passive"))
      (node (ref "U201") (pin "B1") (pinfunction "IO_L1P/T0/AD4P_B1") (pintype "bidirectional"))
    )
    (net (code "65") (name "CM4_PTP_PPS_OUT") (class "Default")
      (node (ref "R112") (pin "2") (pinfunction "2_2") (pintype "passive"))
      (node (ref "R113") (pin "2") (pinfunction "2_2") (pintype "passive"))
      (node (ref "U201") (pin "A1") (pinfunction "IO_L1N/T0/AD4N_A1") (pintype "bidirectional"))
    )
    (net (code "66") (name "CM4_RUNNING") (class "Default")
      (node (ref "U1002") (pin "35") (pinfunction "PA19/GPIO5_35") (pintype "bidirectional"))
      (node (ref "U102") (pin "92") (pinfunction "RUN_PG_92") (pintype "bidirectional"))
    )
    (net (code "67") (name "CM4_SD_CLK") (class "Default")
      (node (ref "SD101") (pin "5") (pinfunction "CLK_5") (pintype "input"))
      (node (ref "U102") (pin "57") (pinfunction "SD_CLK_57") (pintype "bidirectional"))
    )
    (net (code "68") (name "CM4_SD_CMD") (class "Default")
      (node (ref "SD101") (pin "3") (pinfunction "CMD_3") (pintype "bidirectional"))
      (node (ref "U102") (pin "62") (pinfunction "SD_CMD_62") (pintype "bidirectional"))
    )
    (net (code "69") (name "CM4_SD_D0") (class "Default")
      (node (ref "SD101") (pin "7") (pinfunction "DAT0_7") (pintype "bidirectional"))
      (node (ref "U102") (pin "63") (pinfunction "SD_DAT0_63") (pintype "bidirectional"))
    )
    (net (code "70") (name "CM4_SD_D1") (class "Default")
      (node (ref "SD101") (pin "8") (pinfunction "DAT1_8") (pintype "bidirectional"))
      (node (ref "U102") (pin "67") (pinfunction "SD_DAT1_67") (pintype "bidirectional"))
    )
    (net (code "71") (name "CM4_SD_D2") (class "Default")
      (node (ref "SD101") (pin "1") (pinfunction "DAT2_1") (pintype "bidirectional"))
      (node (ref "U102") (pin "69") (pinfunction "SD_DAT2_69") (pintype "bidirectional"))
    )
    (net (code "72") (name "CM4_SD_D3") (class "Default")
      (node (ref "SD101") (pin "2") (pinfunction "CD/DAT3_2") (pintype "bidirectional"))
      (node (ref "U102") (pin "61") (pinfunction "SD_DAT3_61") (pintype "bidirectional"))
    )
    (net (code "73") (name "CM4_SD_PWR_EN") (class "Default")
      (node (ref "R103") (pin "1") (pinfunction "1_1") (pintype "passive"))
      (node (ref "U101") (pin "3") (pinfunction "EN_3") (pintype "bidirectional"))
      (node (ref "U102") (pin "75") (pinfunction "SD_PWR_ON_75") (pintype "bidirectional"))
    )
    (net (code "74") (name "CM4_UART_RXD") (class "Default")
      (node (ref "R114") (pin "2") (pinfunction "2_2") (pintype "passive"))
      (node (ref "U102") (pin "51") (pinfunction "GPIO15_51") (pintype "bidirectional"))
    )
    (net (code "75") (name "CM4_UART_TXD") (class "Default")
      (node (ref "R115") (pin "2") (pinfunction "2_2") (pintype "passive"))
      (node (ref "U102") (pin "55") (pinfunction "GPIO14_55") (pintype "bidirectional"))
    )
    (net (code "76") (name "CM4_USB_OTG") (class "Default")
      (node (ref "U1002") (pin "1") (pinfunction "PA28_1") (pintype "bidirectional"))
      (node (ref "U102") (pin "101") (pinfunction "USB_OTG_ID_101") (pintype "bidirectional"))
    )
    (net (code "77") (name "CM4_WAKE") (class "Default")
      (node (ref "Q102") (pin "1") (pinfunction "G_1") (pintype "passive"))
      (node (ref "U201") (pin "A13") (pinfunction "IO_L10P/T1_A13") (pintype "bidirectional"))
    )
    (net (code "78") (name "CODEC_DMIC_CLK") (class "Default")
      (node (ref "CON701") (pin "2") (pinfunction "S_2") (pintype "passive"))
      (node (ref "M701") (pin "4") (pinfunction "CLK_4") (pintype "passive"))
      (node (ref "M702") (pin "4") (pinfunction "CLK_4") (pintype "passive"))
      (node (ref "U701") (pin "35") (pinfunction "ADC_SDATA1/CLKOUT/MP6_35") (pintype "bidirectional"))
    )
    (net (code "79") (name "CODEC_DMIC_DATA") (class "Default")
      (node (ref "M701") (pin "1") (pinfunction "DAT_1") (pintype "passive"))
      (node (ref "M702") (pin "1") (pinfunction "DAT_1") (pintype "passive"))
      (node (ref "U701") (pin "37") (pinfunction "DMIC0_1/MP4_37") (pintype "bidirectional"))
    )
    (net (code "80") (name "CODEC_DVDD") (class "Default")
      (node (ref "C705") (pin "1") (pinfunction "C1_1") (pintype "passive"))
      (node (ref "C706") (pin "1") (pinfunction "C1_1") (pintype "passive"))
      (node (ref "U701") (pin "28") (pinfunction "REG_OUT_28") (pintype "bidirectional"))
      (node (ref "U701") (pin "29") (pinfunction "DVDD_29") (pintype "bidirectional"))
    )
    (net (code "81") (name "CODEC_EXT_DMIC_DATA") (class "Default")
      (node (ref "CON701") (pin "3") (pinfunction "S_3") (pintype "passive"))
      (node (ref "U701") (pin "36") (pinfunction "DMIC2_3/MP5_36") (pintype "bidirectional"))
    )
    (net (code "82") (name "CODEC_I2S_LRCLK") (class "Default")
      (node (ref "U201") (pin "W17") (pinfunction "IO_L16N/T2/A15/D31_W17") (pintype "bidirectional"))
      (node (ref "U701") (pin "31") (pinfunction "LRCLK_31") (pintype "bidirectional"))
    )
    (net (code "83") (name "CODEC_I2S_MCLK") (class "Default")
      (node (ref "U201") (pin "AB13") (pinfunction "IO_L3N/T0_DQS_AB13") (pintype "bidirectional"))
      (node (ref "U701") (pin "39") (pinfunction "XTALI/MCLKIN_39") (pintype "bidirectional"))
    )
    (net (code "84") (name "CODEC_I2S_SCLK") (class "Default")
      (node (ref "U201") (pin "V17") (pinfunction "IO_L16P/T2/~{CSI}_V17") (pintype "bidirectional"))
      (node (ref "U701") (pin "32") (pinfunction "BCLK_32") (pintype "bidirectional"))
    )
    (net (code "85") (name "CODEC_I2S_SDIN") (class "Default")
      (node (ref "U201") (pin "W16") (pinfunction "IO_L16N/T2_W16") (pintype "bidirectional"))
      (node (ref "U701") (pin "33") (pinfunction "DAC_SDATA/MP0_33") (pintype "bidirectional"))
    )
    (net (code "86") (name "CODEC_I2S_SDOUT") (class "Default")
      (node (ref "U201") (pin "AA15") (pinfunction "IO_L4P/T0_AA15") (pintype "bidirectional"))
      (node (ref "U701") (pin "34") (pinfunction "ADC_SDATA0/MP1_34") (pintype "bidirectional"))
    )
    (net (code "87") (name "CODEC_LINE_IN_L") (class "Default")
      (node (ref "C719") (pin "1") (pinfunction "C1_1") (pintype "passive"))
      (node (ref "U701") (pin "18") (pinfunction "AIN3_18") (pintype "bidirectional"))
    )
    (net (code "88") (name "CODEC_LINE_IN_R") (class "Default")
      (node (ref "C720") (pin "1") (pinfunction "C1_1") (pintype "passive"))
      (node (ref "U701") (pin "16") (pinfunction "AIN2_16") (pintype "bidirectional"))
    )
    (net (code "89") (name "CODEC_MICBIAS0") (class "Default")
      (node (ref "C723") (pin "1") (pinfunction "C1_1") (pintype "passive"))
      (node (ref "R704") (pin "2") (pinfunction "2_2") (pintype "passive"))
      (node (ref "R708") (pin "2") (pinfunction "2_2") (pintype "passive"))
      (node (ref "U701") (pin "6") (pinfunction "MICBIAS0_6") (pintype "bidirectional"))
    )
    (net (code "90") (name "CODEC_MICBIAS1") (class "Default")
      (node (ref "C724") (pin "1") (pinfunction "C1_1") (pintype "passive"))
      (node (ref "R706") (pin "2") (pinfunction "2_2") (pintype "passive"))
      (node (ref "R710") (pin "2") (pinfunction "2_2") (pintype "passive"))
      (node (ref "U701") (pin "7") (pinfunction "MICBIAS1_7") (pintype "bidirectional"))
    )
    (net (code "91") (name "CODEC_MIC_IN_L") (class "Default")
      (node (ref "C717") (pin "1") (pinfunction "C1_1") (pintype "passive"))
      (node (ref "U701") (pin "14") (pinfunction "AIN1_14") (pintype "bidirectional"))
    )
    (net (code "92") (name "CODEC_MIC_IN_R") (class "Default")
      (node (ref "C718") (pin "1") (pinfunction "C1_1") (pintype "passive"))
      (node (ref "U701") (pin "9") (pinfunction "AIN0_9") (pintype "bidirectional"))
    )
    (net (code "93") (name "CODEC_OUT_L") (class "Default")
      (node (ref "C712") (pin "1") (pinfunction "C1_1") (pintype "passive"))
      (node (ref "C713") (pin "1") (pinfunction "C1_1") (pintype "passive"))
      (node (ref "U701") (pin "22") (pinfunction "HPOUTLP/LOUTLP_22") (pintype "bidirectional"))
    )
    (net (code "94") (name "CODEC_OUT_R") (class "Default")
      (node (ref "C714") (pin "1") (pinfunction "C1_1") (pintype "passive"))
      (node (ref "C715") (pin "1") (pinfunction "C1_1") (pintype "passive"))
      (node (ref "U701") (pin "26") (pinfunction "HPOUTRP/LOUTRP_26") (pintype "bidirectional"))
    )
    (net (code "95") (name "DDR3_A0") (class "Default")
      (node (ref "R303") (pin "2") (pinfunction "2_2") (pintype "passive"))
      (node (ref "U201") (pin "W6") (pinfunction "IO_L15P/T2_DQS_W6") (pintype "bidirectional"))
      (node (ref "U301") (pin "N3") (pinfunction "A0_N3") (pintype "bidirectional"))
    )
    (net (code "96") (name "DDR3_A1") (class "Default")
      (node (ref "R312") (pin "2") (pinfunction "2_2") (pintype "passive"))
      (node (ref "U201") (pin "U5") (pinfunction "IO_L14N/T2/SRCC_U5") (pintype "bidirectional"))
      (node (ref "U301") (pin "P7") (pinfunction "A1_P7") (pintype "bidirectional"))
    )
    (net (code "97") (name "DDR3_A2") (class "Default")
      (node (ref "R304") (pin "2") (pinfunction "2_2") (pintype "passive"))
      (node (ref "U201") (pin "T5") (pinfunction "IO_L14P/T2/SRCC_T5") (pintype "bidirectional"))
      (node (ref "U301") (pin "P3") (pinfunction "A2_P3") (pintype "bidirectional"))
    )
    (net (code "98") (name "DDR3_A3") (class "Default")
      (node (ref "R313") (pin "2") (pinfunction "2_2") (pintype "passive"))
      (node (ref "U201") (pin "W4") (pinfunction "IO_L12N/T1/MRCC_W4") (pintype "bidirectional"))
      (node (ref "U301") (pin "N2") (pinfunction "A3_N2") (pintype "bidirectional"))
    )
    (net (code "99") (name "DDR3_A4") (class "Default")
      (node (ref "R305") (pin "2") (pinfunction "2_2") (pintype "passive"))
      (node (ref "U201") (pin "V4") (pinfunction "IO_L12P/T1/MRCC_V4") (pintype "bidirectional"))
      (node (ref "U301") (pin "P8") (pinfunction "A4_P8") (pintype "bidirectional"))
    )
    (net (code "100") (name "DDR3_A5") (class "Default")
      (node (ref "R314") (pin "2") (pinfunction "2_2") (pintype "passive"))
      (node (ref "U201") (pin "AA4") (pinfunction "IO_L11N/T1/SRCC_AA4") (pintype "bidirectional"))
      (node (ref "U301") (pin "P2") (pinfunction "A5_P2") (pintype "bidirectional"))
    )
    (net (code "101") (name "DDR3_A6") (class "Default")
      (node (ref "R306") (pin "2") (pinfunction "2_2") (pintype "passive"))
      (node (ref "U201") (pin "Y4") (pinfunction "IO_L11P/T1/SRCC_Y4") (pintype "bidirectional"))
      (node (ref "U301") (pin "R8") (pinfunction "A6_R8") (pintype "bidirectional"))
    )
    (net (code "102") (name "DDR3_A7") (class "Default")
      (node (ref "R315") (pin "2") (pinfunction "2_2") (pintype "passive"))
      (node (ref "U201") (pin "AB5") (pinfunction "IO_L10N/T1_AB5") (pintype "bidirectional"))
      (node (ref "U301") (pin "R2") (pinfunction "A7_R2") (pintype "bidirectional"))
    )
    (net (code "103") (name "DDR3_A8") (class "Default")
      (node (ref "R307") (pin "2") (pinfunction "2_2") (pintype "passive"))
      (node (ref "U201") (pin "AA5") (pinfunction "IO_L10P/T1_AA5") (pintype "bidirectional"))
      (node (ref "U301") (pin "T8") (pinfunction "A8_T8") (pintype "bidirectional"))
    )
    (net (code "104") (name "DDR3_A9") (class "Default")
      (node (ref "R316") (pin "2") (pinfunction "2_2") (pintype "passive"))
      (node (ref "U201") (pin "AA3") (pinfunction "IO_L9N/T1_DQS_AA3") (pintype "bidirectional"))
      (node (ref "U301") (pin "R3") (pinfunction "A9_R3") (pintype "bidirectional"))
    )
    (net (code "105") (name "DDR3_A10") (class "Default")
      (node (ref "R308") (pin "2") (pinfunction "2_2") (pintype "passive"))
      (node (ref "U201") (pin "Y3") (pinfunction "IO_L9P/T1_DQS_Y3") (pintype "bidirectional"))
      (node (ref "U301") (pin "L7") (pinfunction "A10/AP_L7") (pintype "bidirectional"))
    )
    (net (code "106") (name "DDR3_A11") (class "Default")
      (node (ref "R317") (pin "2") (pinfunction "2_2") (pintype "passive"))
      (node (ref "U201") (pin "AB2") (pinfunction "IO_L8N/T1_AB2") (pintype "bidirectional"))
      (node (ref "U301") (pin "R7") (pinfunction "A11_R7") (pintype "bidirectional"))
    )
    (net (code "107") (name "DDR3_A12") (class "Default")
      (node (ref "R309") (pin "2") (pinfunction "2_2") (pintype "passive"))
      (node (ref "U201") (pin "AB3") (pinfunction "IO_L8P/T1_AB3") (pintype "bidirectional"))
      (node (ref "U301") (pin "N7") (pinfunction "A12/~{BC}_N7") (pintype "bidirectional"))
    )
    (net (code "108") (name "DDR3_A13") (class "Default")
      (node (ref "R318") (pin "2") (pinfunction "2_2") (pintype "passive"))
      (node (ref "U201") (pin "AB1") (pinfunction "IO_L7N/T1_AB1") (pintype "bidirectional"))
      (node (ref "U301") (pin "T3") (pinfunction "A13_T3") (pintype "bidirectional"))
    )
    (net (code "109") (name "DDR3_A14") (class "Default")
      (node (ref "R310") (pin "2") (pinfunction "2_2") (pintype "passive"))
      (node (ref "U201") (pin "AA1") (pinfunction "IO_L7P/T1_AA1") (pintype "bidirectional"))
      (node (ref "U301") (pin "T7") (pinfunction "A14_T7") (pintype "bidirectional"))
    )
    (net (code "110") (name "DDR3_BA0") (class "Default")
      (node (ref "R321") (pin "1") (pinfunction "1_1") (pintype "passive"))
      (node (ref "U201") (pin "V5") (pinfunction "IO_L16N/T2_V5") (pintype "bidirectional"))
      (node (ref "U301") (pin "M2") (pinfunction "BA0_M2") (pintype "bidirectional"))
    )
    (net (code "111") (name "DDR3_BA1") (class "Default")
      (node (ref "R325") (pin "1") (pinfunction "1_1") (pintype "passive"))
      (node (ref "U201") (pin "U6") (pinfunction "IO_L16P/T2_U6") (pintype "bidirectional"))
      (node (ref "U301") (pin "N8") (pinfunction "BA1_N8") (pintype "bidirectional"))
    )
    (net (code "112") (name "DDR3_BA2") (class "Default")
      (node (ref "R320") (pin "1") (pinfunction "1_1") (pintype "passive"))
      (node (ref "U201") (pin "W5") (pinfunction "IO_L15N/T2_DQS_W5") (pintype "bidirectional"))
      (node (ref "U301") (pin "M3") (pinfunction "BA2_M3") (pintype "bidirectional"))
    )
    (net (code "113") (name "DDR3_CLK_EN") (class "Default")
      (node (ref "R328") (pin "1") (pinfunction "1_1") (pintype "passive"))
      (node (ref "U201") (pin "AA6") (pinfunction "IO_L18N/T2_AA6") (pintype "bidirectional"))
      (node (ref "U301") (pin "K9") (pinfunction "CKE_K9") (pintype "bidirectional"))
    )
    (net (code "114") (name "DDR3_CLK_N") (class "Default")
      (node (ref "R319") (pin "1") (pinfunction "1_1") (pintype "passive"))
      (node (ref "U201") (pin "V8") (pinfunction "IO_L21N/T3_DQS_V8") (pintype "bidirectional"))
      (node (ref "U301") (pin "K7") (pinfunction "~{CK}_K7") (pintype "bidirectional"))
    )
    (net (code "115") (name "DDR3_CLK_P") (class "Default")
      (node (ref "R311") (pin "2") (pinfunction "2_2") (pintype "passive"))
      (node (ref "U201") (pin "V9") (pinfunction "IO_L21P/T3_DQS_V9") (pintype "bidirectional"))
      (node (ref "U301") (pin "J7") (pinfunction "CK_J7") (pintype "bidirectional"))
    )
    (net (code "116") (name "DDR3_DM0") (class "Default")
      (node (ref "U201") (pin "N4") (pinfunction "IO_L19P/T3_N4") (pintype "bidirectional"))
      (node (ref "U301") (pin "E7") (pinfunction "LDM_E7") (pintype "bidirectional"))
    )
    (net (code "117") (name "DDR3_DM1") (class "Default")
      (node (ref "U201") (pin "T1") (pinfunction "IO_L1P/T0_T1") (pintype "bidirectional"))
      (node (ref "U301") (pin "D3") (pinfunction "UDM_D3") (pintype "bidirectional"))
    )
    (net (code "118") (name "DDR3_DQ0") (class "Default")
      (node (ref "U201") (pin "R1") (pinfunction "IO_L20P/T3_R1") (pintype "bidirectional"))
      (node (ref "U301") (pin "E3") (pinfunction "DQ0_E3") (pintype "bidirectional"))
    )
    (net (code "119") (name "DDR3_DQ1") (class "Default")
      (node (ref "U201") (pin "P1") (pinfunction "IO_L20N/T3_P1") (pintype "bidirectional"))
      (node (ref "U301") (pin "F7") (pinfunction "DQ1_F7") (pintype "bidirectional"))
    )
    (net (code "120") (name "DDR3_DQ2") (class "Default")
      (node (ref "U201") (pin "P2") (pinfunction "IO_L22P/T3_P2") (pintype "bidirectional"))
      (node (ref "U301") (pin "F2") (pinfunction "DQ2_F2") (pintype "bidirectional"))
    )
    (net (code "121") (name "DDR3_DQ3") (class "Default")
      (node (ref "U201") (pin "N2") (pinfunction "IO_L22N/T3_N2") (pintype "bidirectional"))
      (node (ref "U301") (pin "F8") (pinfunction "DQ3_F8") (pintype "bidirectional"))
    )
    (net (code "122") (name "DDR3_DQ4") (class "Default")
      (node (ref "U201") (pin "M6") (pinfunction "IO_L23P/T3_M6") (pintype "bidirectional"))
      (node (ref "U301") (pin "H3") (pinfunction "DQ4_H3") (pintype "bidirectional"))
    )
    (net (code "123") (name "DDR3_DQ5") (class "Default")
      (node (ref "U201") (pin "M5") (pinfunction "IO_L23N/T3_M5") (pintype "bidirectional"))
      (node (ref "U301") (pin "H8") (pinfunction "DQ5_H8") (pintype "bidirectional"))
    )
    (net (code "124") (name "DDR3_DQ6") (class "Default")
      (node (ref "U201") (pin "P6") (pinfunction "IO_L24P/T3_P6") (pintype "bidirectional"))
      (node (ref "U301") (pin "G2") (pinfunction "DQ6_G2") (pintype "bidirectional"))
    )
    (net (code "125") (name "DDR3_DQ7") (class "Default")
      (node (ref "U201") (pin "N5") (pinfunction "IO_L24N/T3_N5") (pintype "bidirectional"))
      (node (ref "U301") (pin "H7") (pinfunction "DQ7_H7") (pintype "bidirectional"))
    )
    (net (code "126") (name "DDR3_DQ8") (class "Default")
      (node (ref "U201") (pin "U1") (pinfunction "IO_L1N/T0_U1") (pintype "bidirectional"))
      (node (ref "U301") (pin "D7") (pinfunction "DQ8_D7") (pintype "bidirectional"))
    )
    (net (code "127") (name "DDR3_DQ9") (class "Default")
      (node (ref "U201") (pin "U2") (pinfunction "IO_L2P/T0_U2") (pintype "bidirectional"))
      (node (ref "U301") (pin "C3") (pinfunction "DQ9_C3") (pintype "bidirectional"))
    )
    (net (code "128") (name "DDR3_DQ10") (class "Default")
      (node (ref "U201") (pin "V2") (pinfunction "IO_L2N/T0_V2") (pintype "bidirectional"))
      (node (ref "U301") (pin "C8") (pinfunction "DQ10_C8") (pintype "bidirectional"))
    )
    (net (code "129") (name "DDR3_DQ11") (class "Default")
      (node (ref "U201") (pin "W2") (pinfunction "IO_L4P/T0_W2") (pintype "bidirectional"))
      (node (ref "U301") (pin "C2") (pinfunction "DQ11_C2") (pintype "bidirectional"))
    )
    (net (code "130") (name "DDR3_DQ12") (class "Default")
      (node (ref "U201") (pin "Y2") (pinfunction "IO_L4N/T0_Y2") (pintype "bidirectional"))
      (node (ref "U301") (pin "A7") (pinfunction "DQ12_A7") (pintype "bidirectional"))
    )
    (net (code "131") (name "DDR3_DQ13") (class "Default")
      (node (ref "U201") (pin "W1") (pinfunction "IO_L5P/T0_W1") (pintype "bidirectional"))
      (node (ref "U301") (pin "A2") (pinfunction "DQ13_A2") (pintype "bidirectional"))
    )
    (net (code "132") (name "DDR3_DQ14") (class "Default")
      (node (ref "U201") (pin "Y1") (pinfunction "IO_L5N/T0_Y1") (pintype "bidirectional"))
      (node (ref "U301") (pin "B8") (pinfunction "DQ14_B8") (pintype "bidirectional"))
    )
    (net (code "133") (name "DDR3_DQ15") (class "Default")
      (node (ref "U201") (pin "U3") (pinfunction "IO_L6P/T0_U3") (pintype "bidirectional"))
      (node (ref "U301") (pin "A3") (pinfunction "DQ15_A3") (pintype "bidirectional"))
    )
    (net (code "134") (name "DDR3_DQS0_N") (class "Default")
      (node (ref "U201") (pin "P4") (pinfunction "IO_L21N/T3_DQS_P4") (pintype "bidirectional"))
      (node (ref "U301") (pin "G3") (pinfunction "~{LDQS}_G3") (pintype "bidirectional"))
    )
    (net (code "135") (name "DDR3_DQS0_P") (class "Default")
      (node (ref "U201") (pin "P5") (pinfunction "IO_L21P/T3_DQS_P5") (pintype "bidirectional"))
      (node (ref "U301") (pin "F3") (pinfunction "LDQS_F3") (pintype "bidirectional"))
    )
    (net (code "136") (name "DDR3_DQS1_N") (class "Default")
      (node (ref "U201") (pin "R2") (pinfunction "IO_L3N/T0_DQS_R2") (pintype "bidirectional"))
      (node (ref "U301") (pin "B7") (pinfunction "~{UDQS}_B7") (pintype "bidirectional"))
    )
    (net (code "137") (name "DDR3_DQS1_P") (class "Default")
      (node (ref "U201") (pin "R3") (pinfunction "IO_L3P/T0_DQS_R3") (pintype "bidirectional"))
      (node (ref "U301") (pin "C7") (pinfunction "UDQS_C7") (pintype "bidirectional"))
    )
    (net (code "138") (name "DDR3_ODT") (class "Default")
      (node (ref "R326") (pin "1") (pinfunction "1_1") (pintype "passive"))
      (node (ref "U201") (pin "V7") (pinfunction "IO_L19P/T3_V7") (pintype "bidirectional"))
      (node (ref "U301") (pin "K1") (pinfunction "ODT_K1") (pintype "bidirectional"))
    )
    (net (code "139") (name "ETH_ACT_LED") (class "Default")
      (node (ref "J101") (pin "12") (pinfunction "C_12") (pintype "passive"))
      (node (ref "U102") (pin "17") (pinfunction "~{ETH_LED2}_17") (pintype "bidirectional"))
    )
    (net (code "140") (name "ETH_LINK_LED") (class "Default")
      (node (ref "J101") (pin "14") (pinfunction "C_14") (pintype "passive"))
      (node (ref "U102") (pin "15") (pinfunction "~{ETH_LED3}_15") (pintype "bidirectional"))
    )
    (net (code "141") (name "ETH_P0_N") (class "Default")
      (node (ref "J101") (pin "3") (pinfunction "P0-_3") (pintype "bidirectional"))
      (node (ref "U102") (pin "10") (pinfunction "ETH_P0N_10") (pintype "bidirectional"))
    )
    (net (code "142") (name "ETH_P0_P") (class "Default")
      (node (ref "J101") (pin "2") (pinfunction "P0+_2") (pintype "bidirectional"))
      (node (ref "U102") (pin "12") (pinfunction "ETH_P0P_12") (pintype "bidirectional"))
    )
    (net (code "143") (name "ETH_P1_N") (class "Default")
      (node (ref "J101") (pin "7") (pinfunction "P1-_7") (pintype "bidirectional"))
      (node (ref "U102") (pin "6") (pinfunction "ETH_P1N_6") (pintype "bidirectional"))
    )
    (net (code "144") (name "ETH_P1_P") (class "Default")
      (node (ref "J101") (pin "4") (pinfunction "P1+_4") (pintype "bidirectional"))
      (node (ref "U102") (pin "4") (pinfunction "ETH_P1P_4") (pintype "bidirectional"))
    )
    (net (code "145") (name "ETH_P2_N") (class "Default")
      (node (ref "J101") (pin "6") (pinfunction "P2-_6") (pintype "bidirectional"))
      (node (ref "U102") (pin "9") (pinfunction "ETH_P2N_9") (pintype "bidirectional"))
    )
    (net (code "146") (name "ETH_P2_P") (class "Default")
      (node (ref "J101") (pin "5") (pinfunction "P2+_5") (pintype "bidirectional"))
      (node (ref "U102") (pin "11") (pinfunction "ETH_P2P_11") (pintype "bidirectional"))
    )
    (net (code "147") (name "ETH_P3_N") (class "Default")
      (node (ref "J101") (pin "9") (pinfunction "P3-_9") (pintype "bidirectional"))
      (node (ref "U102") (pin "5") (pinfunction "ETH_P3N_5") (pintype "bidirectional"))
    )
    (net (code "148") (name "ETH_P3_P") (class "Default")
      (node (ref "J101") (pin "8") (pinfunction "P3+_8") (pintype "bidirectional"))
      (node (ref "U102") (pin "3") (pinfunction "ETH_P3P_3") (pintype "bidirectional"))
    )
    (net (code "149") (name "EXT_CLK_2_3") (class "Default")
      (node (ref "JP201") (pin "3") (pinfunction "S_3") (pintype "passive"))
      (node (ref "R909") (pin "1") (pinfunction "1_1") (pintype "passive"))
    )
    (net (code "150") (name "EXT_CLK_OUT") (class "Default")
      (node (ref "R913") (pin "1") (pinfunction "1_1") (pintype "passive"))
      (node (ref "RFCON902") (pin "P$3") (pinfunction "SIGNAL_P$3") (pintype "bidirectional"))
    )
    (net (code "151") (name "EXT_IO_1_1") (class "Default")
      (node (ref "R211") (pin "2") (pinfunction "2_2") (pintype "passive"))
      (node (ref "U201") (pin "AA9") (pinfunction "IO_L8P/T1_AA9") (pintype "bidirectional"))
    )
    (net (code "152") (name "EXT_IO_1_2") (class "Default")
      (node (ref "R208") (pin "2") (pinfunction "2_2") (pintype "passive"))
      (node (ref "U201") (pin "AA11") (pinfunction "IO_L9N/T1_DQS_AA11") (pintype "bidirectional"))
    )
    (net (code "153") (name "EXT_IO_1_3") (class "Default")
      (node (ref "R212") (pin "2") (pinfunction "2_2") (pintype "passive"))
      (node (ref "U201") (pin "AB10") (pinfunction "IO_L8N/T1_AB10") (pintype "bidirectional"))
    )
    (net (code "154") (name "EXT_IO_1_4") (class "Default")
      (node (ref "R209") (pin "2") (pinfunction "2_2") (pintype "passive"))
      (node (ref "U201") (pin "AB11") (pinfunction "IO_L7P/T1_AB11") (pintype "bidirectional"))
    )
    (net (code "155") (name "EXT_IO_1_5") (class "Default")
      (node (ref "R213") (pin "2") (pinfunction "2_2") (pintype "passive"))
      (node (ref "U201") (pin "AA10") (pinfunction "IO_L9P/T1_DQS_AA10") (pintype "bidirectional"))
    )
    (net (code "156") (name "EXT_IO_2_2") (class "Default")
      (node (ref "R203") (pin "2") (pinfunction "2_2") (pintype "passive"))
      (node (ref "U201") (pin "A16") (pinfunction "IO_L9N/T1_DQS_A16") (pintype "bidirectional"))
    )
    (net (code "157") (name "EXT_IO_2_4") (class "Default")
      (node (ref "R204") (pin "2") (pinfunction "2_2") (pintype "passive"))
      (node (ref "U201") (pin "A15") (pinfunction "IO_L9P/T1_DQS_A15") (pintype "bidirectional"))
    )
    (net (code "158") (name "EXT_IO_2_6") (class "Default")
      (node (ref "R206") (pin "2") (pinfunction "2_2") (pintype "passive"))
      (node (ref "U201") (pin "A14") (pinfunction "IO_L10N/T1_A14") (pintype "bidirectional"))
    )
    (net (code "159") (name "FPGA_CLK0") (class "Default")
      (node (ref "R907") (pin "1") (pinfunction "1_1") (pintype "passive"))
      (node (ref "U201") (pin "W11") (pinfunction "IO_L12P/T1/MRCC_W11") (pintype "bidirectional"))
    )
    (net (code "160") (name "FPGA_CLK1") (class "Default")
      (node (ref "R911") (pin "1") (pinfunction "1_1") (pintype "passive"))
      (node (ref "U201") (pin "V13") (pinfunction "IO_L13P/T2/MRCC_V13") (pintype "bidirectional"))
    )
    (net (code "161") (name "FPGA_CLK2") (class "Default")
      (node (ref "R906") (pin "1") (pinfunction "1_1") (pintype "passive"))
      (node (ref "U201") (pin "W19") (pinfunction "IO_L12P/T1/MRCC_W19") (pintype "bidirectional"))
    )
    (net (code "162") (name "FPGA_CLK3") (class "Default")
      (node (ref "R910") (pin "1") (pinfunction "1_1") (pintype "passive"))
      (node (ref "U201") (pin "Y18") (pinfunction "IO_L13P/T2/MRCC_Y18") (pintype "bidirectional"))
    )
    (net (code "163") (name "FPGA_DONE") (class "Default")
      (node (ref "D202") (pin "A") (pinfunction "A_A") (pintype "passive"))
      (node (ref "R222") (pin "1") (pinfunction "1_1") (pintype "passive"))
      (node (ref "U201") (pin "G11") (pinfunction "DONE_G11") (pintype "bidirectional"))
    )
    (net (code "164") (name "FPGA_FLASH_IO0") (class "Default")
      (node (ref "U201") (pin "P22") (pinfunction "IO_L1P/T0/D0/MOSI_P22") (pintype "bidirectional"))
      (node (ref "U202") (pin "5") (pinfunction "MOSI/IO0_5") (pintype "input"))
    )
    (net (code "165") (name "FPGA_FLASH_IO1") (class "Default")
      (node (ref "U201") (pin "R22") (pinfunction "IO_L1N/T0/D1/DIN_R22") (pintype "bidirectional"))
      (node (ref "U202") (pin "2") (pinfunction "MISO/IO1_2") (pintype "output"))
    )
    (net (code "166") (name "FPGA_FLASH_IO2") (class "Default")
      (node (ref "R217") (pin "1") (pinfunction "1_1") (pintype "passive"))
      (node (ref "U201") (pin "P21") (pinfunction "IO_L2P/T0/D2_P21") (pintype "bidirectional"))
      (node (ref "U202") (pin "3") (pinfunction "~{WP}/IO2_3") (pintype "input"))
    )
    (net (code "167") (name "FPGA_FLASH_IO3") (class "Default")
      (node (ref "R218") (pin "1") (pinfunction "1_1") (pintype "passive"))
      (node (ref "U201") (pin "R21") (pinfunction "IO_L2N/T0/D3_R21") (pintype "bidirectional"))
      (node (ref "U202") (pin "7") (pinfunction "~{HOLD}/IO3_7") (pintype "input"))
    )
    (net (code "168") (name "FPGA_FLASH_SCK") (class "Default")
      (node (ref "U201") (pin "L12") (pinfunction "CCLK_L12") (pintype "bidirectional"))
      (node (ref "U201") (pin "N13") (pinfunction "IO_L23P/T3/A3/D19_N13") (pintype "bidirectional"))
      (node (ref "U202") (pin "6") (pinfunction "SCK_6") (pintype "input"))
    )
    (net (code "169") (name "FPGA_JTAG_EN") (class "Default")
      (node (ref "R216") (pin "2") (pinfunction "2_2") (pintype "passive"))
      (node (ref "TC201") (pin "10") (pinfunction "S_10") (pintype "passive"))
      (node (ref "U201") (pin "U9") (pinfunction "M2_U9") (pintype "bidirectional"))
    )
    (net (code "170") (name "FPGA_TCK") (class "Default")
      (node (ref "TC201") (pin "4") (pinfunction "S_4") (pintype "passive"))
      (node (ref "U201") (pin "V12") (pinfunction "TCK_V12") (pintype "bidirectional"))
    )
    (net (code "171") (name "FPGA_TDI") (class "Default")
      (node (ref "R220") (pin "1") (pinfunction "1_1") (pintype "passive"))
      (node (ref "TC201") (pin "8") (pinfunction "S_8") (pintype "passive"))
      (node (ref "U201") (pin "R13") (pinfunction "TDI_R13") (pintype "bidirectional"))
    )
    (net (code "172") (name "FPGA_TDO") (class "Default")
      (node (ref "TC201") (pin "6") (pinfunction "S_6") (pintype "passive"))
      (node (ref "U201") (pin "U13") (pinfunction "TDO_U13") (pintype "bidirectional"))
    )
    (net (code "173") (name "FPGA_TMS") (class "Default")
      (node (ref "R221") (pin "1") (pinfunction "1_1") (pintype "passive"))
      (node (ref "TC201") (pin "2") (pinfunction "S_2") (pintype "passive"))
      (node (ref "U201") (pin "T13") (pinfunction "TMS_T13") (pintype "bidirectional"))
    )
    (net (code "174") (name "GND") (class "Default")
      (node (ref "C1001") (pin "2") (pinfunction "C2_2") (pintype "passive"))
      (node (ref "C1002") (pin "2") (pinfunction "C2_2") (pintype "passive"))
      (node (ref "C1003") (pin "2") (pinfunction "C2_2") (pintype "passive"))
      (node (ref "C1004") (pin "2") (pinfunction "C2_2") (pintype "passive"))
      (node (ref "C1005") (pin "2") (pinfunction "C2_2") (pintype "passive"))
      (node (ref "C1006") (pin "2") (pinfunction "C2_2") (pintype "passive"))
      (node (ref "C1007") (pin "2") (pinfunction "C2_2") (pintype "passive"))
      (node (ref "C1008") (pin "2") (pinfunction "C2_2") (pintype "passive"))
      (node (ref "C1009") (pin "2") (pinfunction "C2_2") (pintype "passive"))
      (node (ref "C101") (pin "2") (pinfunction "C2_2") (pintype "passive"))
      (node (ref "C1010") (pin "2") (pinfunction "C2_2") (pintype "passive"))
      (node (ref "C1011") (pin "2") (pinfunction "C2_2") (pintype "passive"))
      (node (ref "C1012") (pin "2") (pinfunction "C2_2") (pintype "passive"))
      (node (ref "C1013") (pin "2") (pinfunction "C2_2") (pintype "passive"))
      (node (ref "C1014") (pin "2") (pinfunction "C2_2") (pintype "passive"))
      (node (ref "C102") (pin "2") (pinfunction "C2_2") (pintype "passive"))
      (node (ref "C103") (pin "2") (pinfunction "C2_2") (pintype "passive"))
      (node (ref "C104") (pin "2") (pinfunction "C2_2") (pintype "passive"))
      (node (ref "C105") (pin "2") (pinfunction "C2_2") (pintype "passive"))
      (node (ref "C106") (pin "2") (pinfunction "C2_2") (pintype "passive"))
      (node (ref "C107") (pin "2") (pinfunction "C2_2") (pintype "passive"))
      (node (ref "C108") (pin "2") (pinfunction "C2_2") (pintype "passive"))
      (node (ref "C1101") (pin "2") (pinfunction "C2_2") (pintype "passive"))
      (node (ref "C1102") (pin "2") (pinfunction "C2_2") (pintype "passive"))
      (node (ref "C1103") (pin "2") (pinfunction "C2_2") (pintype "passive"))
      (node (ref "C1104") (pin "2") (pinfunction "C2_2") (pintype "passive"))
      (node (ref "C1105") (pin "2") (pinfunction "C2_2") (pintype "passive"))
      (node (ref "C1106") (pin "2") (pinfunction "C2_2") (pintype "passive"))
      (node (ref "C1107") (pin "2") (pinfunction "C2_2") (pintype "passive"))
      (node (ref "C1108") (pin "2") (pinfunction "C2_2") (pintype "passive"))
      (node (ref "C1109") (pin "2") (pinfunction "C2_2") (pintype "passive"))
      (node (ref "C1110") (pin "2") (pinfunction "C2_2") (pintype "passive"))
      (node (ref "C1111") (pin "2") (pinfunction "C2_2") (pintype "passive"))
      (node (ref "C1112") (pin "2") (pinfunction "C2_2") (pintype "passive"))
      (node (ref "C1113") (pin "2") (pinfunction "C2_2") (pintype "passive"))
      (node (ref "C1114") (pin "2") (pinfunction "C2_2") (pintype "passive"))
      (node (ref "C1115") (pin "2") (pinfunction "C2_2") (pintype "passive"))
      (node (ref "C1116") (pin "2") (pinfunction "C2_2") (pintype "passive"))
      (node (ref "C1117") (pin "2") (pinfunction "C2_2") (pintype "passive"))
      (node (ref "C1118") (pin "2") (pinfunction "C2_2") (pintype "passive"))
      (node (ref "C1119") (pin "2") (pinfunction "C2_2") (pintype "passive"))
      (node (ref "C1122") (pin "2") (pinfunction "C2_2") (pintype "passive"))
      (node (ref "C1123") (pin "2") (pinfunction "C2_2") (pintype "passive"))
      (node (ref "C1124") (pin "2") (pinfunction "C2_2") (pintype "passive"))
      (node (ref "C1125") (pin "2") (pinfunction "C2_2") (pintype "passive"))
      (node (ref "C1126") (pin "2") (pinfunction "C2_2") (pintype "passive"))
      (node (ref "C1127") (pin "2") (pinfunction "C2_2") (pintype "passive"))
      (node (ref "C1128") (pin "2") (pinfunction "C2_2") (pintype "passive"))
      (node (ref "C1129") (pin "2") (pinfunction "C2_2") (pintype "passive"))
      (node (ref "C1130") (pin "2") (pinfunction "C2_2") (pintype "passive"))
      (node (ref "C1201") (pin "2") (pinfunction "C2_2") (pintype "passive"))
      (node (ref "C1202") (pin "2") (pinfunction "C2_2") (pintype "passive"))
      (node (ref "C1203") (pin "2") (pinfunction "C2_2") (pintype "passive"))
      (node (ref "C1204") (pin "2") (pinfunction "C2_2") (pintype "passive"))
      (node (ref "C1205") (pin "2") (pinfunction "C2_2") (pintype "passive"))
      (node (ref "C1206") (pin "2") (pinfunction "C2_2") (pintype "passive"))
      (node (ref "C1207") (pin "2") (pinfunction "C2_2") (pintype "passive"))
      (node (ref "C1208") (pin "2") (pinfunction "C2_2") (pintype "passive"))
      (node (ref "C1209") (pin "2") (pinfunction "C2_2") (pintype "passive"))
      (node (ref "C1210") (pin "2") (pinfunction "C2_2") (pintype "passive"))
      (node (ref "C1211") (pin "2") (pinfunction "C2_2") (pintype "passive"))
      (node (ref "C1212") (pin "2") (pinfunction "C2_2") (pintype "passive"))
      (node (ref "C1213") (pin "2") (pinfunction "C2_2") (pintype "passive"))
      (node (ref "C1214") (pin "2") (pinfunction "C2_2") (pintype "passive"))
      (node (ref "C1215") (pin "2") (pinfunction "C2_2") (pintype "passive"))
      (node (ref "C1216") (pin "2") (pinfunction "C2_2") (pintype "passive"))
      (node (ref "C1217") (pin "2") (pinfunction "C2_2") (pintype "passive"))
      (node (ref "C1218") (pin "2") (pinfunction "C2_2") (pintype "passive"))
      (node (ref "C1219") (pin "2") (pinfunction "C2_2") (pintype "passive"))
      (node (ref "C1220") (pin "2") (pinfunction "C2_2") (pintype "passive"))
      (node (ref "C1221") (pin "2") (pinfunction "C2_2") (pintype "passive"))
      (node (ref "C1222") (pin "2") (pinfunction "C2_2") (pintype "passive"))
      (node (ref "C1223") (pin "2") (pinfunction "C2_2") (pintype "passive"))
      (node (ref "C1224") (pin "2") (pinfunction "C2_2") (pintype "passive"))
      (node (ref "C1225") (pin "2") (pinfunction "C2_2") (pintype "passive"))
      (node (ref "C1226") (pin "2") (pinfunction "C2_2") (pintype "passive"))
      (node (ref "C1227") (pin "2") (pinfunction "C2_2") (pintype "passive"))
      (node (ref "C1228") (pin "2") (pinfunction "C2_2") (pintype "passive"))
      (node (ref "C1229") (pin "2") (pinfunction "C2_2") (pintype "passive"))
      (node (ref "C1230") (pin "2") (pinfunction "C2_2") (pintype "passive"))
      (node (ref "C1231") (pin "2") (pinfunction "C2_2") (pintype "passive"))
      (node (ref "C1232") (pin "2") (pinfunction "C2_2") (pintype "passive"))
      (node (ref "C1233") (pin "2") (pinfunction "C2_2") (pintype "passive"))
      (node (ref "C1234") (pin "2") (pinfunction "C2_2") (pintype "passive"))
      (node (ref "C1235") (pin "2") (pinfunction "C2_2") (pintype "passive"))
      (node (ref "C1236") (pin "2") (pinfunction "C2_2") (pintype "passive"))
      (node (ref "C1237") (pin "2") (pinfunction "C2_2") (pintype "passive"))
      (node (ref "C1238") (pin "2") (pinfunction "C2_2") (pintype "passive"))
      (node (ref "C1239") (pin "2") (pinfunction "C2_2") (pintype "passive"))
      (node (ref "C1240") (pin "2") (pinfunction "C2_2") (pintype "passive"))
      (node (ref "C1241") (pin "2") (pinfunction "C2_2") (pintype "passive"))
      (node (ref "C1242") (pin "2") (pinfunction "C2_2") (pintype "passive"))
      (node (ref "C1243") (pin "2") (pinfunction "C2_2") (pintype "passive"))
      (node (ref "C1244") (pin "2") (pinfunction "C2_2") (pintype "passive"))
      (node (ref "C1245") (pin "2") (pinfunction "C2_2") (pintype "passive"))
      (node (ref "C1246") (pin "2") (pinfunction "C2_2") (pintype "passive"))
      (node (ref "C1247") (pin "2") (pinfunction "C2_2") (pintype "passive"))
      (node (ref "C1248") (pin "2") (pinfunction "C2_2") (pintype "passive"))
      (node (ref "C1249") (pin "2") (pinfunction "C2_2") (pintype "passive"))
      (node (ref "C1250") (pin "2") (pinfunction "C2_2") (pintype "passive"))
      (node (ref "C1251") (pin "2") (pinfunction "C2_2") (pintype "passive"))
      (node (ref "C1252") (pin "2") (pinfunction "C2_2") (pintype "passive"))
      (node (ref "C1253") (pin "2") (pinfunction "C2_2") (pintype "passive"))
      (node (ref "C1254") (pin "2") (pinfunction "C2_2") (pintype "passive"))
      (node (ref "C1255") (pin "2") (pinfunction "C2_2") (pintype "passive"))
      (node (ref "C1256") (pin "2") (pinfunction "C2_2") (pintype "passive"))
      (node (ref "C1257") (pin "2") (pinfunction "C2_2") (pintype "passive"))
      (node (ref "C1258") (pin "2") (pinfunction "C2_2") (pintype "passive"))
      (node (ref "C1259") (pin "2") (pinfunction "C2_2") (pintype "passive"))
      (node (ref "C201") (pin "2") (pinfunction "C2_2") (pintype "passive"))
      (node (ref "C202") (pin "2") (pinfunction "C2_2") (pintype "passive"))
      (node (ref "C203") (pin "2") (pinfunction "C2_2") (pintype "passive"))
      (node (ref "C204") (pin "2") (pinfunction "C2_2") (pintype "passive"))
      (node (ref "C205") (pin "2") (pinfunction "C2_2") (pintype "passive"))
      (node (ref "C206") (pin "2") (pinfunction "C2_2") (pintype "passive"))
      (node (ref "C207") (pin "2") (pinfunction "C2_2") (pintype "passive"))
      (node (ref "C208") (pin "2") (pinfunction "C2_2") (pintype "passive"))
      (node (ref "C209") (pin "2") (pinfunction "C2_2") (pintype "passive"))
      (node (ref "C210") (pin "2") (pinfunction "C2_2") (pintype "passive"))
      (node (ref "C211") (pin "2") (pinfunction "C2_2") (pintype "passive"))
      (node (ref "C212") (pin "2") (pinfunction "C2_2") (pintype "passive"))
      (node (ref "C213") (pin "2") (pinfunction "C2_2") (pintype "passive"))
      (node (ref "C214") (pin "2") (pinfunction "C2_2") (pintype "passive"))
      (node (ref "C215") (pin "2") (pinfunction "C2_2") (pintype "passive"))
      (node (ref "C216") (pin "2") (pinfunction "C2_2") (pintype "passive"))
      (node (ref "C217") (pin "2") (pinfunction "C2_2") (pintype "passive"))
      (node (ref "C218") (pin "2") (pinfunction "C2_2") (pintype "passive"))
      (node (ref "C219") (pin "2") (pinfunction "C2_2") (pintype "passive"))
      (node (ref "C220") (pin "2") (pinfunction "C2_2") (pintype "passive"))
      (node (ref "C221") (pin "2") (pinfunction "C2_2") (pintype "passive"))
      (node (ref "C222") (pin "2") (pinfunction "C2_2") (pintype "passive"))
      (node (ref "C223") (pin "2") (pinfunction "C2_2") (pintype "passive"))
      (node (ref "C224") (pin "2") (pinfunction "C2_2") (pintype "passive"))
      (node (ref "C225") (pin "2") (pinfunction "C2_2") (pintype "passive"))
      (node (ref "C226") (pin "2") (pinfunction "C2_2") (pintype "passive"))
      (node (ref "C227") (pin "2") (pinfunction "C2_2") (pintype "passive"))
      (node (ref "C228") (pin "2") (pinfunction "C2_2") (pintype "passive"))
      (node (ref "C229") (pin "2") (pinfunction "C2_2") (pintype "passive"))
      (node (ref "C230") (pin "2") (pinfunction "C2_2") (pintype "passive"))
      (node (ref "C231") (pin "2") (pinfunction "C2_2") (pintype "passive"))
      (node (ref "C232") (pin "2") (pinfunction "C2_2") (pintype "passive"))
      (node (ref "C233") (pin "2") (pinfunction "C2_2") (pintype "passive"))
      (node (ref "C234") (pin "2") (pinfunction "C2_2") (pintype "passive"))
      (node (ref "C235") (pin "2") (pinfunction "C2_2") (pintype "passive"))
      (node (ref "C236") (pin "2") (pinfunction "C2_2") (pintype "passive"))
      (node (ref "C237") (pin "2") (pinfunction "C2_2") (pintype "passive"))
      (node (ref "C238") (pin "2") (pinfunction "C2_2") (pintype "passive"))
      (node (ref "C239") (pin "2") (pinfunction "C2_2") (pintype "passive"))
      (node (ref "C240") (pin "2") (pinfunction "C2_2") (pintype "passive"))
      (node (ref "C241") (pin "2") (pinfunction "C2_2") (pintype "passive"))
      (node (ref "C242") (pin "2") (pinfunction "C2_2") (pintype "passive"))
      (node (ref "C243") (pin "2") (pinfunction "C2_2") (pintype "passive"))
      (node (ref "C244") (pin "2") (pinfunction "C2_2") (pintype "passive"))
      (node (ref "C245") (pin "2") (pinfunction "C2_2") (pintype "passive"))
      (node (ref "C246") (pin "2") (pinfunction "C2_2") (pintype "passive"))
      (node (ref "C247") (pin "2") (pinfunction "C2_2") (pintype "passive"))
      (node (ref "C248") (pin "2") (pinfunction "C2_2") (pintype "passive"))
      (node (ref "C249") (pin "2") (pinfunction "C2_2") (pintype "passive"))
      (node (ref "C250") (pin "2") (pinfunction "C2_2") (pintype "passive"))
      (node (ref "C251") (pin "2") (pinfunction "C2_2") (pintype "passive"))
      (node (ref "C252") (pin "2") (pinfunction "C2_2") (pintype "passive"))
      (node (ref "C253") (pin "2") (pinfunction "C2_2") (pintype "passive"))
      (node (ref "C254") (pin "2") (pinfunction "C2_2") (pintype "passive"))
      (node (ref "C255") (pin "2") (pinfunction "C2_2") (pintype "passive"))
      (node (ref "C256") (pin "2") (pinfunction "C2_2") (pintype "passive"))
      (node (ref "C257") (pin "2") (pinfunction "C2_2") (pintype "passive"))
      (node (ref "C258") (pin "2") (pinfunction "C2_2") (pintype "passive"))
      (node (ref "C259") (pin "2") (pinfunction "C2_2") (pintype "passive"))
      (node (ref "C260") (pin "2") (pinfunction "C2_2") (pintype "passive"))
      (node (ref "C261") (pin "2") (pinfunction "C2_2") (pintype "passive"))
      (node (ref "C262") (pin "2") (pinfunction "C2_2") (pintype "passive"))
      (node (ref "C263") (pin "2") (pinfunction "C2_2") (pintype "passive"))
      (node (ref "C264") (pin "2") (pinfunction "C2_2") (pintype "passive"))
      (node (ref "C301") (pin "2") (pinfunction "C2_2") (pintype "passive"))
      (node (ref "C302") (pin "2") (pinfunction "C2_2") (pintype "passive"))
      (node (ref "C303") (pin "2") (pinfunction "C2_2") (pintype "passive"))
      (node (ref "C304") (pin "2") (pinfunction "C2_2") (pintype "passive"))
      (node (ref "C305") (pin "2") (pinfunction "C2_2") (pintype "passive"))
      (node (ref "C306") (pin "2") (pinfunction "C2_2") (pintype "passive"))
      (node (ref "C307") (pin "2") (pinfunction "C2_2") (pintype "passive"))
      (node (ref "C308") (pin "2") (pinfunction "C2_2") (pintype "passive"))
      (node (ref "C309") (pin "2") (pinfunction "C2_2") (pintype "passive"))
      (node (ref "C310") (pin "2") (pinfunction "C2_2") (pintype "passive"))
      (node (ref "C311") (pin "2") (pinfunction "C2_2") (pintype "passive"))
      (node (ref "C312") (pin "2") (pinfunction "C2_2") (pintype "passive"))
      (node (ref "C313") (pin "2") (pinfunction "C2_2") (pintype "passive"))
      (node (ref "C314") (pin "2") (pinfunction "C2_2") (pintype "passive"))
      (node (ref "C315") (pin "2") (pinfunction "C2_2") (pintype "passive"))
      (node (ref "C316") (pin "2") (pinfunction "C2_2") (pintype "passive"))
      (node (ref "C317") (pin "2") (pinfunction "C2_2") (pintype "passive"))
      (node (ref "C318") (pin "2") (pinfunction "C2_2") (pintype "passive"))
      (node (ref "C319") (pin "2") (pinfunction "C2_2") (pintype "passive"))
      (node (ref "C320") (pin "2") (pinfunction "C2_2") (pintype "passive"))
      (node (ref "C321") (pin "2") (pinfunction "C2_2") (pintype "passive"))
      (node (ref "C322") (pin "2") (pinfunction "C2_2") (pintype "passive"))
      (node (ref "C324") (pin "2") (pinfunction "C2_2") (pintype "passive"))
      (node (ref "C325") (pin "2") (pinfunction "C2_2") (pintype "passive"))
      (node (ref "C326") (pin "2") (pinfunction "C2_2") (pintype "passive"))
      (node (ref "C327") (pin "2") (pinfunction "C2_2") (pintype "passive"))
      (node (ref "C328") (pin "2") (pinfunction "C2_2") (pintype "passive"))
      (node (ref "C329") (pin "2") (pinfunction "C2_2") (pintype "passive"))
      (node (ref "C330") (pin "2") (pinfunction "C2_2") (pintype "passive"))
      (node (ref "C331") (pin "2") (pinfunction "C2_2") (pintype "passive"))
      (node (ref "C401") (pin "2") (pinfunction "C2_2") (pintype "passive"))
      (node (ref "C402") (pin "2") (pinfunction "C2_2") (pintype "passive"))
      (node (ref "C404") (pin "2") (pinfunction "C2_2") (pintype "passive"))
      (node (ref "C405") (pin "2") (pinfunction "C2_2") (pintype "passive"))
      (node (ref "C406") (pin "2") (pinfunction "C2_2") (pintype "passive"))
      (node (ref "C407") (pin "2") (pinfunction "C2_2") (pintype "passive"))
      (node (ref "C408") (pin "2") (pinfunction "C2_2") (pintype "passive"))
      (node (ref "C409") (pin "2") (pinfunction "C2_2") (pintype "passive"))
      (node (ref "C410") (pin "2") (pinfunction "C2_2") (pintype "passive"))
      (node (ref "C411") (pin "2") (pinfunction "C2_2") (pintype "passive"))
      (node (ref "C412") (pin "2") (pinfunction "C2_2") (pintype "passive"))
      (node (ref "C413") (pin "2") (pinfunction "C2_2") (pintype "passive"))
      (node (ref "C414") (pin "2") (pinfunction "C2_2") (pintype "passive"))
      (node (ref "C415") (pin "2") (pinfunction "C2_2") (pintype "passive"))
      (node (ref "C416") (pin "2") (pinfunction "C2_2") (pintype "passive"))
      (node (ref "C417") (pin "2") (pinfunction "C2_2") (pintype "passive"))
      (node (ref "C418") (pin "2") (pinfunction "C2_2") (pintype "passive"))
      (node (ref "C419") (pin "2") (pinfunction "C2_2") (pintype "passive"))
      (node (ref "C420") (pin "2") (pinfunction "C2_2") (pintype "passive"))
      (node (ref "C422") (pin "2") (pinfunction "C2_2") (pintype "passive"))
      (node (ref "C424") (pin "2") (pinfunction "C2_2") (pintype "passive"))
      (node (ref "C503") (pin "2") (pinfunction "C2_2") (pintype "passive"))
      (node (ref "C504") (pin "2") (pinfunction "C2_2") (pintype "passive"))
      (node (ref "C505") (pin "2") (pinfunction "C2_2") (pintype "passive"))
      (node (ref "C506") (pin "2") (pinfunction "C2_2") (pintype "passive"))
      (node (ref "C507") (pin "2") (pinfunction "C2_2") (pintype "passive"))
      (node (ref "C508") (pin "2") (pinfunction "C2_2") (pintype "passive"))
      (node (ref "C517") (pin "2") (pinfunction "C2_2") (pintype "passive"))
      (node (ref "C518") (pin "2") (pinfunction "C2_2") (pintype "passive"))
      (node (ref "C519") (pin "2") (pinfunction "C2_2") (pintype "passive"))
      (node (ref "C520") (pin "2") (pinfunction "C2_2") (pintype "passive"))
      (node (ref "C521") (pin "2") (pinfunction "C2_2") (pintype "passive"))
      (node (ref "C522") (pin "2") (pinfunction "C2_2") (pintype "passive"))
      (node (ref "C523") (pin "2") (pinfunction "C2_2") (pintype "passive"))
      (node (ref "C524") (pin "2") (pinfunction "C2_2") (pintype "passive"))
      (node (ref "C525") (pin "2") (pinfunction "C2_2") (pintype "passive"))
      (node (ref "C526") (pin "2") (pinfunction "C2_2") (pintype "passive"))
      (node (ref "C527") (pin "2") (pinfunction "C2_2") (pintype "passive"))
      (node (ref "C528") (pin "2") (pinfunction "C2_2") (pintype "passive"))
      (node (ref "C534") (pin "2") (pinfunction "C2_2") (pintype "passive"))
      (node (ref "C535") (pin "2") (pinfunction "C2_2") (pintype "passive"))
      (node (ref "C536") (pin "2") (pinfunction "C2_2") (pintype "passive"))
      (node (ref "C537") (pin "2") (pinfunction "C2_2") (pintype "passive"))
      (node (ref "C540") (pin "2") (pinfunction "C2_2") (pintype "passive"))
      (node (ref "C541") (pin "2") (pinfunction "C2_2") (pintype "passive"))
      (node (ref "C542") (pin "2") (pinfunction "C2_2") (pintype "passive"))
      (node (ref "C543") (pin "2") (pinfunction "C2_2") (pintype "passive"))
      (node (ref "C548") (pin "2") (pinfunction "C2_2") (pintype "passive"))
      (node (ref "C549") (pin "2") (pinfunction "C2_2") (pintype "passive"))
      (node (ref "C551") (pin "2") (pinfunction "C2_2") (pintype "passive"))
      (node (ref "C552") (pin "2") (pinfunction "C2_2") (pintype "passive"))
      (node (ref "C602") (pin "2") (pinfunction "C2_2") (pintype "passive"))
      (node (ref "C603") (pin "2") (pinfunction "C2_2") (pintype "passive"))
      (node (ref "C604") (pin "2") (pinfunction "C2_2") (pintype "passive"))
      (node (ref "C605") (pin "2") (pinfunction "C2_2") (pintype "passive"))
      (node (ref "C606") (pin "2") (pinfunction "C2_2") (pintype "passive"))
      (node (ref "C607") (pin "2") (pinfunction "C2_2") (pintype "passive"))
      (node (ref "C608") (pin "2") (pinfunction "C2_2") (pintype "passive"))
      (node (ref "C609") (pin "2") (pinfunction "C2_2") (pintype "passive"))
      (node (ref "C610") (pin "2") (pinfunction "C2_2") (pintype "passive"))
      (node (ref "C611") (pin "2") (pinfunction "C2_2") (pintype "passive"))
      (node (ref "C612") (pin "2") (pinfunction "C2_2") (pintype "passive"))
      (node (ref "C613") (pin "2") (pinfunction "C2_2") (pintype "passive"))
      (node (ref "C614") (pin "2") (pinfunction "C2_2") (pintype "passive"))
      (node (ref "C615") (pin "2") (pinfunction "C2_2") (pintype "passive"))
      (node (ref "C616") (pin "2") (pinfunction "C2_2") (pintype "passive"))
      (node (ref "C617") (pin "2") (pinfunction "C2_2") (pintype "passive"))
      (node (ref "C618") (pin "2") (pinfunction "C2_2") (pintype "passive"))
      (node (ref "C619") (pin "2") (pinfunction "C2_2") (pintype "passive"))
      (node (ref "C620") (pin "2") (pinfunction "C2_2") (pintype "passive"))
      (node (ref "C621") (pin "2") (pinfunction "C2_2") (pintype "passive"))
      (node (ref "C622") (pin "2") (pinfunction "C2_2") (pintype "passive"))
      (node (ref "C701") (pin "2") (pinfunction "C2_2") (pintype "passive"))
      (node (ref "C702") (pin "2") (pinfunction "C2_2") (pintype "passive"))
      (node (ref "C703") (pin "2") (pinfunction "C2_2") (pintype "passive"))
      (node (ref "C704") (pin "2") (pinfunction "C2_2") (pintype "passive"))
      (node (ref "C705") (pin "2") (pinfunction "C2_2") (pintype "passive"))
      (node (ref "C706") (pin "2") (pinfunction "C2_2") (pintype "passive"))
      (node (ref "C707") (pin "2") (pinfunction "C2_2") (pintype "passive"))
      (node (ref "C708") (pin "2") (pinfunction "C2_2") (pintype "passive"))
      (node (ref "C709") (pin "2") (pinfunction "C2_2") (pintype "passive"))
      (node (ref "C710") (pin "2") (pinfunction "C2_2") (pintype "passive"))
      (node (ref "C711") (pin "2") (pinfunction "C2_2") (pintype "passive"))
      (node (ref "C716") (pin "2") (pinfunction "C2_2") (pintype "passive"))
      (node (ref "C721") (pin "2") (pinfunction "C2_2") (pintype "passive"))
      (node (ref "C722") (pin "2") (pinfunction "C2_2") (pintype "passive"))
      (node (ref "C723") (pin "2") (pinfunction "C2_2") (pintype "passive"))
      (node (ref "C724") (pin "2") (pinfunction "C2_2") (pintype "passive"))
      (node (ref "C813") (pin "2") (pinfunction "C2_2") (pintype "passive"))
      (node (ref "C901") (pin "2") (pinfunction "C2_2") (pintype "passive"))
      (node (ref "C902") (pin "2") (pinfunction "C2_2") (pintype "passive"))
      (node (ref "C903") (pin "2") (pinfunction "C2_2") (pintype "passive"))
      (node (ref "C904") (pin "2") (pinfunction "C2_2") (pintype "passive"))
      (node (ref "C905") (pin "2") (pinfunction "C2_2") (pintype "passive"))
      (node (ref "C906") (pin "2") (pinfunction "C2_2") (pintype "passive"))
      (node (ref "C908") (pin "2") (pinfunction "C2_2") (pintype "passive"))
      (node (ref "C909") (pin "2") (pinfunction "C2_2") (pintype "passive"))
      (node (ref "CON101") (pin "10") (pinfunction "S_10") (pintype "passive"))
      (node (ref "CON101") (pin "13") (pinfunction "S_13") (pintype "passive"))
      (node (ref "CON101") (pin "16") (pinfunction "S_16") (pintype "passive"))
      (node (ref "CON101") (pin "19") (pinfunction "S_19") (pintype "passive"))
      (node (ref "CON101") (pin "22") (pinfunction "S_22") (pintype "passive"))
      (node (ref "CON101") (pin "4") (pinfunction "S_4") (pintype "passive"))
      (node (ref "CON101") (pin "7") (pinfunction "S_7") (pintype "passive"))
      (node (ref "CON102") (pin "10") (pinfunction "S_10") (pintype "passive"))
      (node (ref "CON102") (pin "13") (pinfunction "S_13") (pintype "passive"))
      (node (ref "CON102") (pin "16") (pinfunction "S_16") (pintype "passive"))
      (node (ref "CON102") (pin "19") (pinfunction "S_19") (pintype "passive"))
      (node (ref "CON102") (pin "22") (pinfunction "S_22") (pintype "passive"))
      (node (ref "CON102") (pin "4") (pinfunction "S_4") (pintype "passive"))
      (node (ref "CON102") (pin "7") (pinfunction "S_7") (pintype "passive"))
      (node (ref "CON1101") (pin "P$1") (pinfunction "S_P$1") (pintype "passive"))
      (node (ref "CON701") (pin "4") (pinfunction "S_4") (pintype "passive"))
      (node (ref "CON801") (pin "A12") (pinfunction "S_A12") (pintype "passive"))
      (node (ref "CON801") (pin "A15") (pinfunction "S_A15") (pintype "passive"))
      (node (ref "CON801") (pin "A18") (pinfunction "S_A18") (pintype "passive"))
      (node (ref "CON801") (pin "A20") (pinfunction "S_A20") (pintype "passive"))
      (node (ref "CON801") (pin "A23") (pinfunction "S_A23") (pintype "passive"))
      (node (ref "CON801") (pin "A24") (pinfunction "S_A24") (pintype "passive"))
      (node (ref "CON801") (pin "A27") (pinfunction "S_A27") (pintype "passive"))
      (node (ref "CON801") (pin "A28") (pinfunction "S_A28") (pintype "passive"))
      (node (ref "CON801") (pin "A31") (pinfunction "S_A31") (pintype "passive"))
      (node (ref "CON801") (pin "A4") (pinfunction "S_A4") (pintype "passive"))
      (node (ref "CON801") (pin "B13") (pinfunction "S_B13") (pintype "passive"))
      (node (ref "CON801") (pin "B16") (pinfunction "S_B16") (pintype "passive"))
      (node (ref "CON801") (pin "B18") (pinfunction "S_B18") (pintype "passive"))
      (node (ref "CON801") (pin "B21") (pinfunction "S_B21") (pintype "passive"))
      (node (ref "CON801") (pin "B22") (pinfunction "S_B22") (pintype "passive"))
      (node (ref "CON801") (pin "B25") (pinfunction "S_B25") (pintype "passive"))
      (node (ref "CON801") (pin "B26") (pinfunction "S_B26") (pintype "passive"))
      (node (ref "CON801") (pin "B29") (pinfunction "S_B29") (pintype "passive"))
      (node (ref "CON801") (pin "B32") (pinfunction "S_B32") (pintype "passive"))
      (node (ref "CON801") (pin "B4") (pinfunction "S_B4") (pintype "passive"))
      (node (ref "CON801") (pin "B7") (pinfunction "S_B7") (pintype "passive"))
      (node (ref "D1001") (pin "3") (pinfunction "A_3") (pintype "bidirectional"))
      (node (ref "D1002") (pin "A") (pinfunction "A_A") (pintype "passive"))
      (node (ref "D1004") (pin "C") (pinfunction "C_C") (pintype "passive"))
      (node (ref "D102") (pin "C") (pinfunction "C_C") (pintype "passive"))
      (node (ref "D1104") (pin "C") (pinfunction "C_C") (pintype "passive"))
      (node (ref "D1105") (pin "A") (pinfunction "A_A") (pintype "passive"))
      (node (ref "D201") (pin "C") (pinfunction "C_C") (pintype "passive"))
      (node (ref "D202") (pin "C") (pinfunction "C_C") (pintype "passive"))
      (node (ref "D501") (pin "2") (pinfunction "2_2") (pintype "passive"))
      (node (ref "D502") (pin "2") (pinfunction "2_2") (pintype "passive"))
      (node (ref "D503") (pin "2") (pinfunction "2_2") (pintype "passive"))
      (node (ref "D504") (pin "2") (pinfunction "2_2") (pintype "passive"))
      (node (ref "D505") (pin "C") (pinfunction "C_C") (pintype "passive"))
      (node (ref "D506") (pin "C") (pinfunction "C_C") (pintype "passive"))
      (node (ref "D507") (pin "C") (pinfunction "C_C") (pintype "passive"))
      (node (ref "D508") (pin "C") (pinfunction "C_C") (pintype "passive"))
      (node (ref "D509") (pin "2") (pinfunction "2_2") (pintype "passive"))
      (node (ref "D510") (pin "2") (pinfunction "2_2") (pintype "passive"))
      (node (ref "D511") (pin "2") (pinfunction "2_2") (pintype "passive"))
      (node (ref "D512") (pin "2") (pinfunction "2_2") (pintype "passive"))
      (node (ref "D601") (pin "2") (pinfunction "2_2") (pintype "passive"))
      (node (ref "D602") (pin "2") (pinfunction "2_2") (pintype "passive"))
      (node (ref "J101") (pin "10") (pinfunction "CHS_GND_10") (pintype "bidirectional"))
      (node (ref "J101") (pin "SHIELD@0") (pinfunction "CHS_GND_SHIELD@0") (pintype "bidirectional"))
      (node (ref "J101") (pin "SHIELD@1") (pinfunction "CHS_GND_SHIELD@1") (pintype "bidirectional"))
      (node (ref "J701") (pin "1") (pinfunction "S_1") (pintype "bidirectional"))
      (node (ref "J702") (pin "1") (pinfunction "S_1") (pintype "bidirectional"))
      (node (ref "J703") (pin "1") (pinfunction "S_1") (pintype "bidirectional"))
      (node (ref "JP101") (pin "3") (pinfunction "S_3") (pintype "passive"))
      (node (ref "JP1101") (pin "3") (pinfunction "S_3") (pintype "passive"))
      (node (ref "JP1101") (pin "4") (pinfunction "S_4") (pintype "passive"))
      (node (ref "JP201") (pin "1") (pinfunction "S_1") (pintype "passive"))
      (node (ref "JP201") (pin "5") (pinfunction "S_5") (pintype "passive"))
      (node (ref "JP202") (pin "6") (pinfunction "S_6") (pintype "passive"))
      (node (ref "M701") (pin "3") (pinfunction "GND_3") (pintype "passive"))
      (node (ref "M702") (pin "2") (pinfunction "SEL_2") (pintype "passive"))
      (node (ref "M702") (pin "3") (pinfunction "GND_3") (pintype "passive"))
      (node (ref "Q101") (pin "2") (pinfunction "S_2") (pintype "passive"))
      (node (ref "Q102") (pin "2") (pinfunction "S_2") (pintype "passive"))
      (node (ref "Q1101") (pin "2") (pinfunction "S_2") (pintype "passive"))
      (node (ref "Q1103") (pin "2") (pinfunction "S_2") (pintype "passive"))
      (node (ref "Q1106") (pin "2") (pinfunction "S_2") (pintype "passive"))
      (node (ref "R1001") (pin "1") (pinfunction "1_1") (pintype "passive"))
      (node (ref "R1003") (pin "1") (pinfunction "1_1") (pintype "passive"))
      (node (ref "R1006") (pin "1") (pinfunction "1_1") (pintype "passive"))
      (node (ref "R1009") (pin "1") (pinfunction "1_1") (pintype "passive"))
      (node (ref "R1010") (pin "1") (pinfunction "1_1") (pintype "passive"))
      (node (ref "R1012") (pin "1") (pinfunction "1_1") (pintype "passive"))
      (node (ref "R102") (pin "1") (pinfunction "1_1") (pintype "passive"))
      (node (ref "R104") (pin "1") (pinfunction "1_1") (pintype "passive"))
      (node (ref "R105") (pin "1") (pinfunction "1_1") (pintype "passive"))
      (node (ref "R107") (pin "1") (pinfunction "1_1") (pintype "passive"))
      (node (ref "R109") (pin "1") (pinfunction "1_1") (pintype "passive"))
      (node (ref "R110") (pin "1") (pinfunction "1_1") (pintype "passive"))
      (node (ref "R1102") (pin "1") (pinfunction "1_1") (pintype "passive"))
      (node (ref "R1104") (pin "1") (pinfunction "1_1") (pintype "passive"))
      (node (ref "R1105") (pin "1") (pinfunction "1_1") (pintype "passive"))
      (node (ref "R1109") (pin "1") (pinfunction "1_1") (pintype "passive"))
      (node (ref "R1111") (pin "1") (pinfunction "1_1") (pintype "passive"))
      (node (ref "R1112") (pin "1") (pinfunction "1_1") (pintype "passive"))
      (node (ref "R1115") (pin "1") (pinfunction "1_1") (pintype "passive"))
      (node (ref "R112") (pin "1") (pinfunction "1_1") (pintype "passive"))
      (node (ref "R1125") (pin "1") (pinfunction "1_1") (pintype "passive"))
      (node (ref "R1126") (pin "1") (pinfunction "1_1") (pintype "passive"))
      (node (ref "R1127") (pin "1") (pinfunction "1_1") (pintype "passive"))
      (node (ref "R1128") (pin "1") (pinfunction "1_1") (pintype "passive"))
      (node (ref "R1203") (pin "1") (pinfunction "1_1") (pintype "passive"))
      (node (ref "R1206") (pin "1") (pinfunction "1_1") (pintype "passive"))
      (node (ref "R1209") (pin "1") (pinfunction "1_1") (pintype "passive"))
      (node (ref "R1213") (pin "1") (pinfunction "1_1") (pintype "passive"))
      (node (ref "R1215") (pin "1") (pinfunction "1_1") (pintype "passive"))
      (node (ref "R216") (pin "1") (pinfunction "1_1") (pintype "passive"))
      (node (ref "R301") (pin "1") (pinfunction "1_1") (pintype "passive"))
      (node (ref "R302") (pin "1") (pinfunction "1_1") (pintype "passive"))
      (node (ref "R402") (pin "1") (pinfunction "1_1") (pintype "passive"))
      (node (ref "R403") (pin "1") (pinfunction "1_1") (pintype "passive"))
      (node (ref "R404") (pin "1") (pinfunction "1_1") (pintype "passive"))
      (node (ref "R405") (pin "1") (pinfunction "1_1") (pintype "passive"))
      (node (ref "R501") (pin "1") (pinfunction "1_1") (pintype "passive"))
      (node (ref "R502") (pin "1") (pinfunction "1_1") (pintype "passive"))
      (node (ref "R507") (pin "1") (pinfunction "1_1") (pintype "passive"))
      (node (ref "R508") (pin "1") (pinfunction "1_1") (pintype "passive"))
      (node (ref "R513") (pin "1") (pinfunction "1_1") (pintype "passive"))
      (node (ref "R515") (pin "1") (pinfunction "1_1") (pintype "passive"))
      (node (ref "R601") (pin "1") (pinfunction "1_1") (pintype "passive"))
      (node (ref "R602") (pin "1") (pinfunction "1_1") (pintype "passive"))
      (node (ref "R603") (pin "1") (pinfunction "1_1") (pintype "passive"))
      (node (ref "R605") (pin "1") (pinfunction "1_1") (pintype "passive"))
      (node (ref "R607") (pin "1") (pinfunction "1_1") (pintype "passive"))
      (node (ref "R614") (pin "1") (pinfunction "1_1") (pintype "passive"))
      (node (ref "R615") (pin "1") (pinfunction "1_1") (pintype "passive"))
      (node (ref "R701") (pin "1") (pinfunction "1_1") (pintype "passive"))
      (node (ref "R702") (pin "1") (pinfunction "1_1") (pintype "passive"))
      (node (ref "R703") (pin "1") (pinfunction "1_1") (pintype "passive"))
      (node (ref "R705") (pin "1") (pinfunction "1_1") (pintype "passive"))
      (node (ref "R707") (pin "1") (pinfunction "1_1") (pintype "passive"))
      (node (ref "R709") (pin "1") (pinfunction "1_1") (pintype "passive"))
      (node (ref "R711") (pin "1") (pinfunction "1_1") (pintype "passive"))
      (node (ref "R901") (pin "1") (pinfunction "1_1") (pintype "passive"))
      (node (ref "R903") (pin "1") (pinfunction "1_1") (pintype "passive"))
      (node (ref "RFCON101") (pin "P$1") (pinfunction "GND_P$1") (pintype "bidirectional"))
      (node (ref "RFCON101") (pin "P$2") (pinfunction "GND_P$2") (pintype "bidirectional"))
      (node (ref "RFCON501") (pin "GND@0") (pinfunction "GND_GND@0") (pintype "bidirectional"))
      (node (ref "RFCON501") (pin "GND@1") (pinfunction "GND_GND@1") (pintype "bidirectional"))
      (node (ref "RFCON501") (pin "GND@2") (pinfunction "GND_GND@2") (pintype "bidirectional"))
      (node (ref "RFCON501") (pin "GND@3") (pinfunction "GND_GND@3") (pintype "bidirectional"))
      (node (ref "RFCON502") (pin "GND@0") (pinfunction "GND_GND@0") (pintype "bidirectional"))
      (node (ref "RFCON502") (pin "GND@1") (pinfunction "GND_GND@1") (pintype "bidirectional"))
      (node (ref "RFCON502") (pin "GND@2") (pinfunction "GND_GND@2") (pintype "bidirectional"))
      (node (ref "RFCON502") (pin "GND@3") (pinfunction "GND_GND@3") (pintype "bidirectional"))
      (node (ref "RFCON503") (pin "GND@0") (pinfunction "GND_GND@0") (pintype "bidirectional"))
      (node (ref "RFCON503") (pin "GND@1") (pinfunction "GND_GND@1") (pintype "bidirectional"))
      (node (ref "RFCON503") (pin "GND@2") (pinfunction "GND_GND@2") (pintype "bidirectional"))
      (node (ref "RFCON503") (pin "GND@3") (pinfunction "GND_GND@3") (pintype "bidirectional"))
      (node (ref "RFCON504") (pin "GND@0") (pinfunction "GND_GND@0") (pintype "bidirectional"))
      (node (ref "RFCON504") (pin "GND@1") (pinfunction "GND_GND@1") (pintype "bidirectional"))
      (node (ref "RFCON504") (pin "GND@2") (pinfunction "GND_GND@2") (pintype "bidirectional"))
      (node (ref "RFCON504") (pin "GND@3") (pinfunction "GND_GND@3") (pintype "bidirectional"))
      (node (ref "RFCON505") (pin "P$1") (pinfunction "GND_P$1") (pintype "bidirectional"))
      (node (ref "RFCON505") (pin "P$2") (pinfunction "GND_P$2") (pintype "bidirectional"))
      (node (ref "RFCON506") (pin "P$1") (pinfunction "GND_P$1") (pintype "bidirectional"))
      (node (ref "RFCON506") (pin "P$2") (pinfunction "GND_P$2") (pintype "bidirectional"))
      (node (ref "RFCON507") (pin "GND@0") (pinfunction "GND_GND@0") (pintype "bidirectional"))
      (node (ref "RFCON507") (pin "GND@1") (pinfunction "GND_GND@1") (pintype "bidirectional"))
      (node (ref "RFCON507") (pin "GND@2") (pinfunction "GND_GND@2") (pintype "bidirectional"))
      (node (ref "RFCON507") (pin "GND@3") (pinfunction "GND_GND@3") (pintype "bidirectional"))
      (node (ref "RFCON508") (pin "GND@0") (pinfunction "GND_GND@0") (pintype "bidirectional"))
      (node (ref "RFCON508") (pin "GND@1") (pinfunction "GND_GND@1") (pintype "bidirectional"))
      (node (ref "RFCON508") (pin "GND@2") (pinfunction "GND_GND@2") (pintype "bidirectional"))
      (node (ref "RFCON508") (pin "GND@3") (pinfunction "GND_GND@3") (pintype "bidirectional"))
      (node (ref "RFCON509") (pin "GND@0") (pinfunction "GND_GND@0") (pintype "bidirectional"))
      (node (ref "RFCON509") (pin "GND@1") (pinfunction "GND_GND@1") (pintype "bidirectional"))
      (node (ref "RFCON509") (pin "GND@2") (pinfunction "GND_GND@2") (pintype "bidirectional"))
      (node (ref "RFCON509") (pin "GND@3") (pinfunction "GND_GND@3") (pintype "bidirectional"))
      (node (ref "RFCON510") (pin "GND@0") (pinfunction "GND_GND@0") (pintype "bidirectional"))
      (node (ref "RFCON510") (pin "GND@1") (pinfunction "GND_GND@1") (pintype "bidirectional"))
      (node (ref "RFCON510") (pin "GND@2") (pinfunction "GND_GND@2") (pintype "bidirectional"))
      (node (ref "RFCON510") (pin "GND@3") (pinfunction "GND_GND@3") (pintype "bidirectional"))
      (node (ref "RFCON601") (pin "GND@0") (pinfunction "GND_GND@0") (pintype "bidirectional"))
      (node (ref "RFCON601") (pin "GND@1") (pinfunction "GND_GND@1") (pintype "bidirectional"))
      (node (ref "RFCON601") (pin "GND@2") (pinfunction "GND_GND@2") (pintype "bidirectional"))
      (node (ref "RFCON601") (pin "GND@3") (pinfunction "GND_GND@3") (pintype "bidirectional"))
      (node (ref "RFCON602") (pin "GND@0") (pinfunction "GND_GND@0") (pintype "bidirectional"))
      (node (ref "RFCON602") (pin "GND@1") (pinfunction "GND_GND@1") (pintype "bidirectional"))
      (node (ref "RFCON602") (pin "GND@2") (pinfunction "GND_GND@2") (pintype "bidirectional"))
      (node (ref "RFCON602") (pin "GND@3") (pinfunction "GND_GND@3") (pintype "bidirectional"))
      (node (ref "RFCON901") (pin "P$1") (pinfunction "GND_P$1") (pintype "bidirectional"))
      (node (ref "RFCON901") (pin "P$2") (pinfunction "GND_P$2") (pintype "bidirectional"))
      (node (ref "RFCON902") (pin "P$1") (pinfunction "GND_P$1") (pintype "bidirectional"))
      (node (ref "RFCON902") (pin "P$2") (pinfunction "GND_P$2") (pintype "bidirectional"))
      (node (ref "S1001") (pin "1") (pinfunction "1_1") (pintype "passive"))
      (node (ref "S1001") (pin "2") (pinfunction "2_2") (pintype "passive"))
      (node (ref "SD101") (pin "11") (pinfunction "GND_11") (pintype "power_in"))
      (node (ref "SD101") (pin "12") (pinfunction "GND_12") (pintype "power_in"))
      (node (ref "SD101") (pin "13") (pinfunction "GND_13") (pintype "power_in"))
      (node (ref "SD101") (pin "14") (pinfunction "GND_14") (pintype "power_in"))
      (node (ref "SD101") (pin "15") (pinfunction "GND_15") (pintype "power_in"))
      (node (ref "SD101") (pin "16") (pinfunction "GND_16") (pintype "power_in"))
      (node (ref "SD101") (pin "6") (pinfunction "VSS_6") (pintype "power_in"))
      (node (ref "SHIELD401") (pin "1") (pinfunction "GND_1") (pintype "bidirectional"))
      (node (ref "SHIELD401") (pin "10") (pinfunction "GND_10") (pintype "bidirectional"))
      (node (ref "SHIELD401") (pin "11") (pinfunction "GND_11") (pintype "bidirectional"))
      (node (ref "SHIELD401") (pin "12") (pinfunction "GND_12") (pintype "bidirectional"))
      (node (ref "SHIELD401") (pin "13") (pinfunction "GND_13") (pintype "bidirectional"))
      (node (ref "SHIELD401") (pin "14") (pinfunction "GND_14") (pintype "bidirectional"))
      (node (ref "SHIELD401") (pin "15") (pinfunction "GND_15") (pintype "bidirectional"))
      (node (ref "SHIELD401") (pin "16") (pinfunction "GND_16") (pintype "bidirectional"))
      (node (ref "SHIELD401") (pin "17") (pinfunction "GND_17") (pintype "bidirectional"))
      (node (ref "SHIELD401") (pin "18") (pinfunction "GND_18") (pintype "bidirectional"))
      (node (ref "SHIELD401") (pin "19") (pinfunction "GND_19") (pintype "bidirectional"))
      (node (ref "SHIELD401") (pin "2") (pinfunction "GND_2") (pintype "bidirectional"))
      (node (ref "SHIELD401") (pin "20") (pinfunction "GND_20") (pintype "bidirectional"))
      (node (ref "SHIELD401") (pin "21") (pinfunction "GND_21") (pintype "bidirectional"))
      (node (ref "SHIELD401") (pin "22") (pinfunction "GND_22") (pintype "bidirectional"))
      (node (ref "SHIELD401") (pin "23") (pinfunction "GND_23") (pintype "bidirectional"))
      (node (ref "SHIELD401") (pin "24") (pinfunction "GND_24") (pintype "bidirectional"))
      (node (ref "SHIELD401") (pin "25") (pinfunction "GND_25") (pintype "bidirectional"))
      (node (ref "SHIELD401") (pin "26") (pinfunction "GND_26") (pintype "bidirectional"))
      (node (ref "SHIELD401") (pin "27") (pinfunction "GND_27") (pintype "bidirectional"))
      (node (ref "SHIELD401") (pin "28") (pinfunction "GND_28") (pintype "bidirectional"))
      (node (ref "SHIELD401") (pin "29") (pinfunction "GND_29") (pintype "bidirectional"))
      (node (ref "SHIELD401") (pin "3") (pinfunction "GND_3") (pintype "bidirectional"))
      (node (ref "SHIELD401") (pin "30") (pinfunction "GND_30") (pintype "bidirectional"))
      (node (ref "SHIELD401") (pin "31") (pinfunction "GND_31") (pintype "bidirectional"))
      (node (ref "SHIELD401") (pin "32") (pinfunction "GND_32") (pintype "bidirectional"))
      (node (ref "SHIELD401") (pin "4") (pinfunction "GND_4") (pintype "bidirectional"))
      (node (ref "SHIELD401") (pin "5") (pinfunction "GND_5") (pintype "bidirectional"))
      (node (ref "SHIELD401") (pin "6") (pinfunction "GND_6") (pintype "bidirectional"))
      (node (ref "SHIELD401") (pin "7") (pinfunction "GND_7") (pintype "bidirectional"))
      (node (ref "SHIELD401") (pin "8") (pinfunction "GND_8") (pintype "bidirectional"))
      (node (ref "SHIELD401") (pin "9") (pinfunction "GND_9") (pintype "bidirectional"))
      (node (ref "SHIELD601") (pin "1") (pinfunction "GND_1") (pintype "bidirectional"))
      (node (ref "SHIELD601") (pin "10") (pinfunction "GND_10") (pintype "bidirectional"))
      (node (ref "SHIELD601") (pin "11") (pinfunction "GND_11") (pintype "bidirectional"))
      (node (ref "SHIELD601") (pin "12") (pinfunction "GND_12") (pintype "bidirectional"))
      (node (ref "SHIELD601") (pin "13") (pinfunction "GND_13") (pintype "bidirectional"))
      (node (ref "SHIELD601") (pin "14") (pinfunction "GND_14") (pintype "bidirectional"))
      (node (ref "SHIELD601") (pin "15") (pinfunction "GND_15") (pintype "bidirectional"))
      (node (ref "SHIELD601") (pin "16") (pinfunction "GND_16") (pintype "bidirectional"))
      (node (ref "SHIELD601") (pin "2") (pinfunction "GND_2") (pintype "bidirectional"))
      (node (ref "SHIELD601") (pin "3") (pinfunction "GND_3") (pintype "bidirectional"))
      (node (ref "SHIELD601") (pin "4") (pinfunction "GND_4") (pintype "bidirectional"))
      (node (ref "SHIELD601") (pin "5") (pinfunction "GND_5") (pintype "bidirectional"))
      (node (ref "SHIELD601") (pin "6") (pinfunction "GND_6") (pintype "bidirectional"))
      (node (ref "SHIELD601") (pin "7") (pinfunction "GND_7") (pintype "bidirectional"))
      (node (ref "SHIELD601") (pin "8") (pinfunction "GND_8") (pintype "bidirectional"))
      (node (ref "SHIELD601") (pin "9") (pinfunction "GND_9") (pintype "bidirectional"))
      (node (ref "T501") (pin "2") (pinfunction "PRI2_2") (pintype "passive"))
      (node (ref "T502") (pin "2") (pinfunction "PRI2_2") (pintype "passive"))
      (node (ref "T503") (pin "2") (pinfunction "PRI2_2") (pintype "passive"))
      (node (ref "T504") (pin "2") (pinfunction "PRI2_2") (pintype "passive"))
      (node (ref "T505") (pin "2") (pinfunction "PRI2_2") (pintype "passive"))
      (node (ref "T506") (pin "2") (pinfunction "PRI2_2") (pintype "passive"))
      (node (ref "T507") (pin "2") (pinfunction "PRI2_2") (pintype "passive"))
      (node (ref "T508") (pin "2") (pinfunction "PRI2_2") (pintype "passive"))
      (node (ref "TC1001") (pin "3") (pinfunction "S_3") (pintype "passive"))
      (node (ref "TC201") (pin "3") (pinfunction "S_3") (pintype "passive"))
      (node (ref "U1001") (pin "4") (pinfunction "GND_4") (pintype "bidirectional"))
      (node (ref "U1001") (pin "9") (pinfunction "GND_9") (pintype "bidirectional"))
      (node (ref "U1002") (pin "41") (pinfunction "GND_41") (pintype "bidirectional"))
      (node (ref "U1003") (pin "2") (pinfunction "GND_2") (pintype "bidirectional"))
      (node (ref "U101") (pin "2") (pinfunction "GND_2") (pintype "bidirectional"))
      (node (ref "U102") (pin "1") (pinfunction "GND_1") (pintype "bidirectional"))
      (node (ref "U102") (pin "107") (pinfunction "GND_107") (pintype "bidirectional"))
      (node (ref "U102") (pin "108") (pinfunction "GND_108") (pintype "bidirectional"))
      (node (ref "U102") (pin "113") (pinfunction "GND_113") (pintype "bidirectional"))
      (node (ref "U102") (pin "114") (pinfunction "GND_114") (pintype "bidirectional"))
      (node (ref "U102") (pin "119") (pinfunction "GND_119") (pintype "bidirectional"))
      (node (ref "U102") (pin "120") (pinfunction "GND_120") (pintype "bidirectional"))
      (node (ref "U102") (pin "125") (pinfunction "GND_125") (pintype "bidirectional"))
      (node (ref "U102") (pin "126") (pinfunction "GND_126") (pintype "bidirectional"))
      (node (ref "U102") (pin "13") (pinfunction "GND_13") (pintype "bidirectional"))
      (node (ref "U102") (pin "131") (pinfunction "GND_131") (pintype "bidirectional"))
      (node (ref "U102") (pin "132") (pinfunction "GND_132") (pintype "bidirectional"))
      (node (ref "U102") (pin "137") (pinfunction "GND_137") (pintype "bidirectional"))
      (node (ref "U102") (pin "138") (pinfunction "GND_138") (pintype "bidirectional"))
      (node (ref "U102") (pin "14") (pinfunction "GND_14") (pintype "bidirectional"))
      (node (ref "U102") (pin "144") (pinfunction "GND_144") (pintype "bidirectional"))
      (node (ref "U102") (pin "150") (pinfunction "GND_150") (pintype "bidirectional"))
      (node (ref "U102") (pin "155") (pinfunction "GND_155") (pintype "bidirectional"))
      (node (ref "U102") (pin "156") (pinfunction "GND_156") (pintype "bidirectional"))
      (node (ref "U102") (pin "161") (pinfunction "GND_161") (pintype "bidirectional"))
      (node (ref "U102") (pin "162") (pinfunction "GND_162") (pintype "bidirectional"))
      (node (ref "U102") (pin "167") (pinfunction "GND_167") (pintype "bidirectional"))
      (node (ref "U102") (pin "168") (pinfunction "GND_168") (pintype "bidirectional"))
      (node (ref "U102") (pin "173") (pinfunction "GND_173") (pintype "bidirectional"))
      (node (ref "U102") (pin "174") (pinfunction "GND_174") (pintype "bidirectional"))
      (node (ref "U102") (pin "179") (pinfunction "GND_179") (pintype "bidirectional"))
      (node (ref "U102") (pin "180") (pinfunction "GND_180") (pintype "bidirectional"))
      (node (ref "U102") (pin "185") (pinfunction "GND_185") (pintype "bidirectional"))
      (node (ref "U102") (pin "186") (pinfunction "GND_186") (pintype "bidirectional"))
      (node (ref "U102") (pin "191") (pinfunction "GND_191") (pintype "bidirectional"))
      (node (ref "U102") (pin "192") (pinfunction "GND_192") (pintype "bidirectional"))
      (node (ref "U102") (pin "197") (pinfunction "GND_197") (pintype "bidirectional"))
      (node (ref "U102") (pin "198") (pinfunction "GND_198") (pintype "bidirectional"))
      (node (ref "U102") (pin "2") (pinfunction "GND_2") (pintype "bidirectional"))
      (node (ref "U102") (pin "22") (pinfunction "GND_22") (pintype "bidirectional"))
      (node (ref "U102") (pin "23") (pinfunction "GND_23") (pintype "bidirectional"))
      (node (ref "U102") (pin "32") (pinfunction "GND_32") (pintype "bidirectional"))
      (node (ref "U102") (pin "33") (pinfunction "GND_33") (pintype "bidirectional"))
      (node (ref "U102") (pin "42") (pinfunction "GND_42") (pintype "bidirectional"))
      (node (ref "U102") (pin "43") (pinfunction "GND_43") (pintype "bidirectional"))
      (node (ref "U102") (pin "52") (pinfunction "GND_52") (pintype "bidirectional"))
      (node (ref "U102") (pin "53") (pinfunction "GND_53") (pintype "bidirectional"))
      (node (ref "U102") (pin "59") (pinfunction "GND_59") (pintype "bidirectional"))
      (node (ref "U102") (pin "60") (pinfunction "GND_60") (pintype "bidirectional"))
      (node (ref "U102") (pin "65") (pinfunction "GND_65") (pintype "bidirectional"))
      (node (ref "U102") (pin "66") (pinfunction "GND_66") (pintype "bidirectional"))
      (node (ref "U102") (pin "7") (pinfunction "GND_7") (pintype "bidirectional"))
      (node (ref "U102") (pin "71") (pinfunction "GND_71") (pintype "bidirectional"))
      (node (ref "U102") (pin "74") (pinfunction "GND_74") (pintype "bidirectional"))
      (node (ref "U102") (pin "8") (pinfunction "GND_8") (pintype "bidirectional"))
      (node (ref "U102") (pin "98") (pinfunction "GND_98") (pintype "bidirectional"))
      (node (ref "U1101") (pin "2") (pinfunction "GND_2") (pintype "bidirectional"))
      (node (ref "U1102") (pin "1") (pinfunction "VSENSEN_1") (pintype "bidirectional"))
      (node (ref "U1102") (pin "12") (pinfunction "VSENSEN_12") (pintype "bidirectional"))
      (node (ref "U1102") (pin "14") (pinfunction "PGND_14") (pintype "bidirectional"))
      (node (ref "U1102") (pin "19") (pinfunction "PGND_19") (pintype "bidirectional"))
      (node (ref "U1102") (pin "3") (pinfunction "SGND_3") (pintype "bidirectional"))
      (node (ref "U1102") (pin "34") (pinfunction "PGND_34") (pintype "bidirectional"))
      (node (ref "U1102") (pin "39") (pinfunction "PGND_39") (pintype "bidirectional"))
      (node (ref "U1102") (pin "42") (pinfunction "PGND_42") (pintype "bidirectional"))
      (node (ref "U1102") (pin "43") (pinfunction "PGND_43") (pintype "bidirectional"))
      (node (ref "U1102") (pin "45") (pinfunction "PGND_45") (pintype "bidirectional"))
      (node (ref "U1102") (pin "46") (pinfunction "PGND_46") (pintype "bidirectional"))
      (node (ref "U1102") (pin "47") (pinfunction "PGND_47") (pintype "bidirectional"))
      (node (ref "U1102") (pin "48") (pinfunction "PGND_48") (pintype "bidirectional"))
      (node (ref "U1201") (pin "6") (pinfunction "GND_6") (pintype "bidirectional"))
      (node (ref "U1201") (pin "9") (pinfunction "GND_9") (pintype "bidirectional"))
      (node (ref "U1202") (pin "6") (pinfunction "GND_6") (pintype "bidirectional"))
      (node (ref "U1202") (pin "9") (pinfunction "GND_9") (pintype "bidirectional"))
      (node (ref "U1203") (pin "6") (pinfunction "GND_6") (pintype "bidirectional"))
      (node (ref "U1203") (pin "9") (pinfunction "GND_9") (pintype "bidirectional"))
      (node (ref "U1204") (pin "19") (pinfunction "AGND_19") (pintype "bidirectional"))
      (node (ref "U1204") (pin "2") (pinfunction "PGND_2") (pintype "bidirectional"))
      (node (ref "U1204") (pin "21") (pinfunction "PGND_21") (pintype "bidirectional"))
      (node (ref "U1204") (pin "5") (pinfunction "PGND_5") (pintype "bidirectional"))
      (node (ref "U1204") (pin "8") (pinfunction "AGND_8") (pintype "bidirectional"))
      (node (ref "U1205") (pin "11") (pinfunction "AGND_11") (pintype "bidirectional"))
      (node (ref "U1205") (pin "3") (pinfunction "AGND_3") (pintype "bidirectional"))
      (node (ref "U1205") (pin "8") (pinfunction "PGND_8") (pintype "bidirectional"))
      (node (ref "U1206") (pin "6") (pinfunction "GND_6") (pintype "bidirectional"))
      (node (ref "U1206") (pin "9") (pinfunction "GND_9") (pintype "bidirectional"))
      (node (ref "U1207") (pin "6") (pinfunction "GND_6") (pintype "bidirectional"))
      (node (ref "U1207") (pin "9") (pinfunction "GND_9") (pintype "bidirectional"))
      (node (ref "U1208") (pin "19") (pinfunction "AGND_19") (pintype "bidirectional"))
      (node (ref "U1208") (pin "2") (pinfunction "PGND_2") (pintype "bidirectional"))
      (node (ref "U1208") (pin "21") (pinfunction "PGND_21") (pintype "bidirectional"))
      (node (ref "U1208") (pin "5") (pinfunction "PGND_5") (pintype "bidirectional"))
      (node (ref "U1208") (pin "8") (pinfunction "AGND_8") (pintype "bidirectional"))
      (node (ref "U1209") (pin "10") (pinfunction "PGND_10") (pintype "bidirectional"))
      (node (ref "U1209") (pin "11") (pinfunction "PGND_11") (pintype "bidirectional"))
      (node (ref "U1209") (pin "7") (pinfunction "AGND_7") (pintype "bidirectional"))
      (node (ref "U1210") (pin "2") (pinfunction "GND_2") (pintype "bidirectional"))
      (node (ref "U201") (pin "A11") (pinfunction "GND_A11") (pintype "bidirectional"))
      (node (ref "U201") (pin "A12") (pinfunction "GND_A12") (pintype "bidirectional"))
      (node (ref "U201") (pin "A2") (pinfunction "GND_A2") (pintype "bidirectional"))
      (node (ref "U201") (pin "A22") (pinfunction "GND_A22") (pintype "bidirectional"))
      (node (ref "U201") (pin "A3") (pinfunction "GND_A3") (pintype "bidirectional"))
      (node (ref "U201") (pin "A5") (pinfunction "GND_A5") (pintype "bidirectional"))
      (node (ref "U201") (pin "A7") (pinfunction "GND_A7") (pintype "bidirectional"))
      (node (ref "U201") (pin "A9") (pinfunction "GND_A9") (pintype "bidirectional"))
      (node (ref "U201") (pin "AA12") (pinfunction "GND_AA12") (pintype "bidirectional"))
      (node (ref "U201") (pin "AA2") (pinfunction "GND_AA2") (pintype "bidirectional"))
      (node (ref "U201") (pin "AA22") (pinfunction "GND_AA22") (pintype "bidirectional"))
      (node (ref "U201") (pin "AB19") (pinfunction "GND_AB19") (pintype "bidirectional"))
      (node (ref "U201") (pin "AB9") (pinfunction "GND_AB9") (pintype "bidirectional"))
      (node (ref "U201") (pin "B12") (pinfunction "GND_B12") (pintype "bidirectional"))
      (node (ref "U201") (pin "B19") (pinfunction "GND_B19") (pintype "bidirectional"))
      (node (ref "U201") (pin "B3") (pinfunction "GND_B3") (pintype "bidirectional"))
      (node (ref "U201") (pin "C10") (pinfunction "GND_C10") (pintype "bidirectional"))
      (node (ref "U201") (pin "C11") (pinfunction "MGTPRXN1_C11") (pintype "bidirectional"))
      (node (ref "U201") (pin "C12") (pinfunction "GND_C12") (pintype "bidirectional"))
      (node (ref "U201") (pin "C16") (pinfunction "GND_C16") (pintype "bidirectional"))
      (node (ref "U201") (pin "C3") (pinfunction "GND_C3") (pintype "bidirectional"))
      (node (ref "U201") (pin "C6") (pinfunction "GND_C6") (pintype "bidirectional"))
      (node (ref "U201") (pin "D11") (pinfunction "MGTPRXP1_D11") (pintype "bidirectional"))
      (node (ref "U201") (pin "D12") (pinfunction "GND_D12") (pintype "bidirectional"))
      (node (ref "U201") (pin "D13") (pinfunction "GND_D13") (pintype "bidirectional"))
      (node (ref "U201") (pin "D3") (pinfunction "GND_D3") (pintype "bidirectional"))
      (node (ref "U201") (pin "D4") (pinfunction "GND_D4") (pintype "bidirectional"))
      (node (ref "U201") (pin "D8") (pinfunction "GND_D8") (pintype "bidirectional"))
      (node (ref "U201") (pin "E11") (pinfunction "GND_E11") (pintype "bidirectional"))
      (node (ref "U201") (pin "E20") (pinfunction "GND_E20") (pintype "bidirectional"))
      (node (ref "U201") (pin "E4") (pinfunction "GND_E4") (pintype "bidirectional"))
      (node (ref "U201") (pin "E5") (pinfunction "GND_E5") (pintype "bidirectional"))
      (node (ref "U201") (pin "E7") (pinfunction "GND_E7") (pintype "bidirectional"))
      (node (ref "U201") (pin "E9") (pinfunction "GND_E9") (pintype "bidirectional"))
      (node (ref "U201") (pin "F11") (pinfunction "GND_F11") (pintype "bidirectional"))
      (node (ref "U201") (pin "F17") (pinfunction "GND_F17") (pintype "bidirectional"))
      (node (ref "U201") (pin "F5") (pinfunction "GND_F5") (pintype "bidirectional"))
      (node (ref "U201") (pin "G10") (pinfunction "GND_G10") (pintype "bidirectional"))
      (node (ref "U201") (pin "G12") (pinfunction "GND_G12") (pintype "bidirectional"))
      (node (ref "U201") (pin "G14") (pinfunction "GND_G14") (pintype "bidirectional"))
      (node (ref "U201") (pin "G5") (pinfunction "GND_G5") (pintype "bidirectional"))
      (node (ref "U201") (pin "G6") (pinfunction "GND_G6") (pintype "bidirectional"))
      (node (ref "U201") (pin "G7") (pinfunction "GND_G7") (pintype "bidirectional"))
      (node (ref "U201") (pin "G8") (pinfunction "GND_G8") (pintype "bidirectional"))
      (node (ref "U201") (pin "G9") (pinfunction "GND_G9") (pintype "bidirectional"))
      (node (ref "U201") (pin "H1") (pinfunction "GND_H1") (pintype "bidirectional"))
      (node (ref "U201") (pin "H11") (pinfunction "GND_H11") (pintype "bidirectional"))
      (node (ref "U201") (pin "H19") (pinfunction "IO_L12N/T1/MRCC_H19") (pintype "bidirectional"))
      (node (ref "U201") (pin "H20") (pinfunction "IO_L8P/T1/AD10P_H20") (pintype "bidirectional"))
      (node (ref "U201") (pin "H21") (pinfunction "GND_H21") (pintype "bidirectional"))
      (node (ref "U201") (pin "H22") (pinfunction "IO_L7N/T1/AD2N_H22") (pintype "bidirectional"))
      (node (ref "U201") (pin "H7") (pinfunction "GND_H7") (pintype "bidirectional"))
      (node (ref "U201") (pin "H9") (pinfunction "GND_H9") (pintype "bidirectional"))
      (node (ref "U201") (pin "J10") (pinfunction "GND_J10") (pintype "bidirectional"))
      (node (ref "U201") (pin "J12") (pinfunction "GND_J12") (pintype "bidirectional"))
      (node (ref "U201") (pin "J18") (pinfunction "GND_J18") (pintype "bidirectional"))
      (node (ref "U201") (pin "J8") (pinfunction "GND_J8") (pintype "bidirectional"))
      (node (ref "U201") (pin "K11") (pinfunction "GND_K11") (pintype "bidirectional"))
      (node (ref "U201") (pin "K15") (pinfunction "GND_K15") (pintype "bidirectional"))
      (node (ref "U201") (pin "K5") (pinfunction "GND_K5") (pintype "bidirectional"))
      (node (ref "U201") (pin "K7") (pinfunction "GND_K7") (pintype "bidirectional"))
      (node (ref "U201") (pin "K9") (pinfunction "GNDADC_K9") (pintype "bidirectional"))
      (node (ref "U201") (pin "L10") (pinfunction "VP_L10") (pintype "bidirectional"))
      (node (ref "U201") (pin "L2") (pinfunction "GND_L2") (pintype "bidirectional"))
      (node (ref "U201") (pin "L22") (pinfunction "GND_L22") (pintype "bidirectional"))
      (node (ref "U201") (pin "L8") (pinfunction "GND_L8") (pintype "bidirectional"))
      (node (ref "U201") (pin "L9") (pinfunction "VREFN_L9") (pintype "bidirectional"))
      (node (ref "U201") (pin "M10") (pinfunction "VREFP_M10") (pintype "bidirectional"))
      (node (ref "U201") (pin "M11") (pinfunction "GND_M11") (pintype "bidirectional"))
      (node (ref "U201") (pin "M19") (pinfunction "GND_M19") (pintype "bidirectional"))
      (node (ref "U201") (pin "M20") (pinfunction "IO_L18N/T2/A23_M20") (pintype "bidirectional"))
      (node (ref "U201") (pin "M21") (pinfunction "IO_L10P/T1/AD11P_M21") (pintype "bidirectional"))
      (node (ref "U201") (pin "M7") (pinfunction "GND_M7") (pintype "bidirectional"))
      (node (ref "U201") (pin "M9") (pinfunction "VN_M9") (pintype "bidirectional"))
      (node (ref "U201") (pin "N10") (pinfunction "DXP_N10") (pintype "bidirectional"))
      (node (ref "U201") (pin "N16") (pinfunction "GND_N16") (pintype "bidirectional"))
      (node (ref "U201") (pin "N6") (pinfunction "GND_N6") (pintype "bidirectional"))
      (node (ref "U201") (pin "N8") (pinfunction "GND_N8") (pintype "bidirectional"))
      (node (ref "U201") (pin "N9") (pinfunction "DXN_N9") (pintype "bidirectional"))
      (node (ref "U201") (pin "P11") (pinfunction "GND_P11") (pintype "bidirectional"))
      (node (ref "U201") (pin "P13") (pinfunction "GND_P13") (pintype "bidirectional"))
      (node (ref "U201") (pin "P3") (pinfunction "GND_P3") (pintype "bidirectional"))
      (node (ref "U201") (pin "P7") (pinfunction "GND_P7") (pintype "bidirectional"))
      (node (ref "U201") (pin "P9") (pinfunction "GND_P9") (pintype "bidirectional"))
      (node (ref "U201") (pin "R10") (pinfunction "GND_R10") (pintype "bidirectional"))
      (node (ref "U201") (pin "R12") (pinfunction "GND_R12") (pintype "bidirectional"))
      (node (ref "U201") (pin "R20") (pinfunction "GND_R20") (pintype "bidirectional"))
      (node (ref "U201") (pin "R8") (pinfunction "GND_R8") (pintype "bidirectional"))
      (node (ref "U201") (pin "T11") (pinfunction "GND_T11") (pintype "bidirectional"))
      (node (ref "U201") (pin "T17") (pinfunction "GND_T17") (pintype "bidirectional"))
      (node (ref "U201") (pin "T7") (pinfunction "GND_T7") (pintype "bidirectional"))
      (node (ref "U201") (pin "T9") (pinfunction "GND_T9") (pintype "bidirectional"))
      (node (ref "U201") (pin "U10") (pinfunction "M1_U10") (pintype "bidirectional"))
      (node (ref "U201") (pin "U14") (pinfunction "GND_U14") (pintype "bidirectional"))
      (node (ref "U201") (pin "U22") (pinfunction "IO_L3P/T0_DQS/~{PUDC}_U22") (pintype "bidirectional"))
      (node (ref "U201") (pin "U4") (pinfunction "GND_U4") (pintype "bidirectional"))
      (node (ref "U201") (pin "V1") (pinfunction "GND_V1") (pintype "bidirectional"))
      (node (ref "U201") (pin "V11") (pinfunction "GND_V11") (pintype "bidirectional"))
      (node (ref "U201") (pin "V21") (pinfunction "GND_V21") (pintype "bidirectional"))
      (node (ref "U201") (pin "W18") (pinfunction "GND_W18") (pintype "bidirectional"))
      (node (ref "U201") (pin "W8") (pinfunction "GND_W8") (pintype "bidirectional"))
      (node (ref "U201") (pin "Y15") (pinfunction "GND_Y15") (pintype "bidirectional"))
      (node (ref "U201") (pin "Y5") (pinfunction "GND_Y5") (pintype "bidirectional"))
      (node (ref "U202") (pin "4") (pinfunction "GND_4") (pintype "power_in"))
      (node (ref "U301") (pin "A9") (pinfunction "VSS_A9") (pintype "bidirectional"))
      (node (ref "U301") (pin "B1") (pinfunction "VSSQ_B1") (pintype "bidirectional"))
      (node (ref "U301") (pin "B3") (pinfunction "VSS_B3") (pintype "bidirectional"))
      (node (ref "U301") (pin "B9") (pinfunction "VSSQ_B9") (pintype "bidirectional"))
      (node (ref "U301") (pin "D1") (pinfunction "VSSQ_D1") (pintype "bidirectional"))
      (node (ref "U301") (pin "D8") (pinfunction "VSSQ_D8") (pintype "bidirectional"))
      (node (ref "U301") (pin "E1") (pinfunction "VSS_E1") (pintype "bidirectional"))
      (node (ref "U301") (pin "E2") (pinfunction "VSSQ_E2") (pintype "bidirectional"))
      (node (ref "U301") (pin "E8") (pinfunction "VSSQ_E8") (pintype "bidirectional"))
      (node (ref "U301") (pin "F9") (pinfunction "VSSQ_F9") (pintype "bidirectional"))
      (node (ref "U301") (pin "G1") (pinfunction "VSSQ_G1") (pintype "bidirectional"))
      (node (ref "U301") (pin "G8") (pinfunction "VSS_G8") (pintype "bidirectional"))
      (node (ref "U301") (pin "G9") (pinfunction "VSSQ_G9") (pintype "bidirectional"))
      (node (ref "U301") (pin "J2") (pinfunction "VSS_J2") (pintype "bidirectional"))
      (node (ref "U301") (pin "J8") (pinfunction "VSS_J8") (pintype "bidirectional"))
      (node (ref "U301") (pin "L2") (pinfunction "~{CS}_L2") (pintype "bidirectional"))
      (node (ref "U301") (pin "M1") (pinfunction "VSS_M1") (pintype "bidirectional"))
      (node (ref "U301") (pin "M9") (pinfunction "VSS_M9") (pintype "bidirectional"))
      (node (ref "U301") (pin "P1") (pinfunction "VSS_P1") (pintype "bidirectional"))
      (node (ref "U301") (pin "P9") (pinfunction "VSS_P9") (pintype "bidirectional"))
      (node (ref "U301") (pin "T1") (pinfunction "VSS_T1") (pintype "bidirectional"))
      (node (ref "U301") (pin "T9") (pinfunction "VSS_T9") (pintype "bidirectional"))
      (node (ref "U401") (pin "A12") (pinfunction "TX_EXT_LO_IN_A12") (pintype "bidirectional"))
      (node (ref "U401") (pin "A4") (pinfunction "VSSA_A4") (pintype "bidirectional"))
      (node (ref "U401") (pin "A6") (pinfunction "VSSA_A6") (pintype "bidirectional"))
      (node (ref "U401") (pin "B1") (pinfunction "VSSA_B1") (pintype "bidirectional"))
      (node (ref "U401") (pin "B12") (pinfunction "VSSA_B12") (pintype "bidirectional"))
      (node (ref "U401") (pin "B2") (pinfunction "VSSA_B2") (pintype "bidirectional"))
      (node (ref "U401") (pin "C10") (pinfunction "VSSA_C10") (pintype "bidirectional"))
      (node (ref "U401") (pin "C11") (pinfunction "VSSA_C11") (pintype "bidirectional"))
      (node (ref "U401") (pin "C12") (pinfunction "VSSA_C12") (pintype "bidirectional"))
      (node (ref "U401") (pin "C2") (pinfunction "VSSA_C2") (pintype "bidirectional"))
      (node (ref "U401") (pin "C4") (pinfunction "TEST/~{ENABLE}_C4") (pintype "bidirectional"))
      (node (ref "U401") (pin "C7") (pinfunction "VSSA_C7") (pintype "bidirectional"))
      (node (ref "U401") (pin "C8") (pinfunction "VSSA_C8") (pintype "bidirectional"))
      (node (ref "U401") (pin "C9") (pinfunction "VSSA_C9") (pintype "bidirectional"))
      (node (ref "U401") (pin "D12") (pinfunction "VSSD_D12") (pintype "bidirectional"))
      (node (ref "U401") (pin "E1") (pinfunction "RX2B_P_E1") (pintype "bidirectional"))
      (node (ref "U401") (pin "F1") (pinfunction "RX2B_N_F1") (pintype "bidirectional"))
      (node (ref "U401") (pin "F11") (pinfunction "VSSD_F11") (pintype "bidirectional"))
      (node (ref "U401") (pin "F3") (pinfunction "VSSA_F3") (pintype "bidirectional"))
      (node (ref "U401") (pin "F7") (pinfunction "VSSD_F7") (pintype "bidirectional"))
      (node (ref "U401") (pin "F9") (pinfunction "VSSD_F9") (pintype "bidirectional"))
      (node (ref "U401") (pin "G1") (pinfunction "RX_EXT_LO_IN_G1") (pintype "bidirectional"))
      (node (ref "U401") (pin "G10") (pinfunction "FB_CLK_N_G10") (pintype "bidirectional"))
      (node (ref "U401") (pin "G12") (pinfunction "VSSD_G12") (pintype "bidirectional"))
      (node (ref "U401") (pin "H1") (pinfunction "RX1B_P_H1") (pintype "bidirectional"))
      (node (ref "U401") (pin "H10") (pinfunction "VSSD_H10") (pintype "bidirectional"))
      (node (ref "U401") (pin "H2") (pinfunction "VSSA_H2") (pintype "bidirectional"))
      (node (ref "U401") (pin "H3") (pinfunction "VSSA_H3") (pintype "bidirectional"))
      (node (ref "U401") (pin "H6") (pinfunction "VSSA_H6") (pintype "bidirectional"))
      (node (ref "U401") (pin "H7") (pinfunction "VSSD_H7") (pintype "bidirectional"))
      (node (ref "U401") (pin "H9") (pinfunction "TX_FRAME_N_H9") (pintype "bidirectional"))
      (node (ref "U401") (pin "J1") (pinfunction "RX1B_N_J1") (pintype "bidirectional"))
      (node (ref "U401") (pin "J2") (pinfunction "VSSA_J2") (pintype "bidirectional"))
      (node (ref "U401") (pin "K12") (pinfunction "VSSD_K12") (pintype "bidirectional"))
      (node (ref "U401") (pin "K2") (pinfunction "VSSA_K2") (pintype "bidirectional"))
      (node (ref "U401") (pin "L10") (pinfunction "VSSA_L10") (pintype "bidirectional"))
      (node (ref "U401") (pin "L11") (pinfunction "VSSA_L11") (pintype "bidirectional"))
      (node (ref "U401") (pin "L12") (pinfunction "VSSA_L12") (pintype "bidirectional"))
      (node (ref "U401") (pin "L2") (pinfunction "VSSA_L2") (pintype "bidirectional"))
      (node (ref "U401") (pin "L3") (pinfunction "VSSA_L3") (pintype "bidirectional"))
      (node (ref "U401") (pin "L5") (pinfunction "AUXADC_L5") (pintype "bidirectional"))
      (node (ref "U401") (pin "L7") (pinfunction "VSSA_L7") (pintype "bidirectional"))
      (node (ref "U401") (pin "L8") (pinfunction "VSSA_L8") (pintype "bidirectional"))
      (node (ref "U401") (pin "L9") (pinfunction "VSSA_L9") (pintype "bidirectional"))
      (node (ref "U401") (pin "M4") (pinfunction "VSSA_M4") (pintype "bidirectional"))
      (node (ref "U401") (pin "M6") (pinfunction "VSSA_M6") (pintype "bidirectional"))
      (node (ref "U501") (pin "2") (pinfunction "GND_2") (pintype "bidirectional"))
      (node (ref "U502") (pin "2") (pinfunction "GND_2") (pintype "bidirectional"))
      (node (ref "U503") (pin "2") (pinfunction "GND_2") (pintype "bidirectional"))
      (node (ref "U504") (pin "2") (pinfunction "GND_2") (pintype "bidirectional"))
      (node (ref "U505") (pin "2") (pinfunction "GND_2") (pintype "bidirectional"))
      (node (ref "U505") (pin "4") (pinfunction "GND_4") (pintype "bidirectional"))
      (node (ref "U506") (pin "2") (pinfunction "GND_2") (pintype "bidirectional"))
      (node (ref "U506") (pin "4") (pinfunction "GND_4") (pintype "bidirectional"))
      (node (ref "U601") (pin "14") (pinfunction "VSSPDCP_14") (pintype "bidirectional"))
      (node (ref "U601") (pin "17") (pinfunction "VSSFB_17") (pintype "bidirectional"))
      (node (ref "U601") (pin "19") (pinfunction "VSSDIG_19") (pintype "bidirectional"))
      (node (ref "U601") (pin "20") (pinfunction "VSSIN_20") (pintype "bidirectional"))
      (node (ref "U601") (pin "38") (pinfunction "VSSOUTA_38") (pintype "bidirectional"))
      (node (ref "U601") (pin "41") (pinfunction "VSSOUTA_41") (pintype "bidirectional"))
      (node (ref "U601") (pin "44") (pinfunction "VSSOUTB_44") (pintype "bidirectional"))
      (node (ref "U601") (pin "47") (pinfunction "VSSOUTB_47") (pintype "bidirectional"))
      (node (ref "U601") (pin "49") (pinfunction "VSS_49") (pintype "bidirectional"))
      (node (ref "U701") (pin "11") (pinfunction "AGND_11") (pintype "bidirectional"))
      (node (ref "U701") (pin "20") (pinfunction "AGND_20") (pintype "bidirectional"))
      (node (ref "U701") (pin "23") (pinfunction "AGND_23") (pintype "bidirectional"))
      (node (ref "U701") (pin "3") (pinfunction "ADDR1/MOSI_3") (pintype "bidirectional"))
      (node (ref "U701") (pin "30") (pinfunction "DGND_30") (pintype "bidirectional"))
      (node (ref "U701") (pin "4") (pinfunction "ADDR0/~{SS}_4") (pintype "bidirectional"))
      (node (ref "U701") (pin "41") (pinfunction "DGND_41") (pintype "bidirectional"))
      (node (ref "U701") (pin "5") (pinfunction "DGND_5") (pintype "bidirectional"))
      (node (ref "U901") (pin "1") (pinfunction "GND_1") (pintype "power_in"))
      (node (ref "U901") (pin "2") (pinfunction "GND_2") (pintype "power_in"))
      (node (ref "U902") (pin "21") (pinfunction "GND_21") (pintype "bidirectional"))
      (node (ref "USB1001") (pin "A1/B12") (pinfunction "GND_A1/B12") (pintype "bidirectional"))
      (node (ref "USB1001") (pin "B1/A12") (pinfunction "GND_B1/A12") (pintype "bidirectional"))
    )
    (net (code "175") (name "Net-(C105-C1)") (class "Default")
      (node (ref "C105") (pin "1") (pinfunction "C1_1") (pintype "passive"))
      (node (ref "SD101") (pin "4") (pinfunction "VDD_4") (pintype "power_in"))
      (node (ref "U101") (pin "6") (pinfunction "VOUT_6") (pintype "bidirectional"))
    )
    (net (code "176") (name "Net-(C107-C1)") (class "Default")
      (node (ref "C107") (pin "1") (pinfunction "C1_1") (pintype "passive"))
      (node (ref "J101") (pin "1") (pinfunction "CT_1") (pintype "bidirectional"))
    )
    (net (code "177") (name "Net-(C323-C1)") (class "Default")
      (node (ref "C323") (pin "1") (pinfunction "C1_1") (pintype "passive"))
      (node (ref "R311") (pin "1") (pinfunction "1_1") (pintype "passive"))
      (node (ref "R319") (pin "2") (pinfunction "2_2") (pintype "passive"))
    )
    (net (code "178") (name "Net-(C402-C1)") (class "Default")
      (node (ref "C402") (pin "1") (pinfunction "C1_1") (pintype "passive"))
      (node (ref "C403") (pin "1") (pinfunction "C1_1") (pintype "passive"))
      (node (ref "R401") (pin "1") (pinfunction "1_1") (pintype "passive"))
      (node (ref "R402") (pin "2") (pinfunction "2_2") (pintype "passive"))
    )
    (net (code "179") (name "Net-(C403-C2)") (class "Default")
      (node (ref "C403") (pin "2") (pinfunction "C2_2") (pintype "passive"))
      (node (ref "U401") (pin "M12") (pinfunction "XTALN_M12") (pintype "bidirectional"))
    )
    (net (code "180") (name "Net-(C406-C1)") (class "Default")
      (node (ref "C406") (pin "1") (pinfunction "C1_1") (pintype "passive"))
      (node (ref "C409") (pin "1") (pinfunction "C1_1") (pintype "passive"))
      (node (ref "C412") (pin "1") (pinfunction "C1_1") (pintype "passive"))
      (node (ref "C415") (pin "1") (pinfunction "C1_1") (pintype "passive"))
      (node (ref "C418") (pin "1") (pinfunction "C1_1") (pintype "passive"))
      (node (ref "FB401") (pin "2") (pinfunction "2_2") (pintype "passive"))
      (node (ref "U401") (pin "B8") (pinfunction "VDD_GPO_B8") (pintype "bidirectional"))
      (node (ref "U401") (pin "H12") (pinfunction "VDD_INTERFACE_H12") (pintype "bidirectional"))
    )
    (net (code "181") (name "Net-(C421-C1)") (class "Default")
      (node (ref "C421") (pin "1") (pinfunction "C1_1") (pintype "passive"))
      (node (ref "C422") (pin "1") (pinfunction "C1_1") (pintype "passive"))
      (node (ref "U401") (pin "A11") (pinfunction "VDDA1P1_TX_VCO_A11") (pintype "bidirectional"))
      (node (ref "U401") (pin "B11") (pinfunction "TX_VCO_LDO_OUT_B11") (pintype "bidirectional"))
    )
    (net (code "182") (name "Net-(C421-C2)") (class "Default")
      (node (ref "C421") (pin "2") (pinfunction "C2_2") (pintype "passive"))
      (node (ref "R404") (pin "2") (pinfunction "2_2") (pintype "passive"))
    )
    (net (code "183") (name "Net-(C423-C1)") (class "Default")
      (node (ref "C423") (pin "1") (pinfunction "C1_1") (pintype "passive"))
      (node (ref "C424") (pin "1") (pinfunction "C1_1") (pintype "passive"))
      (node (ref "U401") (pin "G2") (pinfunction "RX_VCO_LDO_OUT_G2") (pintype "bidirectional"))
      (node (ref "U401") (pin "G3") (pinfunction "VDDA1P1_RX_VCO_G3") (pintype "bidirectional"))
    )
    (net (code "184") (name "Net-(C423-C2)") (class "Default")
      (node (ref "C423") (pin "2") (pinfunction "C2_2") (pintype "passive"))
      (node (ref "R405") (pin "2") (pinfunction "2_2") (pintype "passive"))
    )
    (net (code "185") (name "Net-(C501-C1)") (class "Default")
      (node (ref "C501") (pin "1") (pinfunction "C1_1") (pintype "passive"))
      (node (ref "D503") (pin "1") (pinfunction "1_1") (pintype "passive"))
      (node (ref "L501") (pin "2") (pinfunction "2_2") (pintype "passive"))
      (node (ref "RFCON503") (pin "SIGNAL") (pinfunction "SIGNAL_SIGNAL") (pintype "bidirectional"))
    )
    (net (code "186") (name "Net-(C501-C2)") (class "Default")
      (node (ref "C501") (pin "2") (pinfunction "C2_2") (pintype "passive"))
      (node (ref "T503") (pin "3") (pinfunction "PRI1_3") (pintype "passive"))
    )
    (net (code "187") (name "Net-(C502-C1)") (class "Default")
      (node (ref "C502") (pin "1") (pinfunction "C1_1") (pintype "passive"))
      (node (ref "D504") (pin "1") (pinfunction "1_1") (pintype "passive"))
      (node (ref "L502") (pin "2") (pinfunction "2_2") (pintype "passive"))
      (node (ref "RFCON504") (pin "SIGNAL") (pinfunction "SIGNAL_SIGNAL") (pintype "bidirectional"))
    )
    (net (code "188") (name "Net-(C502-C2)") (class "Default")
      (node (ref "C502") (pin "2") (pinfunction "C2_2") (pintype "passive"))
      (node (ref "T504") (pin "3") (pinfunction "PRI1_3") (pintype "passive"))
    )
    (net (code "189") (name "Net-(C509-C1)") (class "Default")
      (node (ref "C509") (pin "1") (pinfunction "C1_1") (pintype "passive"))
      (node (ref "T501") (pin "5") (pinfunction "SEC1_5") (pintype "passive"))
    )
    (net (code "190") (name "Net-(C510-C1)") (class "Default")
      (node (ref "C510") (pin "1") (pinfunction "C1_1") (pintype "passive"))
      (node (ref "T501") (pin "4") (pinfunction "SEC2_4") (pintype "passive"))
    )
    (net (code "191") (name "Net-(C511-C1)") (class "Default")
      (node (ref "C511") (pin "1") (pinfunction "C1_1") (pintype "passive"))
      (node (ref "T502") (pin "5") (pinfunction "SEC1_5") (pintype "passive"))
    )
    (net (code "192") (name "Net-(C512-C1)") (class "Default")
      (node (ref "C512") (pin "1") (pinfunction "C1_1") (pintype "passive"))
      (node (ref "T502") (pin "4") (pinfunction "SEC2_4") (pintype "passive"))
    )
    (net (code "193") (name "Net-(C513-C1)") (class "Default")
      (node (ref "C513") (pin "1") (pinfunction "C1_1") (pintype "passive"))
      (node (ref "T503") (pin "5") (pinfunction "SEC1_5") (pintype "passive"))
    )
    (net (code "194") (name "Net-(C514-C1)") (class "Default")
      (node (ref "C514") (pin "1") (pinfunction "C1_1") (pintype "passive"))
      (node (ref "T503") (pin "4") (pinfunction "SEC2_4") (pintype "passive"))
    )
    (net (code "195") (name "Net-(C515-C1)") (class "Default")
      (node (ref "C515") (pin "1") (pinfunction "C1_1") (pintype "passive"))
      (node (ref "T504") (pin "5") (pinfunction "SEC1_5") (pintype "passive"))
    )
    (net (code "196") (name "Net-(C516-C1)") (class "Default")
      (node (ref "C516") (pin "1") (pinfunction "C1_1") (pintype "passive"))
      (node (ref "T504") (pin "4") (pinfunction "SEC2_4") (pintype "passive"))
    )
    (net (code "197") (name "Net-(C529-C1)") (class "Default")
      (node (ref "C529") (pin "1") (pinfunction "C1_1") (pintype "passive"))
      (node (ref "R514") (pin "1") (pinfunction "1_1") (pintype "passive"))
    )
    (net (code "198") (name "Net-(C530-C2)") (class "Default")
      (node (ref "C530") (pin "2") (pinfunction "C2_2") (pintype "passive"))
      (node (ref "T505") (pin "5") (pinfunction "SEC1_5") (pintype "passive"))
    )
    (net (code "199") (name "Net-(C531-C2)") (class "Default")
      (node (ref "C531") (pin "2") (pinfunction "C2_2") (pintype "passive"))
      (node (ref "T505") (pin "4") (pinfunction "SEC2_4") (pintype "passive"))
    )
    (net (code "200") (name "Net-(C532-C2)") (class "Default")
      (node (ref "C532") (pin "2") (pinfunction "C2_2") (pintype "passive"))
      (node (ref "T506") (pin "5") (pinfunction "SEC1_5") (pintype "passive"))
    )
    (net (code "201") (name "Net-(C533-C2)") (class "Default")
      (node (ref "C533") (pin "2") (pinfunction "C2_2") (pintype "passive"))
      (node (ref "T506") (pin "4") (pinfunction "SEC2_4") (pintype "passive"))
    )
    (net (code "202") (name "Net-(C538-C1)") (class "Default")
      (node (ref "C538") (pin "1") (pinfunction "C1_1") (pintype "passive"))
      (node (ref "T505") (pin "3") (pinfunction "PRI1_3") (pintype "passive"))
    )
    (net (code "203") (name "Net-(C538-C2)") (class "Default")
      (node (ref "C538") (pin "2") (pinfunction "C2_2") (pintype "passive"))
      (node (ref "U505") (pin "1") (pinfunction "RFIN_1") (pintype "bidirectional"))
    )
    (net (code "204") (name "Net-(C539-C1)") (class "Default")
      (node (ref "C539") (pin "1") (pinfunction "C1_1") (pintype "passive"))
      (node (ref "T506") (pin "3") (pinfunction "PRI1_3") (pintype "passive"))
    )
    (net (code "205") (name "Net-(C539-C2)") (class "Default")
      (node (ref "C539") (pin "2") (pinfunction "C2_2") (pintype "passive"))
      (node (ref "U506") (pin "1") (pinfunction "RFIN_1") (pintype "bidirectional"))
    )
    (net (code "206") (name "Net-(C544-C2)") (class "Default")
      (node (ref "C544") (pin "2") (pinfunction "C2_2") (pintype "passive"))
      (node (ref "T507") (pin "5") (pinfunction "SEC1_5") (pintype "passive"))
    )
    (net (code "207") (name "Net-(C545-C2)") (class "Default")
      (node (ref "C545") (pin "2") (pinfunction "C2_2") (pintype "passive"))
      (node (ref "T507") (pin "4") (pinfunction "SEC2_4") (pintype "passive"))
    )
    (net (code "208") (name "Net-(C546-C2)") (class "Default")
      (node (ref "C546") (pin "2") (pinfunction "C2_2") (pintype "passive"))
      (node (ref "T508") (pin "5") (pinfunction "SEC1_5") (pintype "passive"))
    )
    (net (code "209") (name "Net-(C547-C2)") (class "Default")
      (node (ref "C547") (pin "2") (pinfunction "C2_2") (pintype "passive"))
      (node (ref "T508") (pin "4") (pinfunction "SEC2_4") (pintype "passive"))
    )
    (net (code "210") (name "Net-(C550-C1)") (class "Default")
      (node (ref "C550") (pin "1") (pinfunction "C1_1") (pintype "passive"))
      (node (ref "R516") (pin "1") (pinfunction "1_1") (pintype "passive"))
    )
    (net (code "211") (name "Net-(C553-C1)") (class "Default")
      (node (ref "C553") (pin "1") (pinfunction "C1_1") (pintype "passive"))
      (node (ref "L511") (pin "2") (pinfunction "2_2") (pintype "passive"))
      (node (ref "U505") (pin "3") (pinfunction "RFOUT_3") (pintype "bidirectional"))
    )
    (net (code "212") (name "Net-(C553-C2)") (class "Default")
      (node (ref "C553") (pin "2") (pinfunction "C2_2") (pintype "passive"))
      (node (ref "D511") (pin "1") (pinfunction "1_1") (pintype "passive"))
      (node (ref "RFCON509") (pin "SIGNAL") (pinfunction "SIGNAL_SIGNAL") (pintype "bidirectional"))
    )
    (net (code "213") (name "Net-(C554-C1)") (class "Default")
      (node (ref "C554") (pin "1") (pinfunction "C1_1") (pintype "passive"))
      (node (ref "L512") (pin "2") (pinfunction "2_2") (pintype "passive"))
      (node (ref "U506") (pin "3") (pinfunction "RFOUT_3") (pintype "bidirectional"))
    )
    (net (code "214") (name "Net-(C554-C2)") (class "Default")
      (node (ref "C554") (pin "2") (pinfunction "C2_2") (pintype "passive"))
      (node (ref "D512") (pin "1") (pinfunction "1_1") (pintype "passive"))
      (node (ref "RFCON510") (pin "SIGNAL") (pinfunction "SIGNAL_SIGNAL") (pintype "bidirectional"))
    )
    (net (code "215") (name "Net-(C601-C2)") (class "Default")
      (node (ref "C601") (pin "2") (pinfunction "C2_2") (pintype "passive"))
      (node (ref "R604") (pin "1") (pinfunction "1_1") (pintype "passive"))
      (node (ref "R605") (pin "2") (pinfunction "2_2") (pintype "passive"))
      (node (ref "U601") (pin "22") (pinfunction "REF_IN_22") (pintype "bidirectional"))
    )
    (net (code "216") (name "Net-(C603-C1)") (class "Default")
      (node (ref "C603") (pin "1") (pinfunction "C1_1") (pintype "passive"))
      (node (ref "R606") (pin "1") (pinfunction "1_1") (pintype "passive"))
      (node (ref "R607") (pin "2") (pinfunction "2_2") (pintype "passive"))
      (node (ref "U601") (pin "23") (pinfunction "~{REF_IN}_23") (pintype "bidirectional"))
    )
    (net (code "217") (name "Net-(C606-C1)") (class "Default")
      (node (ref "C606") (pin "1") (pinfunction "C1_1") (pintype "passive"))
      (node (ref "U601") (pin "32") (pinfunction "VREGVCO1_32") (pintype "bidirectional"))
    )
    (net (code "218") (name "Net-(C609-C1)") (class "Default")
      (node (ref "C609") (pin "1") (pinfunction "C1_1") (pintype "passive"))
      (node (ref "U601") (pin "4") (pinfunction "VREGVCO2_4") (pintype "bidirectional"))
    )
    (net (code "219") (name "Net-(C612-C1)") (class "Default")
      (node (ref "C612") (pin "1") (pinfunction "C1_1") (pintype "passive"))
      (node (ref "U601") (pin "35") (pinfunction "VREFVCO1_35") (pintype "bidirectional"))
    )
    (net (code "220") (name "Net-(C613-C1)") (class "Default")
      (node (ref "C613") (pin "1") (pinfunction "C1_1") (pintype "passive"))
      (node (ref "U601") (pin "1") (pinfunction "VREFVCO2_1") (pintype "bidirectional"))
    )
    (net (code "221") (name "Net-(C614-C1)") (class "Default")
      (node (ref "C614") (pin "1") (pinfunction "C1_1") (pintype "passive"))
      (node (ref "U601") (pin "11") (pinfunction "CPBIAS_11") (pintype "bidirectional"))
    )
    (net (code "222") (name "Net-(C615-C1)") (class "Default")
      (node (ref "C615") (pin "1") (pinfunction "C1_1") (pintype "passive"))
      (node (ref "FB601") (pin "2") (pinfunction "2_2") (pintype "passive"))
      (node (ref "U601") (pin "18") (pinfunction "VDDDIG_18") (pintype "bidirectional"))
    )
    (net (code "223") (name "Net-(C616-C1)") (class "Default")
      (node (ref "C616") (pin "1") (pinfunction "C1_1") (pintype "passive"))
      (node (ref "R608") (pin "1") (pinfunction "1_1") (pintype "passive"))
    )
    (net (code "224") (name "Net-(C617-C1)") (class "Default")
      (node (ref "C617") (pin "1") (pinfunction "C1_1") (pintype "passive"))
      (node (ref "R608") (pin "2") (pinfunction "2_2") (pintype "passive"))
      (node (ref "R609") (pin "2") (pinfunction "2_2") (pintype "passive"))
      (node (ref "U601") (pin "10") (pinfunction "CPOUT_10") (pintype "bidirectional"))
    )
    (net (code "225") (name "Net-(C618-C1)") (class "Default")
      (node (ref "C618") (pin "1") (pinfunction "C1_1") (pintype "passive"))
      (node (ref "R609") (pin "1") (pinfunction "1_1") (pintype "passive"))
      (node (ref "U601") (pin "5") (pinfunction "VTUNE_5") (pintype "bidirectional"))
    )
    (net (code "226") (name "Net-(C619-C1)") (class "Default")
      (node (ref "C619") (pin "1") (pinfunction "C1_1") (pintype "passive"))
      (node (ref "C621") (pin "1") (pinfunction "C1_1") (pintype "passive"))
      (node (ref "L601") (pin "2") (pinfunction "2_2") (pintype "passive"))
      (node (ref "R610") (pin "2") (pinfunction "2_2") (pintype "passive"))
      (node (ref "R612") (pin "2") (pinfunction "2_2") (pintype "passive"))
    )
    (net (code "227") (name "Net-(C620-C1)") (class "Default")
      (node (ref "C620") (pin "1") (pinfunction "C1_1") (pintype "passive"))
      (node (ref "C622") (pin "1") (pinfunction "C1_1") (pintype "passive"))
      (node (ref "L602") (pin "2") (pinfunction "2_2") (pintype "passive"))
      (node (ref "R611") (pin "2") (pinfunction "2_2") (pintype "passive"))
      (node (ref "R613") (pin "2") (pinfunction "2_2") (pintype "passive"))
    )
    (net (code "228") (name "Net-(C623-C1)") (class "Default")
      (node (ref "C623") (pin "1") (pinfunction "C1_1") (pintype "passive"))
      (node (ref "R612") (pin "1") (pinfunction "1_1") (pintype "passive"))
      (node (ref "U601") (pin "39") (pinfunction "~{RF_OUTA}_39") (pintype "bidirectional"))
    )
    (net (code "229") (name "Net-(C623-C2)") (class "Default")
      (node (ref "C623") (pin "2") (pinfunction "C2_2") (pintype "passive"))
      (node (ref "R614") (pin "2") (pinfunction "2_2") (pintype "passive"))
    )
    (net (code "230") (name "Net-(C624-C1)") (class "Default")
      (node (ref "C624") (pin "1") (pinfunction "C1_1") (pintype "passive"))
      (node (ref "R613") (pin "1") (pinfunction "1_1") (pintype "passive"))
      (node (ref "U601") (pin "46") (pinfunction "~{RF_OUTB}_46") (pintype "bidirectional"))
    )
    (net (code "231") (name "Net-(C624-C2)") (class "Default")
      (node (ref "C624") (pin "2") (pinfunction "C2_2") (pintype "passive"))
      (node (ref "R615") (pin "2") (pinfunction "2_2") (pintype "passive"))
    )
    (net (code "232") (name "Net-(C625-C1)") (class "Default")
      (node (ref "C625") (pin "1") (pinfunction "C1_1") (pintype "passive"))
      (node (ref "R610") (pin "1") (pinfunction "1_1") (pintype "passive"))
      (node (ref "U601") (pin "40") (pinfunction "RF_OUTA_40") (pintype "bidirectional"))
    )
    (net (code "233") (name "Net-(C625-C2)") (class "Default")
      (node (ref "C625") (pin "2") (pinfunction "C2_2") (pintype "passive"))
      (node (ref "D601") (pin "1") (pinfunction "1_1") (pintype "passive"))
      (node (ref "RFCON601") (pin "SIGNAL") (pinfunction "SIGNAL_SIGNAL") (pintype "bidirectional"))
    )
    (net (code "234") (name "Net-(C626-C1)") (class "Default")
      (node (ref "C626") (pin "1") (pinfunction "C1_1") (pintype "passive"))
      (node (ref "R611") (pin "1") (pinfunction "1_1") (pintype "passive"))
      (node (ref "U601") (pin "45") (pinfunction "RF_OUTB_45") (pintype "bidirectional"))
    )
    (net (code "235") (name "Net-(C626-C2)") (class "Default")
      (node (ref "C626") (pin "2") (pinfunction "C2_2") (pintype "passive"))
      (node (ref "D602") (pin "1") (pinfunction "1_1") (pintype "passive"))
      (node (ref "RFCON602") (pin "SIGNAL") (pinfunction "SIGNAL_SIGNAL") (pintype "bidirectional"))
    )
    (net (code "236") (name "Net-(C707-C1)") (class "Default")
      (node (ref "C707") (pin "1") (pinfunction "C1_1") (pintype "passive"))
      (node (ref "FB701") (pin "1") (pinfunction "1_1") (pintype "passive"))
      (node (ref "U701") (pin "40") (pinfunction "IOVDD_40") (pintype "bidirectional"))
    )
    (net (code "237") (name "Net-(C709-C1)") (class "Default")
      (node (ref "C709") (pin "1") (pinfunction "C1_1") (pintype "passive"))
      (node (ref "C710") (pin "1") (pinfunction "C1_1") (pintype "passive"))
      (node (ref "U701") (pin "12") (pinfunction "CM_12") (pintype "bidirectional"))
      (node (ref "U701") (pin "13") (pinfunction "AIN1REF_13") (pintype "bidirectional"))
      (node (ref "U701") (pin "15") (pinfunction "AIN2REF_15") (pintype "bidirectional"))
      (node (ref "U701") (pin "17") (pinfunction "AIN3REF_17") (pintype "bidirectional"))
      (node (ref "U701") (pin "8") (pinfunction "AIN0REF_8") (pintype "bidirectional"))
    )
    (net (code "238") (name "Net-(C712-C2)") (class "Default")
      (node (ref "C712") (pin "2") (pinfunction "C2_2") (pintype "passive"))
      (node (ref "C713") (pin "2") (pinfunction "C2_2") (pintype "passive"))
      (node (ref "L701") (pin "1") (pinfunction "1_1") (pintype "passive"))
      (node (ref "R703") (pin "2") (pinfunction "2_2") (pintype "passive"))
    )
    (net (code "239") (name "Net-(C714-C2)") (class "Default")
      (node (ref "C714") (pin "2") (pinfunction "C2_2") (pintype "passive"))
      (node (ref "C715") (pin "2") (pinfunction "C2_2") (pintype "passive"))
      (node (ref "L702") (pin "1") (pinfunction "1_1") (pintype "passive"))
      (node (ref "R702") (pin "2") (pinfunction "2_2") (pintype "passive"))
    )
    (net (code "240") (name "Net-(C717-C2)") (class "Default")
      (node (ref "C717") (pin "2") (pinfunction "C2_2") (pintype "passive"))
      (node (ref "J701") (pin "2") (pinfunction "T_2") (pintype "bidirectional"))
      (node (ref "R708") (pin "1") (pinfunction "1_1") (pintype "passive"))
      (node (ref "R709") (pin "2") (pinfunction "2_2") (pintype "passive"))
    )
    (net (code "241") (name "Net-(C718-C2)") (class "Default")
      (node (ref "C718") (pin "2") (pinfunction "C2_2") (pintype "passive"))
      (node (ref "J701") (pin "3") (pinfunction "R_3") (pintype "bidirectional"))
      (node (ref "R704") (pin "1") (pinfunction "1_1") (pintype "passive"))
      (node (ref "R705") (pin "2") (pinfunction "2_2") (pintype "passive"))
    )
    (net (code "242") (name "Net-(C719-C2)") (class "Default")
      (node (ref "C719") (pin "2") (pinfunction "C2_2") (pintype "passive"))
      (node (ref "J702") (pin "2") (pinfunction "T_2") (pintype "bidirectional"))
      (node (ref "R710") (pin "1") (pinfunction "1_1") (pintype "passive"))
      (node (ref "R711") (pin "2") (pinfunction "2_2") (pintype "passive"))
    )
    (net (code "243") (name "Net-(C720-C2)") (class "Default")
      (node (ref "C720") (pin "2") (pinfunction "C2_2") (pintype "passive"))
      (node (ref "J702") (pin "3") (pinfunction "R_3") (pintype "bidirectional"))
      (node (ref "R706") (pin "1") (pinfunction "1_1") (pintype "passive"))
      (node (ref "R707") (pin "2") (pinfunction "2_2") (pintype "passive"))
    )
    (net (code "244") (name "Net-(C721-C1)") (class "Default")
      (node (ref "C721") (pin "1") (pinfunction "C1_1") (pintype "passive"))
      (node (ref "J703") (pin "3") (pinfunction "R_3") (pintype "bidirectional"))
      (node (ref "L702") (pin "2") (pinfunction "2_2") (pintype "passive"))
    )
    (net (code "245") (name "Net-(C722-C1)") (class "Default")
      (node (ref "C722") (pin "1") (pinfunction "C1_1") (pintype "passive"))
      (node (ref "J703") (pin "2") (pinfunction "T_2") (pintype "bidirectional"))
      (node (ref "L701") (pin "2") (pinfunction "2_2") (pintype "passive"))
    )
    (net (code "246") (name "Net-(C801-C2)") (class "Default")
      (node (ref "C801") (pin "2") (pinfunction "C2_2") (pintype "passive"))
      (node (ref "U201") (pin "B8") (pinfunction "MGTPRXP0_B8") (pintype "bidirectional"))
    )
    (net (code "247") (name "Net-(C802-C2)") (class "Default")
      (node (ref "C802") (pin "2") (pinfunction "C2_2") (pintype "passive"))
      (node (ref "U201") (pin "A8") (pinfunction "MGTPRXN0_A8") (pintype "bidirectional"))
    )
    (net (code "248") (name "Net-(C803-C2)") (class "Default")
      (node (ref "C803") (pin "2") (pinfunction "C2_2") (pintype "passive"))
      (node (ref "U201") (pin "B10") (pinfunction "MGTPRXP2_B10") (pintype "bidirectional"))
    )
    (net (code "249") (name "Net-(C804-C2)") (class "Default")
      (node (ref "C804") (pin "2") (pinfunction "C2_2") (pintype "passive"))
      (node (ref "U201") (pin "A10") (pinfunction "MGTPRXN2_A10") (pintype "bidirectional"))
    )
    (net (code "250") (name "Net-(C805-C2)") (class "Default")
      (node (ref "C805") (pin "2") (pinfunction "C2_2") (pintype "passive"))
      (node (ref "U201") (pin "D9") (pinfunction "MGTPRXP3_D9") (pintype "bidirectional"))
    )
    (net (code "251") (name "Net-(C806-C2)") (class "Default")
      (node (ref "C806") (pin "2") (pinfunction "C2_2") (pintype "passive"))
      (node (ref "U201") (pin "C9") (pinfunction "MGTPRXN3_C9") (pintype "bidirectional"))
    )
    (net (code "252") (name "Net-(C807-C1)") (class "Default")
      (node (ref "C807") (pin "1") (pinfunction "C1_1") (pintype "passive"))
      (node (ref "U201") (pin "B4") (pinfunction "MGTPTXP0_B4") (pintype "bidirectional"))
    )
    (net (code "253") (name "Net-(C808-C1)") (class "Default")
      (node (ref "C808") (pin "1") (pinfunction "C1_1") (pintype "passive"))
      (node (ref "U201") (pin "A4") (pinfunction "MGTPTXN0_A4") (pintype "bidirectional"))
    )
    (net (code "254") (name "Net-(C809-C1)") (class "Default")
      (node (ref "C809") (pin "1") (pinfunction "C1_1") (pintype "passive"))
      (node (ref "U201") (pin "B6") (pinfunction "MGTPTXP2_B6") (pintype "bidirectional"))
    )
    (net (code "255") (name "Net-(C810-C1)") (class "Default")
      (node (ref "C810") (pin "1") (pinfunction "C1_1") (pintype "passive"))
      (node (ref "U201") (pin "A6") (pinfunction "MGTPTXN2_A6") (pintype "bidirectional"))
    )
    (net (code "256") (name "Net-(C811-C1)") (class "Default")
      (node (ref "C811") (pin "1") (pinfunction "C1_1") (pintype "passive"))
      (node (ref "U201") (pin "D7") (pinfunction "MGTPTXP3_D7") (pintype "bidirectional"))
    )
    (net (code "257") (name "Net-(C812-C1)") (class "Default")
      (node (ref "C812") (pin "1") (pinfunction "C1_1") (pintype "passive"))
      (node (ref "U201") (pin "C7") (pinfunction "MGTPTXN3_C7") (pintype "bidirectional"))
    )
    (net (code "258") (name "Net-(C906-C1)") (class "Default")
      (node (ref "C906") (pin "1") (pinfunction "C1_1") (pintype "passive"))
      (node (ref "C907") (pin "1") (pinfunction "C1_1") (pintype "passive"))
      (node (ref "R903") (pin "2") (pinfunction "2_2") (pintype "passive"))
      (node (ref "U901") (pin "3") (pinfunction "CLK_3") (pintype "output"))
    )
    (net (code "259") (name "Net-(C907-C2)") (class "Default")
      (node (ref "C907") (pin "2") (pinfunction "C2_2") (pintype "passive"))
      (node (ref "U902") (pin "1") (pinfunction "XA_1") (pintype "bidirectional"))
    )
    (net (code "260") (name "Net-(C1001-C1)") (class "Default")
      (node (ref "C1001") (pin "1") (pinfunction "C1_1") (pintype "passive"))
      (node (ref "R1001") (pin "2") (pinfunction "2_2") (pintype "passive"))
      (node (ref "USB1001") (pin "SHIELD@0") (pinfunction "SHIELD_SHIELD@0") (pintype "bidirectional"))
      (node (ref "USB1001") (pin "SHIELD@1") (pinfunction "SHIELD_SHIELD@1") (pintype "bidirectional"))
      (node (ref "USB1001") (pin "SHIELD@2") (pinfunction "SHIELD_SHIELD@2") (pintype "bidirectional"))
      (node (ref "USB1001") (pin "SHIELD@3") (pinfunction "SHIELD_SHIELD@3") (pintype "bidirectional"))
    )
    (net (code "261") (name "Net-(C1009-C1)") (class "Default")
      (node (ref "C1009") (pin "1") (pinfunction "C1_1") (pintype "passive"))
      (node (ref "U1002") (pin "15") (pinfunction "VDD18_CORE_OUT_15") (pintype "bidirectional"))
      (node (ref "U1002") (pin "28") (pinfunction "VPP18_28") (pintype "bidirectional"))
    )
    (net (code "262") (name "Net-(C1011-C1)") (class "Default")
      (node (ref "C1011") (pin "1") (pinfunction "C1_1") (pintype "passive"))
      (node (ref "U1002") (pin "5") (pinfunction "VDD12_CORE_OUT_5") (pintype "bidirectional"))
    )
    (net (code "263") (name "Net-(C1014-C1)") (class "Default")
      (node (ref "C1014") (pin "1") (pinfunction "C1_1") (pintype "passive"))
      (node (ref "D1003") (pin "A") (pinfunction "A_A") (pintype "passive"))
      (node (ref "U1003") (pin "6") (pinfunction "VOUT_6") (pintype "bidirectional"))
    )
    (net (code "264") (name "Net-(C1104-C1)") (class "Default")
      (node (ref "C1104") (pin "1") (pinfunction "C1_1") (pintype "passive"))
      (node (ref "D1101") (pin "C") (pinfunction "C_C") (pintype "passive"))
      (node (ref "D1102") (pin "C") (pinfunction "C_C") (pintype "passive"))
      (node (ref "D1103") (pin "C") (pinfunction "C_C") (pintype "passive"))
      (node (ref "U1101") (pin "1") (pinfunction "VIN_1") (pintype "bidirectional"))
      (node (ref "U1101") (pin "4") (pinfunction "~{SHDN}_4") (pintype "bidirectional"))
    )
    (net (code "265") (name "Net-(C1115-C1)") (class "Default")
      (node (ref "C1115") (pin "1") (pinfunction "C1_1") (pintype "passive"))
      (node (ref "U1102") (pin "7") (pinfunction "VDD18_7") (pintype "bidirectional"))
    )
    (net (code "266") (name "Net-(C1120-C1)") (class "Default")
      (node (ref "C1120") (pin "1") (pinfunction "C1_1") (pintype "passive"))
      (node (ref "L1101") (pin "1") (pinfunction "1_1") (pintype "passive"))
      (node (ref "U1102") (pin "36") (pinfunction "SW_36") (pintype "bidirectional"))
      (node (ref "U1102") (pin "37") (pinfunction "SW_37") (pintype "bidirectional"))
      (node (ref "U1102") (pin "41") (pinfunction "SW_41") (pintype "bidirectional"))
    )
    (net (code "267") (name "Net-(C1120-C2)") (class "Default")
      (node (ref "C1120") (pin "2") (pinfunction "C2_2") (pintype "passive"))
      (node (ref "U1102") (pin "40") (pinfunction "BOOST_40") (pintype "bidirectional"))
    )
    (net (code "268") (name "Net-(C1121-C1)") (class "Default")
      (node (ref "C1121") (pin "1") (pinfunction "C1_1") (pintype "passive"))
      (node (ref "L1102") (pin "1") (pinfunction "1_1") (pintype "passive"))
      (node (ref "U1102") (pin "16") (pinfunction "SW_16") (pintype "bidirectional"))
      (node (ref "U1102") (pin "17") (pinfunction "SW_17") (pintype "bidirectional"))
      (node (ref "U1102") (pin "44") (pinfunction "SW_44") (pintype "bidirectional"))
    )
    (net (code "269") (name "Net-(C1121-C2)") (class "Default")
      (node (ref "C1121") (pin "2") (pinfunction "C2_2") (pintype "passive"))
      (node (ref "U1102") (pin "13") (pinfunction "BOOST_13") (pintype "bidirectional"))
    )
    (net (code "270") (name "Net-(C1206-C1)") (class "Default")
      (node (ref "C1206") (pin "1") (pinfunction "C1_1") (pintype "passive"))
      (node (ref "U1201") (pin "4") (pinfunction "SS_4") (pintype "bidirectional"))
    )
    (net (code "271") (name "Net-(C1207-C1)") (class "Default")
      (node (ref "C1207") (pin "1") (pinfunction "C1_1") (pintype "passive"))
      (node (ref "U1202") (pin "4") (pinfunction "SS_4") (pintype "bidirectional"))
    )
    (net (code "272") (name "Net-(C1208-C1)") (class "Default")
      (node (ref "C1208") (pin "1") (pinfunction "C1_1") (pintype "passive"))
      (node (ref "U1203") (pin "4") (pinfunction "SS_4") (pintype "bidirectional"))
    )
    (net (code "273") (name "Net-(C1211-C1)") (class "Default")
      (node (ref "C1211") (pin "1") (pinfunction "C1_1") (pintype "passive"))
      (node (ref "U1204") (pin "14") (pinfunction "SS_14") (pintype "bidirectional"))
    )
    (net (code "274") (name "Net-(C1221-C1)") (class "Default")
      (node (ref "C1221") (pin "1") (pinfunction "C1_1") (pintype "passive"))
      (node (ref "U1204") (pin "13") (pinfunction "SS_13") (pintype "bidirectional"))
    )
    (net (code "275") (name "Net-(C1231-C1)") (class "Default")
      (node (ref "C1231") (pin "1") (pinfunction "C1_1") (pintype "passive"))
      (node (ref "U1206") (pin "4") (pinfunction "SS_4") (pintype "bidirectional"))
    )
    (net (code "276") (name "Net-(C1233-C1)") (class "Default")
      (node (ref "C1233") (pin "1") (pinfunction "C1_1") (pintype "passive"))
      (node (ref "U1207") (pin "4") (pinfunction "SS_4") (pintype "bidirectional"))
    )
    (net (code "277") (name "Net-(C1249-C1)") (class "Default")
      (node (ref "C1249") (pin "1") (pinfunction "C1_1") (pintype "passive"))
      (node (ref "U1208") (pin "14") (pinfunction "SS_14") (pintype "bidirectional"))
    )
    (net (code "278") (name "Net-(C1251-C1)") (class "Default")
      (node (ref "C1251") (pin "1") (pinfunction "C1_1") (pintype "passive"))
      (node (ref "U1209") (pin "6") (pinfunction "SS_6") (pintype "bidirectional"))
    )
    (net (code "279") (name "Net-(C1252-C1)") (class "Default")
      (node (ref "C1252") (pin "1") (pinfunction "C1_1") (pintype "passive"))
      (node (ref "U1208") (pin "13") (pinfunction "SS_13") (pintype "bidirectional"))
    )
    (net (code "280") (name "Net-(CON801A-S)") (class "Default")
      (node (ref "CON801") (pin "A1") (pinfunction "S_A1") (pintype "passive"))
      (node (ref "CON801") (pin "B31") (pinfunction "S_B31") (pintype "passive"))
    )
    (net (code "281") (name "Net-(CON1101B-S)") (class "Default")
      (node (ref "CON1101") (pin "P$2") (pinfunction "S_P$2") (pintype "passive"))
      (node (ref "F1101") (pin "2") (pinfunction "2_2") (pintype "passive"))
    )
    (net (code "282") (name "Net-(D101-PadA)") (class "Default")
      (node (ref "D101") (pin "A") (pinfunction "A_A") (pintype "passive"))
      (node (ref "R101") (pin "1") (pinfunction "1_1") (pintype "passive"))
    )
    (net (code "283") (name "Net-(D505-PadA)") (class "Default")
      (node (ref "D505") (pin "A") (pinfunction "A_A") (pintype "passive"))
      (node (ref "R505") (pin "1") (pinfunction "1_1") (pintype "passive"))
    )
    (net (code "284") (name "Net-(D506-PadA)") (class "Default")
      (node (ref "D506") (pin "A") (pinfunction "A_A") (pintype "passive"))
      (node (ref "R506") (pin "1") (pinfunction "1_1") (pintype "passive"))
    )
    (net (code "285") (name "Net-(D507-PadA)") (class "Default")
      (node (ref "D507") (pin "A") (pinfunction "A_A") (pintype "passive"))
      (node (ref "R511") (pin "1") (pinfunction "1_1") (pintype "passive"))
    )
    (net (code "286") (name "Net-(D508-PadA)") (class "Default")
      (node (ref "D508") (pin "A") (pinfunction "A_A") (pintype "passive"))
      (node (ref "R512") (pin "1") (pinfunction "1_1") (pintype "passive"))
    )
    (net (code "287") (name "Net-(D1001-C1)") (class "Default")
      (node (ref "D1001") (pin "1") (pinfunction "C1_1") (pintype "bidirectional"))
      (node (ref "L1001") (pin "1") (pinfunction "1_1") (pintype "passive"))
      (node (ref "USB1001") (pin "A7") (pinfunction "D-_A7") (pintype "bidirectional"))
      (node (ref "USB1001") (pin "B7") (pinfunction "D-_B7") (pintype "bidirectional"))
    )
    (net (code "288") (name "Net-(D1001-C2)") (class "Default")
      (node (ref "D1001") (pin "2") (pinfunction "C2_2") (pintype "bidirectional"))
      (node (ref "L1001") (pin "4") (pinfunction "4_4") (pintype "passive"))
      (node (ref "USB1001") (pin "A6") (pinfunction "D+_A6") (pintype "bidirectional"))
      (node (ref "USB1001") (pin "B6") (pinfunction "D+_B6") (pintype "bidirectional"))
    )
    (net (code "289") (name "Net-(D1004-PadA)") (class "Default")
      (node (ref "D1004") (pin "A") (pinfunction "A_A") (pintype "passive"))
      (node (ref "R1013") (pin "1") (pinfunction "1_1") (pintype "passive"))
    )
    (net (code "290") (name "Net-(D1104-PadA)") (class "Default")
      (node (ref "D1104") (pin "A") (pinfunction "A_A") (pintype "passive"))
      (node (ref "R1119") (pin "1") (pinfunction "1_1") (pintype "passive"))
    )
    (net (code "291") (name "Net-(F1001-Pad2)") (class "Default")
      (node (ref "F1001") (pin "2") (pinfunction "2_2") (pintype "passive"))
      (node (ref "USB1001") (pin "A4/B9") (pinfunction "VBUS_A4/B9") (pintype "bidirectional"))
      (node (ref "USB1001") (pin "B4/A9") (pinfunction "VBUS_B4/A9") (pintype "bidirectional"))
    )
    (net (code "292") (name "Net-(J101A-A)") (class "Default")
      (node (ref "J101") (pin "11") (pinfunction "A_11") (pintype "passive"))
      (node (ref "R119") (pin "1") (pinfunction "1_1") (pintype "passive"))
    )
    (net (code "293") (name "Net-(J101C-A)") (class "Default")
      (node (ref "J101") (pin "13") (pinfunction "A_13") (pintype "passive"))
      (node (ref "R118") (pin "1") (pinfunction "1_1") (pintype "passive"))
    )
    (net (code "294") (name "Net-(JP101A-S)") (class "Default")
      (node (ref "JP101") (pin "1") (pinfunction "S_1") (pintype "passive"))
      (node (ref "R114") (pin "1") (pinfunction "1_1") (pintype "passive"))
    )
    (net (code "295") (name "Net-(JP101B-S)") (class "Default")
      (node (ref "JP101") (pin "2") (pinfunction "S_2") (pintype "passive"))
      (node (ref "R115") (pin "1") (pinfunction "1_1") (pintype "passive"))
    )
    (net (code "296") (name "Net-(JP201B-S)") (class "Default")
      (node (ref "JP201") (pin "2") (pinfunction "S_2") (pintype "passive"))
      (node (ref "R203") (pin "1") (pinfunction "1_1") (pintype "passive"))
    )
    (net (code "297") (name "Net-(JP201D-S)") (class "Default")
      (node (ref "JP201") (pin "4") (pinfunction "S_4") (pintype "passive"))
      (node (ref "R204") (pin "1") (pinfunction "1_1") (pintype "passive"))
    )
    (net (code "298") (name "Net-(JP201F-S)") (class "Default")
      (node (ref "JP201") (pin "6") (pinfunction "S_6") (pintype "passive"))
      (node (ref "R206") (pin "1") (pinfunction "1_1") (pintype "passive"))
    )
    (net (code "299") (name "Net-(JP202A-S)") (class "Default")
      (node (ref "JP202") (pin "1") (pinfunction "S_1") (pintype "passive"))
      (node (ref "R211") (pin "1") (pinfunction "1_1") (pintype "passive"))
    )
    (net (code "300") (name "Net-(JP202B-S)") (class "Default")
      (node (ref "JP202") (pin "2") (pinfunction "S_2") (pintype "passive"))
      (node (ref "R208") (pin "1") (pinfunction "1_1") (pintype "passive"))
    )
    (net (code "301") (name "Net-(JP202C-S)") (class "Default")
      (node (ref "JP202") (pin "3") (pinfunction "S_3") (pintype "passive"))
      (node (ref "R212") (pin "1") (pinfunction "1_1") (pintype "passive"))
    )
    (net (code "302") (name "Net-(JP202D-S)") (class "Default")
      (node (ref "JP202") (pin "4") (pinfunction "S_4") (pintype "passive"))
      (node (ref "R209") (pin "1") (pinfunction "1_1") (pintype "passive"))
    )
    (net (code "303") (name "Net-(JP202E-S)") (class "Default")
      (node (ref "JP202") (pin "5") (pinfunction "S_5") (pintype "passive"))
      (node (ref "R213") (pin "1") (pinfunction "1_1") (pintype "passive"))
    )
    (net (code "304") (name "Net-(L1201-Pad2)") (class "Default")
      (node (ref "L1201") (pin "2") (pinfunction "2_2") (pintype "passive"))
      (node (ref "U1204") (pin "3") (pinfunction "SW_3") (pintype "bidirectional"))
    )
    (net (code "305") (name "Net-(L1202-Pad1)") (class "Default")
      (node (ref "L1202") (pin "1") (pinfunction "1_1") (pintype "passive"))
      (node (ref "U1204") (pin "4") (pinfunction "SW_4") (pintype "bidirectional"))
    )
    (net (code "306") (name "Net-(L1203-Pad2)") (class "Default")
      (node (ref "L1203") (pin "2") (pinfunction "2_2") (pintype "passive"))
      (node (ref "U1208") (pin "3") (pinfunction "SW_3") (pintype "bidirectional"))
    )
    (net (code "307") (name "Net-(L1204-Pad1)") (class "Default")
      (node (ref "L1204") (pin "1") (pinfunction "1_1") (pintype "passive"))
      (node (ref "U1208") (pin "4") (pinfunction "SW_4") (pintype "bidirectional"))
    )
    (net (code "308") (name "Net-(Q101-D)") (class "Default")
      (node (ref "D102") (pin "A") (pinfunction "A_A") (pintype "passive"))
      (node (ref "Q101") (pin "3") (pinfunction "D_3") (pintype "passive"))
      (node (ref "R106") (pin "1") (pinfunction "1_1") (pintype "passive"))
    )
    (net (code "309") (name "Net-(Q102-D)") (class "Default")
      (node (ref "Q102") (pin "3") (pinfunction "D_3") (pintype "passive"))
      (node (ref "R108") (pin "1") (pinfunction "1_1") (pintype "passive"))
      (node (ref "U102") (pin "56") (pinfunction "GPIO3_56") (pintype "bidirectional"))
    )
    (net (code "310") (name "Net-(Q1101-D)") (class "Default")
      (node (ref "Q1101") (pin "3") (pinfunction "D_3") (pintype "passive"))
      (node (ref "R1107") (pin "1") (pinfunction "1_1") (pintype "passive"))
    )
    (net (code "311") (name "Net-(Q1102A-G)") (class "Default")
      (node (ref "Q1102") (pin "2") (pinfunction "G_2") (pintype "passive"))
      (node (ref "Q1102") (pin "4") (pinfunction "G_4") (pintype "passive"))
      (node (ref "R1106") (pin "1") (pinfunction "1_1") (pintype "passive"))
      (node (ref "R1107") (pin "2") (pinfunction "2_2") (pintype "passive"))
    )
    (net (code "312") (name "Net-(Q1102A-S)") (class "Default")
      (node (ref "Q1102") (pin "1") (pinfunction "S_1") (pintype "passive"))
      (node (ref "Q1102") (pin "3") (pinfunction "S_3") (pintype "passive"))
      (node (ref "R1106") (pin "2") (pinfunction "2_2") (pintype "passive"))
    )
    (net (code "313") (name "Net-(Q1103-D)") (class "Default")
      (node (ref "Q1103") (pin "3") (pinfunction "D_3") (pintype "passive"))
      (node (ref "R1114") (pin "1") (pinfunction "1_1") (pintype "passive"))
    )
    (net (code "314") (name "Net-(Q1104A-G)") (class "Default")
      (node (ref "Q1104") (pin "2") (pinfunction "G_2") (pintype "passive"))
      (node (ref "Q1104") (pin "4") (pinfunction "G_4") (pintype "passive"))
      (node (ref "R1113") (pin "1") (pinfunction "1_1") (pintype "passive"))
      (node (ref "R1114") (pin "2") (pinfunction "2_2") (pintype "passive"))
    )
    (net (code "315") (name "Net-(Q1104A-S)") (class "Default")
      (node (ref "Q1104") (pin "1") (pinfunction "S_1") (pintype "passive"))
      (node (ref "Q1104") (pin "3") (pinfunction "S_3") (pintype "passive"))
      (node (ref "R1113") (pin "2") (pinfunction "2_2") (pintype "passive"))
    )
    (net (code "316") (name "Net-(Q1105A-G)") (class "Default")
      (node (ref "Q1105") (pin "2") (pinfunction "G_2") (pintype "passive"))
      (node (ref "Q1105") (pin "4") (pinfunction "G_4") (pintype "passive"))
      (node (ref "R1116") (pin "1") (pinfunction "1_1") (pintype "passive"))
      (node (ref "R1117") (pin "2") (pinfunction "2_2") (pintype "passive"))
    )
    (net (code "317") (name "Net-(Q1105A-S)") (class "Default")
      (node (ref "Q1105") (pin "1") (pinfunction "S_1") (pintype "passive"))
      (node (ref "Q1105") (pin "3") (pinfunction "S_3") (pintype "passive"))
      (node (ref "R1116") (pin "2") (pinfunction "2_2") (pintype "passive"))
    )
    (net (code "318") (name "Net-(Q1106-D)") (class "Default")
      (node (ref "Q1106") (pin "3") (pinfunction "D_3") (pintype "passive"))
      (node (ref "R1117") (pin "1") (pinfunction "1_1") (pintype "passive"))
    )
    (net (code "319") (name "Net-(R1202-Pad1)") (class "Default")
      (node (ref "R1202") (pin "1") (pinfunction "1_1") (pintype "passive"))
      (node (ref "R1203") (pin "2") (pinfunction "2_2") (pintype "passive"))
      (node (ref "U1204") (pin "16") (pinfunction "FB_16") (pintype "bidirectional"))
    )
    (net (code "320") (name "Net-(R1205-Pad1)") (class "Default")
      (node (ref "R1205") (pin "1") (pinfunction "1_1") (pintype "passive"))
      (node (ref "R1206") (pin "2") (pinfunction "2_2") (pintype "passive"))
      (node (ref "U1204") (pin "11") (pinfunction "FB_11") (pintype "bidirectional"))
    )
    (net (code "321") (name "Net-(R1208-Pad1)") (class "Default")
      (node (ref "R1208") (pin "1") (pinfunction "1_1") (pintype "passive"))
      (node (ref "R1209") (pin "2") (pinfunction "2_2") (pintype "passive"))
      (node (ref "U1208") (pin "16") (pinfunction "FB_16") (pintype "bidirectional"))
    )
    (net (code "322") (name "Net-(R1212-Pad1)") (class "Default")
      (node (ref "R1212") (pin "1") (pinfunction "1_1") (pintype "passive"))
      (node (ref "R1213") (pin "2") (pinfunction "2_2") (pintype "passive"))
      (node (ref "U1208") (pin "11") (pinfunction "FB_11") (pintype "bidirectional"))
    )
    (net (code "323") (name "Net-(RFCON101-SIGNAL)") (class "Default")
      (node (ref "RFCON101") (pin "P$3") (pinfunction "SIGNAL_P$3") (pintype "bidirectional"))
      (node (ref "U102") (pin "111") (pinfunction "VDAC_COMP_111") (pintype "bidirectional"))
    )
    (net (code "324") (name "Net-(RFCON505-SIGNAL)") (class "Default")
      (node (ref "R513") (pin "2") (pinfunction "2_2") (pintype "passive"))
      (node (ref "R514") (pin "2") (pinfunction "2_2") (pintype "passive"))
      (node (ref "RFCON505") (pin "P$3") (pinfunction "SIGNAL_P$3") (pintype "bidirectional"))
    )
    (net (code "325") (name "Net-(RFCON506-SIGNAL)") (class "Default")
      (node (ref "R515") (pin "2") (pinfunction "2_2") (pintype "passive"))
      (node (ref "R516") (pin "2") (pinfunction "2_2") (pintype "passive"))
      (node (ref "RFCON506") (pin "P$3") (pinfunction "SIGNAL_P$3") (pintype "bidirectional"))
    )
    (net (code "326") (name "Net-(RFCON901-SIGNAL)") (class "Default")
      (node (ref "R901") (pin "2") (pinfunction "2_2") (pintype "passive"))
      (node (ref "R902") (pin "2") (pinfunction "2_2") (pintype "passive"))
      (node (ref "RFCON901") (pin "P$3") (pinfunction "SIGNAL_P$3") (pintype "bidirectional"))
    )
    (net (code "327") (name "Net-(T501-PRI1)") (class "Default")
      (node (ref "D501") (pin "1") (pinfunction "1_1") (pintype "passive"))
      (node (ref "RFCON501") (pin "SIGNAL") (pinfunction "SIGNAL_SIGNAL") (pintype "bidirectional"))
      (node (ref "T501") (pin "3") (pinfunction "PRI1_3") (pintype "passive"))
    )
    (net (code "328") (name "Net-(T502-PRI1)") (class "Default")
      (node (ref "D502") (pin "1") (pinfunction "1_1") (pintype "passive"))
      (node (ref "RFCON502") (pin "SIGNAL") (pinfunction "SIGNAL_SIGNAL") (pintype "bidirectional"))
      (node (ref "T502") (pin "3") (pinfunction "PRI1_3") (pintype "passive"))
    )
    (net (code "329") (name "Net-(T507-PRI1)") (class "Default")
      (node (ref "D509") (pin "1") (pinfunction "1_1") (pintype "passive"))
      (node (ref "RFCON507") (pin "SIGNAL") (pinfunction "SIGNAL_SIGNAL") (pintype "bidirectional"))
      (node (ref "T507") (pin "3") (pinfunction "PRI1_3") (pintype "passive"))
    )
    (net (code "330") (name "Net-(T508-PRI1)") (class "Default")
      (node (ref "D510") (pin "1") (pinfunction "1_1") (pintype "passive"))
      (node (ref "RFCON508") (pin "SIGNAL") (pinfunction "SIGNAL_SIGNAL") (pintype "bidirectional"))
      (node (ref "T508") (pin "3") (pinfunction "PRI1_3") (pintype "passive"))
    )
    (net (code "331") (name "Net-(U101-ILIMIT)") (class "Default")
      (node (ref "R104") (pin "2") (pinfunction "2_2") (pintype "passive"))
      (node (ref "U101") (pin "5") (pinfunction "ILIMIT_5") (pintype "bidirectional"))
    )
    (net (code "332") (name "Net-(U102E-ETH_SYNC_IN)") (class "Default")
      (node (ref "R111") (pin "1") (pinfunction "1_1") (pintype "passive"))
      (node (ref "U102") (pin "16") (pinfunction "ETH_SYNC_IN_16") (pintype "bidirectional"))
    )
    (net (code "333") (name "Net-(U102E-ETH_SYNC_OUT)") (class "Default")
      (node (ref "R113") (pin "1") (pinfunction "1_1") (pintype "passive"))
      (node (ref "U102") (pin "18") (pinfunction "ETH_SYNC_OUT_18") (pintype "bidirectional"))
    )
    (net (code "334") (name "Net-(U102J-~{BT_DISABLE})") (class "Default")
      (node (ref "R107") (pin "2") (pinfunction "2_2") (pintype "passive"))
      (node (ref "U102") (pin "91") (pinfunction "~{BT_DISABLE}_91") (pintype "bidirectional"))
    )
    (net (code "335") (name "Net-(U102J-~{EEPROM_WP})") (class "Default")
      (node (ref "R109") (pin "2") (pinfunction "2_2") (pintype "passive"))
      (node (ref "U102") (pin "20") (pinfunction "~{EEPROM_WP}_20") (pintype "bidirectional"))
    )
    (net (code "336") (name "Net-(U102J-~{WL_DISABLE})") (class "Default")
      (node (ref "R105") (pin "2") (pinfunction "2_2") (pintype "passive"))
      (node (ref "U102") (pin "89") (pinfunction "~{WL_DISABLE}_89") (pintype "bidirectional"))
    )
    (net (code "337") (name "Net-(U201J-MGTRREF)") (class "Default")
      (node (ref "R210") (pin "1") (pinfunction "1_1") (pintype "passive"))
      (node (ref "U201") (pin "F8") (pinfunction "MGTRREF_F8") (pintype "bidirectional"))
    )
    (net (code "338") (name "Net-(U301-ZQ)") (class "Default")
      (node (ref "R301") (pin "2") (pinfunction "2_2") (pintype "passive"))
      (node (ref "U301") (pin "L8") (pinfunction "ZQ_L8") (pintype "bidirectional"))
    )
    (net (code "339") (name "Net-(U401B-RBIAS)") (class "Default")
      (node (ref "R403") (pin "2") (pinfunction "2_2") (pintype "passive"))
      (node (ref "U401") (pin "L4") (pinfunction "RBIAS_L4") (pintype "bidirectional"))
    )
    (net (code "340") (name "Net-(U501-ILIMIT)") (class "Default")
      (node (ref "R501") (pin "2") (pinfunction "2_2") (pintype "passive"))
      (node (ref "U501") (pin "5") (pinfunction "ILIMIT_5") (pintype "bidirectional"))
    )
    (net (code "341") (name "Net-(U502-ILIMIT)") (class "Default")
      (node (ref "R502") (pin "2") (pinfunction "2_2") (pintype "passive"))
      (node (ref "U502") (pin "5") (pinfunction "ILIMIT_5") (pintype "bidirectional"))
    )
    (net (code "342") (name "Net-(U503-ILIMIT)") (class "Default")
      (node (ref "R507") (pin "2") (pinfunction "2_2") (pintype "passive"))
      (node (ref "U503") (pin "5") (pinfunction "ILIMIT_5") (pintype "bidirectional"))
    )
    (net (code "343") (name "Net-(U504-ILIMIT)") (class "Default")
      (node (ref "R508") (pin "2") (pinfunction "2_2") (pintype "passive"))
      (node (ref "U504") (pin "5") (pinfunction "ILIMIT_5") (pintype "bidirectional"))
    )
    (net (code "344") (name "Net-(U902-CLK0)") (class "Default")
      (node (ref "R906") (pin "2") (pinfunction "2_2") (pintype "passive"))
      (node (ref "U902") (pin "13") (pinfunction "CLK0_13") (pintype "bidirectional"))
    )
    (net (code "345") (name "Net-(U902-CLK1)") (class "Default")
      (node (ref "R910") (pin "2") (pinfunction "2_2") (pintype "passive"))
      (node (ref "U902") (pin "12") (pinfunction "CLK1_12") (pintype "bidirectional"))
    )
    (net (code "346") (name "Net-(U902-CLK2)") (class "Default")
      (node (ref "R907") (pin "2") (pinfunction "2_2") (pintype "passive"))
      (node (ref "U902") (pin "9") (pinfunction "CLK2_9") (pintype "bidirectional"))
    )
    (net (code "347") (name "Net-(U902-CLK3)") (class "Default")
      (node (ref "R911") (pin "2") (pinfunction "2_2") (pintype "passive"))
      (node (ref "U902") (pin "8") (pinfunction "CLK3_8") (pintype "bidirectional"))
    )
    (net (code "348") (name "Net-(U902-CLK4)") (class "Default")
      (node (ref "R908") (pin "2") (pinfunction "2_2") (pintype "passive"))
      (node (ref "U902") (pin "19") (pinfunction "CLK4_19") (pintype "bidirectional"))
    )
    (net (code "349") (name "Net-(U902-CLK5)") (class "Default")
      (node (ref "R912") (pin "2") (pinfunction "2_2") (pintype "passive"))
      (node (ref "U902") (pin "17") (pinfunction "CLK5_17") (pintype "bidirectional"))
    )
    (net (code "350") (name "Net-(U902-CLK6)") (class "Default")
      (node (ref "R909") (pin "2") (pinfunction "2_2") (pintype "passive"))
      (node (ref "U902") (pin "16") (pinfunction "CLK6_16") (pintype "bidirectional"))
    )
    (net (code "351") (name "Net-(U902-CLK7)") (class "Default")
      (node (ref "R913") (pin "2") (pinfunction "2_2") (pintype "passive"))
      (node (ref "U902") (pin "15") (pinfunction "CLK7_15") (pintype "bidirectional"))
    )
    (net (code "352") (name "Net-(U902-CLKIN)") (class "Default")
      (node (ref "R902") (pin "1") (pinfunction "1_1") (pintype "passive"))
      (node (ref "U902") (pin "6") (pinfunction "CLKIN_6") (pintype "bidirectional"))
    )
    (net (code "353") (name "Net-(U1002-PA07{slash}SPI_MOSI_SI)") (class "Default")
      (node (ref "R1008") (pin "2") (pinfunction "2_2") (pintype "passive"))
      (node (ref "U1002") (pin "20") (pinfunction "PA07/SPI_MOSI_SI_20") (pintype "bidirectional"))
    )
    (net (code "354") (name "Net-(U1002-PA08{slash}SPI_MISO)") (class "Default")
      (node (ref "TP9") (pin "TP") (pinfunction "TP_TP") (pintype "input"))
      (node (ref "U1002") (pin "22") (pinfunction "PA08/SPI_MISO_22") (pintype "bidirectional"))
    )
    (net (code "355") (name "Net-(U1002-PA09{slash}SPI_CLK)") (class "Default")
      (node (ref "TP10") (pin "TP") (pinfunction "TP_TP") (pintype "input"))
      (node (ref "U1002") (pin "23") (pinfunction "PA09/SPI_CLK_23") (pintype "bidirectional"))
    )
    (net (code "356") (name "Net-(U1002-PA10{slash}~{SPI_SS0})") (class "Default")
      (node (ref "TP8") (pin "TP") (pinfunction "TP_TP") (pintype "input"))
      (node (ref "U1002") (pin "24") (pinfunction "PA10/~{SPI_SS0}_24") (pintype "bidirectional"))
    )
    (net (code "357") (name "Net-(U1002-PA11{slash}SPI_MOSI)") (class "Default")
      (node (ref "R1008") (pin "1") (pinfunction "1_1") (pintype "passive"))
      (node (ref "U1002") (pin "25") (pinfunction "PA11/SPI_MOSI_25") (pintype "bidirectional"))
    )
    (net (code "358") (name "Net-(U1002-PA14{slash}~{IRQ})") (class "Default")
      (node (ref "TP12") (pin "TP") (pinfunction "TP_TP") (pintype "input"))
      (node (ref "U1002") (pin "29") (pinfunction "PA14/~{IRQ}_29") (pintype "bidirectional"))
    )
    (net (code "359") (name "Net-(U1003-ILIMIT)") (class "Default")
      (node (ref "R1010") (pin "2") (pinfunction "2_2") (pintype "passive"))
      (node (ref "U1003") (pin "5") (pinfunction "ILIMIT_5") (pintype "bidirectional"))
    )
    (net (code "360") (name "Net-(U1102A-RUN)") (class "Default")
      (node (ref "R1123") (pin "1") (pinfunction "1_1") (pintype "passive"))
      (node (ref "U1102") (pin "24") (pinfunction "RUN_24") (pintype "bidirectional"))
    )
    (net (code "361") (name "Net-(U1102C-ASEL)") (class "Default")
      (node (ref "R1128") (pin "2") (pinfunction "2_2") (pintype "passive"))
      (node (ref "U1102") (pin "10") (pinfunction "ASEL_10") (pintype "bidirectional"))
    )
    (net (code "362") (name "Net-(U1102C-SYNC{slash}PWM_CFG)") (class "Default")
      (node (ref "R1127") (pin "2") (pinfunction "2_2") (pintype "passive"))
      (node (ref "U1102") (pin "22") (pinfunction "SYNC/PWM_CFG_22") (pintype "bidirectional"))
    )
    (net (code "363") (name "Net-(U1102C-VOUT0_CFG)") (class "Default")
      (node (ref "R1126") (pin "2") (pinfunction "2_2") (pintype "passive"))
      (node (ref "U1102") (pin "8") (pinfunction "VOUT0_CFG_8") (pintype "bidirectional"))
    )
    (net (code "364") (name "Net-(U1102C-VOUT1_CFG{slash}POLYPHASE_CFG)") (class "Default")
      (node (ref "R1125") (pin "2") (pinfunction "2_2") (pintype "passive"))
      (node (ref "U1102") (pin "9") (pinfunction "VOUT1_CFG/POLYPHASE_CFG_9") (pintype "bidirectional"))
    )
    (net (code "365") (name "Net-(U1102C-WP)") (class "Default")
      (node (ref "R1120") (pin "1") (pinfunction "1_1") (pintype "passive"))
      (node (ref "U1102") (pin "26") (pinfunction "WP_26") (pintype "bidirectional"))
    )
    (net (code "366") (name "Net-(U1209-FB)") (class "Default")
      (node (ref "R1214") (pin "1") (pinfunction "1_1") (pintype "passive"))
      (node (ref "R1215") (pin "2") (pinfunction "2_2") (pintype "passive"))
      (node (ref "U1209") (pin "4") (pinfunction "FB_4") (pintype "bidirectional"))
    )
    (net (code "367") (name "Net-(U1209-SW)") (class "Default")
      (node (ref "L1205") (pin "1") (pinfunction "1_1") (pintype "passive"))
      (node (ref "U1209") (pin "1") (pinfunction "SW_1") (pintype "bidirectional"))
    )
    (net (code "368") (name "PCIE_CM4_REFCLK_N") (class "Default")
      (node (ref "U102") (pin "112") (pinfunction "PCIE_CLK_N_112") (pintype "bidirectional"))
      (node (ref "U201") (pin "E6") (pinfunction "MGTREFCLK0N_E6") (pintype "bidirectional"))
    )
    (net (code "369") (name "PCIE_CM4_REFCLK_P") (class "Default")
      (node (ref "U102") (pin "110") (pinfunction "PCIE_CLK_P_110") (pintype "bidirectional"))
      (node (ref "U201") (pin "F6") (pinfunction "MGTREFCLK0P_F6") (pintype "bidirectional"))
    )
    (net (code "370") (name "PCIE_CM4_RX_N") (class "Default")
      (node (ref "C808") (pin "2") (pinfunction "C2_2") (pintype "passive"))
      (node (ref "U102") (pin "118") (pinfunction "PCIE_RX_N_118") (pintype "bidirectional"))
    )
    (net (code "371") (name "PCIE_CM4_RX_P") (class "Default")
      (node (ref "C807") (pin "2") (pinfunction "C2_2") (pintype "passive"))
      (node (ref "U102") (pin "116") (pinfunction "PCIE_RX_P_116") (pintype "bidirectional"))
    )
    (net (code "372") (name "PCIE_CM4_TX_N") (class "Default")
      (node (ref "C802") (pin "1") (pinfunction "C1_1") (pintype "passive"))
      (node (ref "U102") (pin "124") (pinfunction "PCIE_TX_N_124") (pintype "bidirectional"))
    )
    (net (code "373") (name "PCIE_CM4_TX_P") (class "Default")
      (node (ref "C801") (pin "1") (pinfunction "C1_1") (pintype "passive"))
      (node (ref "U102") (pin "122") (pinfunction "PCIE_TX_P_122") (pintype "bidirectional"))
    )
    (net (code "374") (name "PCIE_SLOT_REFCLK_N") (class "Default")
      (node (ref "CON801") (pin "A14") (pinfunction "S_A14") (pintype "passive"))
      (node (ref "U201") (pin "E10") (pinfunction "MGTREFCLK1N_E10") (pintype "bidirectional"))
    )
    (net (code "375") (name "PCIE_SLOT_REFCLK_P") (class "Default")
      (node (ref "CON801") (pin "A13") (pinfunction "S_A13") (pintype "passive"))
      (node (ref "U201") (pin "F10") (pinfunction "MGTREFCLK1P_F10") (pintype "bidirectional"))
    )
    (net (code "376") (name "PCIE_SLOT_RX0_N") (class "Default")
      (node (ref "C810") (pin "2") (pinfunction "C2_2") (pintype "passive"))
      (node (ref "CON801") (pin "A17") (pinfunction "S_A17") (pintype "passive"))
    )
    (net (code "377") (name "PCIE_SLOT_RX0_P") (class "Default")
      (node (ref "C809") (pin "2") (pinfunction "C2_2") (pintype "passive"))
      (node (ref "CON801") (pin "A16") (pinfunction "S_A16") (pintype "passive"))
    )
    (net (code "378") (name "PCIE_SLOT_RX1_N") (class "Default")
      (node (ref "C812") (pin "2") (pinfunction "C2_2") (pintype "passive"))
      (node (ref "CON801") (pin "A22") (pinfunction "S_A22") (pintype "passive"))
    )
    (net (code "379") (name "PCIE_SLOT_RX1_P") (class "Default")
      (node (ref "C811") (pin "2") (pinfunction "C2_2") (pintype "passive"))
      (node (ref "CON801") (pin "A21") (pinfunction "S_A21") (pintype "passive"))
    )
    (net (code "380") (name "PCIE_SLOT_TX0_N") (class "Default")
      (node (ref "C804") (pin "1") (pinfunction "C1_1") (pintype "passive"))
      (node (ref "CON801") (pin "B15") (pinfunction "S_B15") (pintype "passive"))
    )
    (net (code "381") (name "PCIE_SLOT_TX0_P") (class "Default")
      (node (ref "C803") (pin "1") (pinfunction "C1_1") (pintype "passive"))
      (node (ref "CON801") (pin "B14") (pinfunction "S_B14") (pintype "passive"))
    )
    (net (code "382") (name "PCIE_SLOT_TX1_N") (class "Default")
      (node (ref "C806") (pin "1") (pinfunction "C1_1") (pintype "passive"))
      (node (ref "CON801") (pin "B20") (pinfunction "S_B20") (pintype "passive"))
    )
    (net (code "383") (name "PCIE_SLOT_TX1_P") (class "Default")
      (node (ref "C805") (pin "1") (pinfunction "C1_1") (pintype "passive"))
      (node (ref "CON801") (pin "B19") (pinfunction "S_B19") (pintype "passive"))
    )
    (net (code "384") (name "PMC_LED") (class "Default")
      (node (ref "R1013") (pin "2") (pinfunction "2_2") (pintype "passive"))
      (node (ref "U1002") (pin "10") (pinfunction "PA00_10") (pintype "bidirectional"))
    )
    (net (code "385") (name "PMC_SWCLK") (class "Default")
      (node (ref "TC1001") (pin "4") (pinfunction "S_4") (pintype "passive"))
      (node (ref "U1002") (pin "7") (pinfunction "PA30_7") (pintype "bidirectional"))
    )
    (net (code "386") (name "PMC_SWDIO") (class "Default")
      (node (ref "TC1001") (pin "2") (pinfunction "S_2") (pintype "passive"))
      (node (ref "U1002") (pin "8") (pinfunction "PA31_8") (pintype "bidirectional"))
    )
    (net (code "387") (name "PMC_SWO") (class "Default")
      (node (ref "R1012") (pin "2") (pinfunction "2_2") (pintype "passive"))
      (node (ref "TC1001") (pin "6") (pinfunction "S_6") (pintype "passive"))
      (node (ref "U1002") (pin "34") (pinfunction "PA18/GPO4_34") (pintype "bidirectional"))
    )
    (net (code "388") (name "PM_I2C_EN") (class "Default")
      (node (ref "R1003") (pin "2") (pinfunction "2_2") (pintype "passive"))
      (node (ref "U1001") (pin "1") (pinfunction "ENABLE_1") (pintype "bidirectional"))
      (node (ref "U201") (pin "AA18") (pinfunction "IO_L17P/T2/A14/D30_AA18") (pintype "bidirectional"))
    )
    (net (code "389") (name "PM_I2C_SCL") (class "Default")
      (node (ref "R1004") (pin "1") (pinfunction "1_1") (pintype "passive"))
      (node (ref "U1001") (pin "2") (pinfunction "SCLOUT_2") (pintype "bidirectional"))
      (node (ref "U1002") (pin "32") (pinfunction "PA17_32") (pintype "bidirectional"))
      (node (ref "U1102") (pin "30") (pinfunction "SCL_30") (pintype "bidirectional"))
    )
    (net (code "390") (name "PM_I2C_SDA") (class "Default")
      (node (ref "R1007") (pin "1") (pinfunction "1_1") (pintype "passive"))
      (node (ref "U1001") (pin "7") (pinfunction "SDAOUT_7") (pintype "bidirectional"))
      (node (ref "U1002") (pin "31") (pinfunction "PA16_31") (pintype "bidirectional"))
      (node (ref "U1102") (pin "31") (pinfunction "SDA_31") (pintype "bidirectional"))
    )
    (net (code "391") (name "SYNTH_CE") (class "Default")
      (node (ref "R603") (pin "2") (pinfunction "2_2") (pintype "passive"))
      (node (ref "U201") (pin "Y17") (pinfunction "IO_0_Y17") (pintype "bidirectional"))
      (node (ref "U601") (pin "29") (pinfunction "CE_29") (pintype "bidirectional"))
    )
    (net (code "392") (name "SYNTH_LD") (class "Default")
      (node (ref "U201") (pin "AB20") (pinfunction "IO_L15N/T2_DQS/~{CSO}/DOUT_AB20") (pintype "bidirectional"))
      (node (ref "U601") (pin "8") (pinfunction "LD_8") (pintype "bidirectional"))
    )
    (net (code "393") (name "SYNTH_MUTE") (class "Default")
      (node (ref "U201") (pin "AB21") (pinfunction "IO_L10P/T1/D14_AB21") (pintype "bidirectional"))
      (node (ref "U601") (pin "7") (pinfunction "MUTE_7") (pintype "bidirectional"))
    )
    (net (code "394") (name "SYNTH_REF_CLK") (class "Default")
      (node (ref "C601") (pin "1") (pinfunction "C1_1") (pintype "passive"))
      (node (ref "R602") (pin "2") (pinfunction "2_2") (pintype "passive"))
      (node (ref "R912") (pin "1") (pinfunction "1_1") (pintype "passive"))
    )
    (net (code "395") (name "SYNTH_SPI_MISO") (class "Default")
      (node (ref "U201") (pin "AB18") (pinfunction "IO_L17N/T2/A13/D29_AB18") (pintype "bidirectional"))
      (node (ref "U601") (pin "27") (pinfunction "SDO_27") (pintype "bidirectional"))
    )
    (net (code "396") (name "SYNTH_SPI_MOSI") (class "Default")
      (node (ref "U201") (pin "AB17") (pinfunction "IO_L2N/T0_AB17") (pintype "bidirectional"))
      (node (ref "U601") (pin "28") (pinfunction "SDIO_28") (pintype "bidirectional"))
    )
    (net (code "397") (name "SYNTH_SPI_SCK") (class "Default")
      (node (ref "U201") (pin "AA19") (pinfunction "IO_L15P/T2_DQS/RD/~{WR}_AA19") (pintype "bidirectional"))
      (node (ref "U601") (pin "26") (pinfunction "SCLK_26") (pintype "bidirectional"))
    )
    (net (code "398") (name "SYNTH_SYNC") (class "Default")
      (node (ref "U201") (pin "AB16") (pinfunction "IO_L2P/T0_AB16") (pintype "bidirectional"))
      (node (ref "U601") (pin "30") (pinfunction "SYNC_30") (pintype "bidirectional"))
    )
    (net (code "399") (name "SYS_I2C_SCL") (class "Default")
      (node (ref "R202") (pin "1") (pinfunction "1_1") (pintype "passive"))
      (node (ref "U1001") (pin "3") (pinfunction "SCLIN_3") (pintype "bidirectional"))
      (node (ref "U201") (pin "Y22") (pinfunction "IO_L9N/T1_DQS/D13_Y22") (pintype "bidirectional"))
      (node (ref "U902") (pin "4") (pinfunction "SCL_4") (pintype "bidirectional"))
    )
    (net (code "400") (name "SYS_I2C_SDA") (class "Default")
      (node (ref "R201") (pin "1") (pinfunction "1_1") (pintype "passive"))
      (node (ref "U1001") (pin "6") (pinfunction "SDAIN_6") (pintype "bidirectional"))
      (node (ref "U201") (pin "AB22") (pinfunction "IO_L10N/T1/D15_AB22") (pintype "bidirectional"))
      (node (ref "U902") (pin "5") (pinfunction "SDA_5") (pintype "bidirectional"))
    )
    (net (code "401") (name "TRX_CLK_OUT") (class "Default")
      (node (ref "U201") (pin "J20") (pinfunction "IO_L11P/T1/SRCC_J20") (pintype "bidirectional"))
      (node (ref "U401") (pin "J6") (pinfunction "CLK_OUT_J6") (pintype "bidirectional"))
    )
    (net (code "402") (name "TRX_CTRL_IN0") (class "Default")
      (node (ref "U201") (pin "M15") (pinfunction "IO_L24P/T3/RS1_M15") (pintype "bidirectional"))
      (node (ref "U401") (pin "C5") (pinfunction "CTRL_IN0_C5") (pintype "bidirectional"))
    )
    (net (code "403") (name "TRX_CTRL_IN1") (class "Default")
      (node (ref "U201") (pin "N18") (pinfunction "IO_L17P/T2/A26_N18") (pintype "bidirectional"))
      (node (ref "U401") (pin "C6") (pinfunction "CTRL_IN1_C6") (pintype "bidirectional"))
    )
    (net (code "404") (name "TRX_CTRL_IN2") (class "Default")
      (node (ref "U201") (pin "N20") (pinfunction "IO_L18P/T2/A24_N20") (pintype "bidirectional"))
      (node (ref "U401") (pin "D6") (pinfunction "CTRL_IN2_D6") (pintype "bidirectional"))
    )
    (net (code "405") (name "TRX_CTRL_IN3") (class "Default")
      (node (ref "U201") (pin "N19") (pinfunction "IO_L17N/T2/A25_N19") (pintype "bidirectional"))
      (node (ref "U401") (pin "D5") (pinfunction "CTRL_IN3_D5") (pintype "bidirectional"))
    )
    (net (code "406") (name "TRX_CTRL_OUT0") (class "Default")
      (node (ref "U201") (pin "N22") (pinfunction "IO_L15P/T2_DQS_N22") (pintype "bidirectional"))
      (node (ref "U401") (pin "D4") (pinfunction "CTRL_OUT0_D4") (pintype "bidirectional"))
    )
    (net (code "407") (name "TRX_CTRL_OUT1") (class "Default")
      (node (ref "U201") (pin "D22") (pinfunction "IO_L22N/T3_D22") (pintype "bidirectional"))
      (node (ref "U401") (pin "E4") (pinfunction "CTRL_OUT1_E4") (pintype "bidirectional"))
    )
    (net (code "408") (name "TRX_CTRL_OUT2") (class "Default")
      (node (ref "U201") (pin "D21") (pinfunction "IO_L23N/T3_D21") (pintype "bidirectional"))
      (node (ref "U401") (pin "E5") (pinfunction "CTRL_OUT2_E5") (pintype "bidirectional"))
    )
    (net (code "409") (name "TRX_CTRL_OUT3") (class "Default")
      (node (ref "U201") (pin "D17") (pinfunction "IO_L12P/T1/MRCC_D17") (pintype "bidirectional"))
      (node (ref "U401") (pin "E6") (pinfunction "CTRL_OUT3_E6") (pintype "bidirectional"))
    )
    (net (code "410") (name "TRX_CTRL_OUT4") (class "Default")
      (node (ref "U201") (pin "G22") (pinfunction "IO_L24N/T3_G22") (pintype "bidirectional"))
      (node (ref "U401") (pin "F6") (pinfunction "CTRL_OUT4_F6") (pintype "bidirectional"))
    )
    (net (code "411") (name "TRX_CTRL_OUT5") (class "Default")
      (node (ref "U201") (pin "E21") (pinfunction "IO_L23P/T3_E21") (pintype "bidirectional"))
      (node (ref "U401") (pin "F5") (pinfunction "CTRL_OUT5_F5") (pintype "bidirectional"))
    )
    (net (code "412") (name "TRX_CTRL_OUT6") (class "Default")
      (node (ref "U201") (pin "D19") (pinfunction "IO_L14N/T2/SRCC_D19") (pintype "bidirectional"))
      (node (ref "U401") (pin "F4") (pinfunction "CTRL_OUT6_F4") (pintype "bidirectional"))
    )
    (net (code "413") (name "TRX_CTRL_OUT7") (class "Default")
      (node (ref "U201") (pin "E19") (pinfunction "IO_L14P/T2/SRCC_E19") (pintype "bidirectional"))
      (node (ref "U401") (pin "G4") (pinfunction "CTRL_OUT7_G4") (pintype "bidirectional"))
    )
    (net (code "414") (name "TRX_DATA_CLK") (class "Default")
      (node (ref "U201") (pin "K18") (pinfunction "IO_L13P/T2/MRCC_K18") (pintype "bidirectional"))
      (node (ref "U401") (pin "G11") (pinfunction "DATA_CLK_P_G11") (pintype "bidirectional"))
    )
    (net (code "415") (name "TRX_ENABLE") (class "Default")
      (node (ref "U201") (pin "F16") (pinfunction "IO_L2P/T0_F16") (pintype "bidirectional"))
      (node (ref "U401") (pin "G6") (pinfunction "ENABLE_G6") (pintype "bidirectional"))
    )
    (net (code "416") (name "TRX_EN_AGC") (class "Default")
      (node (ref "U201") (pin "F15") (pinfunction "IO_0_F15") (pintype "bidirectional"))
      (node (ref "U401") (pin "G5") (pinfunction "EN_AGC_G5") (pintype "bidirectional"))
    )
    (net (code "417") (name "TRX_FB_CLK") (class "Default")
      (node (ref "U201") (pin "J19") (pinfunction "IO_L12P/T1/MRCC_J19") (pintype "bidirectional"))
      (node (ref "U401") (pin "F10") (pinfunction "FB_CLK_P_F10") (pintype "bidirectional"))
    )
    (net (code "418") (name "TRX_P0_D0") (class "Default")
      (node (ref "U201") (pin "L16") (pinfunction "IO_L23P/T3/~{FOE}_L16") (pintype "bidirectional"))
      (node (ref "U401") (pin "E12") (pinfunction "P0_D0/TX_D0_N_E12") (pintype "bidirectional"))
    )
    (net (code "419") (name "TRX_P0_D1") (class "Default")
      (node (ref "U201") (pin "L13") (pinfunction "IO_L20N/T3/A19_L13") (pintype "bidirectional"))
      (node (ref "U401") (pin "D11") (pinfunction "P0_D1/TX_D0_P_D11") (pintype "bidirectional"))
    )
    (net (code "420") (name "TRX_P0_D2") (class "Default")
      (node (ref "U201") (pin "L15") (pinfunction "IO_L22N/T3/A16_L15") (pintype "bidirectional"))
      (node (ref "U401") (pin "E11") (pinfunction "P0_D2/TX_D1_N_E11") (pintype "bidirectional"))
    )
    (net (code "421") (name "TRX_P0_D3") (class "Default")
      (node (ref "U201") (pin "M13") (pinfunction "IO_L20P/T3/A20_M13") (pintype "bidirectional"))
      (node (ref "U401") (pin "D10") (pinfunction "P0_D3/TX_D1_P_D10") (pintype "bidirectional"))
    )
    (net (code "422") (name "TRX_P0_D4") (class "Default")
      (node (ref "U201") (pin "L14") (pinfunction "IO_L22P/T3/A17_L14") (pintype "bidirectional"))
      (node (ref "U401") (pin "E10") (pinfunction "P0_D4/TX_D2_N_E10") (pintype "bidirectional"))
    )
    (net (code "423") (name "TRX_P0_D5") (class "Default")
      (node (ref "U201") (pin "M18") (pinfunction "IO_L16P/T2/A28_M18") (pintype "bidirectional"))
      (node (ref "U401") (pin "D9") (pinfunction "P0_D5/TX_D2_P_D9") (pintype "bidirectional"))
    )
    (net (code "424") (name "TRX_P0_D6") (class "Default")
      (node (ref "U201") (pin "L18") (pinfunction "IO_L16N/T2/A27_L18") (pintype "bidirectional"))
      (node (ref "U401") (pin "E9") (pinfunction "P0_D6/TX_D3_N_E9") (pintype "bidirectional"))
    )
    (net (code "425") (name "TRX_P0_D7") (class "Default")
      (node (ref "U201") (pin "M17") (pinfunction "IO_25_M17") (pintype "bidirectional"))
      (node (ref "U401") (pin "D8") (pinfunction "P0_D7/TX_D3_P_D8") (pintype "bidirectional"))
    )
    (net (code "426") (name "TRX_P0_D8") (class "Default")
      (node (ref "U201") (pin "L19") (pinfunction "IO_L14P/T2/SRCC_L19") (pintype "bidirectional"))
      (node (ref "U401") (pin "E8") (pinfunction "P0_D8/TX_D4_N_E8") (pintype "bidirectional"))
    )
    (net (code "427") (name "TRX_P0_D9") (class "Default")
      (node (ref "U201") (pin "M16") (pinfunction "IO_L24N/T3/RS0_M16") (pintype "bidirectional"))
      (node (ref "U401") (pin "D7") (pinfunction "P0_D9/TX_D4_P_D7") (pintype "bidirectional"))
    )
    (net (code "428") (name "TRX_P0_D10") (class "Default")
      (node (ref "U201") (pin "L21") (pinfunction "IO_L10N/T1/AD11N_L21") (pintype "bidirectional"))
      (node (ref "U401") (pin "F8") (pinfunction "P0_D10/TX_D5_N_F8") (pintype "bidirectional"))
    )
    (net (code "429") (name "TRX_P0_D11") (class "Default")
      (node (ref "U201") (pin "L20") (pinfunction "IO_L14N/T2/SRCC_L20") (pintype "bidirectional"))
      (node (ref "U401") (pin "E7") (pinfunction "P0_D11/TX_D5_P_E7") (pintype "bidirectional"))
    )
    (net (code "430") (name "TRX_P1_D0") (class "Default")
      (node (ref "U201") (pin "H14") (pinfunction "IO_L3N/T0_DQS/AD1N_H14") (pintype "bidirectional"))
      (node (ref "U401") (pin "K11") (pinfunction "P1_D0/RX_D0_N_K11") (pintype "bidirectional"))
    )
    (net (code "431") (name "TRX_P1_D1") (class "Default")
      (node (ref "U201") (pin "K14") (pinfunction "IO_L19N/T3/VREF/A21_K14") (pintype "bidirectional"))
      (node (ref "U401") (pin "J12") (pinfunction "P1_D1/RX_D0_P_J12") (pintype "bidirectional"))
    )
    (net (code "432") (name "TRX_P1_D2") (class "Default")
      (node (ref "U201") (pin "H15") (pinfunction "IO_L5N/T0/AD9N_H15") (pintype "bidirectional"))
      (node (ref "U401") (pin "K10") (pinfunction "P1_D2/RX_D1_N_K10") (pintype "bidirectional"))
    )
    (net (code "433") (name "TRX_P1_D3") (class "Default")
      (node (ref "U201") (pin "K13") (pinfunction "IO_L19P/T3/A22_K13") (pintype "bidirectional"))
      (node (ref "U401") (pin "J11") (pinfunction "P1_D3/RX_D1_P_J11") (pintype "bidirectional"))
    )
    (net (code "434") (name "TRX_P1_D4") (class "Default")
      (node (ref "U201") (pin "H17") (pinfunction "IO_L6P/T0_H17") (pintype "bidirectional"))
      (node (ref "U401") (pin "K9") (pinfunction "P1_D4/RX_D2_N_K9") (pintype "bidirectional"))
    )
    (net (code "435") (name "TRX_P1_D5") (class "Default")
      (node (ref "U201") (pin "H13") (pinfunction "IO_L1P/T0/AD0P_H13") (pintype "bidirectional"))
      (node (ref "U401") (pin "J10") (pinfunction "P1_D5/RX_D2_P_J10") (pintype "bidirectional"))
    )
    (net (code "436") (name "TRX_P1_D6") (class "Default")
      (node (ref "U201") (pin "H18") (pinfunction "IO_L6N/T0/VREF_H18") (pintype "bidirectional"))
      (node (ref "U401") (pin "K8") (pinfunction "P1_D6/RX_D3_N_K8") (pintype "bidirectional"))
    )
    (net (code "437") (name "TRX_P1_D7") (class "Default")
      (node (ref "U201") (pin "K16") (pinfunction "IO_L23N/T3/~{FWE}_K16") (pintype "bidirectional"))
      (node (ref "U401") (pin "J9") (pinfunction "P1_D7/RX_D3_P_J9") (pintype "bidirectional"))
    )
    (net (code "438") (name "TRX_P1_D8") (class "Default")
      (node (ref "U201") (pin "G21") (pinfunction "IO_L24P/T3_G21") (pintype "bidirectional"))
      (node (ref "U401") (pin "K7") (pinfunction "P1_D8/RX_D4_N_K7") (pintype "bidirectional"))
    )
    (net (code "439") (name "TRX_P1_D9") (class "Default")
      (node (ref "U201") (pin "K17") (pinfunction "IO_L21P/T3_DQS_K17") (pintype "bidirectional"))
      (node (ref "U401") (pin "J8") (pinfunction "P1_D9/RX_D4_P_J8") (pintype "bidirectional"))
    )
    (net (code "440") (name "TRX_P1_D10") (class "Default")
      (node (ref "U201") (pin "J22") (pinfunction "IO_L7P/T1/AD2P_J22") (pintype "bidirectional"))
      (node (ref "U401") (pin "J7") (pinfunction "P1_D10/RX_D5_N_J7") (pintype "bidirectional"))
    )
    (net (code "441") (name "TRX_P1_D11") (class "Default")
      (node (ref "U201") (pin "J21") (pinfunction "IO_L11N/T1/SRCC_J21") (pintype "bidirectional"))
      (node (ref "U401") (pin "H8") (pinfunction "P1_D11/RX_D5_P_H8") (pintype "bidirectional"))
    )
    (net (code "442") (name "TRX_REF_CLK") (class "Default")
      (node (ref "R401") (pin "2") (pinfunction "2_2") (pintype "passive"))
      (node (ref "R908") (pin "1") (pinfunction "1_1") (pintype "passive"))
    )
    (net (code "443") (name "TRX_RX1A_N") (class "Default")
      (node (ref "C509") (pin "2") (pinfunction "C2_2") (pintype "passive"))
      (node (ref "U401") (pin "M2") (pinfunction "RX1A_N_M2") (pintype "bidirectional"))
    )
    (net (code "444") (name "TRX_RX1A_P") (class "Default")
      (node (ref "C510") (pin "2") (pinfunction "C2_2") (pintype "passive"))
      (node (ref "U401") (pin "M1") (pinfunction "RX1A_P_M1") (pintype "bidirectional"))
    )
    (net (code "445") (name "TRX_RX1C_N") (class "Default")
      (node (ref "C513") (pin "2") (pinfunction "C2_2") (pintype "passive"))
      (node (ref "U401") (pin "L1") (pinfunction "RX1C_N_L1") (pintype "bidirectional"))
    )
    (net (code "446") (name "TRX_RX1C_P") (class "Default")
      (node (ref "C514") (pin "2") (pinfunction "C2_2") (pintype "passive"))
      (node (ref "U401") (pin "K1") (pinfunction "RX1C_P_K1") (pintype "bidirectional"))
    )
    (net (code "447") (name "TRX_RX2A_N") (class "Default")
      (node (ref "C511") (pin "2") (pinfunction "C2_2") (pintype "passive"))
      (node (ref "U401") (pin "A1") (pinfunction "RX2A_N_A1") (pintype "bidirectional"))
    )
    (net (code "448") (name "TRX_RX2A_P") (class "Default")
      (node (ref "C512") (pin "2") (pinfunction "C2_2") (pintype "passive"))
      (node (ref "U401") (pin "A2") (pinfunction "RX2A_P_A2") (pintype "bidirectional"))
    )
    (net (code "449") (name "TRX_RX2C_N") (class "Default")
      (node (ref "C515") (pin "2") (pinfunction "C2_2") (pintype "passive"))
      (node (ref "U401") (pin "D1") (pinfunction "RX2C_N_D1") (pintype "bidirectional"))
    )
    (net (code "450") (name "TRX_RX2C_P") (class "Default")
      (node (ref "C516") (pin "2") (pinfunction "C2_2") (pintype "passive"))
      (node (ref "U401") (pin "C1") (pinfunction "RX2C_P_C1") (pintype "bidirectional"))
    )
    (net (code "451") (name "TRX_RX_FRAME") (class "Default")
      (node (ref "U201") (pin "K22") (pinfunction "IO_L9N/T1_DQS/AD3N_K22") (pintype "bidirectional"))
      (node (ref "U401") (pin "G8") (pinfunction "RX_FRAME_P_G8") (pintype "bidirectional"))
    )
    (net (code "452") (name "TRX_SPI_MISO") (class "Default")
      (node (ref "U201") (pin "G18") (pinfunction "IO_L4N/T0_G18") (pintype "bidirectional"))
      (node (ref "U401") (pin "L6") (pinfunction "SPI_DO_L6") (pintype "bidirectional"))
    )
    (net (code "453") (name "TRX_SPI_MOSI") (class "Default")
      (node (ref "U201") (pin "G17") (pinfunction "IO_L4P/T0_G17") (pintype "bidirectional"))
      (node (ref "U401") (pin "J4") (pinfunction "SPI_DI_J4") (pintype "bidirectional"))
    )
    (net (code "454") (name "TRX_SPI_SCK") (class "Default")
      (node (ref "U201") (pin "G15") (pinfunction "IO_L2P/T0/AD8P_G15") (pintype "bidirectional"))
      (node (ref "U401") (pin "J5") (pinfunction "SPI_CLK_J5") (pintype "bidirectional"))
    )
    (net (code "455") (name "TRX_SYNC_IN") (class "Default")
      (node (ref "U201") (pin "F18") (pinfunction "IO_L15P/T2_DQS_F18") (pintype "bidirectional"))
      (node (ref "U401") (pin "H5") (pinfunction "SYNC_IN_H5") (pintype "bidirectional"))
    )
    (net (code "456") (name "TRX_TX1A_N") (class "Default")
      (node (ref "C544") (pin "1") (pinfunction "C1_1") (pintype "passive"))
      (node (ref "L509") (pin "2") (pinfunction "2_2") (pintype "passive"))
      (node (ref "U401") (pin "M8") (pinfunction "TX1A_N_M8") (pintype "bidirectional"))
    )
    (net (code "457") (name "TRX_TX1A_P") (class "Default")
      (node (ref "C545") (pin "1") (pinfunction "C1_1") (pintype "passive"))
      (node (ref "L507") (pin "2") (pinfunction "2_2") (pintype "passive"))
      (node (ref "U401") (pin "M7") (pinfunction "TX1A_P_M7") (pintype "bidirectional"))
    )
    (net (code "458") (name "TRX_TX1B_N") (class "Default")
      (node (ref "C530") (pin "1") (pinfunction "C1_1") (pintype "passive"))
      (node (ref "L505") (pin "2") (pinfunction "2_2") (pintype "passive"))
      (node (ref "U401") (pin "M10") (pinfunction "TX1B_N_M10") (pintype "bidirectional"))
    )
    (net (code "459") (name "TRX_TX1B_P") (class "Default")
      (node (ref "C531") (pin "1") (pinfunction "C1_1") (pintype "passive"))
      (node (ref "L503") (pin "2") (pinfunction "2_2") (pintype "passive"))
      (node (ref "U401") (pin "M9") (pinfunction "TX1B_P_M9") (pintype "bidirectional"))
    )
    (net (code "460") (name "TRX_TX2A_N") (class "Default")
      (node (ref "C546") (pin "1") (pinfunction "C1_1") (pintype "passive"))
      (node (ref "L510") (pin "2") (pinfunction "2_2") (pintype "passive"))
      (node (ref "U401") (pin "A7") (pinfunction "TX2A_N_A7") (pintype "bidirectional"))
    )
    (net (code "461") (name "TRX_TX2A_P") (class "Default")
      (node (ref "C547") (pin "1") (pinfunction "C1_1") (pintype "passive"))
      (node (ref "L508") (pin "2") (pinfunction "2_2") (pintype "passive"))
      (node (ref "U401") (pin "A8") (pinfunction "TX2A_P_A8") (pintype "bidirectional"))
    )
    (net (code "462") (name "TRX_TX2B_N") (class "Default")
      (node (ref "C532") (pin "1") (pinfunction "C1_1") (pintype "passive"))
      (node (ref "L506") (pin "2") (pinfunction "2_2") (pintype "passive"))
      (node (ref "U401") (pin "A9") (pinfunction "TX2B_N_A9") (pintype "bidirectional"))
    )
    (net (code "463") (name "TRX_TX2B_P") (class "Default")
      (node (ref "C533") (pin "1") (pinfunction "C1_1") (pintype "passive"))
      (node (ref "L504") (pin "2") (pinfunction "2_2") (pintype "passive"))
      (node (ref "U401") (pin "A10") (pinfunction "TX2B_P_A10") (pintype "bidirectional"))
    )
    (net (code "464") (name "TRX_TXMON1") (class "Default")
      (node (ref "C529") (pin "2") (pinfunction "C2_2") (pintype "passive"))
      (node (ref "U401") (pin "M5") (pinfunction "TX_MON1_M5") (pintype "bidirectional"))
    )
    (net (code "465") (name "TRX_TXMON2") (class "Default")
      (node (ref "C550") (pin "2") (pinfunction "C2_2") (pintype "passive"))
      (node (ref "U401") (pin "A5") (pinfunction "TX_MON2_A5") (pintype "bidirectional"))
    )
    (net (code "466") (name "TRX_TX_FRAME") (class "Default")
      (node (ref "U201") (pin "K21") (pinfunction "IO_L9P/T1_DQS/AD3P_K21") (pintype "bidirectional"))
      (node (ref "U401") (pin "G9") (pinfunction "TX_FRAME_P_G9") (pintype "bidirectional"))
    )
    (net (code "467") (name "TRX_TX{slash}~{RX}") (class "Default")
      (node (ref "U201") (pin "F14") (pinfunction "IO_L1N/T0_F14") (pintype "bidirectional"))
      (node (ref "U401") (pin "H4") (pinfunction "TX/~{RX}_H4") (pintype "bidirectional"))
    )
    (net (code "468") (name "USB_CC1") (class "Default")
      (node (ref "C1002") (pin "1") (pinfunction "C1_1") (pintype "passive"))
      (node (ref "U1002") (pin "4") (pinfunction "CC1_4") (pintype "bidirectional"))
      (node (ref "USB1001") (pin "A5") (pinfunction "CC1_A5") (pintype "bidirectional"))
    )
    (net (code "469") (name "USB_CC2") (class "Default")
      (node (ref "C1004") (pin "1") (pinfunction "C1_1") (pintype "passive"))
      (node (ref "U1002") (pin "2") (pinfunction "CC2_2") (pintype "bidirectional"))
      (node (ref "USB1001") (pin "B5") (pinfunction "CC2_B5") (pintype "bidirectional"))
    )
    (net (code "470") (name "USB_D_N") (class "Default")
      (node (ref "L1001") (pin "2") (pinfunction "2_2") (pintype "passive"))
      (node (ref "U102") (pin "103") (pinfunction "USB_DN_103") (pintype "bidirectional"))
    )
    (net (code "471") (name "USB_D_P") (class "Default")
      (node (ref "L1001") (pin "3") (pinfunction "3_3") (pintype "passive"))
      (node (ref "U102") (pin "105") (pinfunction "USB_DP_105") (pintype "bidirectional"))
    )
    (net (code "472") (name "USB_VBUS_DET") (class "Default")
      (node (ref "C1006") (pin "1") (pinfunction "C1_1") (pintype "passive"))
      (node (ref "R1005") (pin "1") (pinfunction "1_1") (pintype "passive"))
      (node (ref "R1006") (pin "2") (pinfunction "2_2") (pintype "passive"))
      (node (ref "U1002") (pin "9") (pinfunction "VBUS_DET_IN_9") (pintype "bidirectional"))
    )
    (net (code "473") (name "VBUS") (class "Default")
      (node (ref "C1103") (pin "1") (pinfunction "C1_1") (pintype "passive"))
      (node (ref "D1002") (pin "C") (pinfunction "C_C") (pintype "passive"))
      (node (ref "D1003") (pin "C") (pinfunction "C_C") (pintype "passive"))
      (node (ref "D1101") (pin "A") (pinfunction "A_A") (pintype "passive"))
      (node (ref "F1001") (pin "1") (pinfunction "1_1") (pintype "passive"))
      (node (ref "Q1102") (pin "5") (pinfunction "D_5") (pintype "passive"))
      (node (ref "Q1102") (pin "6") (pinfunction "D_6") (pintype "passive"))
      (node (ref "R1005") (pin "2") (pinfunction "2_2") (pintype "passive"))
      (node (ref "R1110") (pin "2") (pinfunction "2_2") (pintype "passive"))
    )
    (net (code "474") (name "VBUS_SNK_EN") (class "Default")
      (node (ref "Q1101") (pin "1") (pinfunction "G_1") (pintype "passive"))
      (node (ref "R1105") (pin "2") (pinfunction "2_2") (pintype "passive"))
      (node (ref "U1002") (pin "39") (pinfunction "PA27/GPIO9_39") (pintype "bidirectional"))
    )
    (net (code "475") (name "VBUS_SRC_EN") (class "Default")
      (node (ref "R1009") (pin "2") (pinfunction "2_2") (pintype "passive"))
      (node (ref "U1002") (pin "26") (pinfunction "GPIO2_26") (pintype "bidirectional"))
      (node (ref "U1003") (pin "3") (pinfunction "EN_3") (pintype "bidirectional"))
    )
    (net (code "476") (name "VBUS_VSENSE") (class "Default")
      (node (ref "C1107") (pin "1") (pinfunction "C1_1") (pintype "passive"))
      (node (ref "R1110") (pin "1") (pinfunction "1_1") (pintype "passive"))
      (node (ref "R1111") (pin "2") (pinfunction "2_2") (pintype "passive"))
      (node (ref "U1002") (pin "12") (pinfunction "PA02_12") (pintype "bidirectional"))
    )
    (net (code "477") (name "VEXT") (class "Default")
      (node (ref "C1110") (pin "1") (pinfunction "C1_1") (pintype "passive"))
      (node (ref "D1103") (pin "A") (pinfunction "A_A") (pintype "passive"))
      (node (ref "D1105") (pin "C") (pinfunction "C_C") (pintype "passive"))
      (node (ref "F1101") (pin "1") (pinfunction "1_1") (pintype "passive"))
      (node (ref "Q1105") (pin "7") (pinfunction "D_7") (pintype "passive"))
      (node (ref "Q1105") (pin "8") (pinfunction "D_8") (pintype "passive"))
      (node (ref "R1103") (pin "2") (pinfunction "2_2") (pintype "passive"))
    )
    (net (code "478") (name "VEXT_EN") (class "Default")
      (node (ref "Q1106") (pin "1") (pinfunction "G_1") (pintype "passive"))
      (node (ref "R1115") (pin "2") (pinfunction "2_2") (pintype "passive"))
      (node (ref "U1002") (pin "19") (pinfunction "PA06_19") (pintype "bidirectional"))
    )
    (net (code "479") (name "VEXT_VSENSE") (class "Default")
      (node (ref "C1102") (pin "1") (pinfunction "C1_1") (pintype "passive"))
      (node (ref "R1103") (pin "1") (pinfunction "1_1") (pintype "passive"))
      (node (ref "R1104") (pin "2") (pinfunction "2_2") (pintype "passive"))
      (node (ref "U1002") (pin "18") (pinfunction "PA05_18") (pintype "bidirectional"))
    )
    (net (code "480") (name "VIN") (class "Default")
      (node (ref "C1111") (pin "1") (pinfunction "C1_1") (pintype "passive"))
      (node (ref "C1112") (pin "1") (pinfunction "C1_1") (pintype "passive"))
      (node (ref "C1116") (pin "1") (pinfunction "C1_1") (pintype "passive"))
      (node (ref "C1117") (pin "1") (pinfunction "C1_1") (pintype "passive"))
      (node (ref "C1118") (pin "1") (pinfunction "C1_1") (pintype "passive"))
      (node (ref "C1119") (pin "1") (pinfunction "C1_1") (pintype "passive"))
      (node (ref "Q1102") (pin "7") (pinfunction "D_7") (pintype "passive"))
      (node (ref "Q1102") (pin "8") (pinfunction "D_8") (pintype "passive"))
      (node (ref "Q1104") (pin "7") (pinfunction "D_7") (pintype "passive"))
      (node (ref "Q1104") (pin "8") (pinfunction "D_8") (pintype "passive"))
      (node (ref "Q1105") (pin "5") (pinfunction "D_5") (pintype "passive"))
      (node (ref "Q1105") (pin "6") (pinfunction "D_6") (pintype "passive"))
      (node (ref "R1101") (pin "2") (pinfunction "2_2") (pintype "passive"))
      (node (ref "U1102") (pin "15") (pinfunction "PVIN_15") (pintype "bidirectional"))
      (node (ref "U1102") (pin "18") (pinfunction "PVIN_18") (pintype "bidirectional"))
      (node (ref "U1102") (pin "35") (pinfunction "PVIN_35") (pintype "bidirectional"))
      (node (ref "U1102") (pin "38") (pinfunction "PVIN_38") (pintype "bidirectional"))
    )
    (net (code "481") (name "VIN_REG_SHARE_CLK") (class "Default")
      (node (ref "R1124") (pin "1") (pinfunction "1_1") (pintype "passive"))
      (node (ref "U1102") (pin "25") (pinfunction "SHARE_CLK_25") (pintype "bidirectional"))
    )
    (net (code "482") (name "VIN_VSENSE") (class "Default")
      (node (ref "C1101") (pin "1") (pinfunction "C1_1") (pintype "passive"))
      (node (ref "R1101") (pin "1") (pinfunction "1_1") (pintype "passive"))
      (node (ref "R1102") (pin "2") (pinfunction "2_2") (pintype "passive"))
      (node (ref "U1002") (pin "13") (pinfunction "PA03_13") (pintype "bidirectional"))
    )
    (net (code "483") (name "unconnected-(J701-DT-Pad4)") (class "Default")
      (node (ref "J701") (pin "4") (pinfunction "DT_4") (pintype "bidirectional"))
    )
    (net (code "484") (name "unconnected-(J702-DT-Pad4)") (class "Default")
      (node (ref "J702") (pin "4") (pinfunction "DT_4") (pintype "bidirectional"))
    )
    (net (code "485") (name "unconnected-(J703-DT-Pad4)") (class "Default")
      (node (ref "J703") (pin "4") (pinfunction "DT_4") (pintype "bidirectional"))
    )
    (net (code "486") (name "unconnected-(SD101-SWA-Pad9)") (class "Default")
      (node (ref "SD101") (pin "9") (pinfunction "SWA_9") (pintype "passive"))
    )
    (net (code "487") (name "unconnected-(SD101-SWB-Pad10)") (class "Default")
      (node (ref "SD101") (pin "10") (pinfunction "SWB_10") (pintype "passive"))
    )
    (net (code "488") (name "unconnected-(TC201F-S-Pad5)") (class "Default")
      (node (ref "TC201") (pin "5") (pinfunction "S_5") (pintype "passive"))
    )
    (net (code "489") (name "unconnected-(TC1001F-S-Pad5)") (class "Default")
      (node (ref "TC1001") (pin "5") (pinfunction "S_5") (pintype "passive"))
    )
    (net (code "490") (name "unconnected-(U101-~{FAULT}-Pad4)") (class "Default")
      (node (ref "U101") (pin "4") (pinfunction "~{FAULT}_4") (pintype "bidirectional"))
    )
    (net (code "491") (name "unconnected-(U102E-~{ETH_LED1}-Pad19)") (class "Default")
      (node (ref "U102") (pin "19") (pinfunction "~{ETH_LED1}_19") (pintype "bidirectional"))
    )
    (net (code "492") (name "unconnected-(U102F-GPIO2-Pad58)") (class "Default")
      (node (ref "U102") (pin "58") (pinfunction "GPIO2_58") (pintype "bidirectional"))
    )
    (net (code "493") (name "unconnected-(U102F-GPIO4-Pad54)") (class "Default")
      (node (ref "U102") (pin "54") (pinfunction "GPIO4_54") (pintype "bidirectional"))
    )
    (net (code "494") (name "unconnected-(U102F-GPIO5-Pad34)") (class "Default")
      (node (ref "U102") (pin "34") (pinfunction "GPIO5_34") (pintype "bidirectional"))
    )
    (net (code "495") (name "unconnected-(U102F-GPIO6-Pad30)") (class "Default")
      (node (ref "U102") (pin "30") (pinfunction "GPIO6_30") (pintype "bidirectional"))
    )
    (net (code "496") (name "unconnected-(U102F-GPIO7-Pad37)") (class "Default")
      (node (ref "U102") (pin "37") (pinfunction "GPIO7_37") (pintype "bidirectional"))
    )
    (net (code "497") (name "unconnected-(U102F-GPIO8-Pad39)") (class "Default")
      (node (ref "U102") (pin "39") (pinfunction "GPIO8_39") (pintype "bidirectional"))
    )
    (net (code "498") (name "unconnected-(U102F-GPIO9-Pad40)") (class "Default")
      (node (ref "U102") (pin "40") (pinfunction "GPIO9_40") (pintype "bidirectional"))
    )
    (net (code "499") (name "unconnected-(U102F-GPIO10-Pad44)") (class "Default")
      (node (ref "U102") (pin "44") (pinfunction "GPIO10_44") (pintype "bidirectional"))
    )
    (net (code "500") (name "unconnected-(U102F-GPIO11-Pad38)") (class "Default")
      (node (ref "U102") (pin "38") (pinfunction "GPIO11_38") (pintype "bidirectional"))
    )
    (net (code "501") (name "unconnected-(U102F-GPIO12-Pad31)") (class "Default")
      (node (ref "U102") (pin "31") (pinfunction "GPIO12_31") (pintype "bidirectional"))
    )
    (net (code "502") (name "unconnected-(U102F-GPIO13-Pad28)") (class "Default")
      (node (ref "U102") (pin "28") (pinfunction "GPIO13_28") (pintype "bidirectional"))
    )
    (net (code "503") (name "unconnected-(U102F-GPIO16-Pad29)") (class "Default")
      (node (ref "U102") (pin "29") (pinfunction "GPIO16_29") (pintype "bidirectional"))
    )
    (net (code "504") (name "unconnected-(U102F-GPIO17-Pad50)") (class "Default")
      (node (ref "U102") (pin "50") (pinfunction "GPIO17_50") (pintype "bidirectional"))
    )
    (net (code "505") (name "unconnected-(U102F-GPIO18-Pad49)") (class "Default")
      (node (ref "U102") (pin "49") (pinfunction "GPIO18_49") (pintype "bidirectional"))
    )
    (net (code "506") (name "unconnected-(U102F-GPIO19-Pad26)") (class "Default")
      (node (ref "U102") (pin "26") (pinfunction "GPIO19_26") (pintype "bidirectional"))
    )
    (net (code "507") (name "unconnected-(U102F-GPIO20-Pad27)") (class "Default")
      (node (ref "U102") (pin "27") (pinfunction "GPIO20_27") (pintype "bidirectional"))
    )
    (net (code "508") (name "unconnected-(U102F-GPIO21-Pad25)") (class "Default")
      (node (ref "U102") (pin "25") (pinfunction "GPIO21_25") (pintype "bidirectional"))
    )
    (net (code "509") (name "unconnected-(U102F-GPIO22-Pad46)") (class "Default")
      (node (ref "U102") (pin "46") (pinfunction "GPIO22_46") (pintype "bidirectional"))
    )
    (net (code "510") (name "unconnected-(U102F-GPIO23-Pad47)") (class "Default")
      (node (ref "U102") (pin "47") (pinfunction "GPIO23_47") (pintype "bidirectional"))
    )
    (net (code "511") (name "unconnected-(U102F-GPIO24-Pad45)") (class "Default")
      (node (ref "U102") (pin "45") (pinfunction "GPIO24_45") (pintype "bidirectional"))
    )
    (net (code "512") (name "unconnected-(U102F-GPIO25-Pad41)") (class "Default")
      (node (ref "U102") (pin "41") (pinfunction "GPIO25_41") (pintype "bidirectional"))
    )
    (net (code "513") (name "unconnected-(U102F-GPIO26-Pad24)") (class "Default")
      (node (ref "U102") (pin "24") (pinfunction "GPIO26_24") (pintype "bidirectional"))
    )
    (net (code "514") (name "unconnected-(U102F-GPIO27-Pad48)") (class "Default")
      (node (ref "U102") (pin "48") (pinfunction "GPIO27_48") (pintype "bidirectional"))
    )
    (net (code "515") (name "unconnected-(U102J-AIP0-Pad96)") (class "Default")
      (node (ref "U102") (pin "96") (pinfunction "AIP0_96") (pintype "bidirectional"))
    )
    (net (code "516") (name "unconnected-(U102J-AIP1-Pad94)") (class "Default")
      (node (ref "U102") (pin "94") (pinfunction "AIP1_94") (pintype "bidirectional"))
    )
    (net (code "517") (name "unconnected-(U102J-~{EXTRST}-Pad100)") (class "Default")
      (node (ref "U102") (pin "100") (pinfunction "~{EXTRST}_100") (pintype "bidirectional"))
    )
    (net (code "518") (name "unconnected-(U102K-SD_DAT4-Pad68)") (class "Default")
      (node (ref "U102") (pin "68") (pinfunction "SD_DAT4_68") (pintype "bidirectional"))
    )
    (net (code "519") (name "unconnected-(U102K-SD_DAT5-Pad64)") (class "Default")
      (node (ref "U102") (pin "64") (pinfunction "SD_DAT5_64") (pintype "bidirectional"))
    )
    (net (code "520") (name "unconnected-(U102K-SD_DAT6-Pad72)") (class "Default")
      (node (ref "U102") (pin "72") (pinfunction "SD_DAT6_72") (pintype "bidirectional"))
    )
    (net (code "521") (name "unconnected-(U102K-SD_DAT7-Pad70)") (class "Default")
      (node (ref "U102") (pin "70") (pinfunction "SD_DAT7_70") (pintype "bidirectional"))
    )
    (net (code "522") (name "unconnected-(U102K-SD_VDD_OVR-Pad73)") (class "Default")
      (node (ref "U102") (pin "73") (pinfunction "SD_VDD_OVR_73") (pintype "bidirectional"))
    )
    (net (code "523") (name "unconnected-(U201C-IO_L1P{slash}T0-PadY16)") (class "Default")
      (node (ref "U201") (pin "Y16") (pinfunction "IO_L1P/T0_Y16") (pintype "bidirectional"))
    )
    (net (code "524") (name "unconnected-(U201C-IO_L4N{slash}T0-PadAB15)") (class "Default")
      (node (ref "U201") (pin "AB15") (pinfunction "IO_L4N/T0_AB15") (pintype "bidirectional"))
    )
    (net (code "525") (name "unconnected-(U201C-IO_L5P{slash}T0-PadY13)") (class "Default")
      (node (ref "U201") (pin "Y13") (pinfunction "IO_L5P/T0_Y13") (pintype "bidirectional"))
    )
    (net (code "526") (name "unconnected-(U201C-IO_L6N{slash}T0{slash}VREF-PadY14)") (class "Default")
      (node (ref "U201") (pin "Y14") (pinfunction "IO_L6N/T0/VREF_Y14") (pintype "bidirectional"))
    )
    (net (code "527") (name "unconnected-(U201C-IO_L6P{slash}T0-PadW14)") (class "Default")
      (node (ref "U201") (pin "W14") (pinfunction "IO_L6P/T0_W14") (pintype "bidirectional"))
    )
    (net (code "528") (name "unconnected-(U201C-IO_L7N{slash}T1-PadAB12)") (class "Default")
      (node (ref "U201") (pin "AB12") (pinfunction "IO_L7N/T1_AB12") (pintype "bidirectional"))
    )
    (net (code "529") (name "unconnected-(U201C-IO_L10N{slash}T1-PadW10)") (class "Default")
      (node (ref "U201") (pin "W10") (pinfunction "IO_L10N/T1_W10") (pintype "bidirectional"))
    )
    (net (code "530") (name "unconnected-(U201C-IO_L10P{slash}T1-PadV10)") (class "Default")
      (node (ref "U201") (pin "V10") (pinfunction "IO_L10P/T1_V10") (pintype "bidirectional"))
    )
    (net (code "531") (name "unconnected-(U201C-IO_L11N{slash}T1{slash}SRCC-PadY12)") (class "Default")
      (node (ref "U201") (pin "Y12") (pinfunction "IO_L11N/T1/SRCC_Y12") (pintype "bidirectional"))
    )
    (net (code "532") (name "unconnected-(U201C-IO_L11P{slash}T1{slash}SRCC-PadY11)") (class "Default")
      (node (ref "U201") (pin "Y11") (pinfunction "IO_L11P/T1/SRCC_Y11") (pintype "bidirectional"))
    )
    (net (code "533") (name "unconnected-(U201C-IO_L12N{slash}T1{slash}MRCC-PadW12)") (class "Default")
      (node (ref "U201") (pin "W12") (pinfunction "IO_L12N/T1/MRCC_W12") (pintype "bidirectional"))
    )
    (net (code "534") (name "unconnected-(U201C-IO_L13N{slash}T2{slash}MRCC-PadV14)") (class "Default")
      (node (ref "U201") (pin "V14") (pinfunction "IO_L13N/T2/MRCC_V14") (pintype "bidirectional"))
    )
    (net (code "535") (name "unconnected-(U201C-IO_L14N{slash}T2{slash}SRCC-PadV15)") (class "Default")
      (node (ref "U201") (pin "V15") (pinfunction "IO_L14N/T2/SRCC_V15") (pintype "bidirectional"))
    )
    (net (code "536") (name "unconnected-(U201C-IO_L14P{slash}T2{slash}SRCC-PadU15)") (class "Default")
      (node (ref "U201") (pin "U15") (pinfunction "IO_L14P/T2/SRCC_U15") (pintype "bidirectional"))
    )
    (net (code "537") (name "unconnected-(U201C-IO_L15N{slash}T2_DQS-PadT15)") (class "Default")
      (node (ref "U201") (pin "T15") (pinfunction "IO_L15N/T2_DQS_T15") (pintype "bidirectional"))
    )
    (net (code "538") (name "unconnected-(U201C-IO_L15P{slash}T2_DQS-PadT14)") (class "Default")
      (node (ref "U201") (pin "T14") (pinfunction "IO_L15P/T2_DQS_T14") (pintype "bidirectional"))
    )
    (net (code "539") (name "unconnected-(U201C-IO_L17N{slash}T2-PadU16)") (class "Default")
      (node (ref "U201") (pin "U16") (pinfunction "IO_L17N/T2_U16") (pintype "bidirectional"))
    )
    (net (code "540") (name "unconnected-(U201C-IO_L17P{slash}T2-PadT16)") (class "Default")
      (node (ref "U201") (pin "T16") (pinfunction "IO_L17P/T2_T16") (pintype "bidirectional"))
    )
    (net (code "541") (name "unconnected-(U201D-IO_0-PadP20)") (class "Default")
      (node (ref "U201") (pin "P20") (pinfunction "IO_0_P20") (pintype "bidirectional"))
    )
    (net (code "542") (name "unconnected-(U201D-IO_25-PadN15)") (class "Default")
      (node (ref "U201") (pin "N15") (pinfunction "IO_25_N15") (pintype "bidirectional"))
    )
    (net (code "543") (name "unconnected-(U201D-IO_L4P{slash}T0{slash}D4-PadT21)") (class "Default")
      (node (ref "U201") (pin "T21") (pinfunction "IO_L4P/T0/D4_T21") (pintype "bidirectional"))
    )
    (net (code "544") (name "unconnected-(U201D-IO_L5N{slash}T0{slash}D7-PadR19)") (class "Default")
      (node (ref "U201") (pin "R19") (pinfunction "IO_L5N/T0/D7_R19") (pintype "bidirectional"))
    )
    (net (code "545") (name "unconnected-(U201D-IO_L5P{slash}T0{slash}D6-PadP19)") (class "Default")
      (node (ref "U201") (pin "P19") (pinfunction "IO_L5P/T0/D6_P19") (pintype "bidirectional"))
    )
    (net (code "546") (name "unconnected-(U201D-IO_L8N{slash}T1{slash}D12-PadAA21)") (class "Default")
      (node (ref "U201") (pin "AA21") (pinfunction "IO_L8N/T1/D12_AA21") (pintype "bidirectional"))
    )
    (net (code "547") (name "unconnected-(U201D-IO_L9P{slash}T1_DQS-PadY21)") (class "Default")
      (node (ref "U201") (pin "Y21") (pinfunction "IO_L9P/T1_DQS_Y21") (pintype "bidirectional"))
    )
    (net (code "548") (name "unconnected-(U201D-IO_L11P{slash}T1{slash}SRCC-PadU20)") (class "Default")
      (node (ref "U201") (pin "U20") (pinfunction "IO_L11P/T1/SRCC_U20") (pintype "bidirectional"))
    )
    (net (code "549") (name "unconnected-(U201D-IO_L14N{slash}T2{slash}SRCC-PadV19)") (class "Default")
      (node (ref "U201") (pin "V19") (pinfunction "IO_L14N/T2/SRCC_V19") (pintype "bidirectional"))
    )
    (net (code "550") (name "unconnected-(U201D-IO_L14P{slash}T2{slash}SRCC-PadV18)") (class "Default")
      (node (ref "U201") (pin "V18") (pinfunction "IO_L14P/T2/SRCC_V18") (pintype "bidirectional"))
    )
    (net (code "551") (name "unconnected-(U201D-IO_L18N{slash}T2{slash}A11{slash}D27-PadU18)") (class "Default")
      (node (ref "U201") (pin "U18") (pinfunction "IO_L18N/T2/A11/D27_U18") (pintype "bidirectional"))
    )
    (net (code "552") (name "unconnected-(U201D-IO_L18P{slash}T2{slash}A12{slash}D28-PadU17)") (class "Default")
      (node (ref "U201") (pin "U17") (pinfunction "IO_L18P/T2/A12/D28_U17") (pintype "bidirectional"))
    )
    (net (code "553") (name "unconnected-(U201D-IO_L19N{slash}T3{slash}VREF{slash}A9{slash}D25-PadR14)") (class "Default")
      (node (ref "U201") (pin "R14") (pinfunction "IO_L19N/T3/VREF/A9/D25_R14") (pintype "bidirectional"))
    )
    (net (code "554") (name "unconnected-(U201D-IO_L19P{slash}T3{slash}A10{slash}D26-PadP14)") (class "Default")
      (node (ref "U201") (pin "P14") (pinfunction "IO_L19P/T3/A10/D26_P14") (pintype "bidirectional"))
    )
    (net (code "555") (name "unconnected-(U201D-IO_L20N{slash}T3{slash}A7{slash}D23-PadT18)") (class "Default")
      (node (ref "U201") (pin "T18") (pinfunction "IO_L20N/T3/A7/D23_T18") (pintype "bidirectional"))
    )
    (net (code "556") (name "unconnected-(U201D-IO_L20P{slash}T3{slash}A8{slash}D24-PadR18)") (class "Default")
      (node (ref "U201") (pin "R18") (pinfunction "IO_L20P/T3/A8/D24_R18") (pintype "bidirectional"))
    )
    (net (code "557") (name "unconnected-(U201D-IO_L21N{slash}T3_DQS{slash}A6{slash}D22-PadP17)") (class "Default")
      (node (ref "U201") (pin "P17") (pinfunction "IO_L21N/T3_DQS/A6/D22_P17") (pintype "bidirectional"))
    )
    (net (code "558") (name "unconnected-(U201D-IO_L21P{slash}T3_DQS-PadN17)") (class "Default")
      (node (ref "U201") (pin "N17") (pinfunction "IO_L21P/T3_DQS_N17") (pintype "bidirectional"))
    )
    (net (code "559") (name "unconnected-(U201D-IO_L22N{slash}T3{slash}A4{slash}D20-PadR16)") (class "Default")
      (node (ref "U201") (pin "R16") (pinfunction "IO_L22N/T3/A4/D20_R16") (pintype "bidirectional"))
    )
    (net (code "560") (name "unconnected-(U201D-IO_L22P{slash}T3{slash}A5{slash}D21-PadP15)") (class "Default")
      (node (ref "U201") (pin "P15") (pinfunction "IO_L22P/T3/A5/D21_P15") (pintype "bidirectional"))
    )
    (net (code "561") (name "unconnected-(U201D-IO_L23N{slash}T3{slash}A2{slash}D18-PadN14)") (class "Default")
      (node (ref "U201") (pin "N14") (pinfunction "IO_L23N/T3/A2/D18_N14") (pintype "bidirectional"))
    )
    (net (code "562") (name "unconnected-(U201D-IO_L24N{slash}T3{slash}A0{slash}D16-PadR17)") (class "Default")
      (node (ref "U201") (pin "R17") (pinfunction "IO_L24N/T3/A0/D16_R17") (pintype "bidirectional"))
    )
    (net (code "563") (name "unconnected-(U201D-IO_L24P{slash}T3{slash}A1{slash}D17-PadP16)") (class "Default")
      (node (ref "U201") (pin "P16") (pinfunction "IO_L24P/T3/A1/D17_P16") (pintype "bidirectional"))
    )
    (net (code "564") (name "unconnected-(U201E-IO_0-PadJ16)") (class "Default")
      (node (ref "U201") (pin "J16") (pinfunction "IO_0_J16") (pintype "bidirectional"))
    )
    (net (code "565") (name "unconnected-(U201E-IO_L3P{slash}T0_DQS{slash}AD1P-PadJ14)") (class "Default")
      (node (ref "U201") (pin "J14") (pinfunction "IO_L3P/T0_DQS/AD1P_J14") (pintype "bidirectional"))
    )
    (net (code "566") (name "unconnected-(U201E-IO_L5P{slash}T0{slash}AD9P-PadJ15)") (class "Default")
      (node (ref "U201") (pin "J15") (pinfunction "IO_L5P/T0/AD9P_J15") (pintype "bidirectional"))
    )
    (net (code "567") (name "unconnected-(U201E-IO_L8N{slash}T1{slash}AD10N-PadG20)") (class "Default")
      (node (ref "U201") (pin "G20") (pinfunction "IO_L8N/T1/AD10N_G20") (pintype "bidirectional"))
    )
    (net (code "568") (name "unconnected-(U201E-IO_L13N{slash}T2{slash}MRCC-PadK19)") (class "Default")
      (node (ref "U201") (pin "K19") (pinfunction "IO_L13N/T2/MRCC_K19") (pintype "bidirectional"))
    )
    (net (code "569") (name "unconnected-(U201E-IO_L15N{slash}T2_DQS{slash}~{ADV}-PadM22)") (class "Default")
      (node (ref "U201") (pin "M22") (pinfunction "IO_L15N/T2_DQS/~{ADV}_M22") (pintype "bidirectional"))
    )
    (net (code "570") (name "unconnected-(U201E-IO_L21N{slash}T3_DQS{slash}A18-PadJ17)") (class "Default")
      (node (ref "U201") (pin "J17") (pinfunction "IO_L21N/T3_DQS/A18_J17") (pintype "bidirectional"))
    )
    (net (code "571") (name "unconnected-(U201F-IO_L1P{slash}T0-PadF13)") (class "Default")
      (node (ref "U201") (pin "F13") (pinfunction "IO_L1P/T0_F13") (pintype "bidirectional"))
    )
    (net (code "572") (name "unconnected-(U201F-IO_L2N{slash}T0-PadE17)") (class "Default")
      (node (ref "U201") (pin "E17") (pinfunction "IO_L2N/T0_E17") (pintype "bidirectional"))
    )
    (net (code "573") (name "unconnected-(U201F-IO_L3N{slash}T0_DQS-PadC15)") (class "Default")
      (node (ref "U201") (pin "C15") (pinfunction "IO_L3N/T0_DQS_C15") (pintype "bidirectional"))
    )
    (net (code "574") (name "unconnected-(U201F-IO_L3P{slash}T0_DQS-PadC14)") (class "Default")
      (node (ref "U201") (pin "C14") (pinfunction "IO_L3P/T0_DQS_C14") (pintype "bidirectional"))
    )
    (net (code "575") (name "unconnected-(U201F-IO_L4N{slash}T0-PadE14)") (class "Default")
      (node (ref "U201") (pin "E14") (pinfunction "IO_L4N/T0_E14") (pintype "bidirectional"))
    )
    (net (code "576") (name "unconnected-(U201F-IO_L4P{slash}T0-PadE13)") (class "Default")
      (node (ref "U201") (pin "E13") (pinfunction "IO_L4P/T0_E13") (pintype "bidirectional"))
    )
    (net (code "577") (name "unconnected-(U201F-IO_L5N{slash}T0-PadD16)") (class "Default")
      (node (ref "U201") (pin "D16") (pinfunction "IO_L5N/T0_D16") (pintype "bidirectional"))
    )
    (net (code "578") (name "unconnected-(U201F-IO_L5P{slash}T0-PadE16)") (class "Default")
      (node (ref "U201") (pin "E16") (pinfunction "IO_L5P/T0_E16") (pintype "bidirectional"))
    )
    (net (code "579") (name "unconnected-(U201F-IO_L6N{slash}T0{slash}VREF-PadD15)") (class "Default")
      (node (ref "U201") (pin "D15") (pinfunction "IO_L6N/T0/VREF_D15") (pintype "bidirectional"))
    )
    (net (code "580") (name "unconnected-(U201F-IO_L6P{slash}T0-PadD14)") (class "Default")
      (node (ref "U201") (pin "D14") (pinfunction "IO_L6P/T0_D14") (pintype "bidirectional"))
    )
    (net (code "581") (name "unconnected-(U201F-IO_L7N{slash}T1-PadB16)") (class "Default")
      (node (ref "U201") (pin "B16") (pinfunction "IO_L7N/T1_B16") (pintype "bidirectional"))
    )
    (net (code "582") (name "unconnected-(U201F-IO_L7P{slash}T1-PadB15)") (class "Default")
      (node (ref "U201") (pin "B15") (pinfunction "IO_L7P/T1_B15") (pintype "bidirectional"))
    )
    (net (code "583") (name "unconnected-(U201F-IO_L8N{slash}T1-PadB13)") (class "Default")
      (node (ref "U201") (pin "B13") (pinfunction "IO_L8N/T1_B13") (pintype "bidirectional"))
    )
    (net (code "584") (name "unconnected-(U201F-IO_L8P{slash}T1-PadC13)") (class "Default")
      (node (ref "U201") (pin "C13") (pinfunction "IO_L8P/T1_C13") (pintype "bidirectional"))
    )
    (net (code "585") (name "unconnected-(U201F-IO_L11N{slash}T1{slash}SRCC-PadB18)") (class "Default")
      (node (ref "U201") (pin "B18") (pinfunction "IO_L11N/T1/SRCC_B18") (pintype "bidirectional"))
    )
    (net (code "586") (name "unconnected-(U201F-IO_L11P{slash}T1{slash}SRCC-PadB17)") (class "Default")
      (node (ref "U201") (pin "B17") (pinfunction "IO_L11P/T1/SRCC_B17") (pintype "bidirectional"))
    )
    (net (code "587") (name "unconnected-(U201F-IO_L12N{slash}T1{slash}MRCC-PadC17)") (class "Default")
      (node (ref "U201") (pin "C17") (pinfunction "IO_L12N/T1/MRCC_C17") (pintype "bidirectional"))
    )
    (net (code "588") (name "unconnected-(U201F-IO_L13N{slash}T2{slash}MRCC-PadC19)") (class "Default")
      (node (ref "U201") (pin "C19") (pinfunction "IO_L13N/T2/MRCC_C19") (pintype "bidirectional"))
    )
    (net (code "589") (name "unconnected-(U201F-IO_L13P{slash}T2{slash}MRCC-PadC18)") (class "Default")
      (node (ref "U201") (pin "C18") (pinfunction "IO_L13P/T2/MRCC_C18") (pintype "bidirectional"))
    )
    (net (code "590") (name "unconnected-(U201F-IO_L15N{slash}T2_DQS-PadE18)") (class "Default")
      (node (ref "U201") (pin "E18") (pinfunction "IO_L15N/T2_DQS_E18") (pintype "bidirectional"))
    )
    (net (code "591") (name "unconnected-(U201F-IO_L16P{slash}T2-PadB20)") (class "Default")
      (node (ref "U201") (pin "B20") (pinfunction "IO_L16P/T2_B20") (pintype "bidirectional"))
    )
    (net (code "592") (name "unconnected-(U201F-IO_L18P{slash}T2-PadF19)") (class "Default")
      (node (ref "U201") (pin "F19") (pinfunction "IO_L18P/T2_F19") (pintype "bidirectional"))
    )
    (net (code "593") (name "unconnected-(U201F-IO_L19N{slash}T3{slash}VREF-PadC20)") (class "Default")
      (node (ref "U201") (pin "C20") (pinfunction "IO_L19N/T3/VREF_C20") (pintype "bidirectional"))
    )
    (net (code "594") (name "unconnected-(U201F-IO_L19P{slash}T3-PadD20)") (class "Default")
      (node (ref "U201") (pin "D20") (pinfunction "IO_L19P/T3_D20") (pintype "bidirectional"))
    )
    (net (code "595") (name "unconnected-(U201F-IO_L20N{slash}T3-PadB22)") (class "Default")
      (node (ref "U201") (pin "B22") (pinfunction "IO_L20N/T3_B22") (pintype "bidirectional"))
    )
    (net (code "596") (name "unconnected-(U201F-IO_L20P{slash}T3-PadC22)") (class "Default")
      (node (ref "U201") (pin "C22") (pinfunction "IO_L20P/T3_C22") (pintype "bidirectional"))
    )
    (net (code "597") (name "unconnected-(U201F-IO_L21P{slash}T3_DQS-PadB21)") (class "Default")
      (node (ref "U201") (pin "B21") (pinfunction "IO_L21P/T3_DQS_B21") (pintype "bidirectional"))
    )
    (net (code "598") (name "unconnected-(U201F-IO_L22P{slash}T3-PadE22)") (class "Default")
      (node (ref "U201") (pin "E22") (pinfunction "IO_L22P/T3_E22") (pintype "bidirectional"))
    )
    (net (code "599") (name "unconnected-(U201G-MGTPTXN1-PadC5)") (class "Default")
      (node (ref "U201") (pin "C5") (pinfunction "MGTPTXN1_C5") (pintype "bidirectional"))
    )
    (net (code "600") (name "unconnected-(U201G-MGTPTXP1-PadD5)") (class "Default")
      (node (ref "U201") (pin "D5") (pinfunction "MGTPTXP1_D5") (pintype "bidirectional"))
    )
    (net (code "601") (name "unconnected-(U201H-IO_0-PadT3)") (class "Default")
      (node (ref "U201") (pin "T3") (pinfunction "IO_0_T3") (pintype "bidirectional"))
    )
    (net (code "602") (name "unconnected-(U201H-IO_25-PadU7)") (class "Default")
      (node (ref "U201") (pin "U7") (pinfunction "IO_25_U7") (pintype "bidirectional"))
    )
    (net (code "603") (name "unconnected-(U201H-IO_L13N{slash}T2{slash}MRCC-PadT4)") (class "Default")
      (node (ref "U201") (pin "T4") (pinfunction "IO_L13N/T2/MRCC_T4") (pintype "bidirectional"))
    )
    (net (code "604") (name "unconnected-(U201H-IO_L20N{slash}T3-PadAB6)") (class "Default")
      (node (ref "U201") (pin "AB6") (pinfunction "IO_L20N/T3_AB6") (pintype "bidirectional"))
    )
    (net (code "605") (name "unconnected-(U201H-IO_L20P{slash}T3-PadAB7)") (class "Default")
      (node (ref "U201") (pin "AB7") (pinfunction "IO_L20P/T3_AB7") (pintype "bidirectional"))
    )
    (net (code "606") (name "unconnected-(U201H-IO_L22N{slash}T3-PadAB8)") (class "Default")
      (node (ref "U201") (pin "AB8") (pinfunction "IO_L22N/T3_AB8") (pintype "bidirectional"))
    )
    (net (code "607") (name "unconnected-(U201H-IO_L22P{slash}T3-PadAA8)") (class "Default")
      (node (ref "U201") (pin "AA8") (pinfunction "IO_L22P/T3_AA8") (pintype "bidirectional"))
    )
    (net (code "608") (name "unconnected-(U201H-IO_L23N{slash}T3-PadY7)") (class "Default")
      (node (ref "U201") (pin "Y7") (pinfunction "IO_L23N/T3_Y7") (pintype "bidirectional"))
    )
    (net (code "609") (name "unconnected-(U201H-IO_L23P{slash}T3-PadY8)") (class "Default")
      (node (ref "U201") (pin "Y8") (pinfunction "IO_L23P/T3_Y8") (pintype "bidirectional"))
    )
    (net (code "610") (name "unconnected-(U201H-IO_L24N{slash}T3-PadY9)") (class "Default")
      (node (ref "U201") (pin "Y9") (pinfunction "IO_L24N/T3_Y9") (pintype "bidirectional"))
    )
    (net (code "611") (name "unconnected-(U201H-IO_L24P{slash}T3-PadW9)") (class "Default")
      (node (ref "U201") (pin "W9") (pinfunction "IO_L24P/T3_W9") (pintype "bidirectional"))
    )
    (net (code "612") (name "unconnected-(U201I-IO_0-PadF4)") (class "Default")
      (node (ref "U201") (pin "F4") (pinfunction "IO_0_F4") (pintype "bidirectional"))
    )
    (net (code "613") (name "unconnected-(U201I-IO_25-PadL6)") (class "Default")
      (node (ref "U201") (pin "L6") (pinfunction "IO_25_L6") (pintype "bidirectional"))
    )
    (net (code "614") (name "unconnected-(U201I-IO_L2N{slash}T0{slash}AD12N-PadB2)") (class "Default")
      (node (ref "U201") (pin "B2") (pinfunction "IO_L2N/T0/AD12N_B2") (pintype "bidirectional"))
    )
    (net (code "615") (name "unconnected-(U201I-IO_L2P{slash}T0{slash}AD12P-PadC2)") (class "Default")
      (node (ref "U201") (pin "C2") (pinfunction "IO_L2P/T0/AD12P_C2") (pintype "bidirectional"))
    )
    (net (code "616") (name "unconnected-(U201I-IO_L3N{slash}T0_DQS{slash}AD5N-PadD1)") (class "Default")
      (node (ref "U201") (pin "D1") (pinfunction "IO_L3N/T0_DQS/AD5N_D1") (pintype "bidirectional"))
    )
    (net (code "617") (name "unconnected-(U201I-IO_L3P{slash}T0_DQS{slash}AD5P-PadE1)") (class "Default")
      (node (ref "U201") (pin "E1") (pinfunction "IO_L3P/T0_DQS/AD5P_E1") (pintype "bidirectional"))
    )
    (net (code "618") (name "unconnected-(U201I-IO_L4N{slash}T0-PadD2)") (class "Default")
      (node (ref "U201") (pin "D2") (pinfunction "IO_L4N/T0_D2") (pintype "bidirectional"))
    )
    (net (code "619") (name "unconnected-(U201I-IO_L4P{slash}T0-PadE2)") (class "Default")
      (node (ref "U201") (pin "E2") (pinfunction "IO_L4P/T0_E2") (pintype "bidirectional"))
    )
    (net (code "620") (name "unconnected-(U201I-IO_L5N{slash}T0{slash}AD13N-PadF1)") (class "Default")
      (node (ref "U201") (pin "F1") (pinfunction "IO_L5N/T0/AD13N_F1") (pintype "bidirectional"))
    )
    (net (code "621") (name "unconnected-(U201I-IO_L5P{slash}T0{slash}AD13P-PadG1)") (class "Default")
      (node (ref "U201") (pin "G1") (pinfunction "IO_L5P/T0/AD13P_G1") (pintype "bidirectional"))
    )
    (net (code "622") (name "unconnected-(U201I-IO_L6P{slash}T0-PadF3)") (class "Default")
      (node (ref "U201") (pin "F3") (pinfunction "IO_L6P/T0_F3") (pintype "bidirectional"))
    )
    (net (code "623") (name "unconnected-(U201I-IO_L7N{slash}T1{slash}AD6N-PadJ1)") (class "Default")
      (node (ref "U201") (pin "J1") (pinfunction "IO_L7N/T1/AD6N_J1") (pintype "bidirectional"))
    )
    (net (code "624") (name "unconnected-(U201I-IO_L7P{slash}T1{slash}AD6P-PadK1)") (class "Default")
      (node (ref "U201") (pin "K1") (pinfunction "IO_L7P/T1/AD6P_K1") (pintype "bidirectional"))
    )
    (net (code "625") (name "unconnected-(U201I-IO_L8N{slash}T1{slash}AD14N-PadG2)") (class "Default")
      (node (ref "U201") (pin "G2") (pinfunction "IO_L8N/T1/AD14N_G2") (pintype "bidirectional"))
    )
    (net (code "626") (name "unconnected-(U201I-IO_L8P{slash}T1{slash}AD14P-PadH2)") (class "Default")
      (node (ref "U201") (pin "H2") (pinfunction "IO_L8P/T1/AD14P_H2") (pintype "bidirectional"))
    )
    (net (code "627") (name "unconnected-(U201I-IO_L9N{slash}T1_DQS{slash}AD7N-PadJ2)") (class "Default")
      (node (ref "U201") (pin "J2") (pinfunction "IO_L9N/T1_DQS/AD7N_J2") (pintype "bidirectional"))
    )
    (net (code "628") (name "unconnected-(U201I-IO_L9P{slash}T1_DQS{slash}AD7P-PadK2)") (class "Default")
      (node (ref "U201") (pin "K2") (pinfunction "IO_L9P/T1_DQS/AD7P_K2") (pintype "bidirectional"))
    )
    (net (code "629") (name "unconnected-(U201I-IO_L10N{slash}T1{slash}AD15N-PadH5)") (class "Default")
      (node (ref "U201") (pin "H5") (pinfunction "IO_L10N/T1/AD15N_H5") (pintype "bidirectional"))
    )
    (net (code "630") (name "unconnected-(U201I-IO_L10P{slash}T1{slash}AD15P-PadJ5)") (class "Default")
      (node (ref "U201") (pin "J5") (pinfunction "IO_L10P/T1/AD15P_J5") (pintype "bidirectional"))
    )
    (net (code "631") (name "unconnected-(U201I-IO_L11N{slash}T1{slash}SRCC-PadG3)") (class "Default")
      (node (ref "U201") (pin "G3") (pinfunction "IO_L11N/T1/SRCC_G3") (pintype "bidirectional"))
    )
    (net (code "632") (name "unconnected-(U201I-IO_L11P{slash}T1{slash}SRCC-PadH3)") (class "Default")
      (node (ref "U201") (pin "H3") (pinfunction "IO_L11P/T1/SRCC_H3") (pintype "bidirectional"))
    )
    (net (code "633") (name "unconnected-(U201I-IO_L12N{slash}T1{slash}MRCC-PadG4)") (class "Default")
      (node (ref "U201") (pin "G4") (pinfunction "IO_L12N/T1/MRCC_G4") (pintype "bidirectional"))
    )
    (net (code "634") (name "unconnected-(U201I-IO_L12P{slash}T1{slash}MRCC-PadH4)") (class "Default")
      (node (ref "U201") (pin "H4") (pinfunction "IO_L12P/T1/MRCC_H4") (pintype "bidirectional"))
    )
    (net (code "635") (name "unconnected-(U201I-IO_L13N{slash}T2{slash}MRCC-PadJ4)") (class "Default")
      (node (ref "U201") (pin "J4") (pinfunction "IO_L13N/T2/MRCC_J4") (pintype "bidirectional"))
    )
    (net (code "636") (name "unconnected-(U201I-IO_L13P{slash}T2{slash}MRCC-PadK4)") (class "Default")
      (node (ref "U201") (pin "K4") (pinfunction "IO_L13P/T2/MRCC_K4") (pintype "bidirectional"))
    )
    (net (code "637") (name "unconnected-(U201I-IO_L14N{slash}T2{slash}SRCC-PadK3)") (class "Default")
      (node (ref "U201") (pin "K3") (pinfunction "IO_L14N/T2/SRCC_K3") (pintype "bidirectional"))
    )
    (net (code "638") (name "unconnected-(U201I-IO_L14P{slash}T2{slash}SRCC-PadL3)") (class "Default")
      (node (ref "U201") (pin "L3") (pinfunction "IO_L14P/T2/SRCC_L3") (pintype "bidirectional"))
    )
    (net (code "639") (name "unconnected-(U201I-IO_L15N{slash}T2_DQS-PadL1)") (class "Default")
      (node (ref "U201") (pin "L1") (pinfunction "IO_L15N/T2_DQS_L1") (pintype "bidirectional"))
    )
    (net (code "640") (name "unconnected-(U201I-IO_L15P{slash}T2_DQS-PadM1)") (class "Default")
      (node (ref "U201") (pin "M1") (pinfunction "IO_L15P/T2_DQS_M1") (pintype "bidirectional"))
    )
    (net (code "641") (name "unconnected-(U201I-IO_L16N{slash}T2-PadM2)") (class "Default")
      (node (ref "U201") (pin "M2") (pinfunction "IO_L16N/T2_M2") (pintype "bidirectional"))
    )
    (net (code "642") (name "unconnected-(U201I-IO_L16P{slash}T2-PadM3)") (class "Default")
      (node (ref "U201") (pin "M3") (pinfunction "IO_L16P/T2_M3") (pintype "bidirectional"))
    )
    (net (code "643") (name "unconnected-(U201I-IO_L17N{slash}T2-PadJ6)") (class "Default")
      (node (ref "U201") (pin "J6") (pinfunction "IO_L17N/T2_J6") (pintype "bidirectional"))
    )
    (net (code "644") (name "unconnected-(U201I-IO_L17P{slash}T2-PadK6)") (class "Default")
      (node (ref "U201") (pin "K6") (pinfunction "IO_L17P/T2_K6") (pintype "bidirectional"))
    )
    (net (code "645") (name "unconnected-(U201I-IO_L18N{slash}T2-PadL4)") (class "Default")
      (node (ref "U201") (pin "L4") (pinfunction "IO_L18N/T2_L4") (pintype "bidirectional"))
    )
    (net (code "646") (name "unconnected-(U201I-IO_L18P{slash}T2-PadL5)") (class "Default")
      (node (ref "U201") (pin "L5") (pinfunction "IO_L18P/T2_L5") (pintype "bidirectional"))
    )
    (net (code "647") (name "unconnected-(U401A-DATA_CLK_N-PadH11)") (class "Default")
      (node (ref "U401") (pin "H11") (pinfunction "DATA_CLK_N_H11") (pintype "bidirectional"))
    )
    (net (code "648") (name "unconnected-(U401A-RX_FRAME_N-PadG7)") (class "Default")
      (node (ref "U401") (pin "G7") (pinfunction "RX_FRAME_N_G7") (pintype "bidirectional"))
    )
    (net (code "649") (name "unconnected-(U401A-XTALP-PadM11)") (class "Default")
      (node (ref "U401") (pin "M11") (pinfunction "XTALP_M11") (pintype "bidirectional"))
    )
    (net (code "650") (name "unconnected-(U401C-AUXDAC1-PadB3)") (class "Default")
      (node (ref "U401") (pin "B3") (pinfunction "AUXDAC1_B3") (pintype "bidirectional"))
    )
    (net (code "651") (name "unconnected-(U401C-AUXDAC2-PadC3)") (class "Default")
      (node (ref "U401") (pin "C3") (pinfunction "AUXDAC2_C3") (pintype "bidirectional"))
    )
    (net (code "652") (name "unconnected-(U701-HPOUTLN{slash}LOUTLN-Pad21)") (class "Default")
      (node (ref "U701") (pin "21") (pinfunction "HPOUTLN/LOUTLN_21") (pintype "bidirectional"))
    )
    (net (code "653") (name "unconnected-(U701-HPOUTRN{slash}LOUTRN-Pad25)") (class "Default")
      (node (ref "U701") (pin "25") (pinfunction "HPOUTRN/LOUTRN_25") (pintype "bidirectional"))
    )
    (net (code "654") (name "unconnected-(U701-XTALO-Pad38)") (class "Default")
      (node (ref "U701") (pin "38") (pinfunction "XTALO_38") (pintype "bidirectional"))
    )
    (net (code "655") (name "unconnected-(U902-XB-Pad2)") (class "Default")
      (node (ref "U902") (pin "2") (pinfunction "XB_2") (pintype "bidirectional"))
    )
    (net (code "656") (name "unconnected-(U1001-READY-Pad5)") (class "Default")
      (node (ref "U1001") (pin "5") (pinfunction "READY_5") (pintype "bidirectional"))
    )
    (net (code "657") (name "unconnected-(U1205-PG-Pad5)") (class "Default")
      (node (ref "U1205") (pin "5") (pinfunction "PG_5") (pintype "bidirectional"))
    )
    (net (code "658") (name "unconnected-(USB1001-SB1-PadA8)") (class "Default")
      (node (ref "USB1001") (pin "A8") (pinfunction "SB1_A8") (pintype "bidirectional"))
    )
    (net (code "659") (name "unconnected-(USB1001-SB2-PadB8)") (class "Default")
      (node (ref "USB1001") (pin "B8") (pinfunction "SB2_B8") (pintype "bidirectional"))
    )
    (net (code "660") (name "~{5V0_TRX_BIAS_T1_OC}") (class "Default")
      (node (ref "R503") (pin "1") (pinfunction "1_1") (pintype "passive"))
      (node (ref "U201") (pin "A20") (pinfunction "IO_L16N/T2_A20") (pintype "bidirectional"))
      (node (ref "U501") (pin "4") (pinfunction "~{FAULT}_4") (pintype "bidirectional"))
    )
    (net (code "661") (name "~{5V0_TRX_BIAS_T2_OC}") (class "Default")
      (node (ref "R504") (pin "1") (pinfunction "1_1") (pintype "passive"))
      (node (ref "U201") (pin "A18") (pinfunction "IO_L17P/T2_A18") (pintype "bidirectional"))
      (node (ref "U502") (pin "4") (pinfunction "~{FAULT}_4") (pintype "bidirectional"))
    )
    (net (code "662") (name "~{5V0_TRX_PA1_OC}") (class "Default")
      (node (ref "R509") (pin "1") (pinfunction "1_1") (pintype "passive"))
      (node (ref "U201") (pin "A19") (pinfunction "IO_L17N/T2_A19") (pintype "bidirectional"))
      (node (ref "U503") (pin "4") (pinfunction "~{FAULT}_4") (pintype "bidirectional"))
    )
    (net (code "663") (name "~{5V0_TRX_PA2_OC}") (class "Default")
      (node (ref "R510") (pin "1") (pinfunction "1_1") (pintype "passive"))
      (node (ref "U201") (pin "A21") (pinfunction "IO_L21N/T3_DQS_A21") (pintype "bidirectional"))
      (node (ref "U504") (pin "4") (pinfunction "~{FAULT}_4") (pintype "bidirectional"))
    )
    (net (code "664") (name "~{CLK_MNGR_IRQ}") (class "Default")
      (node (ref "R905") (pin "1") (pinfunction "1_1") (pintype "passive"))
      (node (ref "U201") (pin "U21") (pinfunction "IO_L4N/T0/D5_U21") (pintype "bidirectional"))
      (node (ref "U902") (pin "3") (pinfunction "~{INTR}_3") (pintype "bidirectional"))
    )
    (net (code "665") (name "~{CLK_MNGR_OE}") (class "Default")
      (node (ref "R904") (pin "1") (pinfunction "1_1") (pintype "passive"))
      (node (ref "U201") (pin "T20") (pinfunction "IO_L6N/T0/D8/VREF_T20") (pintype "bidirectional"))
      (node (ref "U902") (pin "7") (pinfunction "~{OE}_7") (pintype "bidirectional"))
    )
    (net (code "666") (name "~{CM4_ACT_LED}") (class "Default")
      (node (ref "D101") (pin "C") (pinfunction "C_C") (pintype "passive"))
      (node (ref "U102") (pin "21") (pinfunction "~{PI_LED_ACT}_21") (pintype "bidirectional"))
    )
    (net (code "667") (name "~{CM4_BTLDR}") (class "Default")
      (node (ref "U1002") (pin "36") (pinfunction "PA22/GPIO6_36") (pintype "bidirectional"))
      (node (ref "U102") (pin "93") (pinfunction "~{RPIBOOT}_93") (pintype "bidirectional"))
    )
    (net (code "668") (name "~{CM4_PWR_LED}") (class "Default")
      (node (ref "Q101") (pin "1") (pinfunction "G_1") (pintype "passive"))
      (node (ref "U102") (pin "95") (pinfunction "~{PI_LED_PWR}_95") (pintype "bidirectional"))
    )
    (net (code "669") (name "~{CODEC_RST}") (class "Default")
      (node (ref "R701") (pin "2") (pinfunction "2_2") (pintype "passive"))
      (node (ref "U201") (pin "Y19") (pinfunction "IO_L13N/T2/MRCC_Y19") (pintype "bidirectional"))
      (node (ref "U701") (pin "27") (pinfunction "~{PD}_27") (pintype "bidirectional"))
    )
    (net (code "670") (name "~{DDR3_CAS}") (class "Default")
      (node (ref "R327") (pin "1") (pinfunction "1_1") (pintype "passive"))
      (node (ref "U201") (pin "T6") (pinfunction "IO_L17N/T2_T6") (pintype "bidirectional"))
      (node (ref "U301") (pin "K3") (pinfunction "~{CAS}_K3") (pintype "bidirectional"))
    )
    (net (code "671") (name "~{DDR3_RAS}") (class "Default")
      (node (ref "R323") (pin "1") (pinfunction "1_1") (pintype "passive"))
      (node (ref "U201") (pin "R6") (pinfunction "IO_L17P/T2_R6") (pintype "bidirectional"))
      (node (ref "U301") (pin "J3") (pinfunction "~{RAS}_J3") (pintype "bidirectional"))
    )
    (net (code "672") (name "~{DDR3_RESET}") (class "Default")
      (node (ref "R302") (pin "2") (pinfunction "2_2") (pintype "passive"))
      (node (ref "R324") (pin "1") (pinfunction "1_1") (pintype "passive"))
      (node (ref "U201") (pin "R4") (pinfunction "IO_L13P/T2/MRCC_R4") (pintype "bidirectional"))
      (node (ref "U301") (pin "T2") (pinfunction "~{RESET}_T2") (pintype "bidirectional"))
    )
    (net (code "673") (name "~{DDR3_WE}") (class "Default")
      (node (ref "R322") (pin "1") (pinfunction "1_1") (pintype "passive"))
      (node (ref "U201") (pin "Y6") (pinfunction "IO_L18P/T2_Y6") (pintype "bidirectional"))
      (node (ref "U301") (pin "L3") (pinfunction "~{WE}_L3") (pintype "bidirectional"))
    )
    (net (code "674") (name "~{FPGA_FLASH_CS}") (class "Default")
      (node (ref "R215") (pin "1") (pinfunction "1_1") (pintype "passive"))
      (node (ref "U201") (pin "T19") (pinfunction "IO_L6P/T0/~{FCS}_T19") (pintype "bidirectional"))
      (node (ref "U202") (pin "1") (pinfunction "~{CS}_1") (pintype "input"))
    )
    (net (code "675") (name "~{FPGA_INIT}") (class "Default")
      (node (ref "D201") (pin "A") (pinfunction "A_A") (pintype "passive"))
      (node (ref "R219") (pin "1") (pinfunction "1_1") (pintype "passive"))
      (node (ref "U1002") (pin "11") (pinfunction "PA01_11") (pintype "bidirectional"))
      (node (ref "U201") (pin "U12") (pinfunction "~{INIT}_U12") (pintype "bidirectional"))
    )
    (net (code "676") (name "~{FPGA_PROGRAM}") (class "Default")
      (node (ref "R214") (pin "1") (pinfunction "1_1") (pintype "passive"))
      (node (ref "TC201") (pin "9") (pinfunction "S_9") (pintype "passive"))
      (node (ref "U201") (pin "N12") (pinfunction "~{PROGRAM}_N12") (pintype "bidirectional"))
    )
    (net (code "677") (name "~{PCIE_CM4_CLK_REQ}") (class "Default")
      (node (ref "R802") (pin "1") (pinfunction "1_1") (pintype "passive"))
      (node (ref "U102") (pin "102") (pinfunction "~{PCIE_CLK_REQ}_102") (pintype "bidirectional"))
      (node (ref "U201") (pin "V22") (pinfunction "IO_L3N/T0_DQS/EMCCLK_V22") (pintype "bidirectional"))
    )
    (net (code "678") (name "~{PCIE_CM4_RST}") (class "Default")
      (node (ref "R801") (pin "1") (pinfunction "1_1") (pintype "passive"))
      (node (ref "U102") (pin "109") (pinfunction "~{PCIE_RST}_109") (pintype "bidirectional"))
      (node (ref "U201") (pin "V20") (pinfunction "IO_L11N/T1/SRCC_V20") (pintype "bidirectional"))
    )
    (net (code "679") (name "~{PCIE_SLOT_CLK_REQ}") (class "Default")
      (node (ref "CON801") (pin "B12") (pinfunction "S_B12") (pintype "passive"))
      (node (ref "R803") (pin "1") (pinfunction "1_1") (pintype "passive"))
      (node (ref "U201") (pin "W20") (pinfunction "IO_L12N/T1/MRCC_W20") (pintype "bidirectional"))
    )
    (net (code "680") (name "~{PCIE_SLOT_RST}") (class "Default")
      (node (ref "C813") (pin "1") (pinfunction "C1_1") (pintype "passive"))
      (node (ref "CON801") (pin "A11") (pinfunction "S_A11") (pintype "passive"))
      (node (ref "R805") (pin "1") (pinfunction "1_1") (pintype "passive"))
      (node (ref "U201") (pin "W21") (pinfunction "IO_L7P/T1/D9_W21") (pintype "bidirectional"))
    )
    (net (code "681") (name "~{PCIE_SLOT_WAKE}") (class "Default")
      (node (ref "CON801") (pin "B11") (pinfunction "S_B11") (pintype "passive"))
      (node (ref "R804") (pin "1") (pinfunction "1_1") (pintype "passive"))
      (node (ref "U201") (pin "W22") (pinfunction "IO_L7N/T1/D10_W22") (pintype "bidirectional"))
    )
    (net (code "682") (name "~{PMC_BTN}") (class "Default")
      (node (ref "C1003") (pin "1") (pinfunction "C1_1") (pintype "passive"))
      (node (ref "R1002") (pin "1") (pinfunction "1_1") (pintype "passive"))
      (node (ref "S1001") (pin "3") (pinfunction "3_3") (pintype "passive"))
      (node (ref "S1001") (pin "4") (pinfunction "4_4") (pintype "passive"))
      (node (ref "U1002") (pin "38") (pinfunction "GPIO8_38") (pintype "bidirectional"))
    )
    (net (code "683") (name "~{PMC_RESET}") (class "Default")
      (node (ref "R1014") (pin "1") (pinfunction "1_1") (pintype "passive"))
      (node (ref "TC1001") (pin "10") (pinfunction "S_10") (pintype "passive"))
      (node (ref "U1002") (pin "33") (pinfunction "~{RESET_COM}_33") (pintype "bidirectional"))
      (node (ref "U1002") (pin "40") (pinfunction "~{RESET}_40") (pintype "bidirectional"))
    )
    (net (code "684") (name "~{SYNTH_RESET}") (class "Default")
      (node (ref "R601") (pin "2") (pinfunction "2_2") (pintype "passive"))
      (node (ref "U201") (pin "AA16") (pinfunction "IO_L1N/T0_AA16") (pintype "bidirectional"))
      (node (ref "U601") (pin "31") (pinfunction "~{RESET}_31") (pintype "bidirectional"))
    )
    (net (code "685") (name "~{SYNTH_SPI_CS}") (class "Default")
      (node (ref "U201") (pin "AA20") (pinfunction "IO_L8P/T1/D11_AA20") (pintype "bidirectional"))
      (node (ref "U601") (pin "25") (pinfunction "~{CS}_25") (pintype "bidirectional"))
    )
    (net (code "686") (name "~{TRX_RESET}") (class "Default")
      (node (ref "U201") (pin "G16") (pinfunction "IO_L2N/T0/AD8N_G16") (pintype "bidirectional"))
      (node (ref "U401") (pin "K5") (pinfunction "~{RESET}_K5") (pintype "bidirectional"))
    )
    (net (code "687") (name "~{TRX_SPI_CS}") (class "Default")
      (node (ref "U201") (pin "G13") (pinfunction "IO_L1N/T0/AD0N_G13") (pintype "bidirectional"))
      (node (ref "U401") (pin "K6") (pinfunction "~{SPI_EN}_K6") (pintype "bidirectional"))
    )
    (net (code "688") (name "~{VBUS_SRC_FAULT}") (class "Default")
      (node (ref "R1011") (pin "1") (pinfunction "1_1") (pintype "passive"))
      (node (ref "U1002") (pin "27") (pinfunction "GPIO3_27") (pintype "bidirectional"))
      (node (ref "U1003") (pin "4") (pinfunction "~{FAULT}_4") (pintype "bidirectional"))
    )
    (net (code "689") (name "~{VIN_REG_ALERT}") (class "Default")
      (node (ref "R1118") (pin "1") (pinfunction "1_1") (pintype "passive"))
      (node (ref "U1102") (pin "29") (pinfunction "~{ALERT}_29") (pintype "bidirectional"))
      (node (ref "U201") (pin "W15") (pinfunction "IO_L16P/T2_W15") (pintype "bidirectional"))
    )
  )
)
